# BEP33_6panel.net
KiCad netlist of a schematic drawn in EAGLE
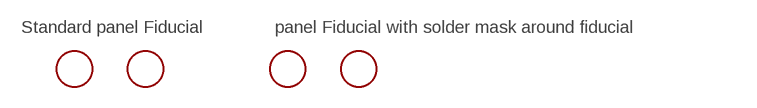
[diagram p0: schematic, sheet 1]
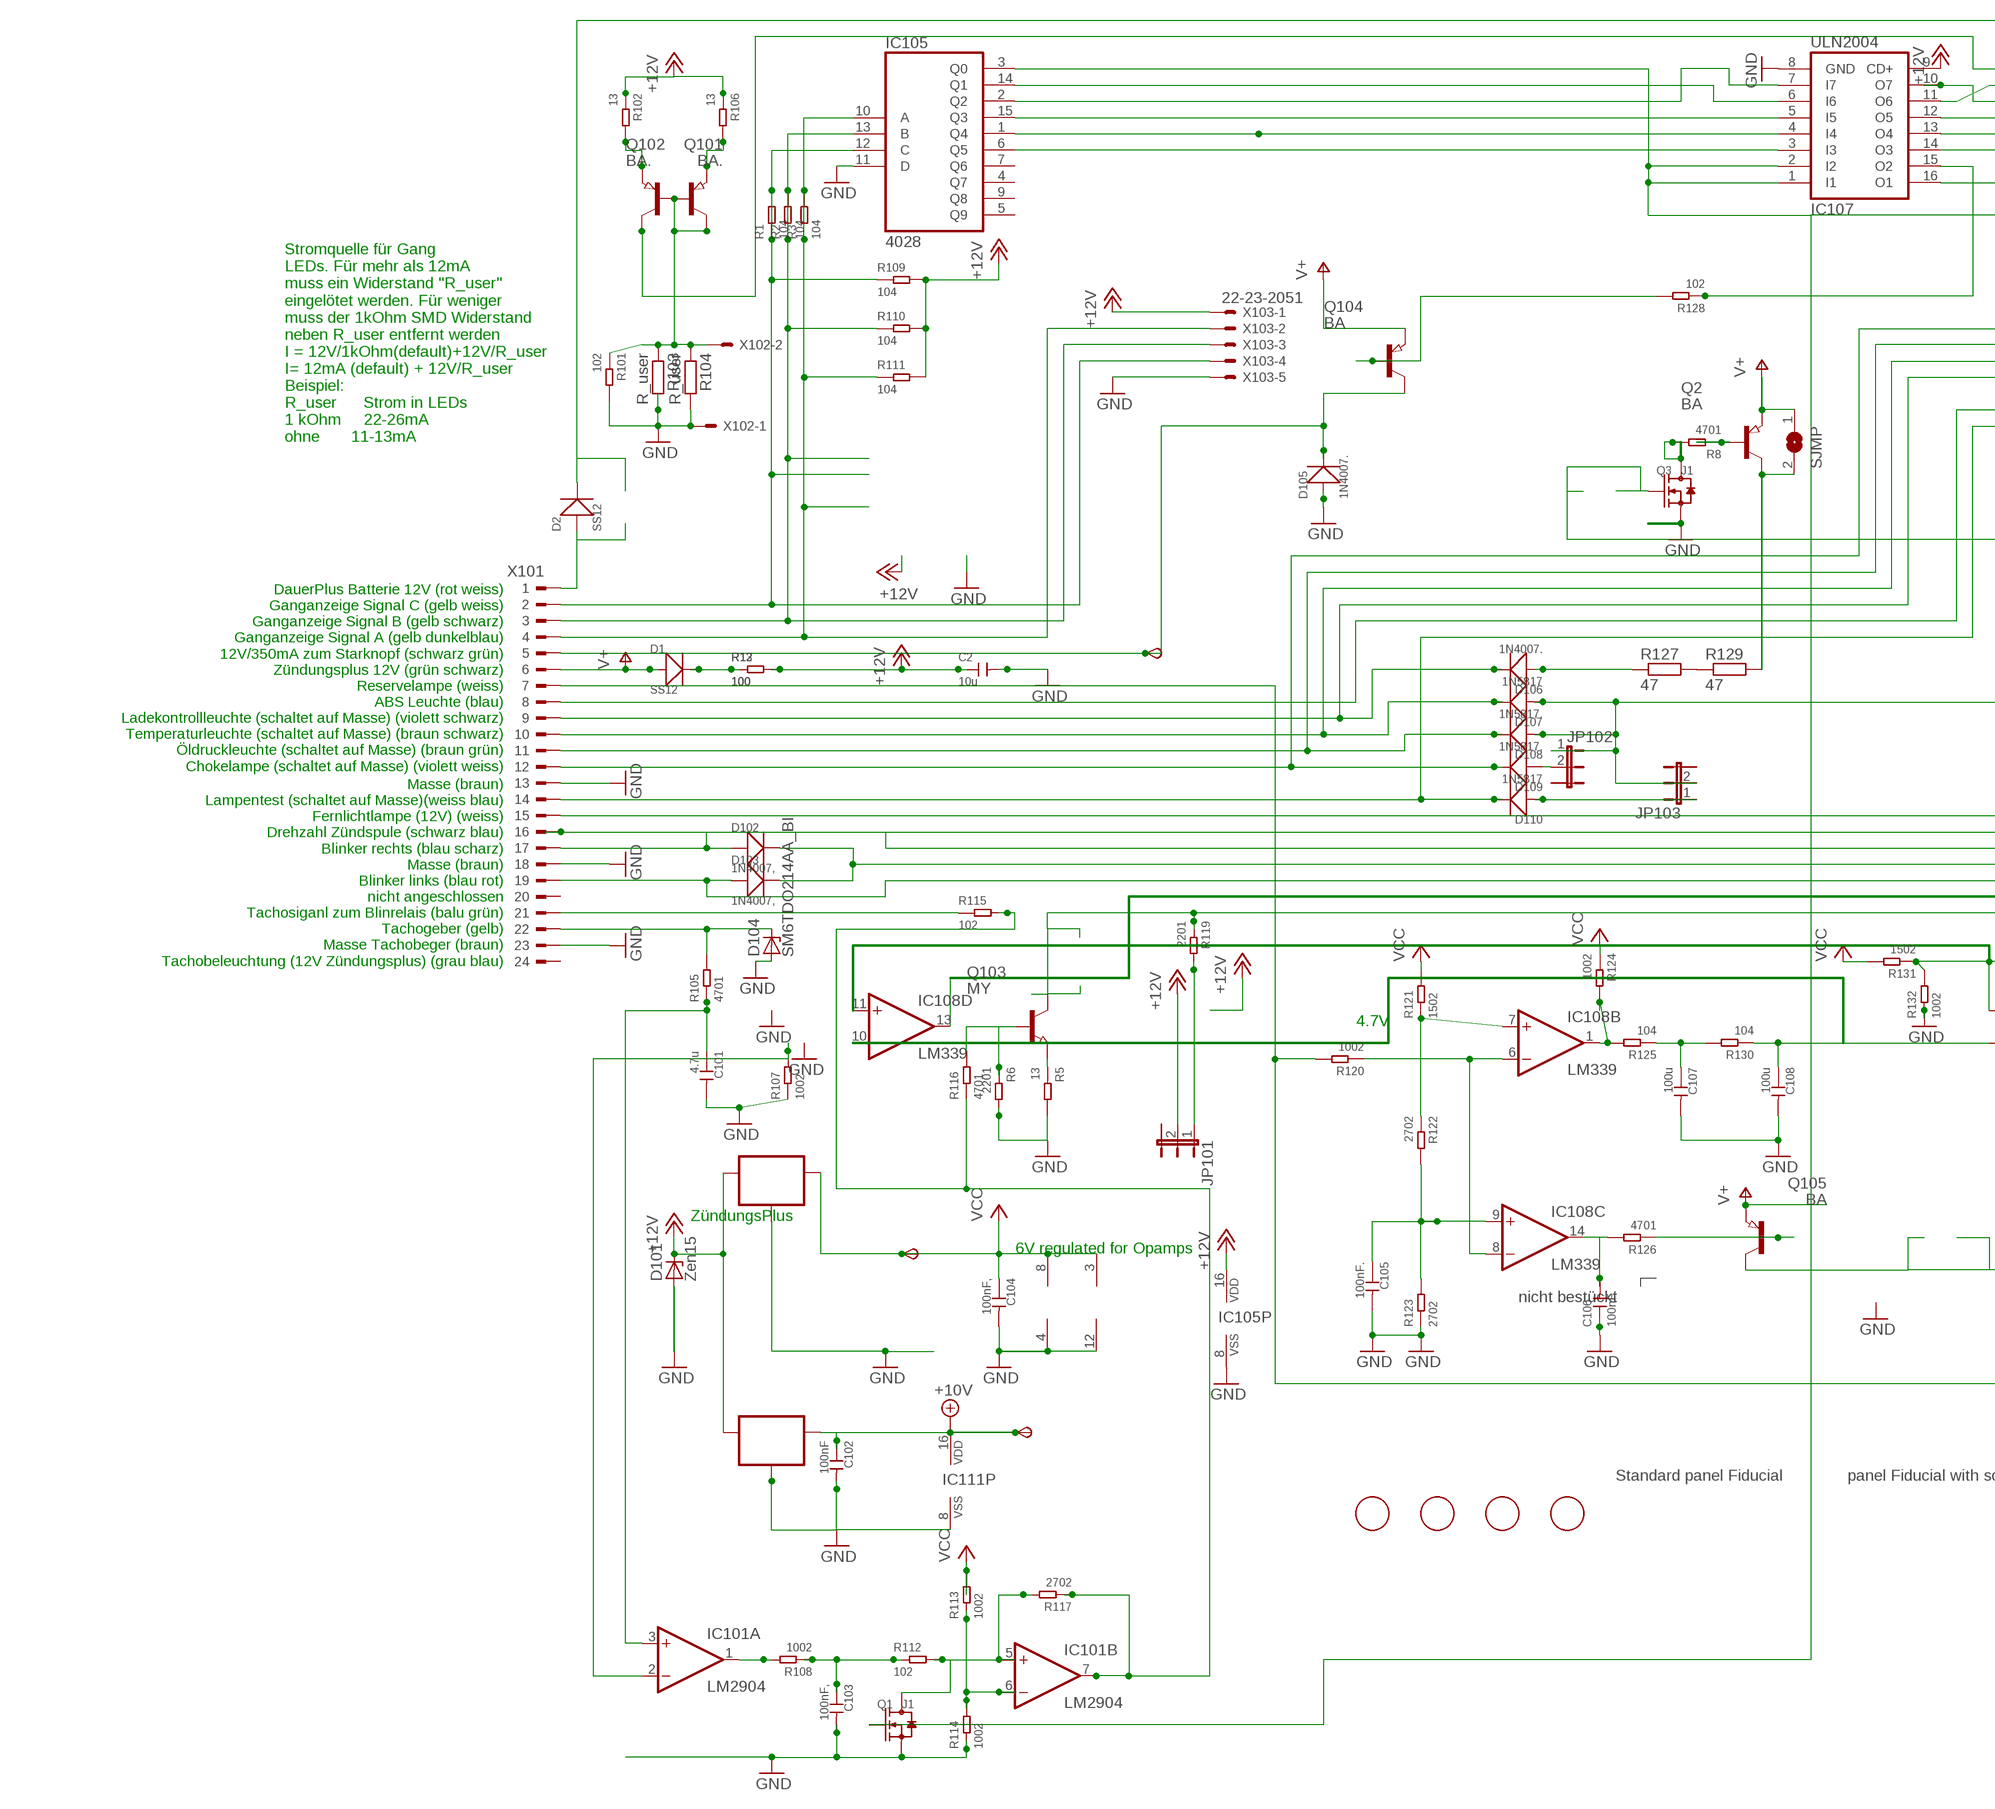
[diagram p1: schematic, sheet 2, part 1 of 2]
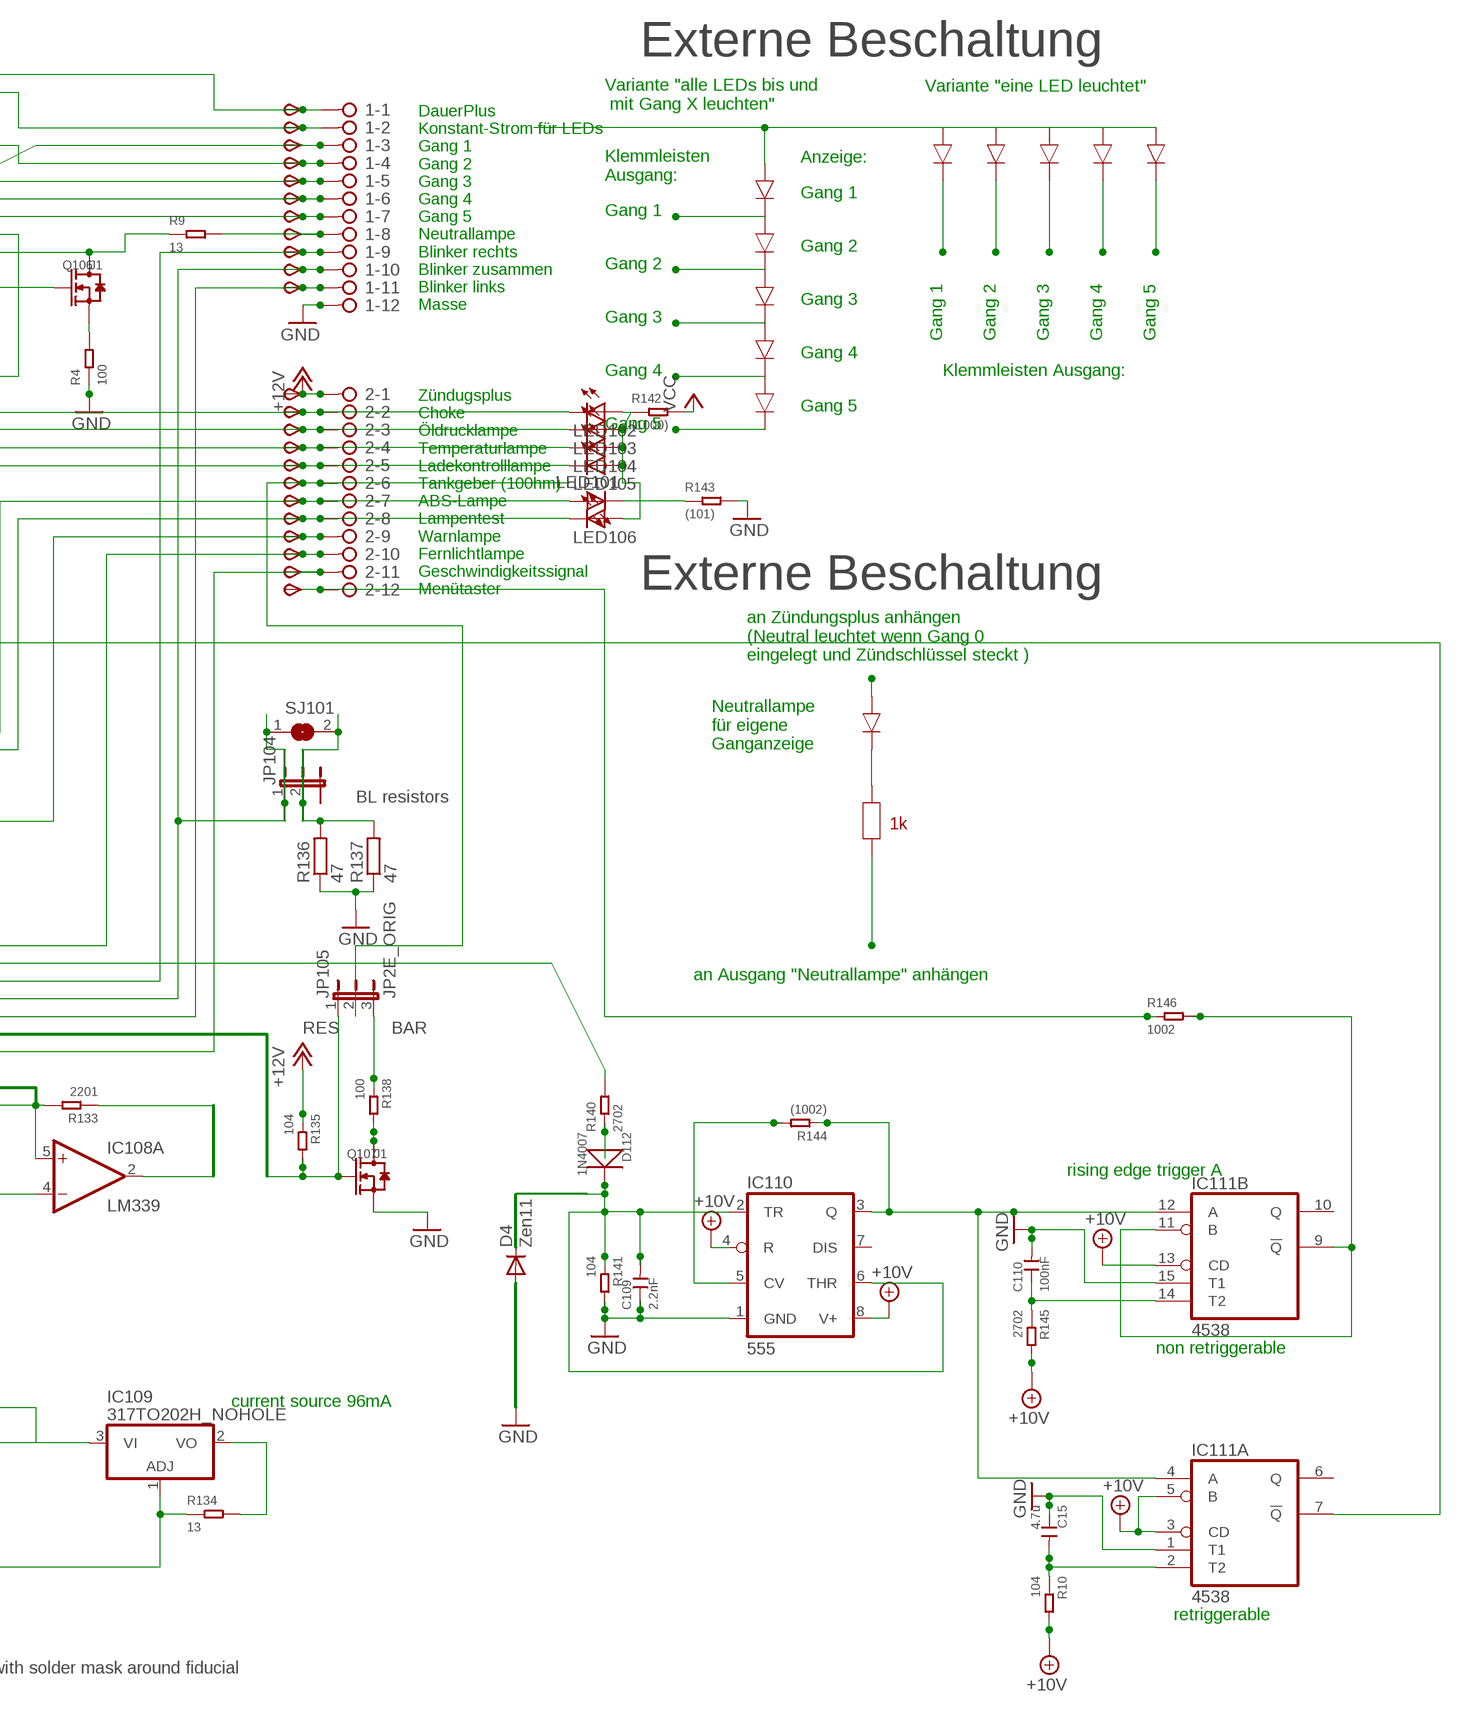
[diagram p2: schematic, sheet 2, part 2 of 2]
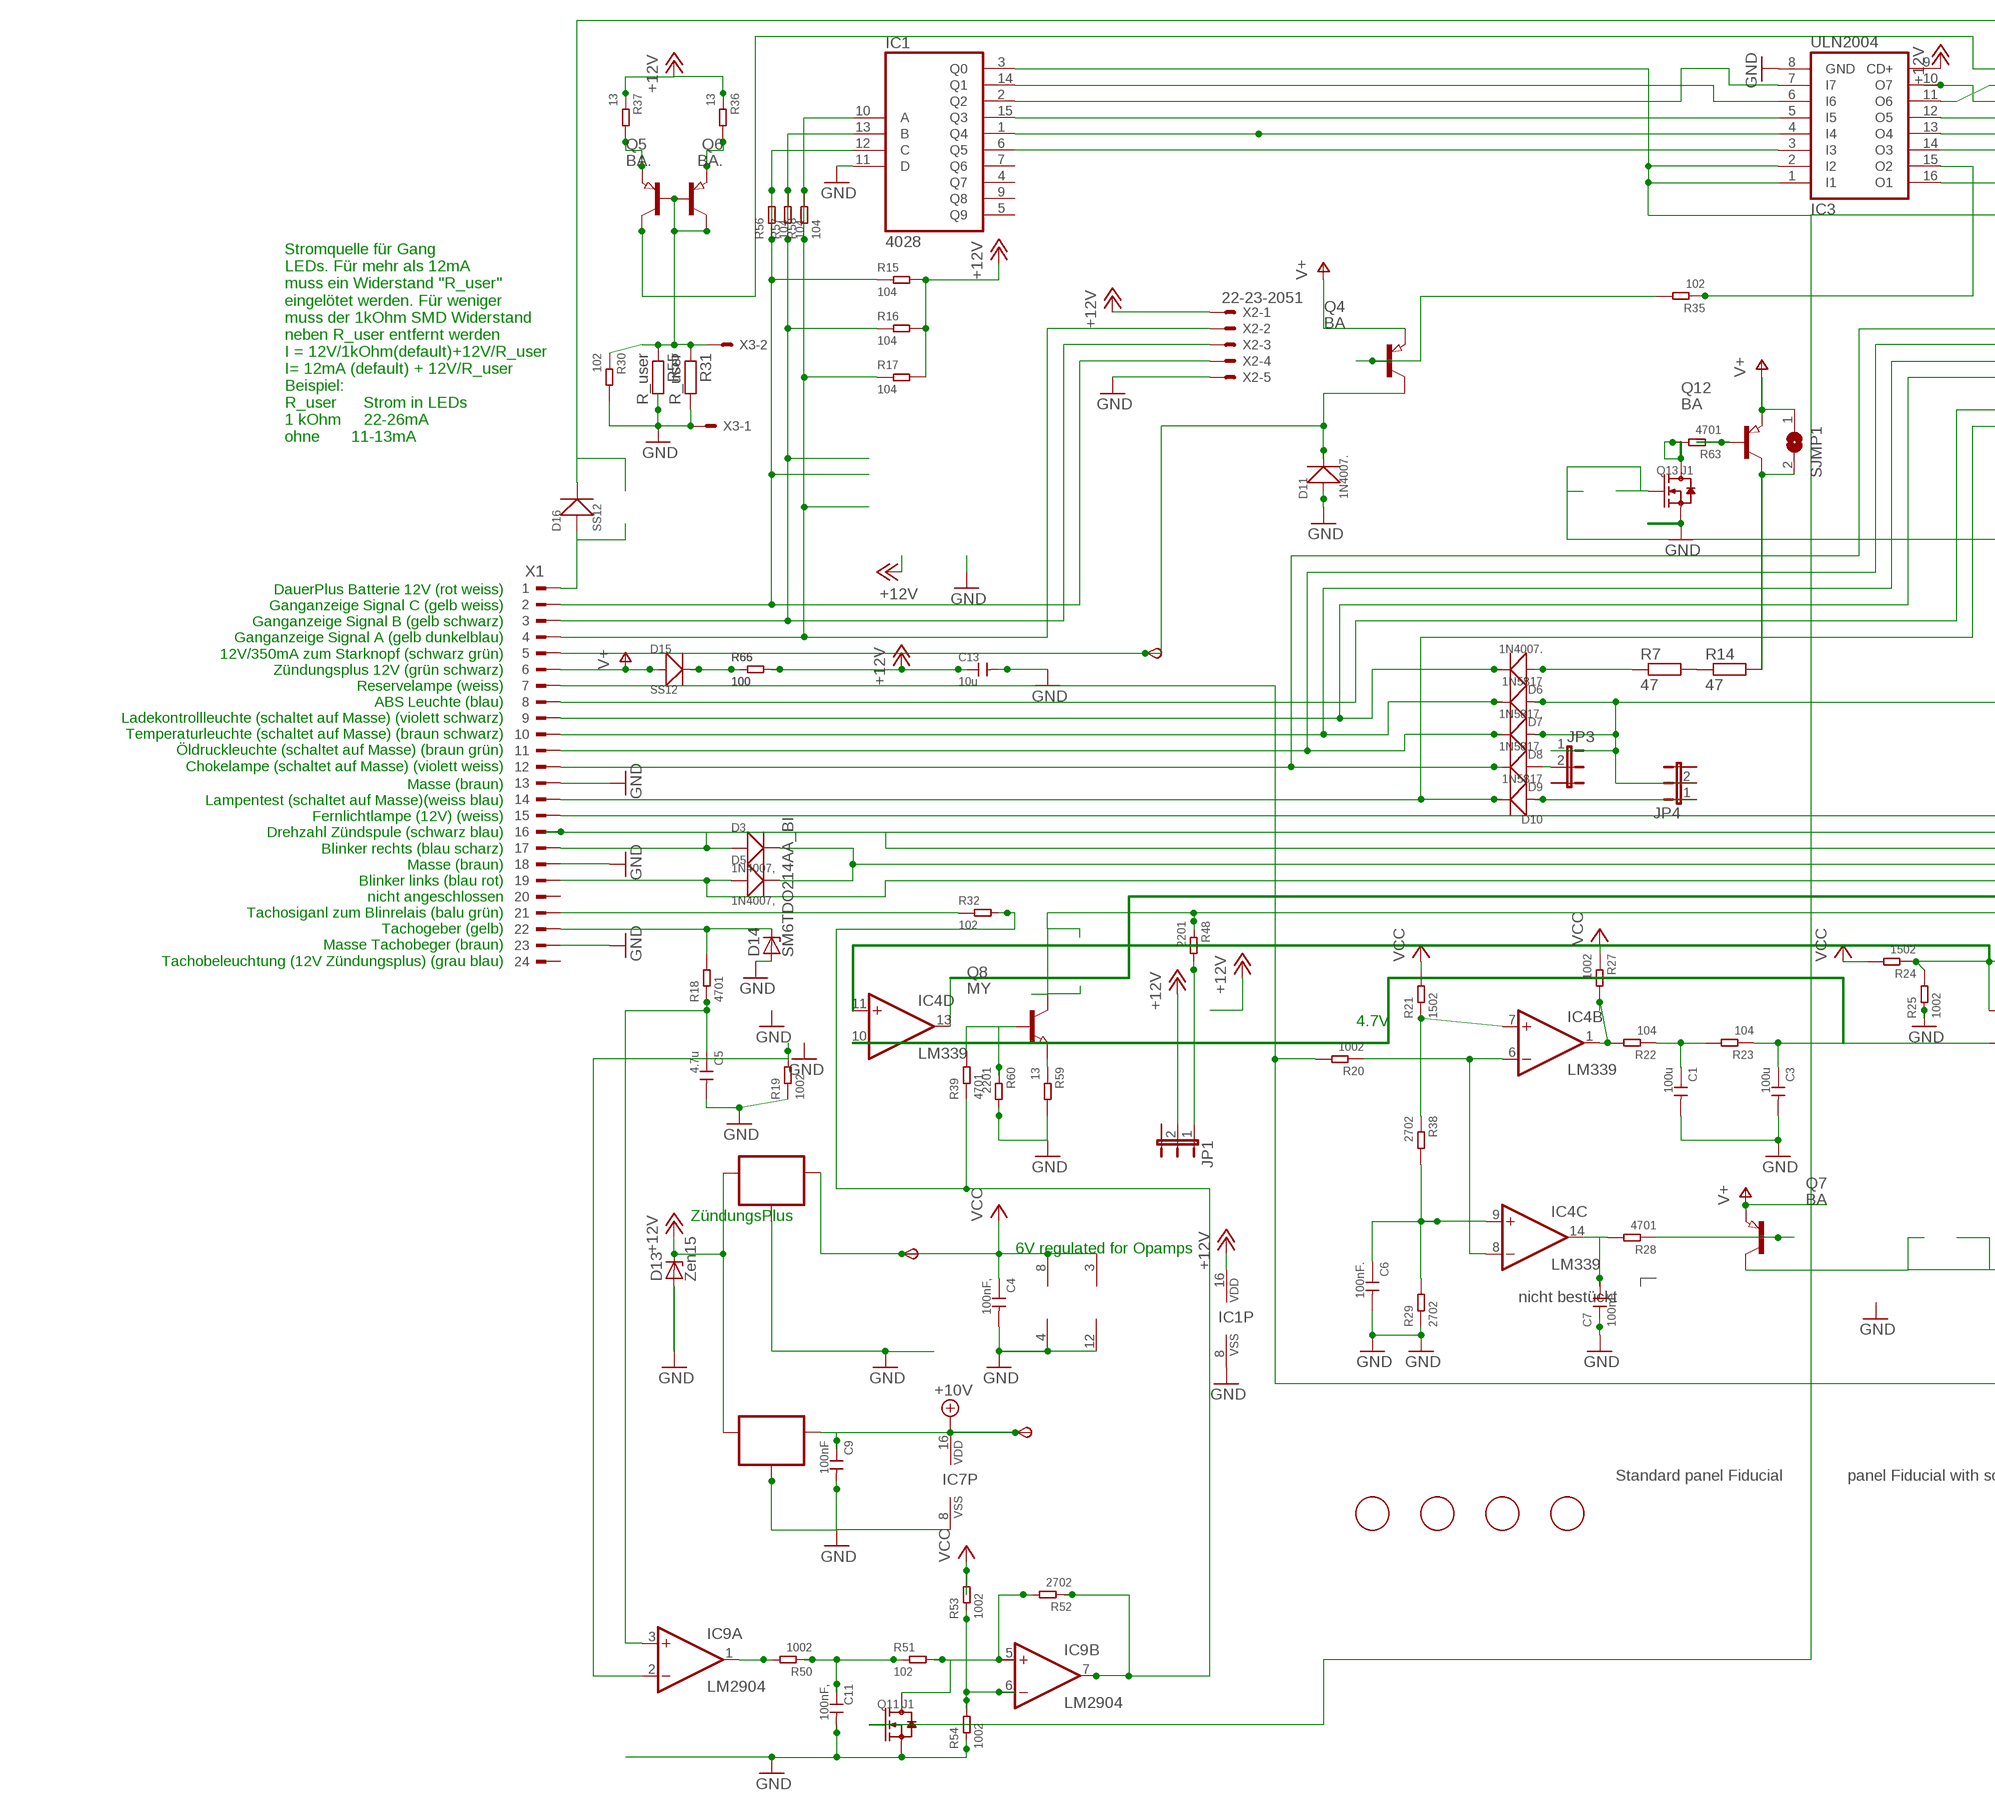
[diagram p3: schematic, sheet 3, part 1 of 2]
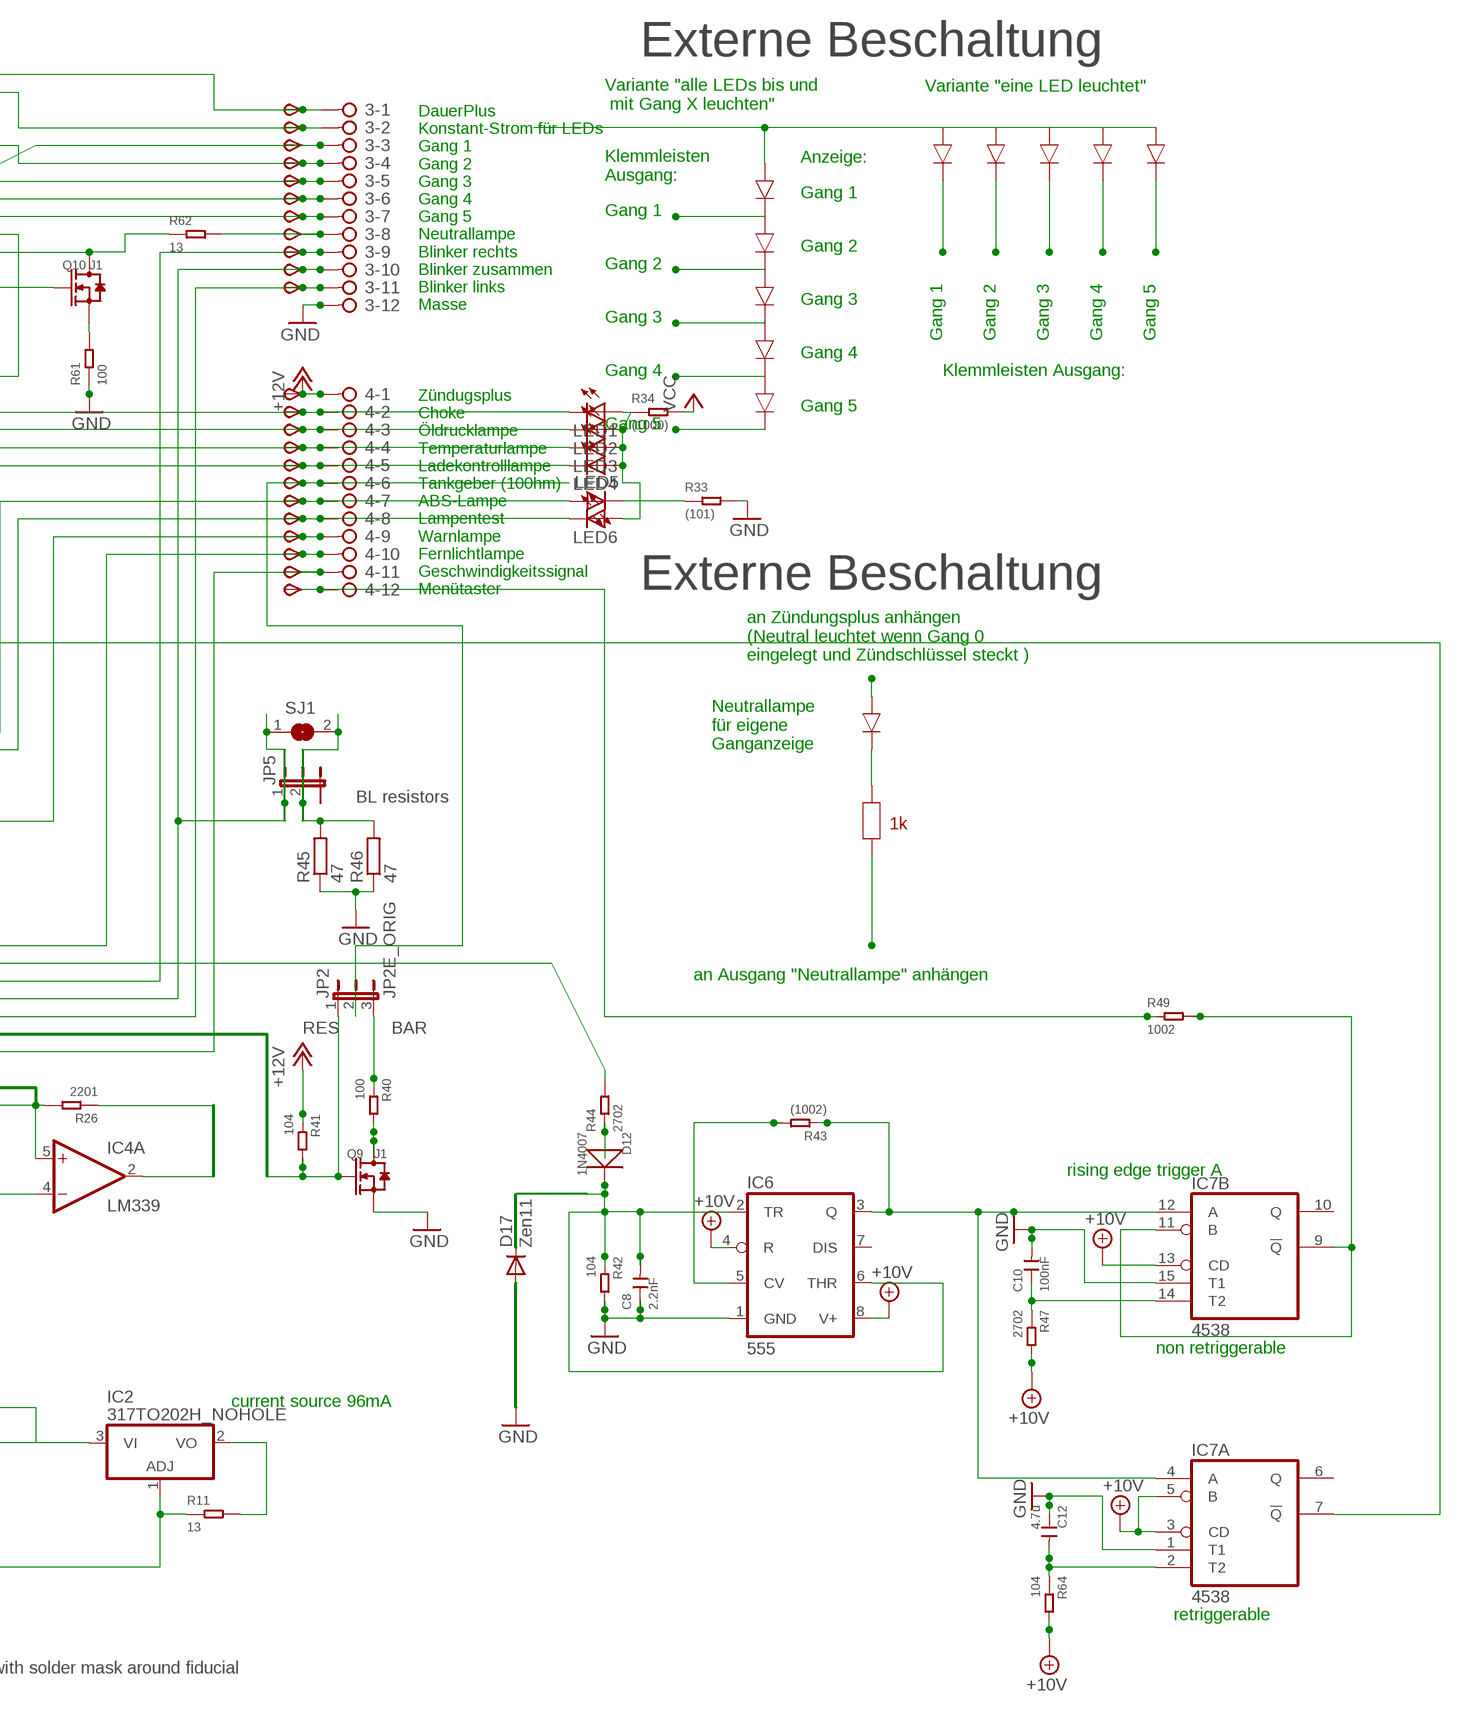
[diagram p4: schematic, sheet 3, part 2 of 2]
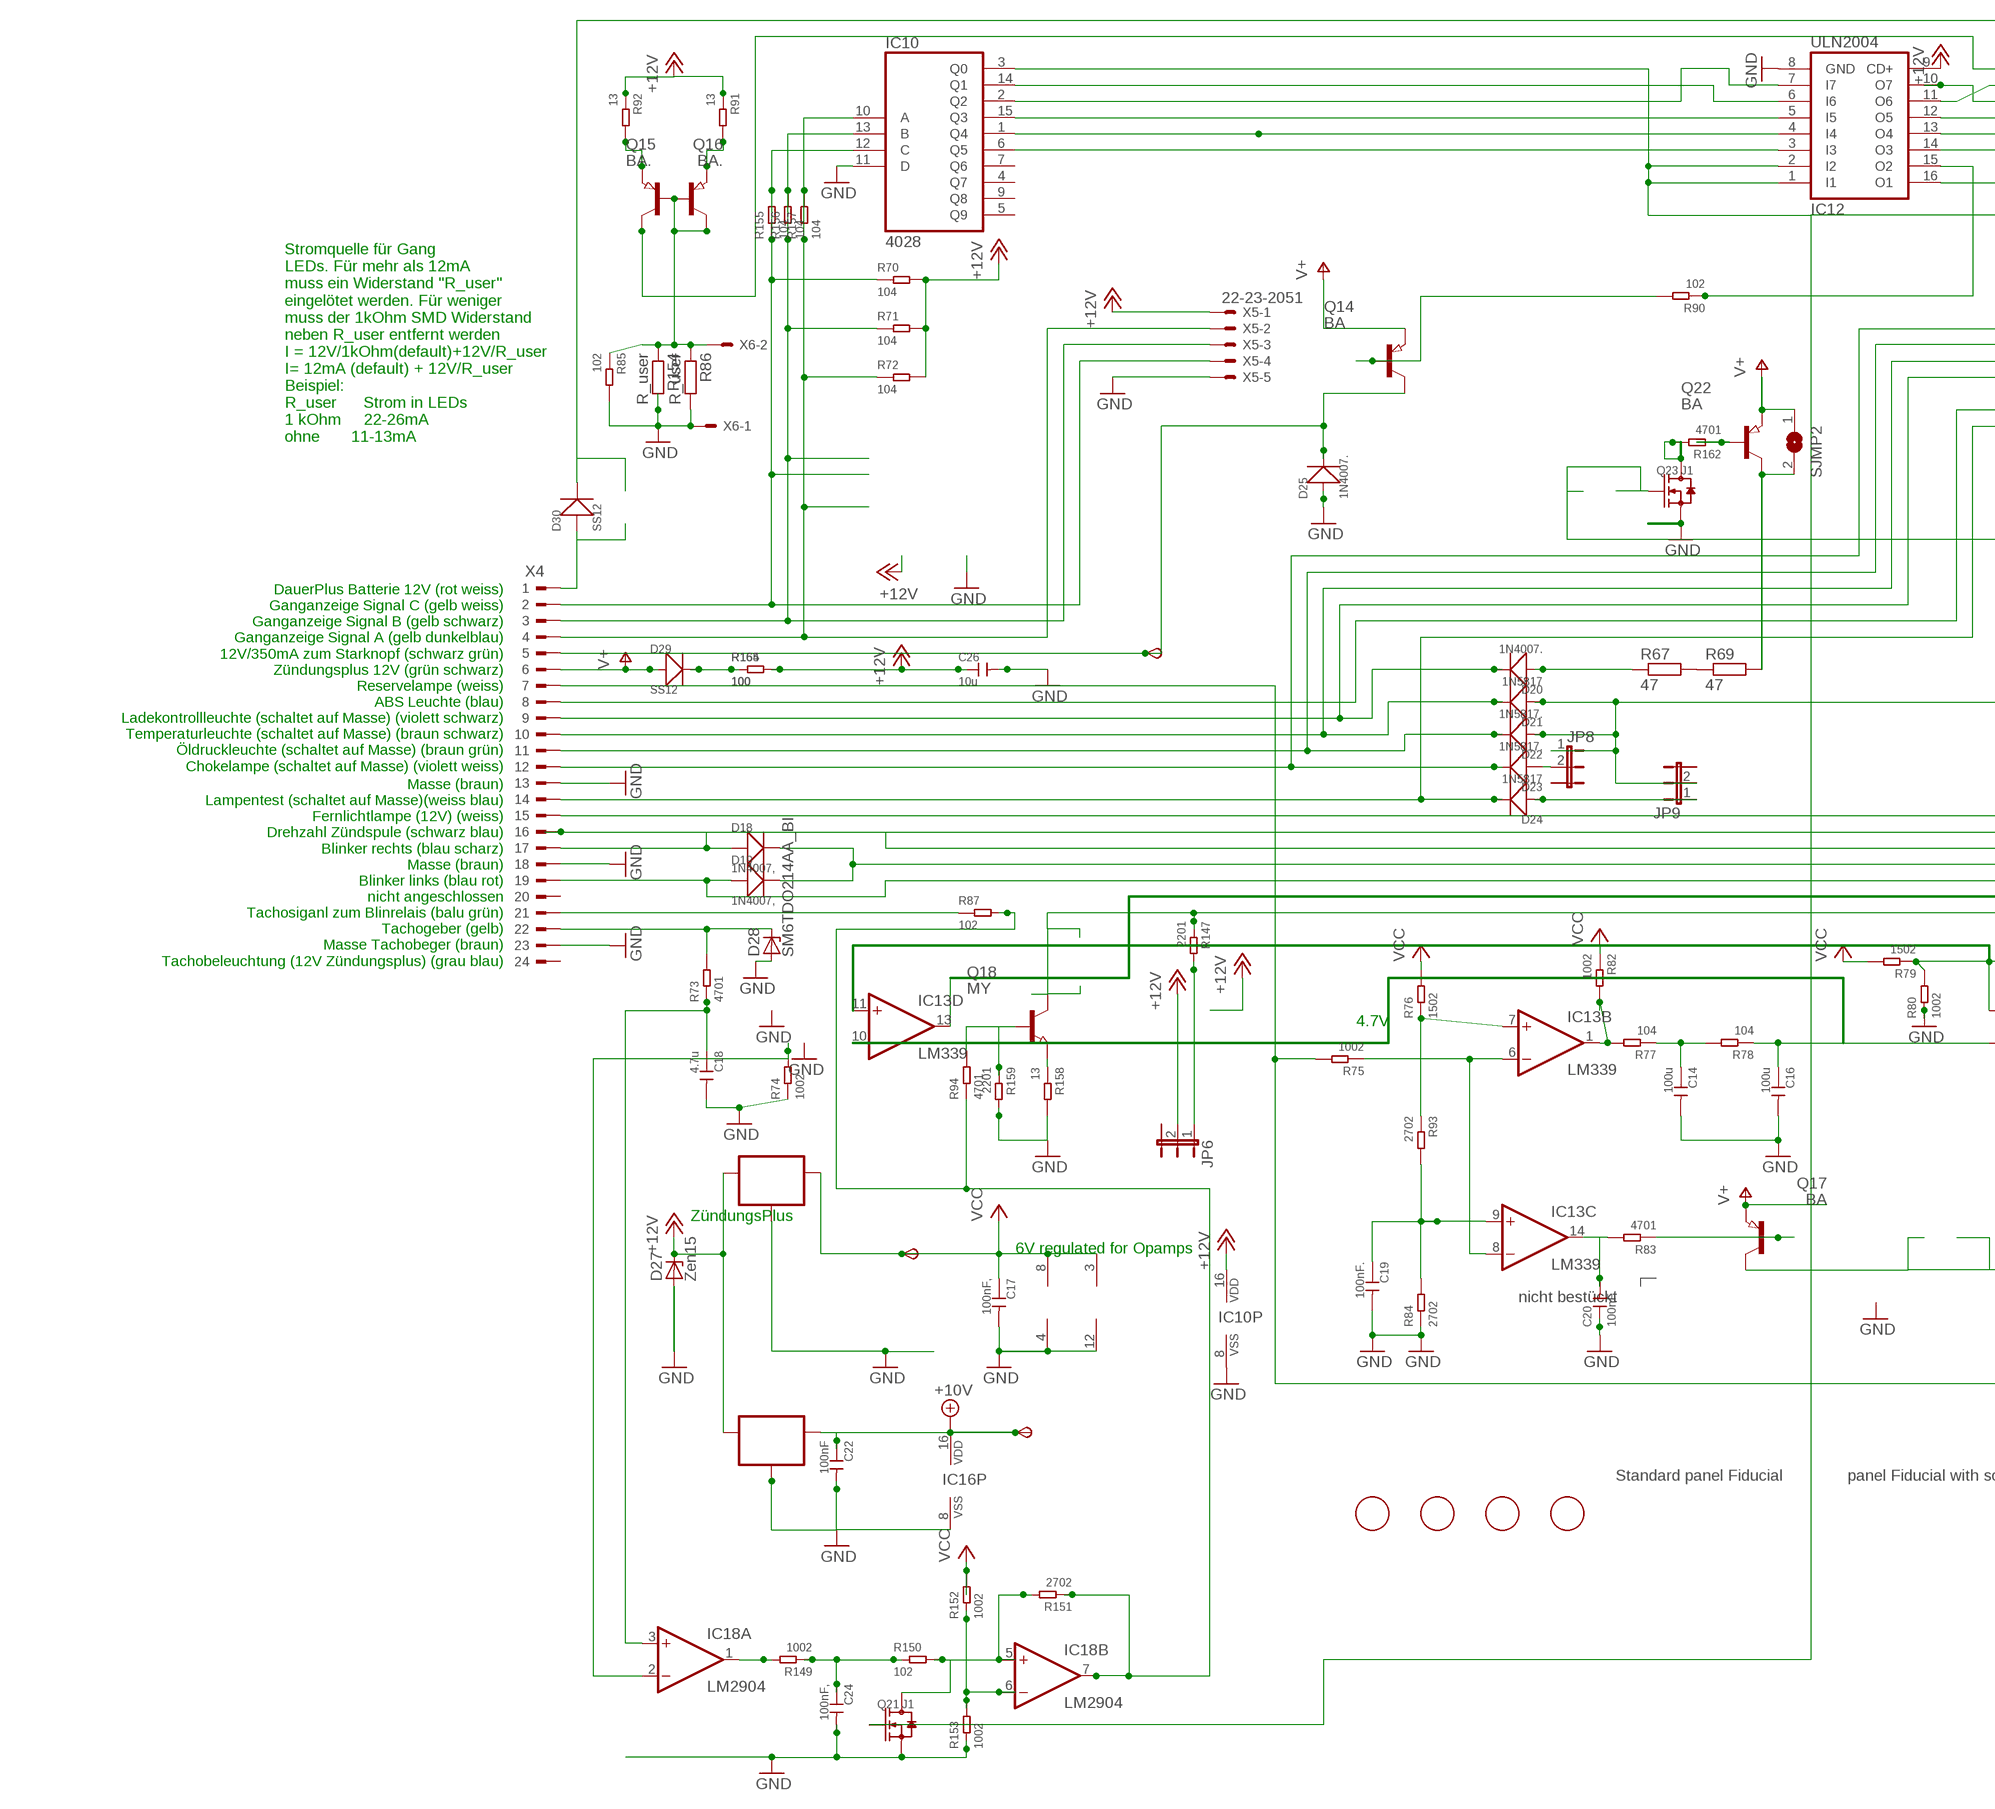
[diagram p5: schematic, sheet 4, part 1 of 2]
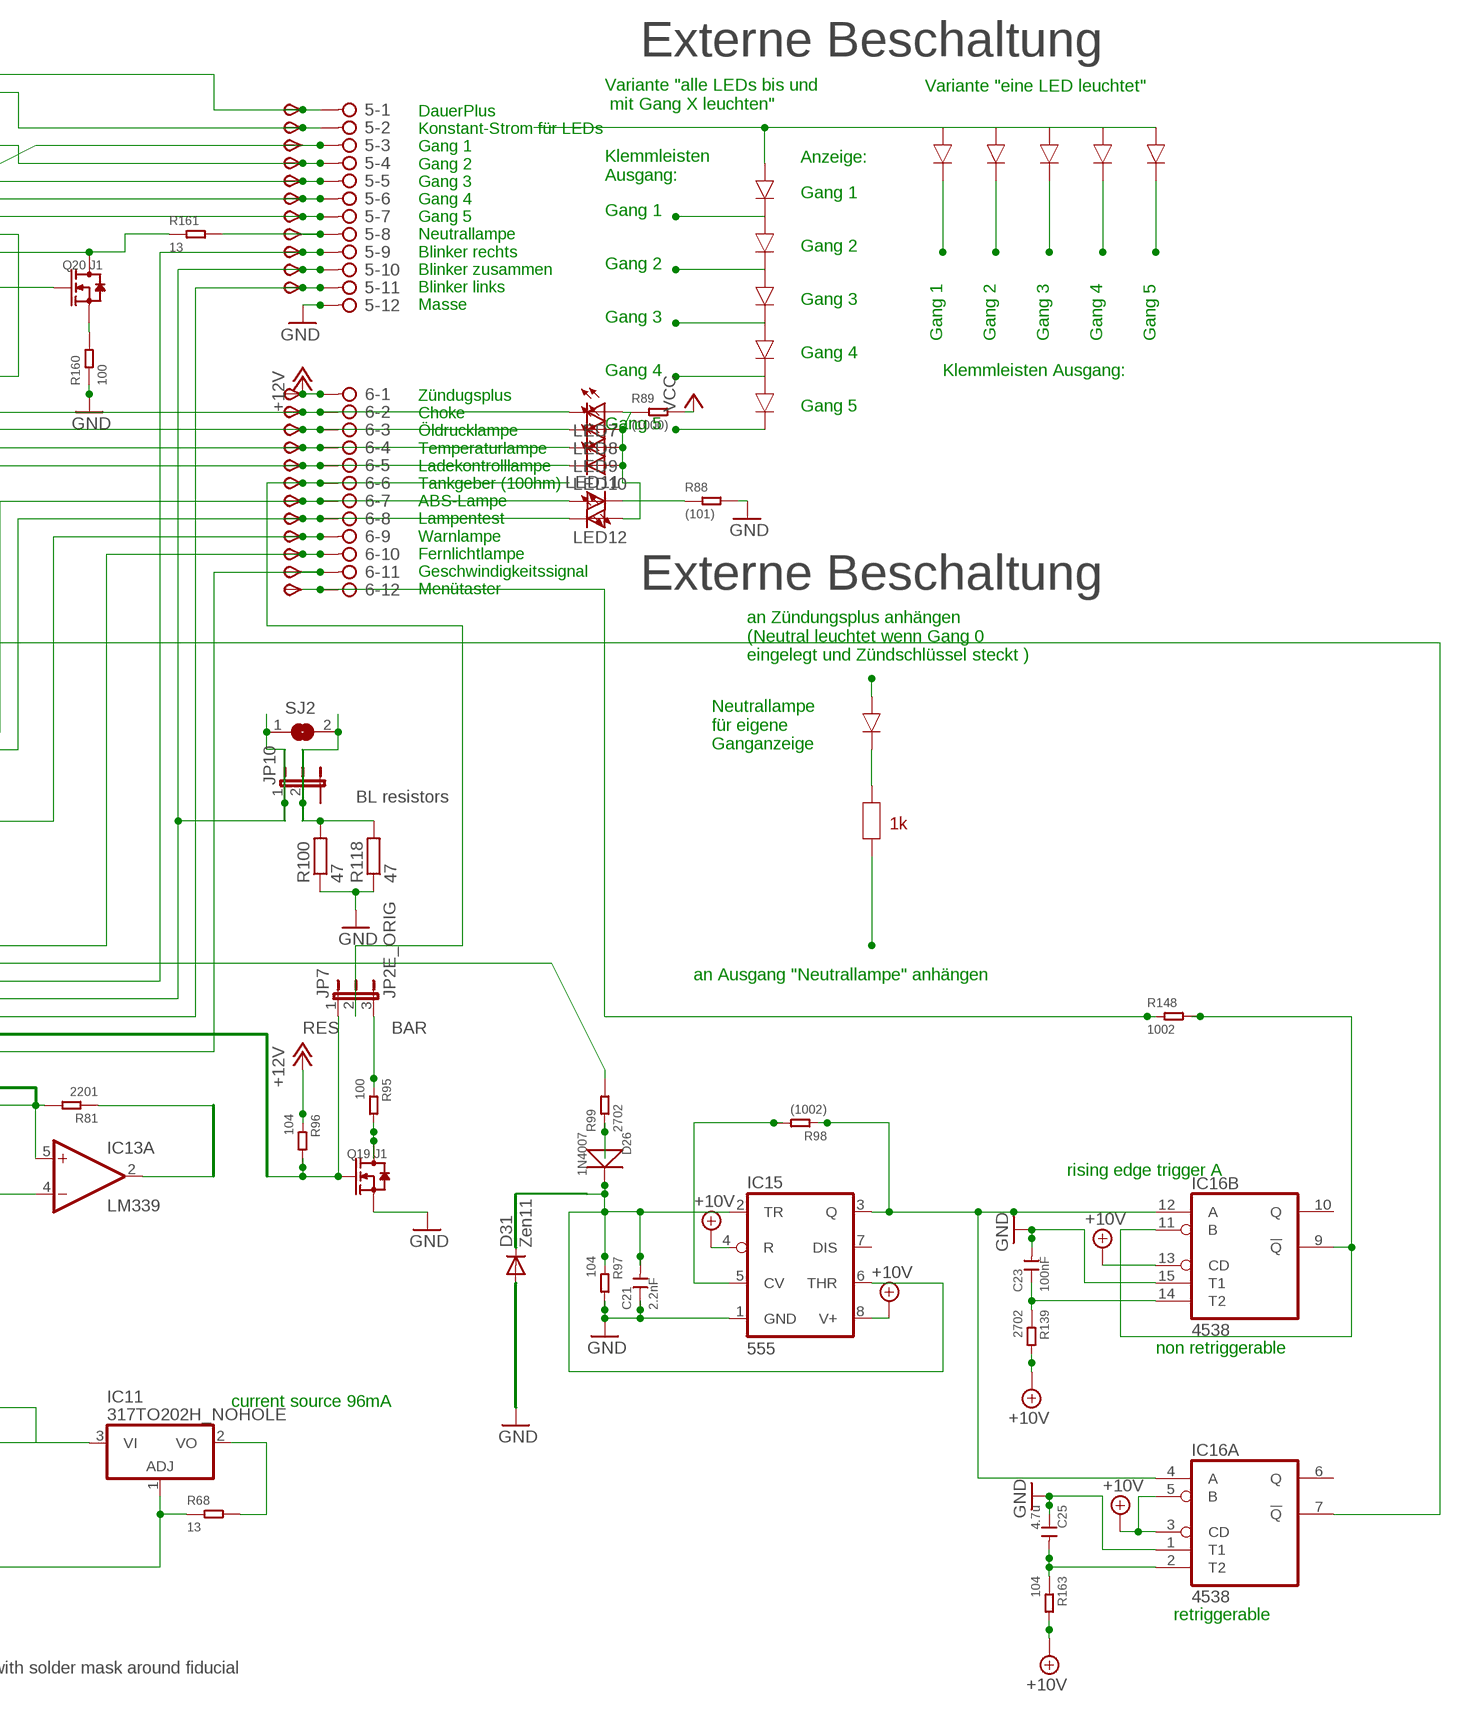
[diagram p6: schematic, sheet 4, part 2 of 2]
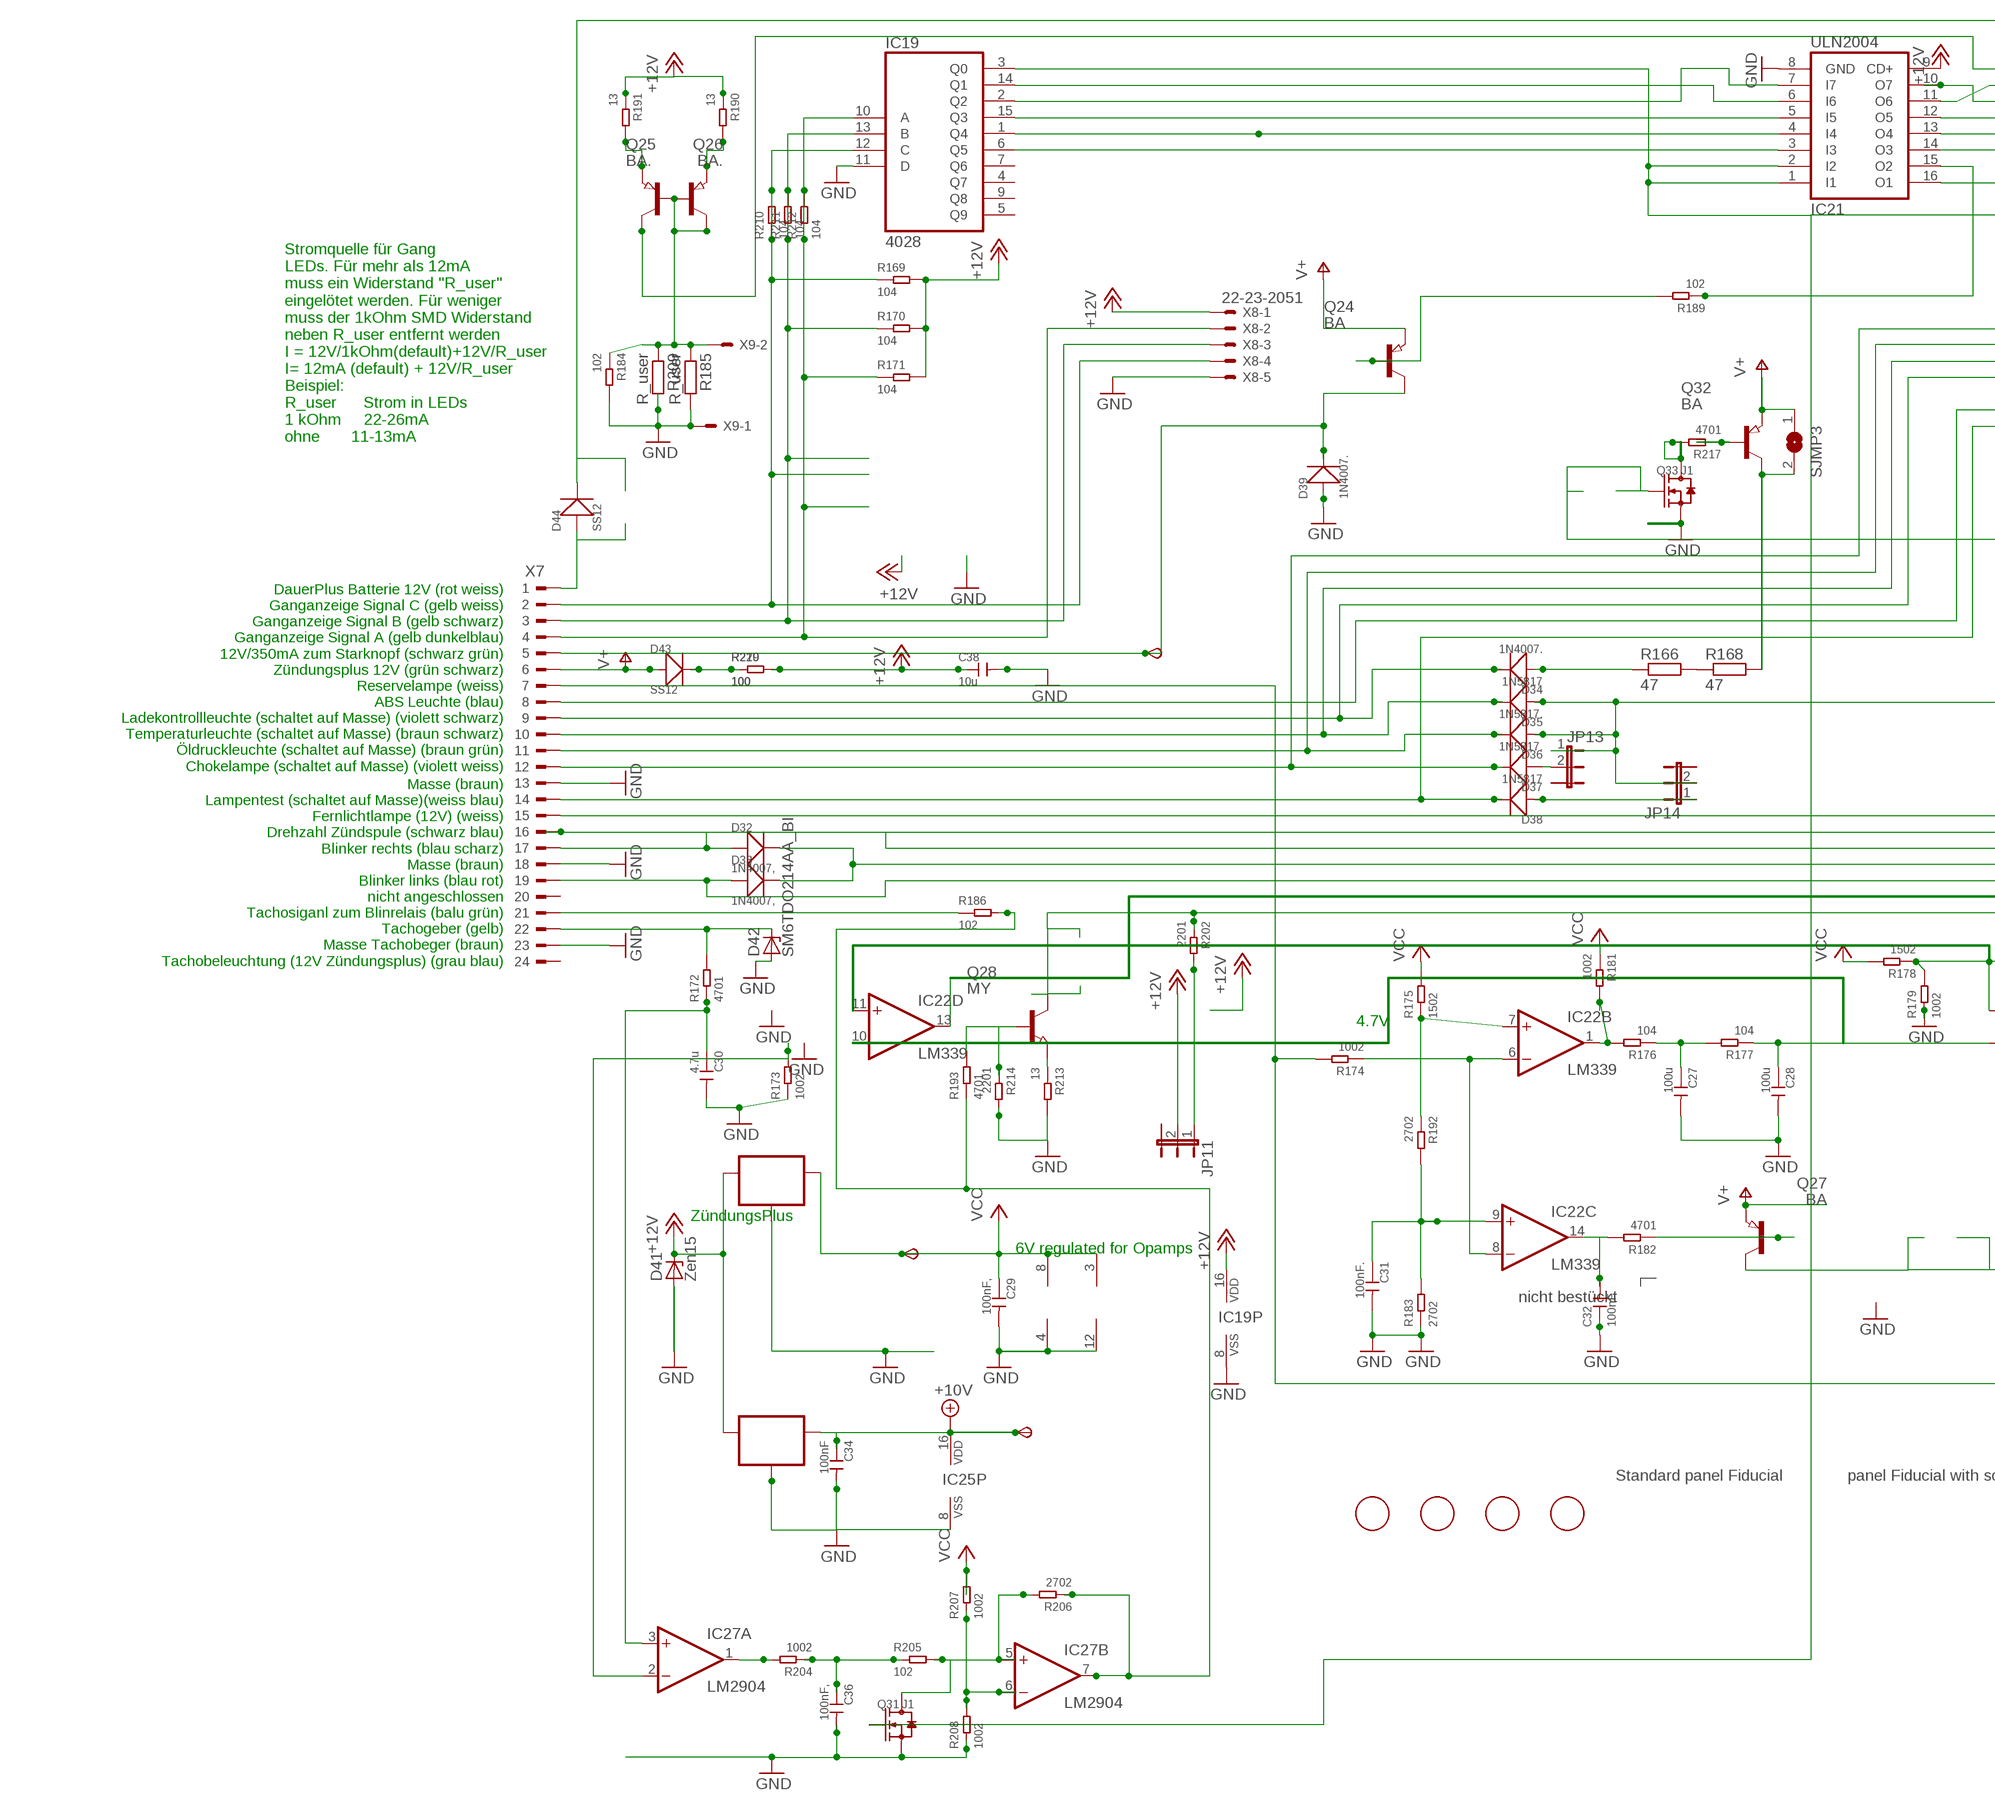
[diagram p7: schematic, sheet 5, part 1 of 2]
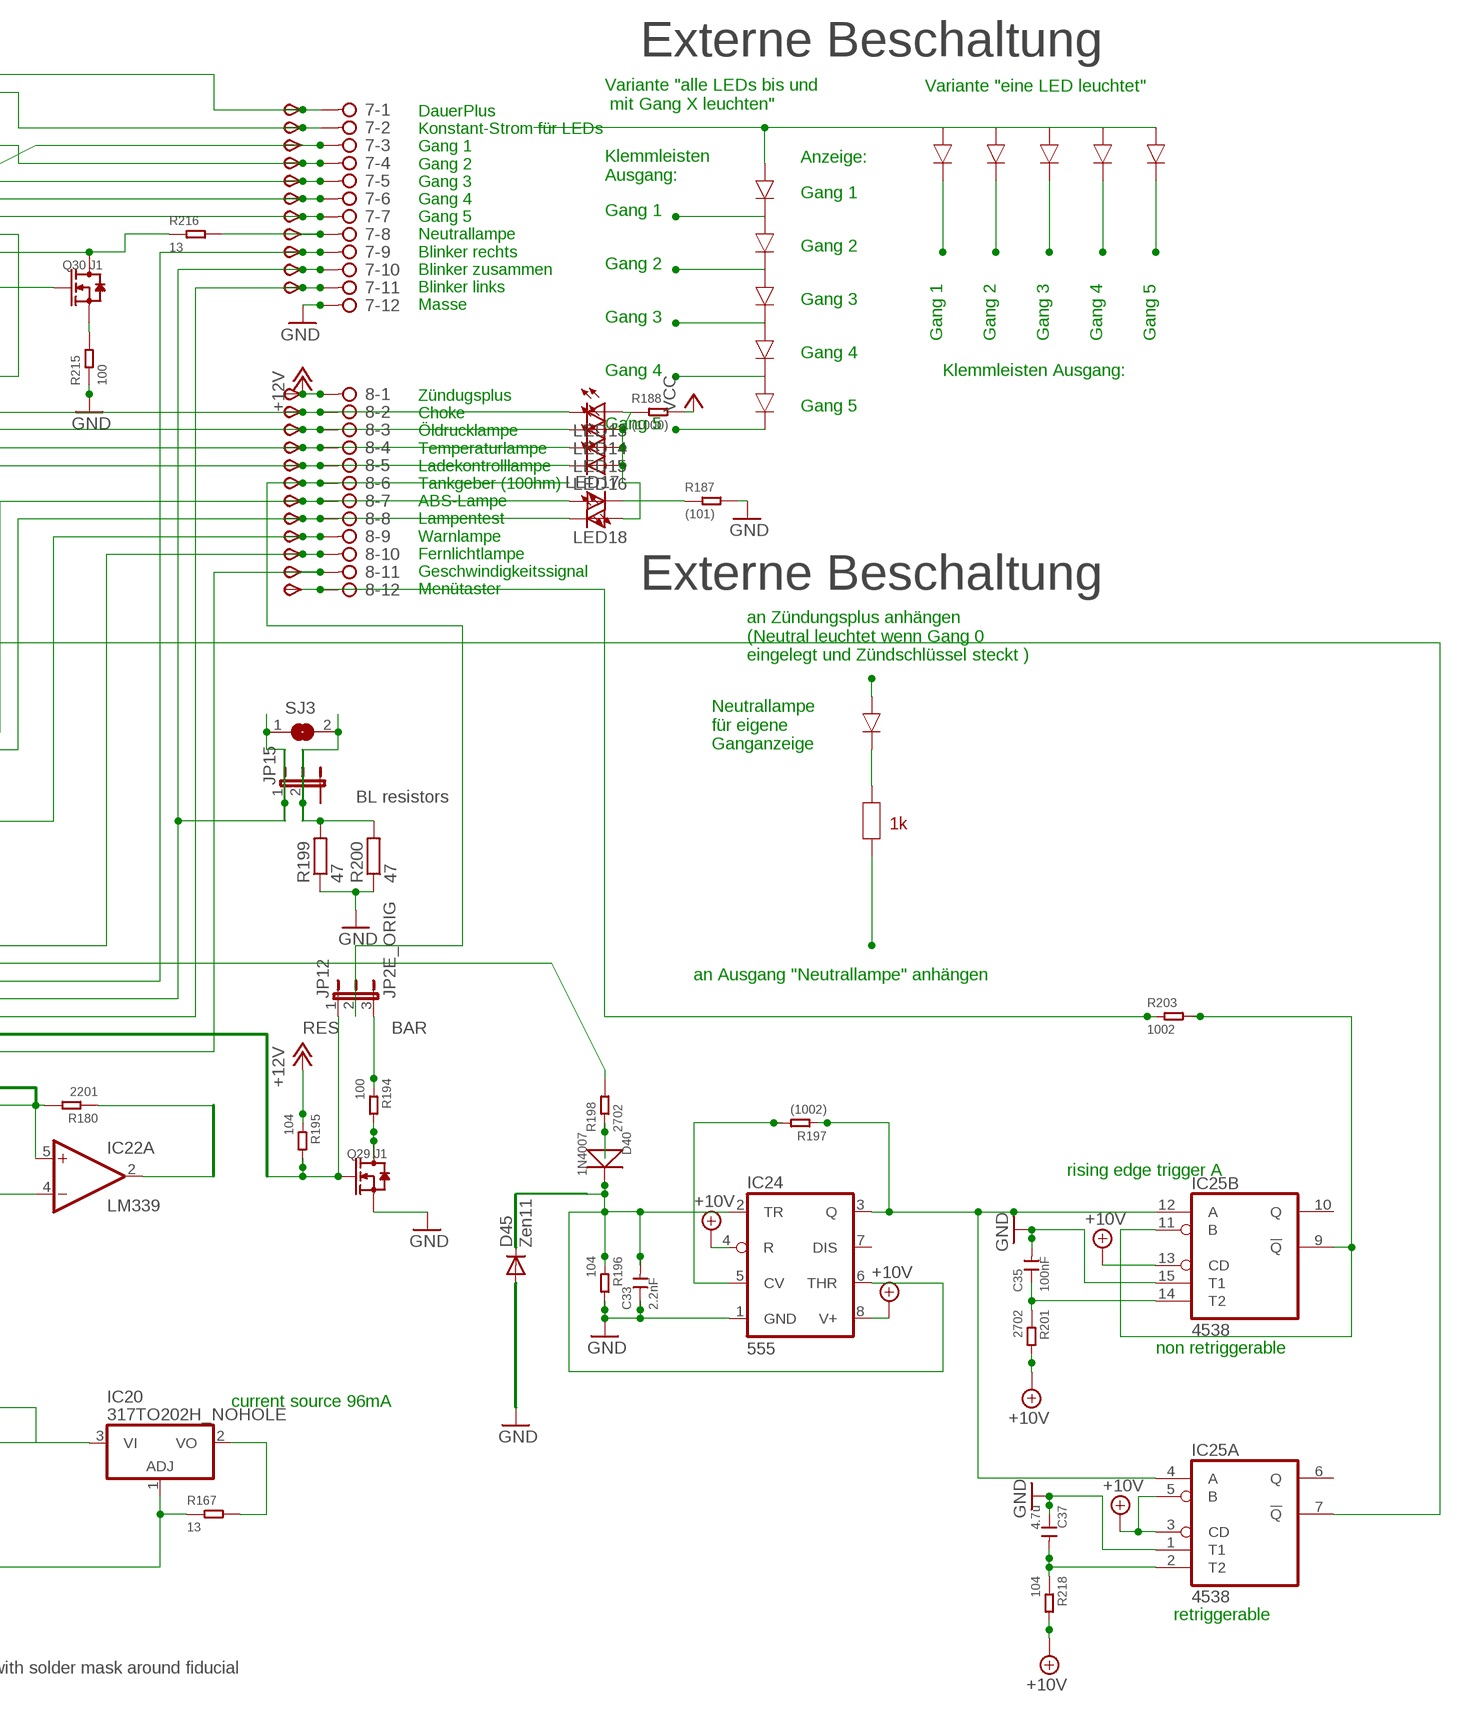
[diagram p8: schematic, sheet 5, part 2 of 2]
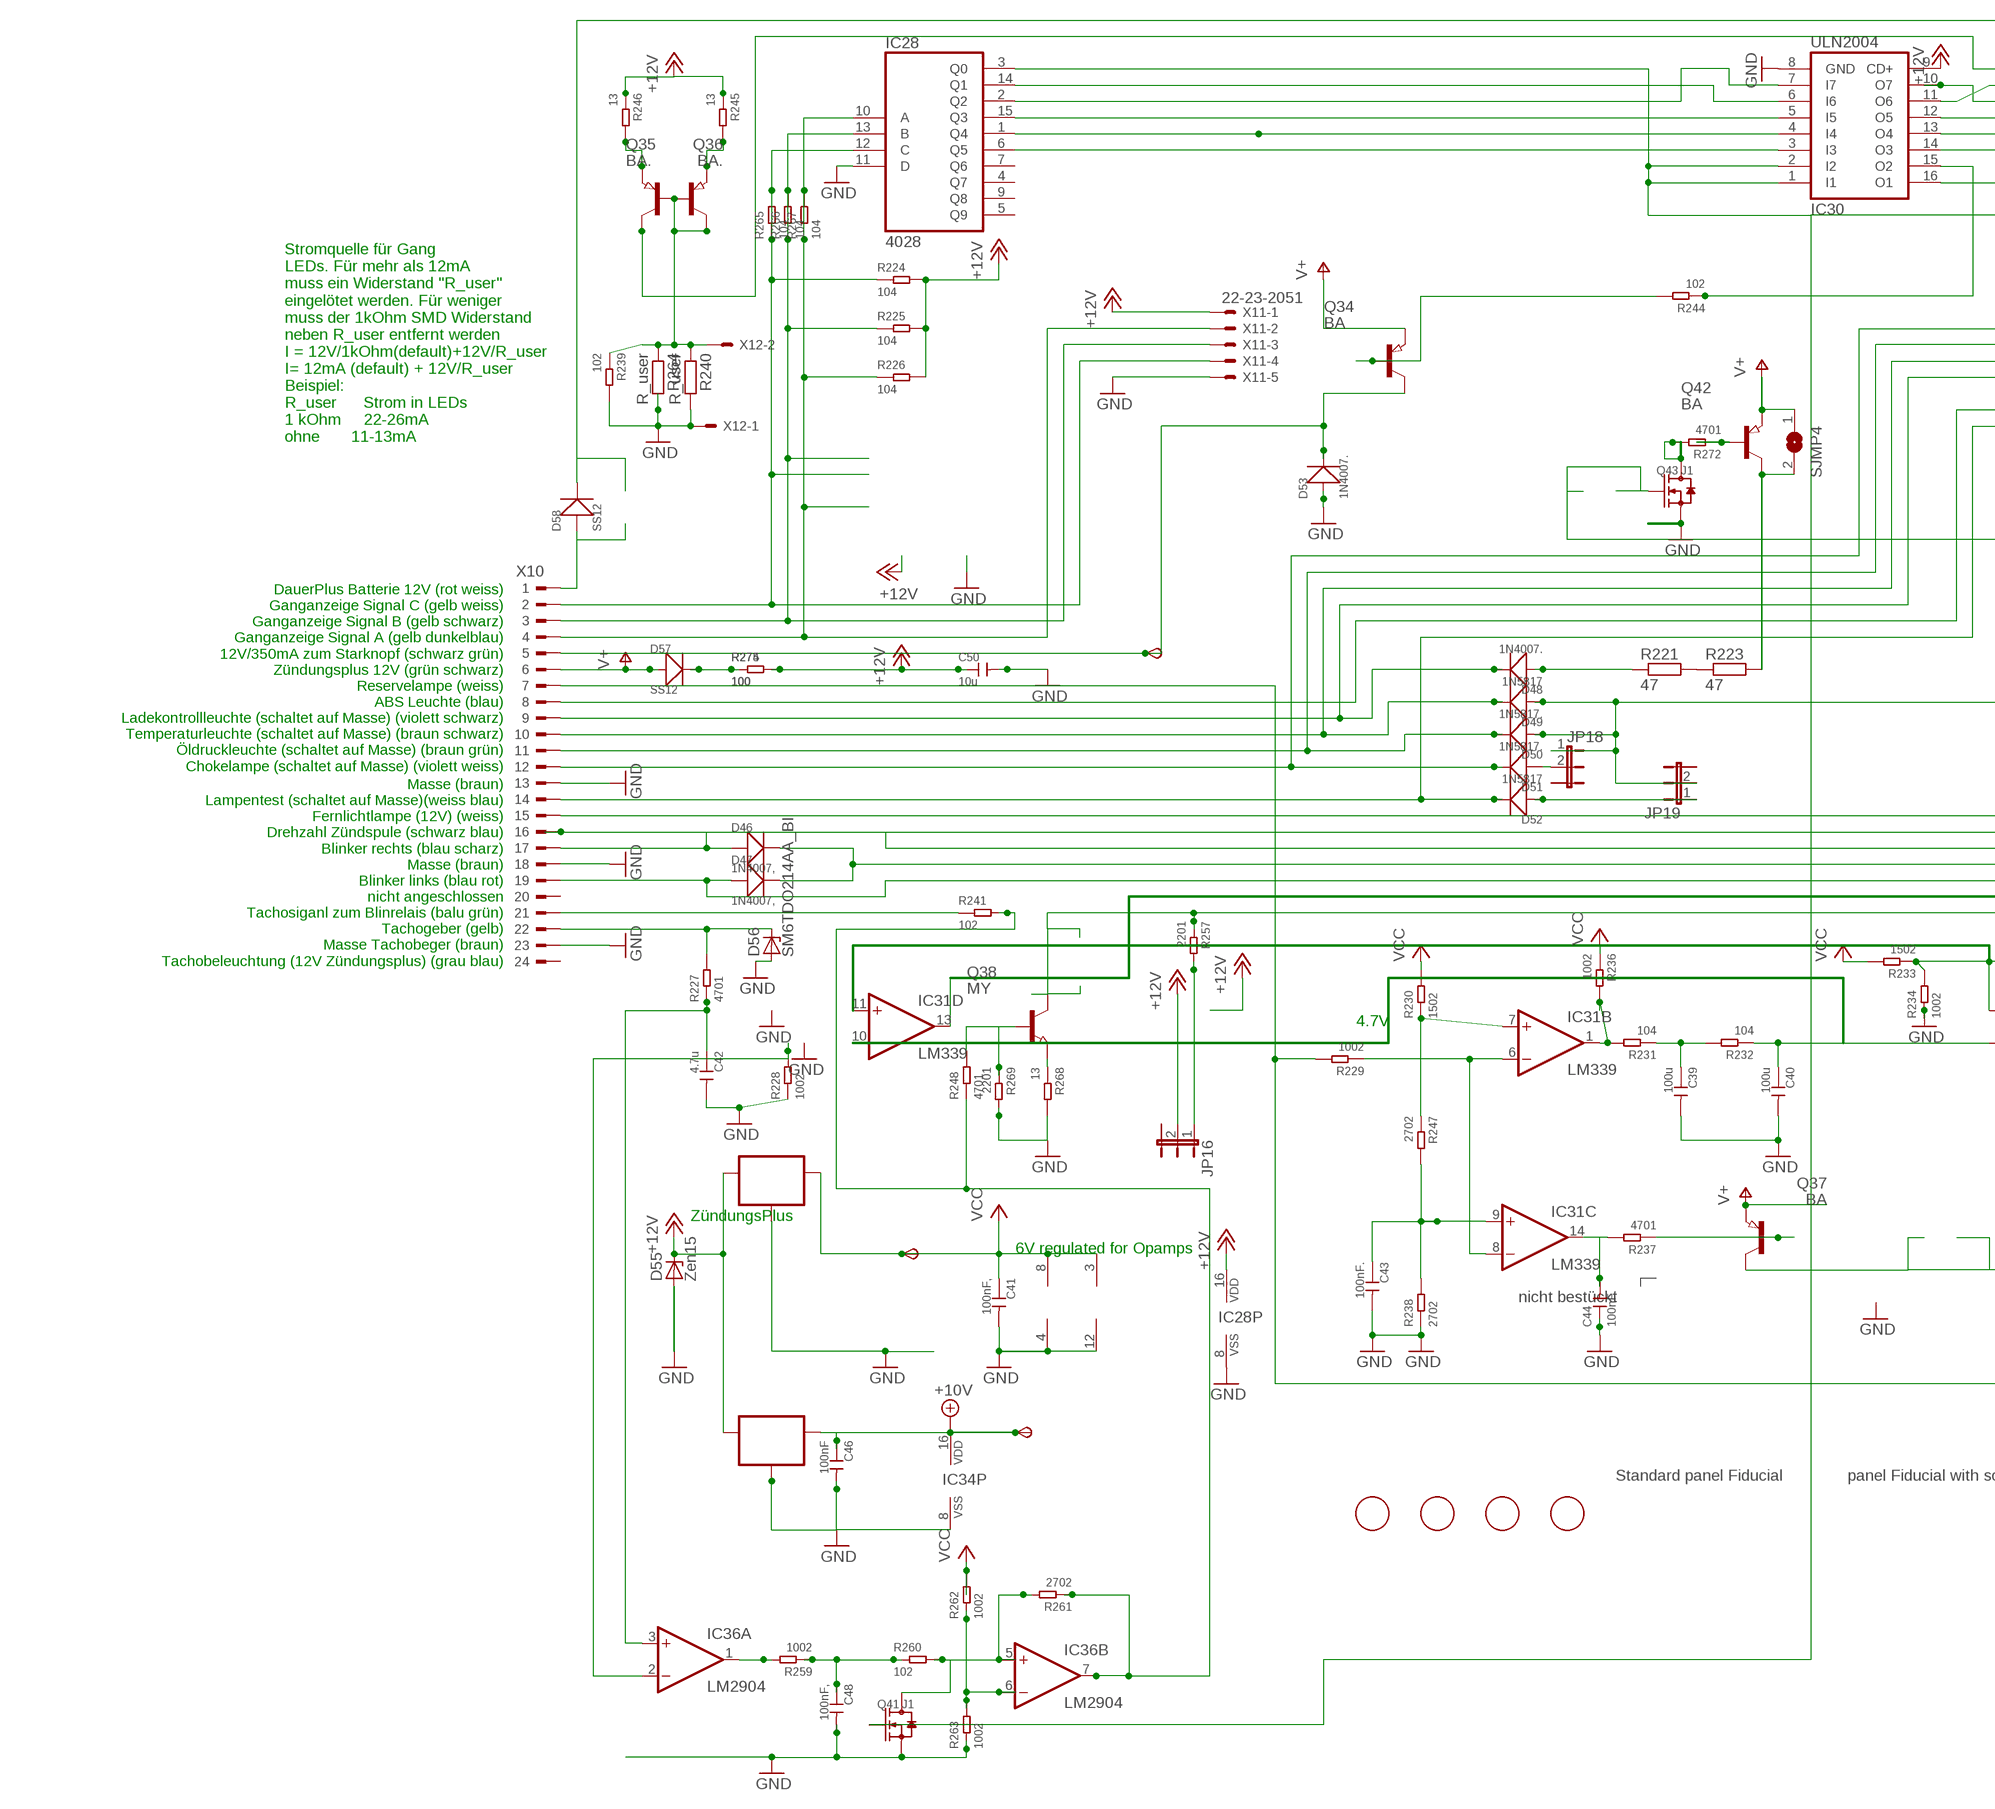
[diagram p9: schematic, sheet 6, part 1 of 2]
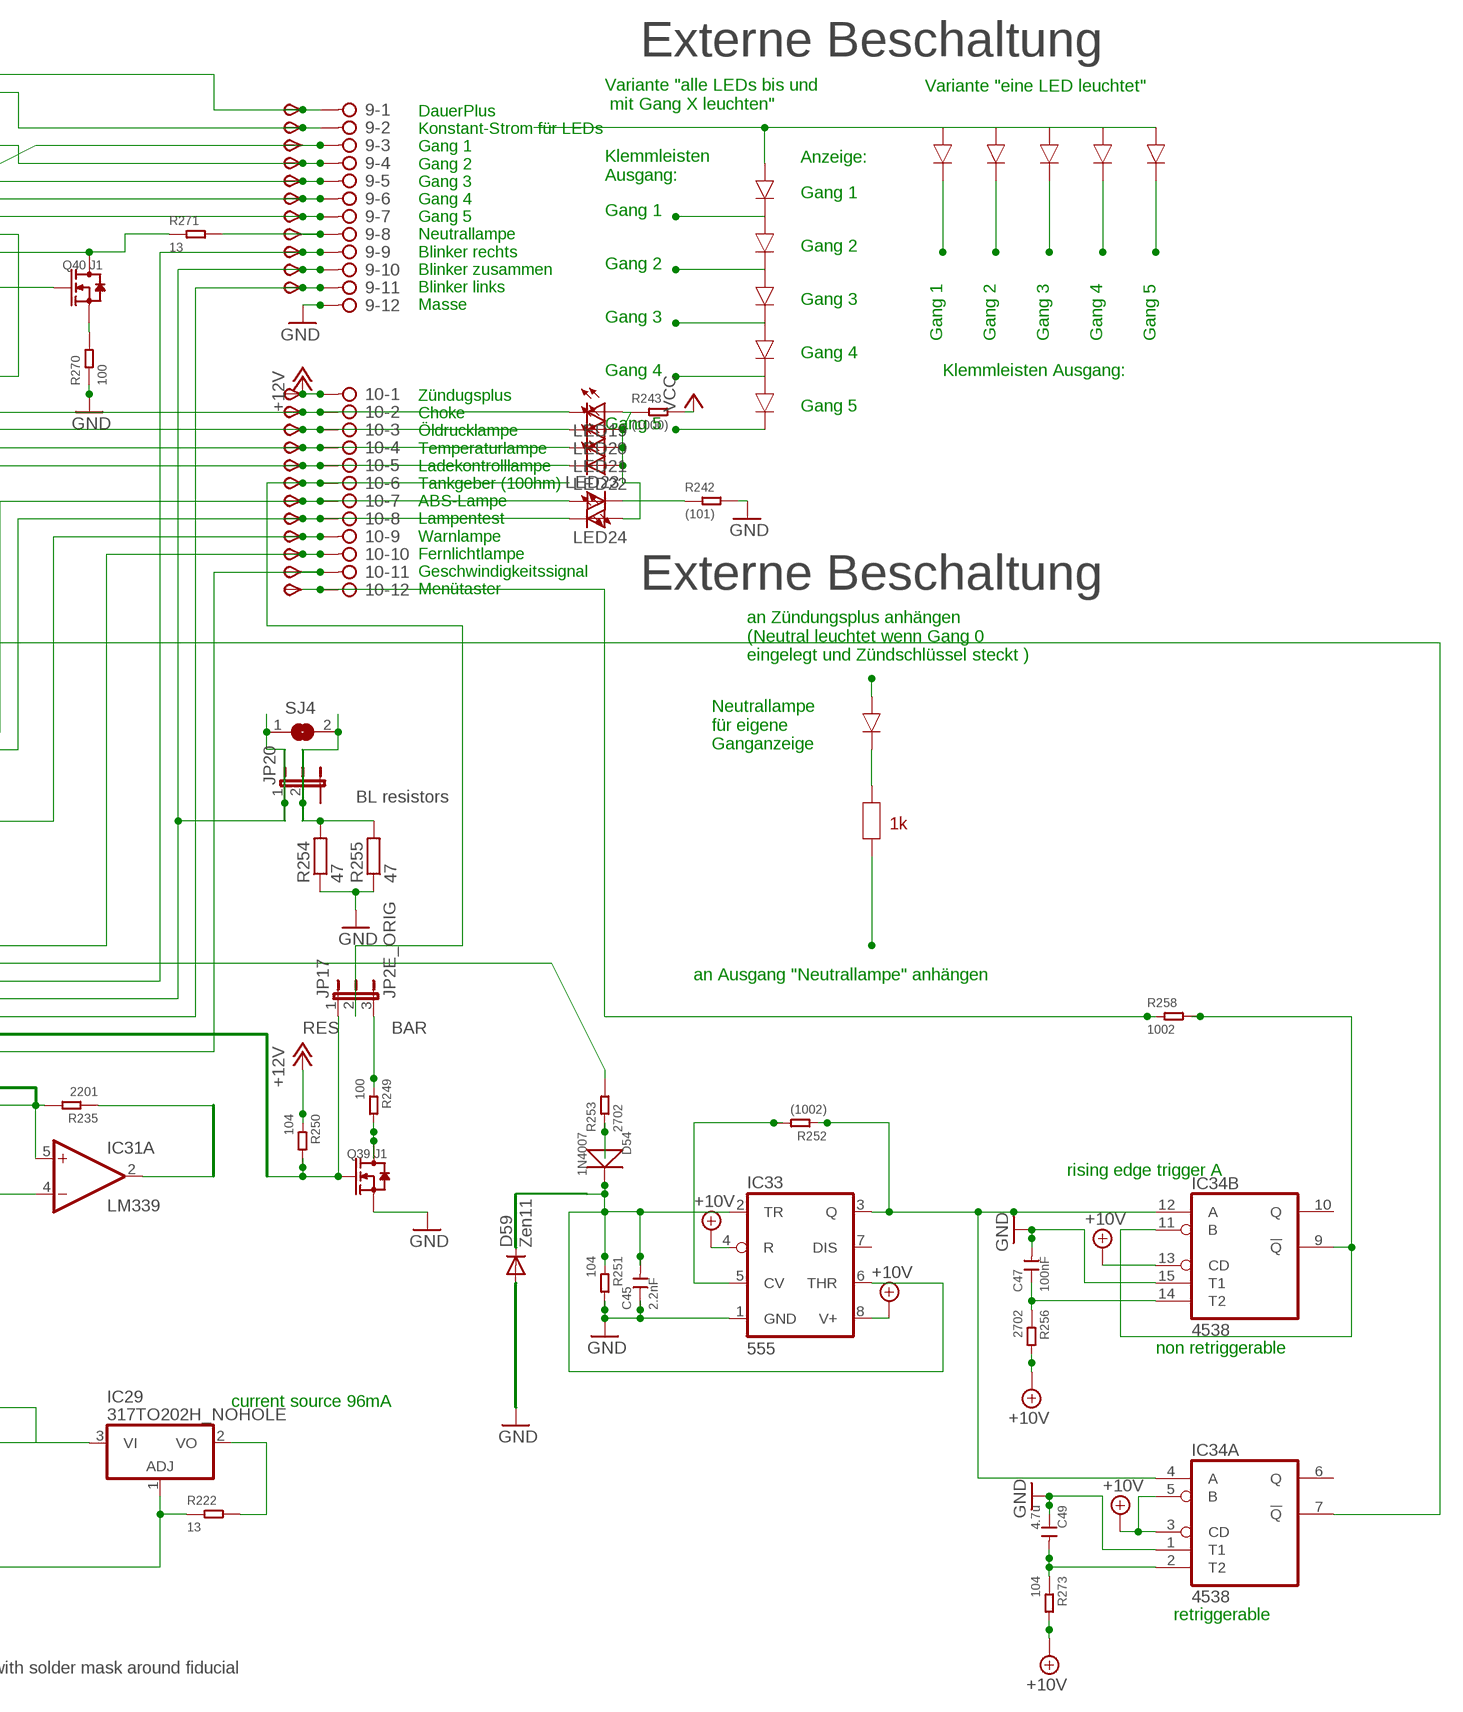
[diagram p10: schematic, sheet 6, part 2 of 2]
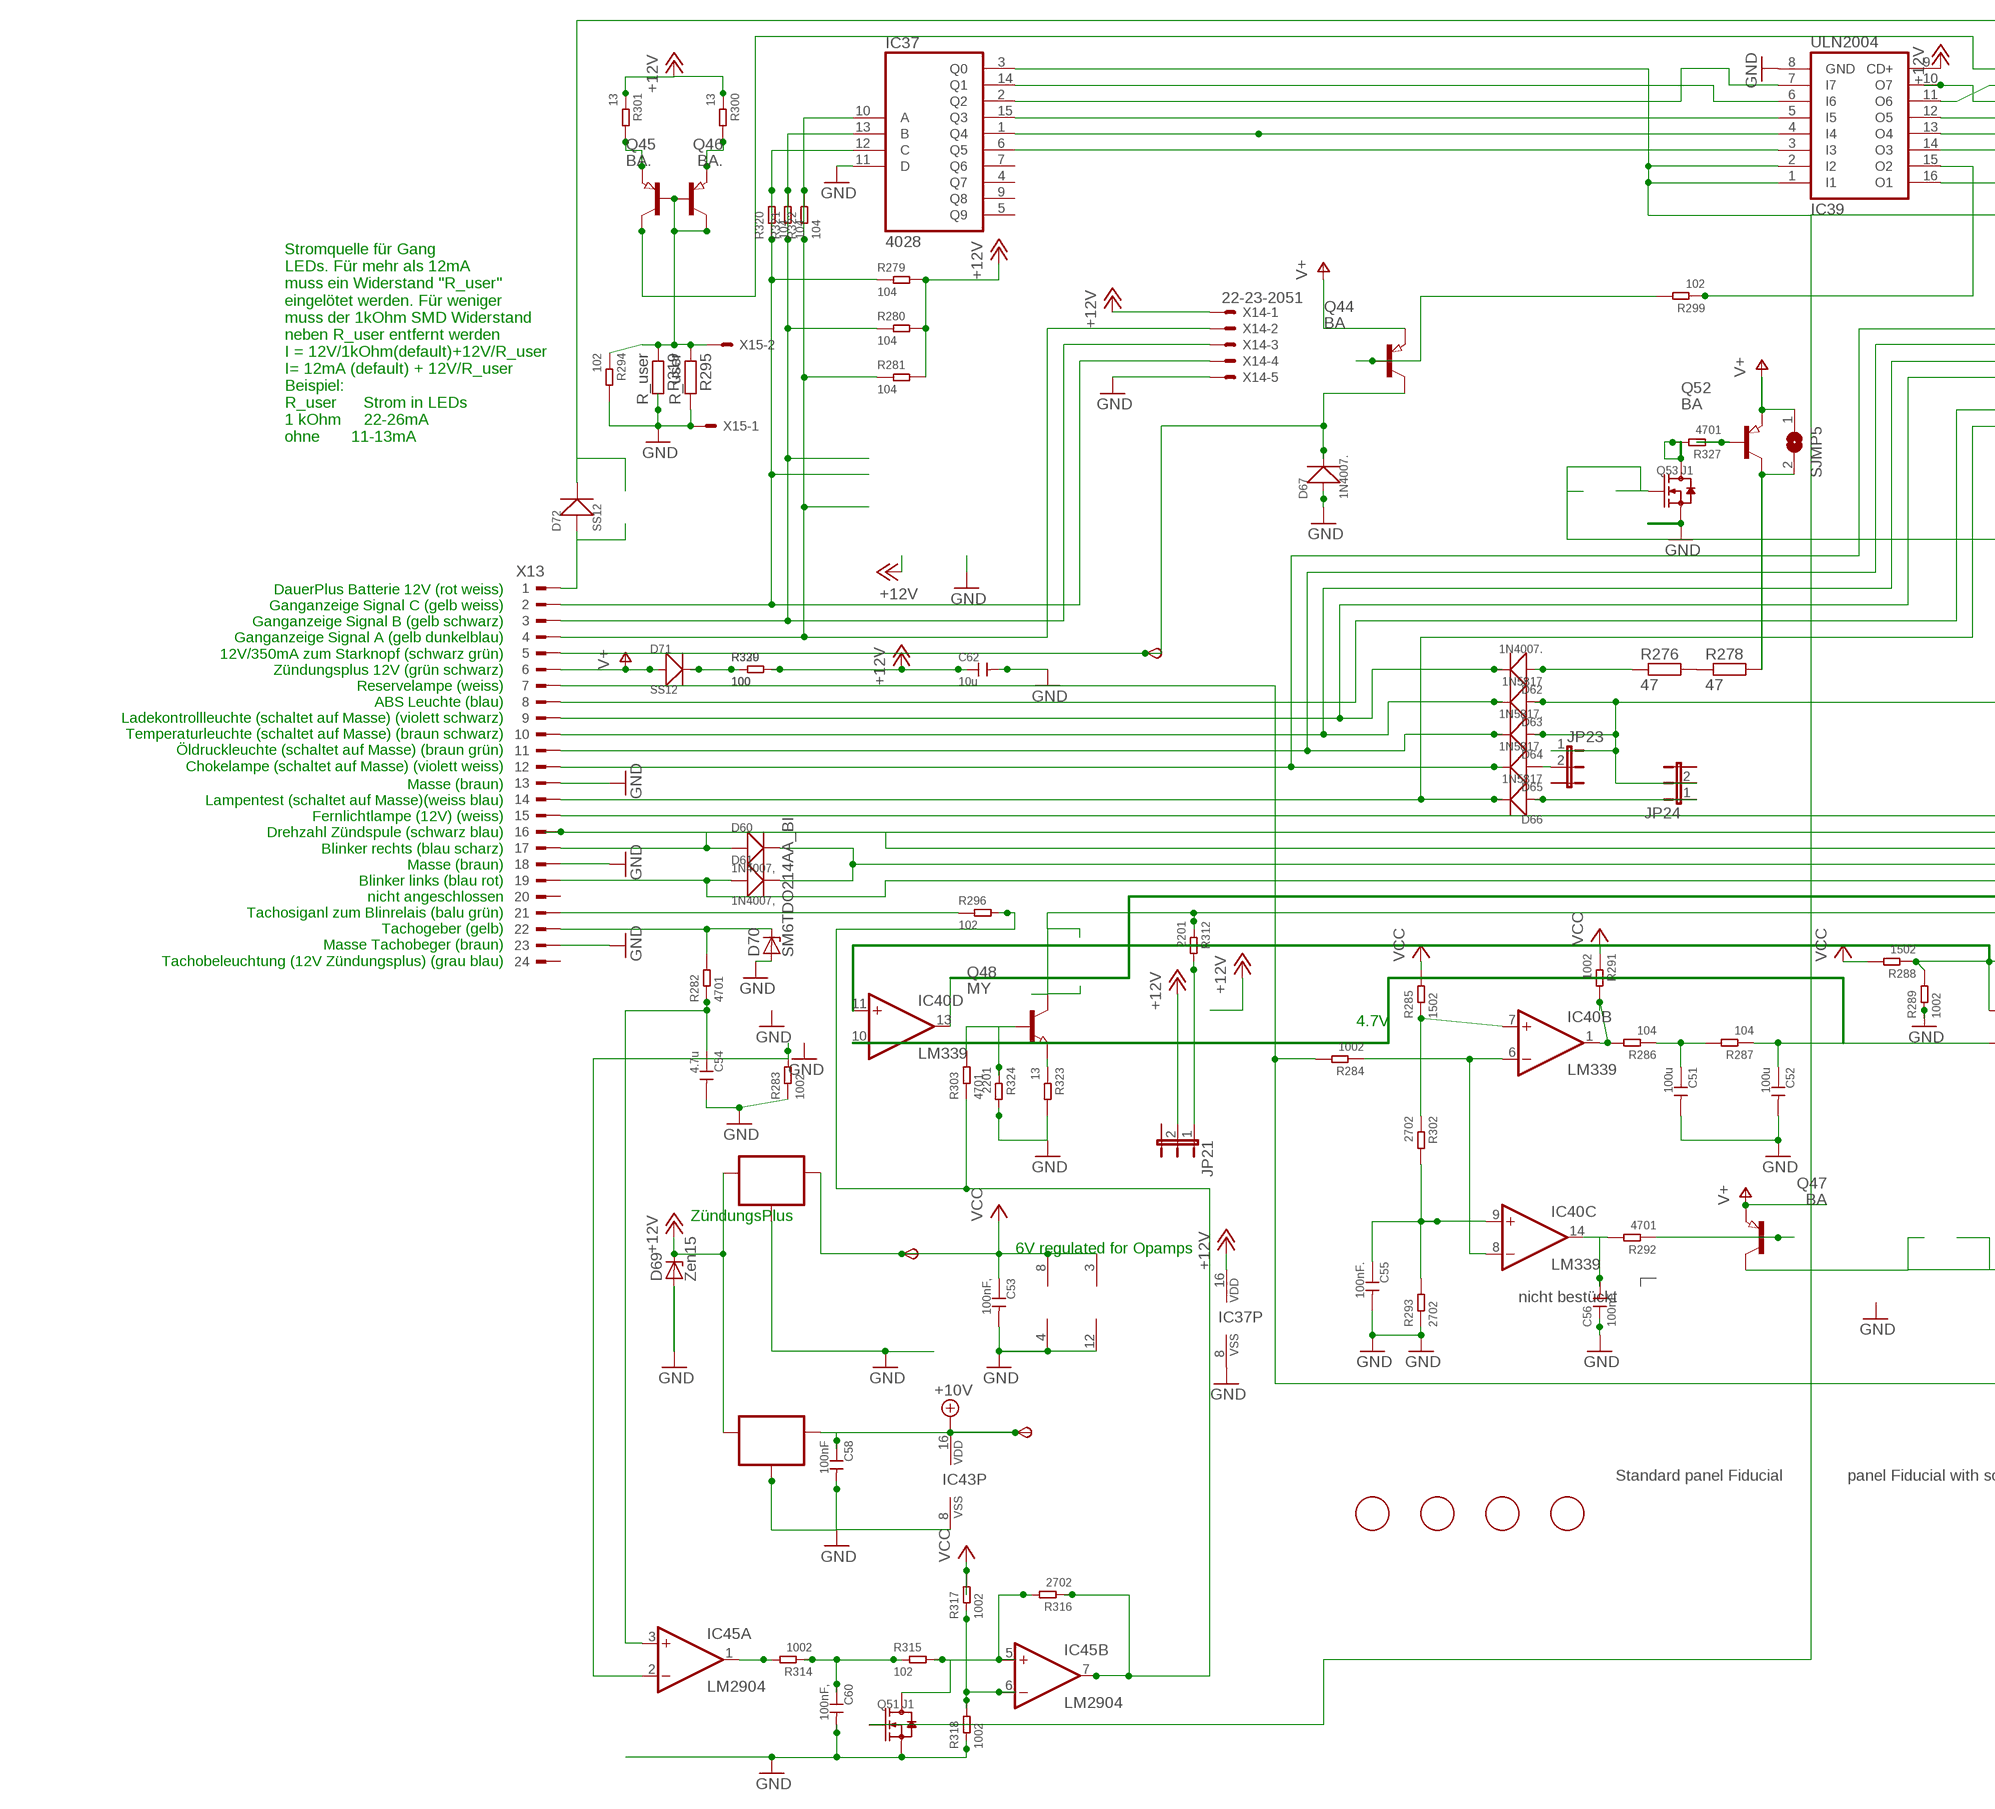
[diagram p11: schematic, sheet 7, part 1 of 2]
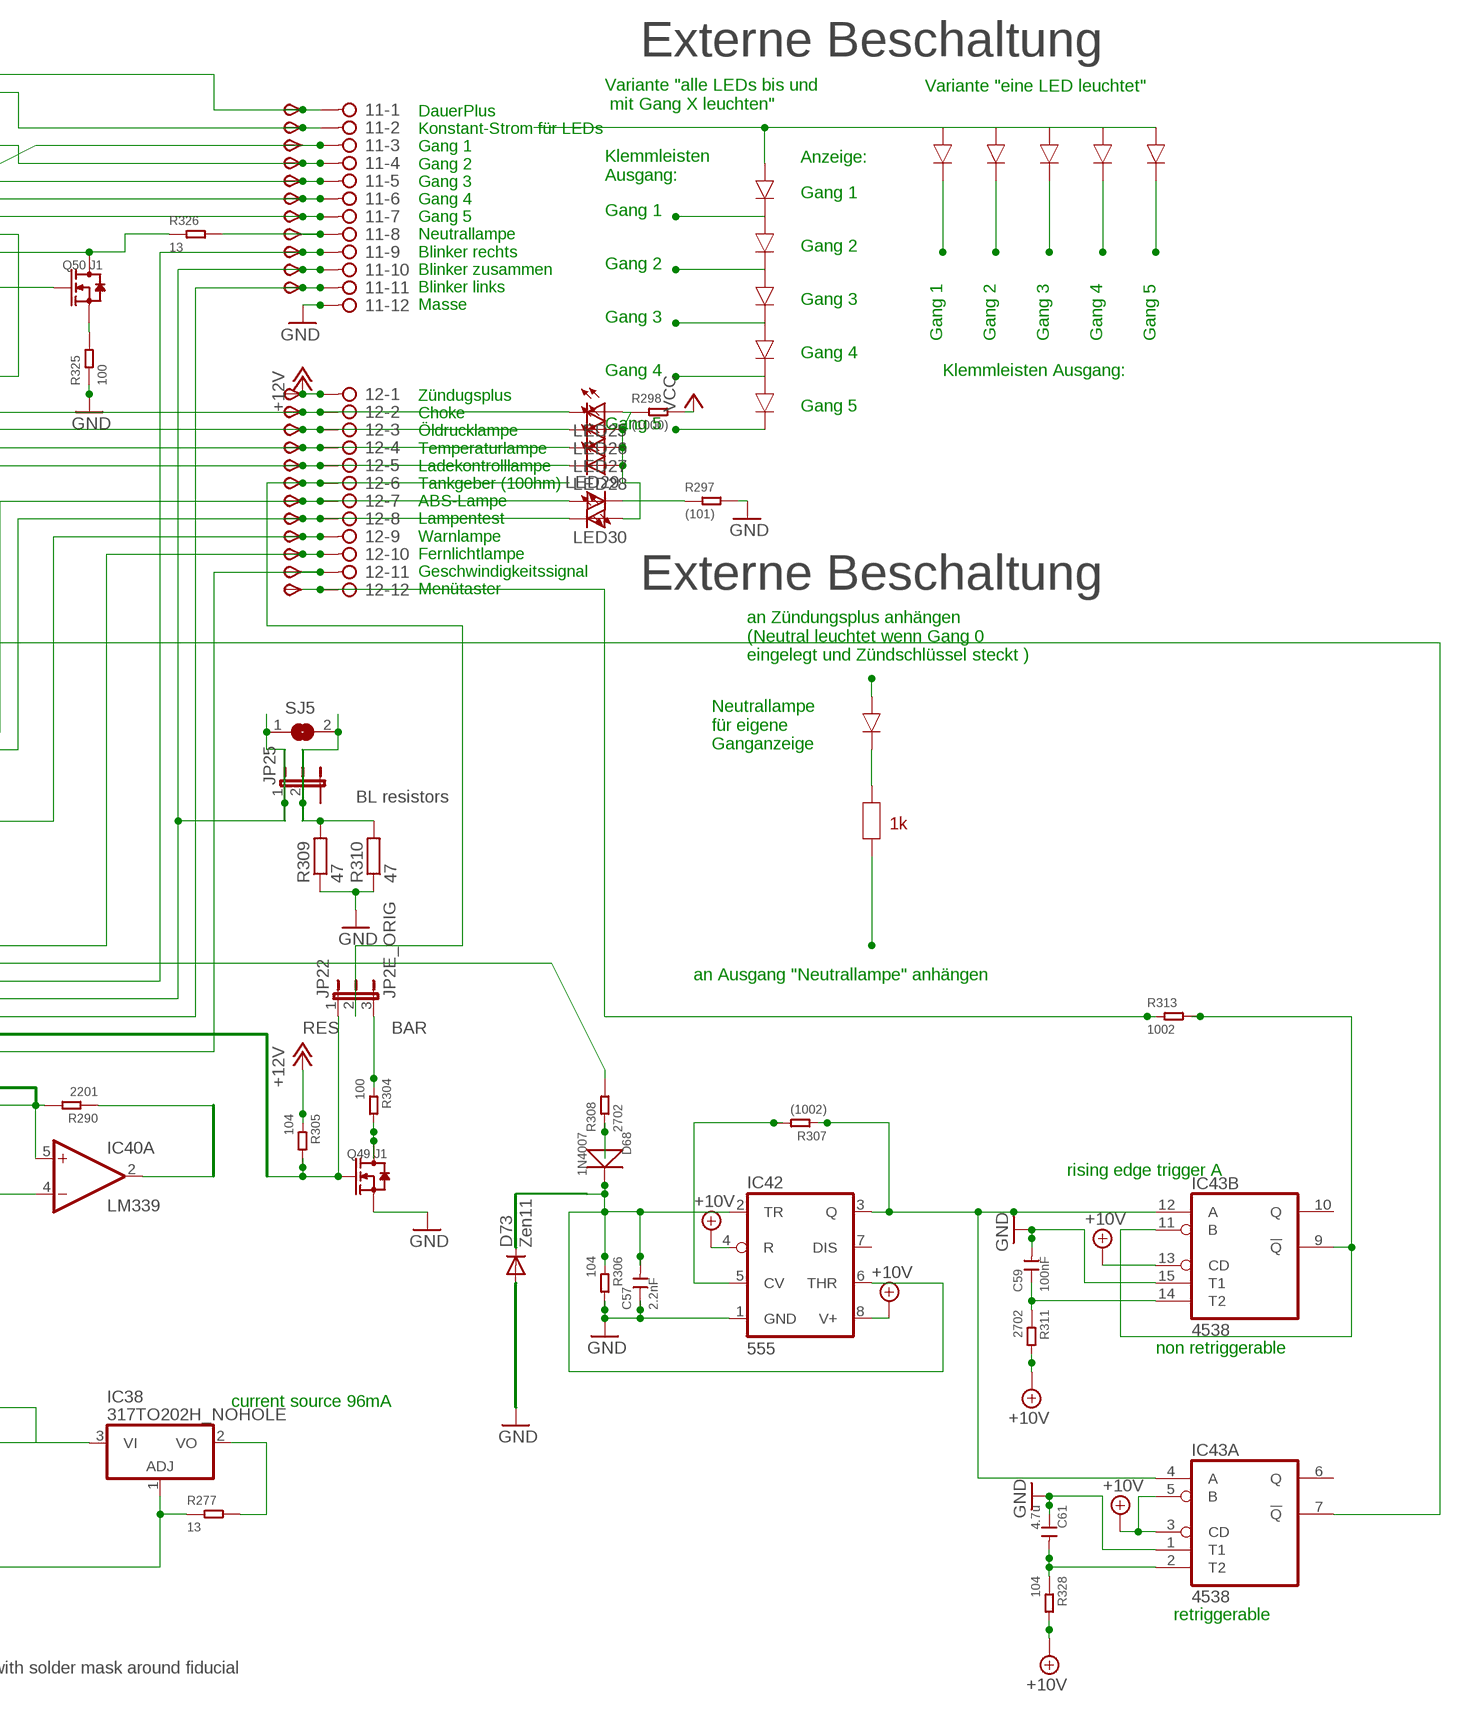
[diagram p12: schematic, sheet 7, part 2 of 2]

(export (version "E")
  (design (tool "Eeschema 10.0.6"))
  (components
    (comp (ref "6V4")
      (value "TPSB2.0")
      (footprint "eagle-import:B2.0")
      (libsource (lib "eagle-import") (part "TPSB2.0"))
    )
    (comp (ref "9")
      (value "2081-1132")
      (footprint "eagle-import:12-PIN")
      (libsource (lib "eagle-import") (part "2081-1132"))
    )
    (comp (ref "10")
      (value "2081-1132")
      (footprint "eagle-import:12-PIN")
      (libsource (lib "eagle-import") (part "2081-1132"))
    )
    (comp (ref "10V4")
      (value "TPSB2.0")
      (footprint "eagle-import:B2.0")
      (libsource (lib "eagle-import") (part "TPSB2.0"))
    )
    (comp (ref "C39")
      (value "100u")
      (footprint "eagle-import:C1206")
      (fields (field (name "MPN") "GRM31CR60J107ME39L"))
      (libsource (lib "eagle-import") (part "CERAMIC-100UF-6.3V-20%-X5R(1206)"))
    )
    (comp (ref "C40")
      (value "100u")
      (footprint "eagle-import:C1206")
      (fields (field (name "MPN") "GRM31CR60J107ME39L"))
      (libsource (lib "eagle-import") (part "CERAMIC-100UF-6.3V-20%-X5R(1206)"))
    )
    (comp (ref "C41")
      (value "100nF,")
      (footprint "eagle-import:C0805")
      (fields (field (name "MPN") "CC0805KRX7R9BB104"))
      (libsource (lib "eagle-import") (part "CERAMIC-100NF-50V-10%-X7R(0805)"))
    )
    (comp (ref "C42")
      (value "4.7u")
      (footprint "eagle-import:C0805")
      (fields (field (name "MPN") "CC0805KKX5R8BB475"))
      (libsource (lib "eagle-import") (part "CERAMIC-4.7UF-25V-10%-X5R(0805)"))
    )
    (comp (ref "C43")
      (value "100nF.")
      (footprint "eagle-import:C0805")
      (fields (field (name "MPN") "CC0805KRX7R9BB104"))
      (libsource (lib "eagle-import") (part "CERAMIC-100NF-50V-10%-X7R(0805)"))
    )
    (comp (ref "C44")
      (value "100nF.")
      (footprint "eagle-import:C0805")
      (fields (field (name "MPN") "CC0805KRX7R9BB104"))
      (libsource (lib "eagle-import") (part "CERAMIC-100NF-50V-10%-X7R(0805)"))
    )
    (comp (ref "C45")
      (value "2.2nF")
      (footprint "eagle-import:C0805")
      (fields (field (name "MPN") "CC0805KRX7R9BB104"))
      (libsource (lib "eagle-import") (part "CERAMIC-100NF-50V-10%-X7R(0805)"))
    )
    (comp (ref "C46")
      (value "100nF")
      (footprint "eagle-import:C0805")
      (fields (field (name "MPN") "CC0805KRX7R9BB104"))
      (libsource (lib "eagle-import") (part "CERAMIC-100NF-50V-10%-X7R(0805)"))
    )
    (comp (ref "C47")
      (value "100nF")
      (footprint "eagle-import:C0805")
      (fields (field (name "MPN") "CC0805KRX7R9BB104"))
      (libsource (lib "eagle-import") (part "CERAMIC-100NF-50V-10%-X7R(0805)"))
    )
    (comp (ref "C48")
      (value "100nF,")
      (footprint "eagle-import:C0805")
      (fields (field (name "MPN") "CC0805KRX7R9BB104"))
      (libsource (lib "eagle-import") (part "CERAMIC-100NF-50V-10%-X7R(0805)"))
    )
    (comp (ref "C49")
      (value "4.7u")
      (footprint "eagle-import:C0805")
      (fields (field (name "MPN") "CC0805KKX5R8BB475"))
      (libsource (lib "eagle-import") (part "CERAMIC-4.7UF-25V-10%-X5R(0805)"))
    )
    (comp (ref "C50")
      (value "10u")
      (footprint "eagle-import:C1206")
      (fields (field (name "MPN") "GRM31CR60J107ME39L"))
      (libsource (lib "eagle-import") (part "CERAMIC-100UF-6.3V-20%-X5R(1206)"))
    )
    (comp (ref "D46")
      (value "1N4007,")
      (footprint "eagle-import:DO-214AC")
      (fields (field (name "MPN") "1N4007"))
      (libsource (lib "eagle-import") (part "DIODE-GEN-PURPOSE-1KV-1A(DO-214AC)"))
    )
    (comp (ref "D47")
      (value "1N4007,")
      (footprint "eagle-import:DO-214AC")
      (fields (field (name "MPN") "1N4007"))
      (libsource (lib "eagle-import") (part "DIODE-GEN-PURPOSE-1KV-1A(DO-214AC)"))
    )
    (comp (ref "D48")
      (value "1N4007.")
      (footprint "eagle-import:DO-214AC")
      (fields (field (name "MPN") "1N4007"))
      (libsource (lib "eagle-import") (part "DIODE-GEN-PURPOSE-1KV-1A(DO-214AC)"))
    )
    (comp (ref "D49")
      (value "1N5817")
      (footprint "eagle-import:DO-214AC_SLIM")
      (libsource (lib "eagle-import") (part "DIODE-GEN-PURPOSE-1KV-1A(DO-214AC)DO-214AC/1206"))
    )
    (comp (ref "D50")
      (value "1N5817.")
      (footprint "eagle-import:DO-214AC_SLIM")
      (libsource (lib "eagle-import") (part "DIODE-GEN-PURPOSE-1KV-1A(DO-214AC)DO-214AC/1206"))
    )
    (comp (ref "D51")
      (value "1N5817.")
      (footprint "eagle-import:DO-214AC_SLIM")
      (libsource (lib "eagle-import") (part "DIODE-GEN-PURPOSE-1KV-1A(DO-214AC)DO-214AC/1206"))
    )
    (comp (ref "D52")
      (value "1N5817")
      (footprint "eagle-import:DO-214AC_SLIM")
      (libsource (lib "eagle-import") (part "DIODE-GEN-PURPOSE-1KV-1A(DO-214AC)DO-214AC/1206"))
    )
    (comp (ref "D53")
      (value "1N4007.")
      (footprint "eagle-import:DO-214AC")
      (fields (field (name "MPN") "1N4007"))
      (libsource (lib "eagle-import") (part "DIODE-GEN-PURPOSE-1KV-1A(DO-214AC)"))
    )
    (comp (ref "D54")
      (value "1N4007")
      (footprint "eagle-import:DO-214AC")
      (libsource (lib "eagle-import") (part "DIODE-GEN-PURPOSE-1KV-1A(DO-214AC)"))
    )
    (comp (ref "D55")
      (value "Zen15")
      (footprint "eagle-import:DO214AA")
      (libsource (lib "eagle-import") (part "SM6T"))
    )
    (comp (ref "D56")
      (value "SM6TDO214AA_BI")
      (footprint "eagle-import:DO214AA_BI")
      (libsource (lib "eagle-import") (part "SM6TDO214AA_BI"))
    )
    (comp (ref "D57")
      (value "SS12")
      (footprint "eagle-import:DO-214AC_SLIM")
      (libsource (lib "eagle-import") (part "DIODE-GEN-PURPOSE-1KV-1A(DO-214AC)DO-214AC/1206"))
    )
    (comp (ref "D58")
      (value "SS12")
      (footprint "eagle-import:DO-214AC_SLIM")
      (libsource (lib "eagle-import") (part "DIODE-GEN-PURPOSE-1KV-1A(DO-214AC)DO-214AC/1206"))
    )
    (comp (ref "D59")
      (value "Zen11")
      (footprint "eagle-import:SOD-123_MINI-SMA")
      (libsource (lib "eagle-import") (part "CGRM400-G1"))
    )
    (comp (ref "FID15")
      (value "FIDUCIAL")
      (footprint "eagle-import:FIDUCIAL_1MM")
      (libsource (lib "eagle-import") (part "FIDUCIAL"))
    )
    (comp (ref "FID16")
      (value "FIDUCIAL")
      (footprint "eagle-import:FIDUCIAL_1MM")
      (libsource (lib "eagle-import") (part "FIDUCIAL"))
    )
    (comp (ref "FID17")
      (value "FIDUCIAL")
      (footprint "eagle-import:FIDUCIAL_1MM")
      (libsource (lib "eagle-import") (part "FIDUCIAL"))
    )
    (comp (ref "FID18")
      (value "FIDUCIAL")
      (footprint "eagle-import:FIDUCIAL_1MM")
      (libsource (lib "eagle-import") (part "FIDUCIAL"))
    )
    (comp (ref "IC28")
      (value "4028")
      (footprint "eagle-import:SO16")
      (libsource (lib "eagle-import") (part "4028D"))
    )
    (comp (ref "IC29")
      (value "317TO202H_NOHOLE")
      (footprint "eagle-import:TO220H_NOHOLE")
      (libsource (lib "eagle-import") (part "317TO202H_NOHOLE"))
    )
    (comp (ref "IC30")
      (value "ULN2004")
      (footprint "eagle-import:SO16")
      (libsource (lib "eagle-import") (part "ULN2004AD"))
    )
    (comp (ref "IC31")
      (value "LM339")
      (footprint "eagle-import:SO14")
      (libsource (lib "eagle-import") (part "LM339D"))
    )
    (comp (ref "IC32")
      (value "78L06")
      (footprint "eagle-import:SOT89_ROUND")
      (libsource (lib "eagle-import") (part "78LXXSOT89_ROUND"))
    )
    (comp (ref "IC33")
      (value "555")
      (footprint "eagle-import:SO08")
      (libsource (lib "eagle-import") (part "555DNE"))
    )
    (comp (ref "IC34")
      (value "4538")
      (footprint "eagle-import:SO16")
      (libsource (lib "eagle-import") (part "4538D"))
    )
    (comp (ref "IC35")
      (value "78L10")
      (footprint "eagle-import:SOT89_ROUND")
      (libsource (lib "eagle-import") (part "78LXXSOT89_ROUND"))
    )
    (comp (ref "IC36")
      (value "LM2904")
      (footprint "eagle-import:SO08")
      (libsource (lib "eagle-import") (part "LM358D"))
    )
    (comp (ref "JP16")
      (value "JP2EJP2_SMALLPADS")
      (footprint "eagle-import:JP2_SMALLPADS")
      (libsource (lib "eagle-import") (part "JP2EJP2_SMALLPADS"))
    )
    (comp (ref "JP17")
      (value "JP2E_ORIG")
      (footprint "eagle-import:JP2_ORIG_SMALLPADS")
      (libsource (lib "eagle-import") (part "JP2E_ORIG"))
    )
    (comp (ref "JP18")
      (value "JP2EJP2_SMALLPADS")
      (footprint "eagle-import:JP2_SMALLPADS")
      (libsource (lib "eagle-import") (part "JP2EJP2_SMALLPADS"))
    )
    (comp (ref "JP19")
      (value "JP2EJP2_SMALLPADS")
      (footprint "eagle-import:JP2_SMALLPADS")
      (libsource (lib "eagle-import") (part "JP2EJP2_SMALLPADS"))
    )
    (comp (ref "JP20")
      (value "JP2EJP2_SMALLPADS")
      (footprint "eagle-import:JP2_SMALLPADS")
      (libsource (lib "eagle-import") (part "JP2EJP2_SMALLPADS"))
    )
    (comp (ref "LED19")
      (value "LEDLD260")
      (footprint "eagle-import:LD260")
      (libsource (lib "eagle-import") (part "LEDLD260"))
    )
    (comp (ref "LED20")
      (value "LEDLD260")
      (footprint "eagle-import:LD260")
      (libsource (lib "eagle-import") (part "LEDLD260"))
    )
    (comp (ref "LED21")
      (value "LEDLD260")
      (footprint "eagle-import:LD260")
      (libsource (lib "eagle-import") (part "LEDLD260"))
    )
    (comp (ref "LED22")
      (value "LEDLD260")
      (footprint "eagle-import:LD260")
      (libsource (lib "eagle-import") (part "LEDLD260"))
    )
    (comp (ref "LED23")
      (value "LEDLD260")
      (footprint "eagle-import:LD260")
      (libsource (lib "eagle-import") (part "LEDLD260"))
    )
    (comp (ref "LED24")
      (value "LEDLD260")
      (footprint "eagle-import:LD260")
      (libsource (lib "eagle-import") (part "LEDLD260"))
    )
    (comp (ref "Q34")
      (value "BA")
      (footprint "eagle-import:SOT89")
      (libsource (lib "eagle-import") (part "PNP-TRANSISTOR_SOT89"))
    )
    (comp (ref "Q35")
      (value "BA.")
      (footprint "eagle-import:SOT89")
      (libsource (lib "eagle-import") (part "PNP-TRANSISTOR_SOT89"))
    )
    (comp (ref "Q36")
      (value "BA.")
      (footprint "eagle-import:SOT89")
      (libsource (lib "eagle-import") (part "PNP-TRANSISTOR_SOT89"))
    )
    (comp (ref "Q37")
      (value "BA")
      (footprint "eagle-import:SOT89")
      (libsource (lib "eagle-import") (part "PNP-TRANSISTOR_SOT89"))
    )
    (comp (ref "Q38")
      (value "MY")
      (footprint "eagle-import:SOT89")
      (libsource (lib "eagle-import") (part "NPN-TRANSISTOR_SOT89"))
    )
    (comp (ref "Q39")
      (value "J1")
      (footprint "eagle-import:SOT-23")
      (fields (field (name "MPN") "BSS138W-7-F"))
      (libsource (lib "eagle-import") (part "SMD-MOSFET-N-CH-50V-200MA-BSS138W-7-F(SOT-23)"))
    )
    (comp (ref "Q40")
      (value "J1")
      (footprint "eagle-import:SOT-23")
      (fields (field (name "MPN") "BSS138W-7-F"))
      (libsource (lib "eagle-import") (part "SMD-MOSFET-N-CH-50V-200MA-BSS138W-7-F(SOT-23)"))
    )
    (comp (ref "Q41")
      (value "J1")
      (footprint "eagle-import:SOT-23")
      (fields (field (name "MPN") "BSS138W-7-F"))
      (libsource (lib "eagle-import") (part "SMD-MOSFET-N-CH-50V-200MA-BSS138W-7-F(SOT-23)"))
    )
    (comp (ref "Q42")
      (value "BA")
      (footprint "eagle-import:SOT89")
      (libsource (lib "eagle-import") (part "PNP-TRANSISTOR_SOT89"))
    )
    (comp (ref "Q43")
      (value "J1")
      (footprint "eagle-import:SOT-23")
      (fields (field (name "MPN") "BSS138W-7-F"))
      (libsource (lib "eagle-import") (part "SMD-MOSFET-N-CH-50V-200MA-BSS138W-7-F(SOT-23)"))
    )
    (comp (ref "R221")
      (value "47")
      (footprint "eagle-import:V235_17_1MM")
      (libsource (lib "eagle-import") (part "R-EU_V235/17_1MM"))
    )
    (comp (ref "R222")
      (value "13")
      (footprint "eagle-import:R1206")
      (fields (field (name "MPN") "RC1206JR-0713RL"))
      (libsource (lib "eagle-import") (part "SMD-RES-13R-5%-1/4W(1206)"))
    )
    (comp (ref "R223")
      (value "47")
      (footprint "eagle-import:V235_17_1MM")
      (libsource (lib "eagle-import") (part "R-EU_V235/17_1MM"))
    )
    (comp (ref "R224")
      (value "104")
      (footprint "eagle-import:R0805")
      (fields (field (name "MPN") "RC0805FR-0710KL"))
      (libsource (lib "eagle-import") (part "SMD-RES-10K-1%-1/8W(0805)"))
    )
    (comp (ref "R225")
      (value "104")
      (footprint "eagle-import:R0805")
      (fields (field (name "MPN") "RC0805FR-0710KL"))
      (libsource (lib "eagle-import") (part "SMD-RES-10K-1%-1/8W(0805)"))
    )
    (comp (ref "R226")
      (value "104")
      (footprint "eagle-import:R0805")
      (fields (field (name "MPN") "RC0805FR-0710KL"))
      (libsource (lib "eagle-import") (part "SMD-RES-10K-1%-1/8W(0805)"))
    )
    (comp (ref "R227")
      (value "4701")
      (footprint "eagle-import:R0805")
      (fields (field (name "MPN") "RC0805JR-074K7L"))
      (libsource (lib "eagle-import") (part "SMD-RES-4.7K-5%-1/8W(0805)"))
    )
    (comp (ref "R228")
      (value "1002")
      (footprint "eagle-import:R0805")
      (fields (field (name "MPN") "RC0805FR-0710KL"))
      (libsource (lib "eagle-import") (part "SMD-RES-10K-1%-1/8W(0805)"))
    )
    (comp (ref "R229")
      (value "1002")
      (footprint "eagle-import:R0805")
      (fields (field (name "MPN") "RC0805FR-0710KL"))
      (libsource (lib "eagle-import") (part "SMD-RES-10K-1%-1/8W(0805)"))
    )
    (comp (ref "R230")
      (value "1502")
      (footprint "eagle-import:R0805")
      (fields (field (name "MPN") "RC0805FR-0710KL"))
      (libsource (lib "eagle-import") (part "SMD-RES-10K-1%-1/8W(0805)"))
    )
    (comp (ref "R231")
      (value "104")
      (footprint "eagle-import:R0805")
      (fields (field (name "MPN") "RC0805FR-0710KL"))
      (libsource (lib "eagle-import") (part "SMD-RES-10K-1%-1/8W(0805)"))
    )
    (comp (ref "R232")
      (value "104")
      (footprint "eagle-import:R0805")
      (fields (field (name "MPN") "RC0805FR-0710KL"))
      (libsource (lib "eagle-import") (part "SMD-RES-10K-1%-1/8W(0805)"))
    )
    (comp (ref "R233")
      (value "1502")
      (footprint "eagle-import:R0805")
      (fields (field (name "MPN") "RC0805FR-0710KL"))
      (libsource (lib "eagle-import") (part "SMD-RES-10K-1%-1/8W(0805)"))
    )
    (comp (ref "R234")
      (value "1002")
      (footprint "eagle-import:R0805")
      (fields (field (name "MPN") "RC0805FR-0710KL"))
      (libsource (lib "eagle-import") (part "SMD-RES-10K-1%-1/8W(0805)"))
    )
    (comp (ref "R235")
      (value "2201")
      (footprint "eagle-import:R0805")
      (fields (field (name "MPN") "RC0805JR-072K2L"))
      (libsource (lib "eagle-import") (part "SMD-RES-2.2K-5%-1/8W(0805)"))
    )
    (comp (ref "R236")
      (value "1002")
      (footprint "eagle-import:R0805")
      (fields (field (name "MPN") "RC0805FR-0710KL"))
      (libsource (lib "eagle-import") (part "SMD-RES-10K-1%-1/8W(0805)"))
    )
    (comp (ref "R237")
      (value "4701")
      (footprint "eagle-import:R0805")
      (fields (field (name "MPN") "RC0805JR-074K7L"))
      (libsource (lib "eagle-import") (part "SMD-RES-4.7K-5%-1/8W(0805)"))
    )
    (comp (ref "R238")
      (value "2702")
      (footprint "eagle-import:R0805")
      (fields (field (name "MPN") "RC0805JR-074K7L"))
      (libsource (lib "eagle-import") (part "SMD-RES-4.7K-5%-1/8W(0805)"))
    )
    (comp (ref "R239")
      (value "102")
      (footprint "eagle-import:R0805")
      (fields (field (name "MPN") "RC0805JR-071KL"))
      (libsource (lib "eagle-import") (part "SMD-RES-1K-5%-1/8W(0805)"))
    )
    (comp (ref "R240")
      (value "R_user")
      (footprint "eagle-import:R0805")
      (libsource (lib "eagle-import") (part "R-EU_R0805"))
    )
    (comp (ref "R241")
      (value "102")
      (footprint "eagle-import:R0805")
      (fields (field (name "MPN") "RC0805JR-07220RL"))
      (libsource (lib "eagle-import") (part "SMD-RES-220R-5%-1/8W(0805)"))
    )
    (comp (ref "R242")
      (value "(101)")
      (footprint "eagle-import:R0805")
      (fields (field (name "MPN") "RC0805JR-07100RL"))
      (libsource (lib "eagle-import") (part "SMD-RES-100R-5%-1/8W(0805)"))
    )
    (comp (ref "R243")
      (value "(1000)")
      (footprint "eagle-import:R0805")
      (fields (field (name "MPN") "RC0805JR-07100RL"))
      (libsource (lib "eagle-import") (part "SMD-RES-100R-5%-1/8W(0805)"))
    )
    (comp (ref "R244")
      (value "102")
      (footprint "eagle-import:R0805")
      (fields (field (name "MPN") "RC0805JR-071KL"))
      (libsource (lib "eagle-import") (part "SMD-RES-1K-5%-1/8W(0805)"))
    )
    (comp (ref "R245")
      (value "13")
      (footprint "eagle-import:R1206")
      (fields (field (name "MPN") "RC1206JR-0713RL"))
      (libsource (lib "eagle-import") (part "SMD-RES-13R-5%-1/4W(1206)"))
    )
    (comp (ref "R246")
      (value "13")
      (footprint "eagle-import:R1206")
      (fields (field (name "MPN") "RC1206JR-0713RL"))
      (libsource (lib "eagle-import") (part "SMD-RES-13R-5%-1/4W(1206)"))
    )
    (comp (ref "R247")
      (value "2702")
      (footprint "eagle-import:R0805")
      (fields (field (name "MPN") "RC0805JR-074K7L"))
      (libsource (lib "eagle-import") (part "SMD-RES-4.7K-5%-1/8W(0805)"))
    )
    (comp (ref "R248")
      (value "4701")
      (footprint "eagle-import:R0805")
      (fields (field (name "MPN") "RC0805JR-074K7L"))
      (libsource (lib "eagle-import") (part "SMD-RES-4.7K-5%-1/8W(0805)"))
    )
    (comp (ref "R249")
      (value "100")
      (footprint "eagle-import:R0805")
      (fields (field (name "MPN") "RC0805JR-072K2L"))
      (libsource (lib "eagle-import") (part "SMD-RES-2.2K-5%-1/8W(0805)"))
    )
    (comp (ref "R250")
      (value "104")
      (footprint "eagle-import:R0805")
      (fields (field (name "MPN") "RC0805FR-0710KL"))
      (libsource (lib "eagle-import") (part "SMD-RES-10K-1%-1/8W(0805)"))
    )
    (comp (ref "R251")
      (value "104")
      (footprint "eagle-import:R0805")
      (fields (field (name "MPN") "RC0805FR-0710KL"))
      (libsource (lib "eagle-import") (part "SMD-RES-10K-1%-1/8W(0805)"))
    )
    (comp (ref "R252")
      (value "(1002)")
      (footprint "eagle-import:R0805")
      (fields (field (name "MPN") "RC0805FR-0710KL"))
      (libsource (lib "eagle-import") (part "SMD-RES-10K-1%-1/8W(0805)"))
    )
    (comp (ref "R253")
      (value "2702")
      (footprint "eagle-import:R0805")
      (fields (field (name "MPN") "RC0805FR-0710KL"))
      (libsource (lib "eagle-import") (part "SMD-RES-10K-1%-1/8W(0805)"))
    )
    (comp (ref "R254")
      (value "47")
      (footprint "eagle-import:V235_17_1MM")
      (libsource (lib "eagle-import") (part "R-EU_V235/17_1MM"))
    )
    (comp (ref "R255")
      (value "47")
      (footprint "eagle-import:V235_17_1MM")
      (libsource (lib "eagle-import") (part "R-EU_V235/17_1MM"))
    )
    (comp (ref "R256")
      (value "2702")
      (footprint "eagle-import:R0805")
      (fields (field (name "MPN") "RC0805JR-074K7L"))
      (libsource (lib "eagle-import") (part "SMD-RES-4.7K-5%-1/8W(0805)"))
    )
    (comp (ref "R257")
      (value "2201")
      (footprint "eagle-import:R0805")
      (fields (field (name "MPN") "RC0805JR-072K2L"))
      (libsource (lib "eagle-import") (part "SMD-RES-2.2K-5%-1/8W(0805)"))
    )
    (comp (ref "R258")
      (value "1002")
      (footprint "eagle-import:R0805")
      (fields (field (name "MPN") "RC0805JR-074K7L"))
      (libsource (lib "eagle-import") (part "SMD-RES-4.7K-5%-1/8W(0805)"))
    )
    (comp (ref "R259")
      (value "1002")
      (footprint "eagle-import:R0805")
      (fields (field (name "MPN") "RC0805FR-0710KL"))
      (libsource (lib "eagle-import") (part "SMD-RES-10K-1%-1/8W(0805)"))
    )
    (comp (ref "R260")
      (value "102")
      (footprint "eagle-import:R0805")
      (fields (field (name "MPN") "RC0805JR-071KL"))
      (libsource (lib "eagle-import") (part "SMD-RES-1K-5%-1/8W(0805)"))
    )
    (comp (ref "R261")
      (value "2702")
      (footprint "eagle-import:R0805")
      (fields (field (name "MPN") "RC0805JR-074K7L"))
      (libsource (lib "eagle-import") (part "SMD-RES-4.7K-5%-1/8W(0805)"))
    )
    (comp (ref "R262")
      (value "1002")
      (footprint "eagle-import:R0805")
      (fields (field (name "MPN") "RC0805JR-071KL"))
      (libsource (lib "eagle-import") (part "SMD-RES-1K-5%-1/8W(0805)"))
    )
    (comp (ref "R263")
      (value "1002")
      (footprint "eagle-import:R0805")
      (fields (field (name "MPN") "RC0805JR-071KL"))
      (libsource (lib "eagle-import") (part "SMD-RES-1K-5%-1/8W(0805)"))
    )
    (comp (ref "R264")
      (value "R_user")
      (footprint "eagle-import:R0805")
      (libsource (lib "eagle-import") (part "R-EU_R0805"))
    )
    (comp (ref "R265")
      (value "104")
      (footprint "eagle-import:R0805")
      (fields (field (name "MPN") "RC0805FR-0710KL"))
      (libsource (lib "eagle-import") (part "SMD-RES-10K-1%-1/8W(0805)"))
    )
    (comp (ref "R266")
      (value "104")
      (footprint "eagle-import:R0805")
      (fields (field (name "MPN") "RC0805FR-0710KL"))
      (libsource (lib "eagle-import") (part "SMD-RES-10K-1%-1/8W(0805)"))
    )
    (comp (ref "R267")
      (value "104")
      (footprint "eagle-import:R0805")
      (fields (field (name "MPN") "RC0805FR-0710KL"))
      (libsource (lib "eagle-import") (part "SMD-RES-10K-1%-1/8W(0805)"))
    )
    (comp (ref "R268")
      (value "13")
      (footprint "eagle-import:R1206")
      (fields (field (name "MPN") "RC1206JR-0713RL"))
      (libsource (lib "eagle-import") (part "SMD-RES-13R-5%-1/4W(1206)"))
    )
    (comp (ref "R269")
      (value "2201")
      (footprint "eagle-import:R0805")
      (fields (field (name "MPN") "RC0805JR-071KL"))
      (libsource (lib "eagle-import") (part "SMD-RES-1K-5%-1/8W(0805)"))
    )
    (comp (ref "R270")
      (value "100")
      (footprint "eagle-import:R0805")
      (fields (field (name "MPN") "RC0805JR-07220RL"))
      (libsource (lib "eagle-import") (part "SMD-RES-220R-5%-1/8W(0805)"))
    )
    (comp (ref "R271")
      (value "13")
      (footprint "eagle-import:R1206")
      (fields (field (name "MPN") "RC1206JR-0713RL"))
      (libsource (lib "eagle-import") (part "SMD-RES-13R-5%-1/4W(1206)"))
    )
    (comp (ref "R272")
      (value "4701")
      (footprint "eagle-import:R0805")
      (fields (field (name "MPN") "RC0805JR-074K7L"))
      (libsource (lib "eagle-import") (part "SMD-RES-4.7K-5%-1/8W(0805)"))
    )
    (comp (ref "R273")
      (value "104")
      (footprint "eagle-import:R0805")
      (fields (field (name "MPN") "RC0805JR-074K7L"))
      (libsource (lib "eagle-import") (part "SMD-RES-4.7K-5%-1/8W(0805)"))
    )
    (comp (ref "R274")
      (value "100")
      (footprint "eagle-import:R0805")
      (fields (field (name "MPN") "RC0805JR-072K2L"))
      (libsource (lib "eagle-import") (part "SMD-RES-2.2K-5%-1/8W(0805)"))
    )
    (comp (ref "R275")
      (value "100")
      (footprint "eagle-import:R0805")
      (fields (field (name "MPN") "RC0805JR-072K2L"))
      (libsource (lib "eagle-import") (part "SMD-RES-2.2K-5%-1/8W(0805)"))
    )
    (comp (ref "SJ4")
      (value "SJ")
      (footprint "eagle-import:SJ")
      (libsource (lib "eagle-import") (part "solder-jumper_SJ"))
    )
    (comp (ref "SJMP4")
      (value "SJ")
      (footprint "eagle-import:SJ")
      (libsource (lib "eagle-import") (part "SJ"))
    )
    (comp (ref "START4")
      (value "TPSB2.0")
      (footprint "eagle-import:B2.0")
      (libsource (lib "eagle-import") (part "TPSB2.0"))
    )
    (comp (ref "TP93")
      (value "TPSB2.0")
      (footprint "eagle-import:B2.0")
      (libsource (lib "eagle-import") (part "TPSB2.0"))
    )
    (comp (ref "TP94")
      (value "TPSB2.0")
      (footprint "eagle-import:B2.0")
      (libsource (lib "eagle-import") (part "TPSB2.0"))
    )
    (comp (ref "TP95")
      (value "TPSB2.0")
      (footprint "eagle-import:B2.0")
      (libsource (lib "eagle-import") (part "TPSB2.0"))
    )
    (comp (ref "TP96")
      (value "TPSB2.0")
      (footprint "eagle-import:B2.0")
      (libsource (lib "eagle-import") (part "TPSB2.0"))
    )
    (comp (ref "TP97")
      (value "TPSB2.0")
      (footprint "eagle-import:B2.0")
      (libsource (lib "eagle-import") (part "TPSB2.0"))
    )
    (comp (ref "TP98")
      (value "TPSB2.0")
      (footprint "eagle-import:B2.0")
      (libsource (lib "eagle-import") (part "TPSB2.0"))
    )
    (comp (ref "TP99")
      (value "TPSB2.0")
      (footprint "eagle-import:B2.0")
      (libsource (lib "eagle-import") (part "TPSB2.0"))
    )
    (comp (ref "TP100")
      (value "TPSB2.0")
      (footprint "eagle-import:B2.0")
      (libsource (lib "eagle-import") (part "TPSB2.0"))
    )
    (comp (ref "TP101")
      (value "TPSB2.0")
      (footprint "eagle-import:B2.0")
      (libsource (lib "eagle-import") (part "TPSB2.0"))
    )
    (comp (ref "TP102")
      (value "TPSB2.0")
      (footprint "eagle-import:B2.0")
      (libsource (lib "eagle-import") (part "TPSB2.0"))
    )
    (comp (ref "TP103")
      (value "TPSB2.0")
      (footprint "eagle-import:B2.0")
      (libsource (lib "eagle-import") (part "TPSB2.0"))
    )
    (comp (ref "TP104")
      (value "TPSB2.0")
      (footprint "eagle-import:B2.0")
      (libsource (lib "eagle-import") (part "TPSB2.0"))
    )
    (comp (ref "TP105")
      (value "TPSB2.0")
      (footprint "eagle-import:B2.0")
      (libsource (lib "eagle-import") (part "TPSB2.0"))
    )
    (comp (ref "TP106")
      (value "TPSB2.0")
      (footprint "eagle-import:B2.0")
      (libsource (lib "eagle-import") (part "TPSB2.0"))
    )
    (comp (ref "TP107")
      (value "TPSB2.0")
      (footprint "eagle-import:B2.0")
      (libsource (lib "eagle-import") (part "TPSB2.0"))
    )
    (comp (ref "TP108")
      (value "TPSB2.0")
      (footprint "eagle-import:B2.0")
      (libsource (lib "eagle-import") (part "TPSB2.0"))
    )
    (comp (ref "TP109")
      (value "TPSB2.0")
      (footprint "eagle-import:B2.0")
      (libsource (lib "eagle-import") (part "TPSB2.0"))
    )
    (comp (ref "TP110")
      (value "TPSB2.0")
      (footprint "eagle-import:B2.0")
      (libsource (lib "eagle-import") (part "TPSB2.0"))
    )
    (comp (ref "TP111")
      (value "TPSB1,27")
      (footprint "eagle-import:B1,27")
      (libsource (lib "eagle-import") (part "TPSB1,27"))
    )
    (comp (ref "TP112")
      (value "TPSB2.0")
      (footprint "eagle-import:B2.0")
      (libsource (lib "eagle-import") (part "TPSB2.0"))
    )
    (comp (ref "TP113")
      (value "TPSB2.0")
      (footprint "eagle-import:B2.0")
      (libsource (lib "eagle-import") (part "TPSB2.0"))
    )
    (comp (ref "TP114")
      (value "TPSB2.0")
      (footprint "eagle-import:B2.0")
      (libsource (lib "eagle-import") (part "TPSB2.0"))
    )
    (comp (ref "TP115")
      (value "TPSB2.0")
      (footprint "eagle-import:B2.0")
      (libsource (lib "eagle-import") (part "TPSB2.0"))
    )
    (comp (ref "X10")
      (value "CON_BMWV2")
      (footprint "eagle-import:24-PIN_V2")
      (libsource (lib "eagle-import") (part "CON_BMWV2"))
    )
    (comp (ref "X11")
      (value "22-23-2051")
      (footprint "eagle-import:22-23-2051")
      (fields (field (name "MF") "MOLEX"))
      (libsource (lib "eagle-import") (part "22-23-2051"))
    )
    (comp (ref "X12")
      (value "22-23-2021")
      (footprint "eagle-import:22-23-2021")
      (fields (field (name "MF") "MOLEX"))
      (libsource (lib "eagle-import") (part "22-23-2021"))
    )
    (comp (ref "6V5")
      (value "TPSB2.0")
      (footprint "eagle-import:B2.0")
      (libsource (lib "eagle-import") (part "TPSB2.0"))
    )
    (comp (ref "10V5")
      (value "TPSB2.0")
      (footprint "eagle-import:B2.0")
      (libsource (lib "eagle-import") (part "TPSB2.0"))
    )
    (comp (ref "11")
      (value "2081-1132")
      (footprint "eagle-import:12-PIN")
      (libsource (lib "eagle-import") (part "2081-1132"))
    )
    (comp (ref "12")
      (value "2081-1132")
      (footprint "eagle-import:12-PIN")
      (libsource (lib "eagle-import") (part "2081-1132"))
    )
    (comp (ref "C51")
      (value "100u")
      (footprint "eagle-import:C1206")
      (fields (field (name "MPN") "GRM31CR60J107ME39L"))
      (libsource (lib "eagle-import") (part "CERAMIC-100UF-6.3V-20%-X5R(1206)"))
    )
    (comp (ref "C52")
      (value "100u")
      (footprint "eagle-import:C1206")
      (fields (field (name "MPN") "GRM31CR60J107ME39L"))
      (libsource (lib "eagle-import") (part "CERAMIC-100UF-6.3V-20%-X5R(1206)"))
    )
    (comp (ref "C53")
      (value "100nF,")
      (footprint "eagle-import:C0805")
      (fields (field (name "MPN") "CC0805KRX7R9BB104"))
      (libsource (lib "eagle-import") (part "CERAMIC-100NF-50V-10%-X7R(0805)"))
    )
    (comp (ref "C54")
      (value "4.7u")
      (footprint "eagle-import:C0805")
      (fields (field (name "MPN") "CC0805KKX5R8BB475"))
      (libsource (lib "eagle-import") (part "CERAMIC-4.7UF-25V-10%-X5R(0805)"))
    )
    (comp (ref "C55")
      (value "100nF.")
      (footprint "eagle-import:C0805")
      (fields (field (name "MPN") "CC0805KRX7R9BB104"))
      (libsource (lib "eagle-import") (part "CERAMIC-100NF-50V-10%-X7R(0805)"))
    )
    (comp (ref "C56")
      (value "100nF.")
      (footprint "eagle-import:C0805")
      (fields (field (name "MPN") "CC0805KRX7R9BB104"))
      (libsource (lib "eagle-import") (part "CERAMIC-100NF-50V-10%-X7R(0805)"))
    )
    (comp (ref "C57")
      (value "2.2nF")
      (footprint "eagle-import:C0805")
      (fields (field (name "MPN") "CC0805KRX7R9BB104"))
      (libsource (lib "eagle-import") (part "CERAMIC-100NF-50V-10%-X7R(0805)"))
    )
    (comp (ref "C58")
      (value "100nF")
      (footprint "eagle-import:C0805")
      (fields (field (name "MPN") "CC0805KRX7R9BB104"))
      (libsource (lib "eagle-import") (part "CERAMIC-100NF-50V-10%-X7R(0805)"))
    )
    (comp (ref "C59")
      (value "100nF")
      (footprint "eagle-import:C0805")
      (fields (field (name "MPN") "CC0805KRX7R9BB104"))
      (libsource (lib "eagle-import") (part "CERAMIC-100NF-50V-10%-X7R(0805)"))
    )
    (comp (ref "C60")
      (value "100nF,")
      (footprint "eagle-import:C0805")
      (fields (field (name "MPN") "CC0805KRX7R9BB104"))
      (libsource (lib "eagle-import") (part "CERAMIC-100NF-50V-10%-X7R(0805)"))
    )
    (comp (ref "C61")
      (value "4.7u")
      (footprint "eagle-import:C0805")
      (fields (field (name "MPN") "CC0805KKX5R8BB475"))
      (libsource (lib "eagle-import") (part "CERAMIC-4.7UF-25V-10%-X5R(0805)"))
    )
    (comp (ref "C62")
      (value "10u")
      (footprint "eagle-import:C1206")
      (fields (field (name "MPN") "GRM31CR60J107ME39L"))
      (libsource (lib "eagle-import") (part "CERAMIC-100UF-6.3V-20%-X5R(1206)"))
    )
    (comp (ref "D60")
      (value "1N4007,")
      (footprint "eagle-import:DO-214AC")
      (fields (field (name "MPN") "1N4007"))
      (libsource (lib "eagle-import") (part "DIODE-GEN-PURPOSE-1KV-1A(DO-214AC)"))
    )
    (comp (ref "D61")
      (value "1N4007,")
      (footprint "eagle-import:DO-214AC")
      (fields (field (name "MPN") "1N4007"))
      (libsource (lib "eagle-import") (part "DIODE-GEN-PURPOSE-1KV-1A(DO-214AC)"))
    )
    (comp (ref "D62")
      (value "1N4007.")
      (footprint "eagle-import:DO-214AC")
      (fields (field (name "MPN") "1N4007"))
      (libsource (lib "eagle-import") (part "DIODE-GEN-PURPOSE-1KV-1A(DO-214AC)"))
    )
    (comp (ref "D63")
      (value "1N5817")
      (footprint "eagle-import:DO-214AC_SLIM")
      (libsource (lib "eagle-import") (part "DIODE-GEN-PURPOSE-1KV-1A(DO-214AC)DO-214AC/1206"))
    )
    (comp (ref "D64")
      (value "1N5817.")
      (footprint "eagle-import:DO-214AC_SLIM")
      (libsource (lib "eagle-import") (part "DIODE-GEN-PURPOSE-1KV-1A(DO-214AC)DO-214AC/1206"))
    )
    (comp (ref "D65")
      (value "1N5817.")
      (footprint "eagle-import:DO-214AC_SLIM")
      (libsource (lib "eagle-import") (part "DIODE-GEN-PURPOSE-1KV-1A(DO-214AC)DO-214AC/1206"))
    )
    (comp (ref "D66")
      (value "1N5817")
      (footprint "eagle-import:DO-214AC_SLIM")
      (libsource (lib "eagle-import") (part "DIODE-GEN-PURPOSE-1KV-1A(DO-214AC)DO-214AC/1206"))
    )
    (comp (ref "D67")
      (value "1N4007.")
      (footprint "eagle-import:DO-214AC")
      (fields (field (name "MPN") "1N4007"))
      (libsource (lib "eagle-import") (part "DIODE-GEN-PURPOSE-1KV-1A(DO-214AC)"))
    )
    (comp (ref "D68")
      (value "1N4007")
      (footprint "eagle-import:DO-214AC")
      (libsource (lib "eagle-import") (part "DIODE-GEN-PURPOSE-1KV-1A(DO-214AC)"))
    )
    (comp (ref "D69")
      (value "Zen15")
      (footprint "eagle-import:DO214AA")
      (libsource (lib "eagle-import") (part "SM6T"))
    )
    (comp (ref "D70")
      (value "SM6TDO214AA_BI")
      (footprint "eagle-import:DO214AA_BI")
      (libsource (lib "eagle-import") (part "SM6TDO214AA_BI"))
    )
    (comp (ref "D71")
      (value "SS12")
      (footprint "eagle-import:DO-214AC_SLIM")
      (libsource (lib "eagle-import") (part "DIODE-GEN-PURPOSE-1KV-1A(DO-214AC)DO-214AC/1206"))
    )
    (comp (ref "D72")
      (value "SS12")
      (footprint "eagle-import:DO-214AC_SLIM")
      (libsource (lib "eagle-import") (part "DIODE-GEN-PURPOSE-1KV-1A(DO-214AC)DO-214AC/1206"))
    )
    (comp (ref "D73")
      (value "Zen11")
      (footprint "eagle-import:SOD-123_MINI-SMA")
      (libsource (lib "eagle-import") (part "CGRM400-G1"))
    )
    (comp (ref "FID19")
      (value "FIDUCIAL")
      (footprint "eagle-import:FIDUCIAL_1MM")
      (libsource (lib "eagle-import") (part "FIDUCIAL"))
    )
    (comp (ref "FID20")
      (value "FIDUCIAL")
      (footprint "eagle-import:FIDUCIAL_1MM")
      (libsource (lib "eagle-import") (part "FIDUCIAL"))
    )
    (comp (ref "FID21")
      (value "FIDUCIAL")
      (footprint "eagle-import:FIDUCIAL_1MM")
      (libsource (lib "eagle-import") (part "FIDUCIAL"))
    )
    (comp (ref "FID22")
      (value "FIDUCIAL")
      (footprint "eagle-import:FIDUCIAL_1MM")
      (libsource (lib "eagle-import") (part "FIDUCIAL"))
    )
    (comp (ref "IC37")
      (value "4028")
      (footprint "eagle-import:SO16")
      (libsource (lib "eagle-import") (part "4028D"))
    )
    (comp (ref "IC38")
      (value "317TO202H_NOHOLE")
      (footprint "eagle-import:TO220H_NOHOLE")
      (libsource (lib "eagle-import") (part "317TO202H_NOHOLE"))
    )
    (comp (ref "IC39")
      (value "ULN2004")
      (footprint "eagle-import:SO16")
      (libsource (lib "eagle-import") (part "ULN2004AD"))
    )
    (comp (ref "IC40")
      (value "LM339")
      (footprint "eagle-import:SO14")
      (libsource (lib "eagle-import") (part "LM339D"))
    )
    (comp (ref "IC41")
      (value "78L06")
      (footprint "eagle-import:SOT89_ROUND")
      (libsource (lib "eagle-import") (part "78LXXSOT89_ROUND"))
    )
    (comp (ref "IC42")
      (value "555")
      (footprint "eagle-import:SO08")
      (libsource (lib "eagle-import") (part "555DNE"))
    )
    (comp (ref "IC43")
      (value "4538")
      (footprint "eagle-import:SO16")
      (libsource (lib "eagle-import") (part "4538D"))
    )
    (comp (ref "IC44")
      (value "78L10")
      (footprint "eagle-import:SOT89_ROUND")
      (libsource (lib "eagle-import") (part "78LXXSOT89_ROUND"))
    )
    (comp (ref "IC45")
      (value "LM2904")
      (footprint "eagle-import:SO08")
      (libsource (lib "eagle-import") (part "LM358D"))
    )
    (comp (ref "JP21")
      (value "JP2EJP2_SMALLPADS")
      (footprint "eagle-import:JP2_SMALLPADS")
      (libsource (lib "eagle-import") (part "JP2EJP2_SMALLPADS"))
    )
    (comp (ref "JP22")
      (value "JP2E_ORIG")
      (footprint "eagle-import:JP2_ORIG_SMALLPADS")
      (libsource (lib "eagle-import") (part "JP2E_ORIG"))
    )
    (comp (ref "JP23")
      (value "JP2EJP2_SMALLPADS")
      (footprint "eagle-import:JP2_SMALLPADS")
      (libsource (lib "eagle-import") (part "JP2EJP2_SMALLPADS"))
    )
    (comp (ref "JP24")
      (value "JP2EJP2_SMALLPADS")
      (footprint "eagle-import:JP2_SMALLPADS")
      (libsource (lib "eagle-import") (part "JP2EJP2_SMALLPADS"))
    )
    (comp (ref "JP25")
      (value "JP2EJP2_SMALLPADS")
      (footprint "eagle-import:JP2_SMALLPADS")
      (libsource (lib "eagle-import") (part "JP2EJP2_SMALLPADS"))
    )
    (comp (ref "LED25")
      (value "LEDLD260")
      (footprint "eagle-import:LD260")
      (libsource (lib "eagle-import") (part "LEDLD260"))
    )
    (comp (ref "LED26")
      (value "LEDLD260")
      (footprint "eagle-import:LD260")
      (libsource (lib "eagle-import") (part "LEDLD260"))
    )
    (comp (ref "LED27")
      (value "LEDLD260")
      (footprint "eagle-import:LD260")
      (libsource (lib "eagle-import") (part "LEDLD260"))
    )
    (comp (ref "LED28")
      (value "LEDLD260")
      (footprint "eagle-import:LD260")
      (libsource (lib "eagle-import") (part "LEDLD260"))
    )
    (comp (ref "LED29")
      (value "LEDLD260")
      (footprint "eagle-import:LD260")
      (libsource (lib "eagle-import") (part "LEDLD260"))
    )
    (comp (ref "LED30")
      (value "LEDLD260")
      (footprint "eagle-import:LD260")
      (libsource (lib "eagle-import") (part "LEDLD260"))
    )
    (comp (ref "Q44")
      (value "BA")
      (footprint "eagle-import:SOT89")
      (libsource (lib "eagle-import") (part "PNP-TRANSISTOR_SOT89"))
    )
    (comp (ref "Q45")
      (value "BA.")
      (footprint "eagle-import:SOT89")
      (libsource (lib "eagle-import") (part "PNP-TRANSISTOR_SOT89"))
    )
    (comp (ref "Q46")
      (value "BA.")
      (footprint "eagle-import:SOT89")
      (libsource (lib "eagle-import") (part "PNP-TRANSISTOR_SOT89"))
    )
    (comp (ref "Q47")
      (value "BA")
      (footprint "eagle-import:SOT89")
      (libsource (lib "eagle-import") (part "PNP-TRANSISTOR_SOT89"))
    )
    (comp (ref "Q48")
      (value "MY")
      (footprint "eagle-import:SOT89")
      (libsource (lib "eagle-import") (part "NPN-TRANSISTOR_SOT89"))
    )
    (comp (ref "Q49")
      (value "J1")
      (footprint "eagle-import:SOT-23")
      (fields (field (name "MPN") "BSS138W-7-F"))
      (libsource (lib "eagle-import") (part "SMD-MOSFET-N-CH-50V-200MA-BSS138W-7-F(SOT-23)"))
    )
    (comp (ref "Q50")
      (value "J1")
      (footprint "eagle-import:SOT-23")
      (fields (field (name "MPN") "BSS138W-7-F"))
      (libsource (lib "eagle-import") (part "SMD-MOSFET-N-CH-50V-200MA-BSS138W-7-F(SOT-23)"))
    )
    (comp (ref "Q51")
      (value "J1")
      (footprint "eagle-import:SOT-23")
      (fields (field (name "MPN") "BSS138W-7-F"))
      (libsource (lib "eagle-import") (part "SMD-MOSFET-N-CH-50V-200MA-BSS138W-7-F(SOT-23)"))
    )
    (comp (ref "Q52")
      (value "BA")
      (footprint "eagle-import:SOT89")
      (libsource (lib "eagle-import") (part "PNP-TRANSISTOR_SOT89"))
    )
    (comp (ref "Q53")
      (value "J1")
      (footprint "eagle-import:SOT-23")
      (fields (field (name "MPN") "BSS138W-7-F"))
      (libsource (lib "eagle-import") (part "SMD-MOSFET-N-CH-50V-200MA-BSS138W-7-F(SOT-23)"))
    )
    (comp (ref "R276")
      (value "47")
      (footprint "eagle-import:V235_17_1MM")
      (libsource (lib "eagle-import") (part "R-EU_V235/17_1MM"))
    )
    (comp (ref "R277")
      (value "13")
      (footprint "eagle-import:R1206")
      (fields (field (name "MPN") "RC1206JR-0713RL"))
      (libsource (lib "eagle-import") (part "SMD-RES-13R-5%-1/4W(1206)"))
    )
    (comp (ref "R278")
      (value "47")
      (footprint "eagle-import:V235_17_1MM")
      (libsource (lib "eagle-import") (part "R-EU_V235/17_1MM"))
    )
    (comp (ref "R279")
      (value "104")
      (footprint "eagle-import:R0805")
      (fields (field (name "MPN") "RC0805FR-0710KL"))
      (libsource (lib "eagle-import") (part "SMD-RES-10K-1%-1/8W(0805)"))
    )
    (comp (ref "R280")
      (value "104")
      (footprint "eagle-import:R0805")
      (fields (field (name "MPN") "RC0805FR-0710KL"))
      (libsource (lib "eagle-import") (part "SMD-RES-10K-1%-1/8W(0805)"))
    )
    (comp (ref "R281")
      (value "104")
      (footprint "eagle-import:R0805")
      (fields (field (name "MPN") "RC0805FR-0710KL"))
      (libsource (lib "eagle-import") (part "SMD-RES-10K-1%-1/8W(0805)"))
    )
    (comp (ref "R282")
      (value "4701")
      (footprint "eagle-import:R0805")
      (fields (field (name "MPN") "RC0805JR-074K7L"))
      (libsource (lib "eagle-import") (part "SMD-RES-4.7K-5%-1/8W(0805)"))
    )
    (comp (ref "R283")
      (value "1002")
      (footprint "eagle-import:R0805")
      (fields (field (name "MPN") "RC0805FR-0710KL"))
      (libsource (lib "eagle-import") (part "SMD-RES-10K-1%-1/8W(0805)"))
    )
    (comp (ref "R284")
      (value "1002")
      (footprint "eagle-import:R0805")
      (fields (field (name "MPN") "RC0805FR-0710KL"))
      (libsource (lib "eagle-import") (part "SMD-RES-10K-1%-1/8W(0805)"))
    )
    (comp (ref "R285")
      (value "1502")
      (footprint "eagle-import:R0805")
      (fields (field (name "MPN") "RC0805FR-0710KL"))
      (libsource (lib "eagle-import") (part "SMD-RES-10K-1%-1/8W(0805)"))
    )
    (comp (ref "R286")
      (value "104")
      (footprint "eagle-import:R0805")
      (fields (field (name "MPN") "RC0805FR-0710KL"))
      (libsource (lib "eagle-import") (part "SMD-RES-10K-1%-1/8W(0805)"))
    )
    (comp (ref "R287")
      (value "104")
      (footprint "eagle-import:R0805")
      (fields (field (name "MPN") "RC0805FR-0710KL"))
      (libsource (lib "eagle-import") (part "SMD-RES-10K-1%-1/8W(0805)"))
    )
    (comp (ref "R288")
      (value "1502")
      (footprint "eagle-import:R0805")
      (fields (field (name "MPN") "RC0805FR-0710KL"))
      (libsource (lib "eagle-import") (part "SMD-RES-10K-1%-1/8W(0805)"))
    )
    (comp (ref "R289")
      (value "1002")
      (footprint "eagle-import:R0805")
      (fields (field (name "MPN") "RC0805FR-0710KL"))
      (libsource (lib "eagle-import") (part "SMD-RES-10K-1%-1/8W(0805)"))
    )
    (comp (ref "R290")
      (value "2201")
      (footprint "eagle-import:R0805")
      (fields (field (name "MPN") "RC0805JR-072K2L"))
      (libsource (lib "eagle-import") (part "SMD-RES-2.2K-5%-1/8W(0805)"))
    )
    (comp (ref "R291")
      (value "1002")
      (footprint "eagle-import:R0805")
      (fields (field (name "MPN") "RC0805FR-0710KL"))
      (libsource (lib "eagle-import") (part "SMD-RES-10K-1%-1/8W(0805)"))
    )
    (comp (ref "R292")
      (value "4701")
      (footprint "eagle-import:R0805")
      (fields (field (name "MPN") "RC0805JR-074K7L"))
      (libsource (lib "eagle-import") (part "SMD-RES-4.7K-5%-1/8W(0805)"))
    )
    (comp (ref "R293")
      (value "2702")
      (footprint "eagle-import:R0805")
      (fields (field (name "MPN") "RC0805JR-074K7L"))
      (libsource (lib "eagle-import") (part "SMD-RES-4.7K-5%-1/8W(0805)"))
    )
    (comp (ref "R294")
      (value "102")
      (footprint "eagle-import:R0805")
      (fields (field (name "MPN") "RC0805JR-071KL"))
      (libsource (lib "eagle-import") (part "SMD-RES-1K-5%-1/8W(0805)"))
    )
    (comp (ref "R295")
      (value "R_user")
      (footprint "eagle-import:R0805")
      (libsource (lib "eagle-import") (part "R-EU_R0805"))
    )
    (comp (ref "R296")
      (value "102")
      (footprint "eagle-import:R0805")
      (fields (field (name "MPN") "RC0805JR-07220RL"))
      (libsource (lib "eagle-import") (part "SMD-RES-220R-5%-1/8W(0805)"))
    )
    (comp (ref "R297")
      (value "(101)")
      (footprint "eagle-import:R0805")
      (fields (field (name "MPN") "RC0805JR-07100RL"))
      (libsource (lib "eagle-import") (part "SMD-RES-100R-5%-1/8W(0805)"))
    )
    (comp (ref "R298")
      (value "(1000)")
      (footprint "eagle-import:R0805")
      (fields (field (name "MPN") "RC0805JR-07100RL"))
      (libsource (lib "eagle-import") (part "SMD-RES-100R-5%-1/8W(0805)"))
    )
    (comp (ref "R299")
      (value "102")
      (footprint "eagle-import:R0805")
      (fields (field (name "MPN") "RC0805JR-071KL"))
      (libsource (lib "eagle-import") (part "SMD-RES-1K-5%-1/8W(0805)"))
    )
    (comp (ref "R300")
      (value "13")
      (footprint "eagle-import:R1206")
      (fields (field (name "MPN") "RC1206JR-0713RL"))
      (libsource (lib "eagle-import") (part "SMD-RES-13R-5%-1/4W(1206)"))
    )
    (comp (ref "R301")
      (value "13")
      (footprint "eagle-import:R1206")
      (fields (field (name "MPN") "RC1206JR-0713RL"))
      (libsource (lib "eagle-import") (part "SMD-RES-13R-5%-1/4W(1206)"))
    )
    (comp (ref "R302")
      (value "2702")
      (footprint "eagle-import:R0805")
      (fields (field (name "MPN") "RC0805JR-074K7L"))
      (libsource (lib "eagle-import") (part "SMD-RES-4.7K-5%-1/8W(0805)"))
    )
    (comp (ref "R303")
      (value "4701")
      (footprint "eagle-import:R0805")
      (fields (field (name "MPN") "RC0805JR-074K7L"))
      (libsource (lib "eagle-import") (part "SMD-RES-4.7K-5%-1/8W(0805)"))
    )
    (comp (ref "R304")
      (value "100")
      (footprint "eagle-import:R0805")
      (fields (field (name "MPN") "RC0805JR-072K2L"))
      (libsource (lib "eagle-import") (part "SMD-RES-2.2K-5%-1/8W(0805)"))
    )
    (comp (ref "R305")
      (value "104")
      (footprint "eagle-import:R0805")
      (fields (field (name "MPN") "RC0805FR-0710KL"))
      (libsource (lib "eagle-import") (part "SMD-RES-10K-1%-1/8W(0805)"))
    )
    (comp (ref "R306")
      (value "104")
      (footprint "eagle-import:R0805")
      (fields (field (name "MPN") "RC0805FR-0710KL"))
      (libsource (lib "eagle-import") (part "SMD-RES-10K-1%-1/8W(0805)"))
    )
    (comp (ref "R307")
      (value "(1002)")
      (footprint "eagle-import:R0805")
      (fields (field (name "MPN") "RC0805FR-0710KL"))
      (libsource (lib "eagle-import") (part "SMD-RES-10K-1%-1/8W(0805)"))
    )
    (comp (ref "R308")
      (value "2702")
      (footprint "eagle-import:R0805")
      (fields (field (name "MPN") "RC0805FR-0710KL"))
      (libsource (lib "eagle-import") (part "SMD-RES-10K-1%-1/8W(0805)"))
    )
    (comp (ref "R309")
      (value "47")
      (footprint "eagle-import:V235_17_1MM")
      (libsource (lib "eagle-import") (part "R-EU_V235/17_1MM"))
    )
    (comp (ref "R310")
      (value "47")
      (footprint "eagle-import:V235_17_1MM")
      (libsource (lib "eagle-import") (part "R-EU_V235/17_1MM"))
    )
    (comp (ref "R311")
      (value "2702")
      (footprint "eagle-import:R0805")
      (fields (field (name "MPN") "RC0805JR-074K7L"))
      (libsource (lib "eagle-import") (part "SMD-RES-4.7K-5%-1/8W(0805)"))
    )
    (comp (ref "R312")
      (value "2201")
      (footprint "eagle-import:R0805")
      (fields (field (name "MPN") "RC0805JR-072K2L"))
      (libsource (lib "eagle-import") (part "SMD-RES-2.2K-5%-1/8W(0805)"))
    )
    (comp (ref "R313")
      (value "1002")
      (footprint "eagle-import:R0805")
      (fields (field (name "MPN") "RC0805JR-074K7L"))
      (libsource (lib "eagle-import") (part "SMD-RES-4.7K-5%-1/8W(0805)"))
    )
    (comp (ref "R314")
      (value "1002")
      (footprint "eagle-import:R0805")
      (fields (field (name "MPN") "RC0805FR-0710KL"))
      (libsource (lib "eagle-import") (part "SMD-RES-10K-1%-1/8W(0805)"))
    )
    (comp (ref "R315")
      (value "102")
      (footprint "eagle-import:R0805")
      (fields (field (name "MPN") "RC0805JR-071KL"))
      (libsource (lib "eagle-import") (part "SMD-RES-1K-5%-1/8W(0805)"))
    )
    (comp (ref "R316")
      (value "2702")
      (footprint "eagle-import:R0805")
      (fields (field (name "MPN") "RC0805JR-074K7L"))
      (libsource (lib "eagle-import") (part "SMD-RES-4.7K-5%-1/8W(0805)"))
    )
    (comp (ref "R317")
      (value "1002")
      (footprint "eagle-import:R0805")
      (fields (field (name "MPN") "RC0805JR-071KL"))
      (libsource (lib "eagle-import") (part "SMD-RES-1K-5%-1/8W(0805)"))
    )
    (comp (ref "R318")
      (value "1002")
      (footprint "eagle-import:R0805")
      (fields (field (name "MPN") "RC0805JR-071KL"))
      (libsource (lib "eagle-import") (part "SMD-RES-1K-5%-1/8W(0805)"))
    )
    (comp (ref "R319")
      (value "R_user")
      (footprint "eagle-import:R0805")
      (libsource (lib "eagle-import") (part "R-EU_R0805"))
    )
    (comp (ref "R320")
      (value "104")
      (footprint "eagle-import:R0805")
      (fields (field (name "MPN") "RC0805FR-0710KL"))
      (libsource (lib "eagle-import") (part "SMD-RES-10K-1%-1/8W(0805)"))
    )
    (comp (ref "R321")
      (value "104")
      (footprint "eagle-import:R0805")
      (fields (field (name "MPN") "RC0805FR-0710KL"))
      (libsource (lib "eagle-import") (part "SMD-RES-10K-1%-1/8W(0805)"))
    )
    (comp (ref "R322")
      (value "104")
      (footprint "eagle-import:R0805")
      (fields (field (name "MPN") "RC0805FR-0710KL"))
      (libsource (lib "eagle-import") (part "SMD-RES-10K-1%-1/8W(0805)"))
    )
    (comp (ref "R323")
      (value "13")
      (footprint "eagle-import:R1206")
      (fields (field (name "MPN") "RC1206JR-0713RL"))
      (libsource (lib "eagle-import") (part "SMD-RES-13R-5%-1/4W(1206)"))
    )
    (comp (ref "R324")
      (value "2201")
      (footprint "eagle-import:R0805")
      (fields (field (name "MPN") "RC0805JR-071KL"))
      (libsource (lib "eagle-import") (part "SMD-RES-1K-5%-1/8W(0805)"))
    )
    (comp (ref "R325")
      (value "100")
      (footprint "eagle-import:R0805")
      (fields (field (name "MPN") "RC0805JR-07220RL"))
      (libsource (lib "eagle-import") (part "SMD-RES-220R-5%-1/8W(0805)"))
    )
    (comp (ref "R326")
      (value "13")
      (footprint "eagle-import:R1206")
      (fields (field (name "MPN") "RC1206JR-0713RL"))
      (libsource (lib "eagle-import") (part "SMD-RES-13R-5%-1/4W(1206)"))
    )
    (comp (ref "R327")
      (value "4701")
      (footprint "eagle-import:R0805")
      (fields (field (name "MPN") "RC0805JR-074K7L"))
      (libsource (lib "eagle-import") (part "SMD-RES-4.7K-5%-1/8W(0805)"))
    )
    (comp (ref "R328")
      (value "104")
      (footprint "eagle-import:R0805")
      (fields (field (name "MPN") "RC0805JR-074K7L"))
      (libsource (lib "eagle-import") (part "SMD-RES-4.7K-5%-1/8W(0805)"))
    )
    (comp (ref "R329")
      (value "100")
      (footprint "eagle-import:R0805")
      (fields (field (name "MPN") "RC0805JR-072K2L"))
      (libsource (lib "eagle-import") (part "SMD-RES-2.2K-5%-1/8W(0805)"))
    )
    (comp (ref "R330")
      (value "100")
      (footprint "eagle-import:R0805")
      (fields (field (name "MPN") "RC0805JR-072K2L"))
      (libsource (lib "eagle-import") (part "SMD-RES-2.2K-5%-1/8W(0805)"))
    )
    (comp (ref "SJ5")
      (value "SJ")
      (footprint "eagle-import:SJ")
      (libsource (lib "eagle-import") (part "solder-jumper_SJ"))
    )
    (comp (ref "SJMP5")
      (value "SJ")
      (footprint "eagle-import:SJ")
      (libsource (lib "eagle-import") (part "SJ"))
    )
    (comp (ref "START5")
      (value "TPSB2.0")
      (footprint "eagle-import:B2.0")
      (libsource (lib "eagle-import") (part "TPSB2.0"))
    )
    (comp (ref "TP116")
      (value "TPSB2.0")
      (footprint "eagle-import:B2.0")
      (libsource (lib "eagle-import") (part "TPSB2.0"))
    )
    (comp (ref "TP117")
      (value "TPSB2.0")
      (footprint "eagle-import:B2.0")
      (libsource (lib "eagle-import") (part "TPSB2.0"))
    )
    (comp (ref "TP118")
      (value "TPSB2.0")
      (footprint "eagle-import:B2.0")
      (libsource (lib "eagle-import") (part "TPSB2.0"))
    )
    (comp (ref "TP119")
      (value "TPSB2.0")
      (footprint "eagle-import:B2.0")
      (libsource (lib "eagle-import") (part "TPSB2.0"))
    )
    (comp (ref "TP120")
      (value "TPSB2.0")
      (footprint "eagle-import:B2.0")
      (libsource (lib "eagle-import") (part "TPSB2.0"))
    )
    (comp (ref "TP121")
      (value "TPSB2.0")
      (footprint "eagle-import:B2.0")
      (libsource (lib "eagle-import") (part "TPSB2.0"))
    )
    (comp (ref "TP122")
      (value "TPSB2.0")
      (footprint "eagle-import:B2.0")
      (libsource (lib "eagle-import") (part "TPSB2.0"))
    )
    (comp (ref "TP123")
      (value "TPSB2.0")
      (footprint "eagle-import:B2.0")
      (libsource (lib "eagle-import") (part "TPSB2.0"))
    )
    (comp (ref "TP124")
      (value "TPSB2.0")
      (footprint "eagle-import:B2.0")
      (libsource (lib "eagle-import") (part "TPSB2.0"))
    )
    (comp (ref "TP125")
      (value "TPSB2.0")
      (footprint "eagle-import:B2.0")
      (libsource (lib "eagle-import") (part "TPSB2.0"))
    )
    (comp (ref "TP126")
      (value "TPSB2.0")
      (footprint "eagle-import:B2.0")
      (libsource (lib "eagle-import") (part "TPSB2.0"))
    )
    (comp (ref "TP127")
      (value "TPSB2.0")
      (footprint "eagle-import:B2.0")
      (libsource (lib "eagle-import") (part "TPSB2.0"))
    )
    (comp (ref "TP128")
      (value "TPSB2.0")
      (footprint "eagle-import:B2.0")
      (libsource (lib "eagle-import") (part "TPSB2.0"))
    )
    (comp (ref "TP129")
      (value "TPSB2.0")
      (footprint "eagle-import:B2.0")
      (libsource (lib "eagle-import") (part "TPSB2.0"))
    )
    (comp (ref "TP130")
      (value "TPSB2.0")
      (footprint "eagle-import:B2.0")
      (libsource (lib "eagle-import") (part "TPSB2.0"))
    )
    (comp (ref "TP131")
      (value "TPSB2.0")
      (footprint "eagle-import:B2.0")
      (libsource (lib "eagle-import") (part "TPSB2.0"))
    )
    (comp (ref "TP132")
      (value "TPSB2.0")
      (footprint "eagle-import:B2.0")
      (libsource (lib "eagle-import") (part "TPSB2.0"))
    )
    (comp (ref "TP133")
      (value "TPSB2.0")
      (footprint "eagle-import:B2.0")
      (libsource (lib "eagle-import") (part "TPSB2.0"))
    )
    (comp (ref "TP134")
      (value "TPSB1,27")
      (footprint "eagle-import:B1,27")
      (libsource (lib "eagle-import") (part "TPSB1,27"))
    )
    (comp (ref "TP135")
      (value "TPSB2.0")
      (footprint "eagle-import:B2.0")
      (libsource (lib "eagle-import") (part "TPSB2.0"))
    )
    (comp (ref "TP136")
      (value "TPSB2.0")
      (footprint "eagle-import:B2.0")
      (libsource (lib "eagle-import") (part "TPSB2.0"))
    )
    (comp (ref "TP137")
      (value "TPSB2.0")
      (footprint "eagle-import:B2.0")
      (libsource (lib "eagle-import") (part "TPSB2.0"))
    )
    (comp (ref "TP138")
      (value "TPSB2.0")
      (footprint "eagle-import:B2.0")
      (libsource (lib "eagle-import") (part "TPSB2.0"))
    )
    (comp (ref "X13")
      (value "CON_BMWV2")
      (footprint "eagle-import:24-PIN_V2")
      (libsource (lib "eagle-import") (part "CON_BMWV2"))
    )
    (comp (ref "X14")
      (value "22-23-2051")
      (footprint "eagle-import:22-23-2051")
      (fields (field (name "MF") "MOLEX"))
      (libsource (lib "eagle-import") (part "22-23-2051"))
    )
    (comp (ref "X15")
      (value "22-23-2021")
      (footprint "eagle-import:22-23-2021")
      (fields (field (name "MF") "MOLEX"))
      (libsource (lib "eagle-import") (part "22-23-2021"))
    )
    (comp (ref "6V3")
      (value "TPSB2.0")
      (footprint "eagle-import:B2.0")
      (libsource (lib "eagle-import") (part "TPSB2.0"))
    )
    (comp (ref "7")
      (value "2081-1132")
      (footprint "eagle-import:12-PIN")
      (libsource (lib "eagle-import") (part "2081-1132"))
    )
    (comp (ref "8")
      (value "2081-1132")
      (footprint "eagle-import:12-PIN")
      (libsource (lib "eagle-import") (part "2081-1132"))
    )
    (comp (ref "10V3")
      (value "TPSB2.0")
      (footprint "eagle-import:B2.0")
      (libsource (lib "eagle-import") (part "TPSB2.0"))
    )
    (comp (ref "C27")
      (value "100u")
      (footprint "eagle-import:C1206")
      (fields (field (name "MPN") "GRM31CR60J107ME39L"))
      (libsource (lib "eagle-import") (part "CERAMIC-100UF-6.3V-20%-X5R(1206)"))
    )
    (comp (ref "C28")
      (value "100u")
      (footprint "eagle-import:C1206")
      (fields (field (name "MPN") "GRM31CR60J107ME39L"))
      (libsource (lib "eagle-import") (part "CERAMIC-100UF-6.3V-20%-X5R(1206)"))
    )
    (comp (ref "C29")
      (value "100nF,")
      (footprint "eagle-import:C0805")
      (fields (field (name "MPN") "CC0805KRX7R9BB104"))
      (libsource (lib "eagle-import") (part "CERAMIC-100NF-50V-10%-X7R(0805)"))
    )
    (comp (ref "C30")
      (value "4.7u")
      (footprint "eagle-import:C0805")
      (fields (field (name "MPN") "CC0805KKX5R8BB475"))
      (libsource (lib "eagle-import") (part "CERAMIC-4.7UF-25V-10%-X5R(0805)"))
    )
    (comp (ref "C31")
      (value "100nF.")
      (footprint "eagle-import:C0805")
      (fields (field (name "MPN") "CC0805KRX7R9BB104"))
      (libsource (lib "eagle-import") (part "CERAMIC-100NF-50V-10%-X7R(0805)"))
    )
    (comp (ref "C32")
      (value "100nF.")
      (footprint "eagle-import:C0805")
      (fields (field (name "MPN") "CC0805KRX7R9BB104"))
      (libsource (lib "eagle-import") (part "CERAMIC-100NF-50V-10%-X7R(0805)"))
    )
    (comp (ref "C33")
      (value "2.2nF")
      (footprint "eagle-import:C0805")
      (fields (field (name "MPN") "CC0805KRX7R9BB104"))
      (libsource (lib "eagle-import") (part "CERAMIC-100NF-50V-10%-X7R(0805)"))
    )
    (comp (ref "C34")
      (value "100nF")
      (footprint "eagle-import:C0805")
      (fields (field (name "MPN") "CC0805KRX7R9BB104"))
      (libsource (lib "eagle-import") (part "CERAMIC-100NF-50V-10%-X7R(0805)"))
    )
    (comp (ref "C35")
      (value "100nF")
      (footprint "eagle-import:C0805")
      (fields (field (name "MPN") "CC0805KRX7R9BB104"))
      (libsource (lib "eagle-import") (part "CERAMIC-100NF-50V-10%-X7R(0805)"))
    )
    (comp (ref "C36")
      (value "100nF,")
      (footprint "eagle-import:C0805")
      (fields (field (name "MPN") "CC0805KRX7R9BB104"))
      (libsource (lib "eagle-import") (part "CERAMIC-100NF-50V-10%-X7R(0805)"))
    )
    (comp (ref "C37")
      (value "4.7u")
      (footprint "eagle-import:C0805")
      (fields (field (name "MPN") "CC0805KKX5R8BB475"))
      (libsource (lib "eagle-import") (part "CERAMIC-4.7UF-25V-10%-X5R(0805)"))
    )
    (comp (ref "C38")
      (value "10u")
      (footprint "eagle-import:C1206")
      (fields (field (name "MPN") "GRM31CR60J107ME39L"))
      (libsource (lib "eagle-import") (part "CERAMIC-100UF-6.3V-20%-X5R(1206)"))
    )
    (comp (ref "D32")
      (value "1N4007,")
      (footprint "eagle-import:DO-214AC")
      (fields (field (name "MPN") "1N4007"))
      (libsource (lib "eagle-import") (part "DIODE-GEN-PURPOSE-1KV-1A(DO-214AC)"))
    )
    (comp (ref "D33")
      (value "1N4007,")
      (footprint "eagle-import:DO-214AC")
      (fields (field (name "MPN") "1N4007"))
      (libsource (lib "eagle-import") (part "DIODE-GEN-PURPOSE-1KV-1A(DO-214AC)"))
    )
    (comp (ref "D34")
      (value "1N4007.")
      (footprint "eagle-import:DO-214AC")
      (fields (field (name "MPN") "1N4007"))
      (libsource (lib "eagle-import") (part "DIODE-GEN-PURPOSE-1KV-1A(DO-214AC)"))
    )
    (comp (ref "D35")
      (value "1N5817")
      (footprint "eagle-import:DO-214AC_SLIM")
      (libsource (lib "eagle-import") (part "DIODE-GEN-PURPOSE-1KV-1A(DO-214AC)DO-214AC/1206"))
    )
    (comp (ref "D36")
      (value "1N5817.")
      (footprint "eagle-import:DO-214AC_SLIM")
      (libsource (lib "eagle-import") (part "DIODE-GEN-PURPOSE-1KV-1A(DO-214AC)DO-214AC/1206"))
    )
    (comp (ref "D37")
      (value "1N5817.")
      (footprint "eagle-import:DO-214AC_SLIM")
      (libsource (lib "eagle-import") (part "DIODE-GEN-PURPOSE-1KV-1A(DO-214AC)DO-214AC/1206"))
    )
    (comp (ref "D38")
      (value "1N5817")
      (footprint "eagle-import:DO-214AC_SLIM")
      (libsource (lib "eagle-import") (part "DIODE-GEN-PURPOSE-1KV-1A(DO-214AC)DO-214AC/1206"))
    )
    (comp (ref "D39")
      (value "1N4007.")
      (footprint "eagle-import:DO-214AC")
      (fields (field (name "MPN") "1N4007"))
      (libsource (lib "eagle-import") (part "DIODE-GEN-PURPOSE-1KV-1A(DO-214AC)"))
    )
    (comp (ref "D40")
      (value "1N4007")
      (footprint "eagle-import:DO-214AC")
      (libsource (lib "eagle-import") (part "DIODE-GEN-PURPOSE-1KV-1A(DO-214AC)"))
    )
    (comp (ref "D41")
      (value "Zen15")
      (footprint "eagle-import:DO214AA")
      (libsource (lib "eagle-import") (part "SM6T"))
    )
    (comp (ref "D42")
      (value "SM6TDO214AA_BI")
      (footprint "eagle-import:DO214AA_BI")
      (libsource (lib "eagle-import") (part "SM6TDO214AA_BI"))
    )
    (comp (ref "D43")
      (value "SS12")
      (footprint "eagle-import:DO-214AC_SLIM")
      (libsource (lib "eagle-import") (part "DIODE-GEN-PURPOSE-1KV-1A(DO-214AC)DO-214AC/1206"))
    )
    (comp (ref "D44")
      (value "SS12")
      (footprint "eagle-import:DO-214AC_SLIM")
      (libsource (lib "eagle-import") (part "DIODE-GEN-PURPOSE-1KV-1A(DO-214AC)DO-214AC/1206"))
    )
    (comp (ref "D45")
      (value "Zen11")
      (footprint "eagle-import:SOD-123_MINI-SMA")
      (libsource (lib "eagle-import") (part "CGRM400-G1"))
    )
    (comp (ref "FID11")
      (value "FIDUCIAL")
      (footprint "eagle-import:FIDUCIAL_1MM")
      (libsource (lib "eagle-import") (part "FIDUCIAL"))
    )
    (comp (ref "FID12")
      (value "FIDUCIAL")
      (footprint "eagle-import:FIDUCIAL_1MM")
      (libsource (lib "eagle-import") (part "FIDUCIAL"))
    )
    (comp (ref "FID13")
      (value "FIDUCIAL")
      (footprint "eagle-import:FIDUCIAL_1MM")
      (libsource (lib "eagle-import") (part "FIDUCIAL"))
    )
    (comp (ref "FID14")
      (value "FIDUCIAL")
      (footprint "eagle-import:FIDUCIAL_1MM")
      (libsource (lib "eagle-import") (part "FIDUCIAL"))
    )
    (comp (ref "IC19")
      (value "4028")
      (footprint "eagle-import:SO16")
      (libsource (lib "eagle-import") (part "4028D"))
    )
    (comp (ref "IC20")
      (value "317TO202H_NOHOLE")
      (footprint "eagle-import:TO220H_NOHOLE")
      (libsource (lib "eagle-import") (part "317TO202H_NOHOLE"))
    )
    (comp (ref "IC21")
      (value "ULN2004")
      (footprint "eagle-import:SO16")
      (libsource (lib "eagle-import") (part "ULN2004AD"))
    )
    (comp (ref "IC22")
      (value "LM339")
      (footprint "eagle-import:SO14")
      (libsource (lib "eagle-import") (part "LM339D"))
    )
    (comp (ref "IC23")
      (value "78L06")
      (footprint "eagle-import:SOT89_ROUND")
      (libsource (lib "eagle-import") (part "78LXXSOT89_ROUND"))
    )
    (comp (ref "IC24")
      (value "555")
      (footprint "eagle-import:SO08")
      (libsource (lib "eagle-import") (part "555DNE"))
    )
    (comp (ref "IC25")
      (value "4538")
      (footprint "eagle-import:SO16")
      (libsource (lib "eagle-import") (part "4538D"))
    )
    (comp (ref "IC26")
      (value "78L10")
      (footprint "eagle-import:SOT89_ROUND")
      (libsource (lib "eagle-import") (part "78LXXSOT89_ROUND"))
    )
    (comp (ref "IC27")
      (value "LM2904")
      (footprint "eagle-import:SO08")
      (libsource (lib "eagle-import") (part "LM358D"))
    )
    (comp (ref "JP11")
      (value "JP2EJP2_SMALLPADS")
      (footprint "eagle-import:JP2_SMALLPADS")
      (libsource (lib "eagle-import") (part "JP2EJP2_SMALLPADS"))
    )
    (comp (ref "JP12")
      (value "JP2E_ORIG")
      (footprint "eagle-import:JP2_ORIG_SMALLPADS")
      (libsource (lib "eagle-import") (part "JP2E_ORIG"))
    )
    (comp (ref "JP13")
      (value "JP2EJP2_SMALLPADS")
      (footprint "eagle-import:JP2_SMALLPADS")
      (libsource (lib "eagle-import") (part "JP2EJP2_SMALLPADS"))
    )
    (comp (ref "JP14")
      (value "JP2EJP2_SMALLPADS")
      (footprint "eagle-import:JP2_SMALLPADS")
      (libsource (lib "eagle-import") (part "JP2EJP2_SMALLPADS"))
    )
    (comp (ref "JP15")
      (value "JP2EJP2_SMALLPADS")
      (footprint "eagle-import:JP2_SMALLPADS")
      (libsource (lib "eagle-import") (part "JP2EJP2_SMALLPADS"))
    )
    (comp (ref "LED13")
      (value "LEDLD260")
      (footprint "eagle-import:LD260")
      (libsource (lib "eagle-import") (part "LEDLD260"))
    )
    (comp (ref "LED14")
      (value "LEDLD260")
      (footprint "eagle-import:LD260")
      (libsource (lib "eagle-import") (part "LEDLD260"))
    )
    (comp (ref "LED15")
      (value "LEDLD260")
      (footprint "eagle-import:LD260")
      (libsource (lib "eagle-import") (part "LEDLD260"))
    )
    (comp (ref "LED16")
      (value "LEDLD260")
      (footprint "eagle-import:LD260")
      (libsource (lib "eagle-import") (part "LEDLD260"))
    )
    (comp (ref "LED17")
      (value "LEDLD260")
      (footprint "eagle-import:LD260")
      (libsource (lib "eagle-import") (part "LEDLD260"))
    )
    (comp (ref "LED18")
      (value "LEDLD260")
      (footprint "eagle-import:LD260")
      (libsource (lib "eagle-import") (part "LEDLD260"))
    )
    (comp (ref "Q24")
      (value "BA")
      (footprint "eagle-import:SOT89")
      (libsource (lib "eagle-import") (part "PNP-TRANSISTOR_SOT89"))
    )
    (comp (ref "Q25")
      (value "BA.")
      (footprint "eagle-import:SOT89")
      (libsource (lib "eagle-import") (part "PNP-TRANSISTOR_SOT89"))
    )
    (comp (ref "Q26")
      (value "BA.")
      (footprint "eagle-import:SOT89")
      (libsource (lib "eagle-import") (part "PNP-TRANSISTOR_SOT89"))
    )
    (comp (ref "Q27")
      (value "BA")
      (footprint "eagle-import:SOT89")
      (libsource (lib "eagle-import") (part "PNP-TRANSISTOR_SOT89"))
    )
    (comp (ref "Q28")
      (value "MY")
      (footprint "eagle-import:SOT89")
      (libsource (lib "eagle-import") (part "NPN-TRANSISTOR_SOT89"))
    )
    (comp (ref "Q29")
      (value "J1")
      (footprint "eagle-import:SOT-23")
      (fields (field (name "MPN") "BSS138W-7-F"))
      (libsource (lib "eagle-import") (part "SMD-MOSFET-N-CH-50V-200MA-BSS138W-7-F(SOT-23)"))
    )
    (comp (ref "Q30")
      (value "J1")
      (footprint "eagle-import:SOT-23")
      (fields (field (name "MPN") "BSS138W-7-F"))
      (libsource (lib "eagle-import") (part "SMD-MOSFET-N-CH-50V-200MA-BSS138W-7-F(SOT-23)"))
    )
    (comp (ref "Q31")
      (value "J1")
      (footprint "eagle-import:SOT-23")
      (fields (field (name "MPN") "BSS138W-7-F"))
      (libsource (lib "eagle-import") (part "SMD-MOSFET-N-CH-50V-200MA-BSS138W-7-F(SOT-23)"))
    )
    (comp (ref "Q32")
      (value "BA")
      (footprint "eagle-import:SOT89")
      (libsource (lib "eagle-import") (part "PNP-TRANSISTOR_SOT89"))
    )
    (comp (ref "Q33")
      (value "J1")
      (footprint "eagle-import:SOT-23")
      (fields (field (name "MPN") "BSS138W-7-F"))
      (libsource (lib "eagle-import") (part "SMD-MOSFET-N-CH-50V-200MA-BSS138W-7-F(SOT-23)"))
    )
    (comp (ref "R166")
      (value "47")
      (footprint "eagle-import:V235_17_1MM")
      (libsource (lib "eagle-import") (part "R-EU_V235/17_1MM"))
    )
    (comp (ref "R167")
      (value "13")
      (footprint "eagle-import:R1206")
      (fields (field (name "MPN") "RC1206JR-0713RL"))
      (libsource (lib "eagle-import") (part "SMD-RES-13R-5%-1/4W(1206)"))
    )
    (comp (ref "R168")
      (value "47")
      (footprint "eagle-import:V235_17_1MM")
      (libsource (lib "eagle-import") (part "R-EU_V235/17_1MM"))
    )
    (comp (ref "R169")
      (value "104")
      (footprint "eagle-import:R0805")
      (fields (field (name "MPN") "RC0805FR-0710KL"))
      (libsource (lib "eagle-import") (part "SMD-RES-10K-1%-1/8W(0805)"))
    )
    (comp (ref "R170")
      (value "104")
      (footprint "eagle-import:R0805")
      (fields (field (name "MPN") "RC0805FR-0710KL"))
      (libsource (lib "eagle-import") (part "SMD-RES-10K-1%-1/8W(0805)"))
    )
    (comp (ref "R171")
      (value "104")
      (footprint "eagle-import:R0805")
      (fields (field (name "MPN") "RC0805FR-0710KL"))
      (libsource (lib "eagle-import") (part "SMD-RES-10K-1%-1/8W(0805)"))
    )
    (comp (ref "R172")
      (value "4701")
      (footprint "eagle-import:R0805")
      (fields (field (name "MPN") "RC0805JR-074K7L"))
      (libsource (lib "eagle-import") (part "SMD-RES-4.7K-5%-1/8W(0805)"))
    )
    (comp (ref "R173")
      (value "1002")
      (footprint "eagle-import:R0805")
      (fields (field (name "MPN") "RC0805FR-0710KL"))
      (libsource (lib "eagle-import") (part "SMD-RES-10K-1%-1/8W(0805)"))
    )
    (comp (ref "R174")
      (value "1002")
      (footprint "eagle-import:R0805")
      (fields (field (name "MPN") "RC0805FR-0710KL"))
      (libsource (lib "eagle-import") (part "SMD-RES-10K-1%-1/8W(0805)"))
    )
    (comp (ref "R175")
      (value "1502")
      (footprint "eagle-import:R0805")
      (fields (field (name "MPN") "RC0805FR-0710KL"))
      (libsource (lib "eagle-import") (part "SMD-RES-10K-1%-1/8W(0805)"))
    )
    (comp (ref "R176")
      (value "104")
      (footprint "eagle-import:R0805")
      (fields (field (name "MPN") "RC0805FR-0710KL"))
      (libsource (lib "eagle-import") (part "SMD-RES-10K-1%-1/8W(0805)"))
    )
    (comp (ref "R177")
      (value "104")
      (footprint "eagle-import:R0805")
      (fields (field (name "MPN") "RC0805FR-0710KL"))
      (libsource (lib "eagle-import") (part "SMD-RES-10K-1%-1/8W(0805)"))
    )
    (comp (ref "R178")
      (value "1502")
      (footprint "eagle-import:R0805")
      (fields (field (name "MPN") "RC0805FR-0710KL"))
      (libsource (lib "eagle-import") (part "SMD-RES-10K-1%-1/8W(0805)"))
    )
    (comp (ref "R179")
      (value "1002")
      (footprint "eagle-import:R0805")
      (fields (field (name "MPN") "RC0805FR-0710KL"))
      (libsource (lib "eagle-import") (part "SMD-RES-10K-1%-1/8W(0805)"))
    )
    (comp (ref "R180")
      (value "2201")
      (footprint "eagle-import:R0805")
      (fields (field (name "MPN") "RC0805JR-072K2L"))
      (libsource (lib "eagle-import") (part "SMD-RES-2.2K-5%-1/8W(0805)"))
    )
    (comp (ref "R181")
      (value "1002")
      (footprint "eagle-import:R0805")
      (fields (field (name "MPN") "RC0805FR-0710KL"))
      (libsource (lib "eagle-import") (part "SMD-RES-10K-1%-1/8W(0805)"))
    )
    (comp (ref "R182")
      (value "4701")
      (footprint "eagle-import:R0805")
      (fields (field (name "MPN") "RC0805JR-074K7L"))
      (libsource (lib "eagle-import") (part "SMD-RES-4.7K-5%-1/8W(0805)"))
    )
    (comp (ref "R183")
      (value "2702")
      (footprint "eagle-import:R0805")
      (fields (field (name "MPN") "RC0805JR-074K7L"))
      (libsource (lib "eagle-import") (part "SMD-RES-4.7K-5%-1/8W(0805)"))
    )
    (comp (ref "R184")
      (value "102")
      (footprint "eagle-import:R0805")
      (fields (field (name "MPN") "RC0805JR-071KL"))
      (libsource (lib "eagle-import") (part "SMD-RES-1K-5%-1/8W(0805)"))
    )
    (comp (ref "R185")
      (value "R_user")
      (footprint "eagle-import:R0805")
      (libsource (lib "eagle-import") (part "R-EU_R0805"))
    )
    (comp (ref "R186")
      (value "102")
      (footprint "eagle-import:R0805")
      (fields (field (name "MPN") "RC0805JR-07220RL"))
      (libsource (lib "eagle-import") (part "SMD-RES-220R-5%-1/8W(0805)"))
    )
    (comp (ref "R187")
      (value "(101)")
      (footprint "eagle-import:R0805")
      (fields (field (name "MPN") "RC0805JR-07100RL"))
      (libsource (lib "eagle-import") (part "SMD-RES-100R-5%-1/8W(0805)"))
    )
    (comp (ref "R188")
      (value "(1000)")
      (footprint "eagle-import:R0805")
      (fields (field (name "MPN") "RC0805JR-07100RL"))
      (libsource (lib "eagle-import") (part "SMD-RES-100R-5%-1/8W(0805)"))
    )
    (comp (ref "R189")
      (value "102")
      (footprint "eagle-import:R0805")
      (fields (field (name "MPN") "RC0805JR-071KL"))
      (libsource (lib "eagle-import") (part "SMD-RES-1K-5%-1/8W(0805)"))
    )
    (comp (ref "R190")
      (value "13")
      (footprint "eagle-import:R1206")
      (fields (field (name "MPN") "RC1206JR-0713RL"))
      (libsource (lib "eagle-import") (part "SMD-RES-13R-5%-1/4W(1206)"))
    )
    (comp (ref "R191")
      (value "13")
      (footprint "eagle-import:R1206")
      (fields (field (name "MPN") "RC1206JR-0713RL"))
      (libsource (lib "eagle-import") (part "SMD-RES-13R-5%-1/4W(1206)"))
    )
    (comp (ref "R192")
      (value "2702")
      (footprint "eagle-import:R0805")
      (fields (field (name "MPN") "RC0805JR-074K7L"))
      (libsource (lib "eagle-import") (part "SMD-RES-4.7K-5%-1/8W(0805)"))
    )
    (comp (ref "R193")
      (value "4701")
      (footprint "eagle-import:R0805")
      (fields (field (name "MPN") "RC0805JR-074K7L"))
      (libsource (lib "eagle-import") (part "SMD-RES-4.7K-5%-1/8W(0805)"))
    )
    (comp (ref "R194")
      (value "100")
      (footprint "eagle-import:R0805")
      (fields (field (name "MPN") "RC0805JR-072K2L"))
      (libsource (lib "eagle-import") (part "SMD-RES-2.2K-5%-1/8W(0805)"))
    )
    (comp (ref "R195")
      (value "104")
      (footprint "eagle-import:R0805")
      (fields (field (name "MPN") "RC0805FR-0710KL"))
      (libsource (lib "eagle-import") (part "SMD-RES-10K-1%-1/8W(0805)"))
    )
    (comp (ref "R196")
      (value "104")
      (footprint "eagle-import:R0805")
      (fields (field (name "MPN") "RC0805FR-0710KL"))
      (libsource (lib "eagle-import") (part "SMD-RES-10K-1%-1/8W(0805)"))
    )
    (comp (ref "R197")
      (value "(1002)")
      (footprint "eagle-import:R0805")
      (fields (field (name "MPN") "RC0805FR-0710KL"))
      (libsource (lib "eagle-import") (part "SMD-RES-10K-1%-1/8W(0805)"))
    )
    (comp (ref "R198")
      (value "2702")
      (footprint "eagle-import:R0805")
      (fields (field (name "MPN") "RC0805FR-0710KL"))
      (libsource (lib "eagle-import") (part "SMD-RES-10K-1%-1/8W(0805)"))
    )
    (comp (ref "R199")
      (value "47")
      (footprint "eagle-import:V235_17_1MM")
      (libsource (lib "eagle-import") (part "R-EU_V235/17_1MM"))
    )
    (comp (ref "R200")
      (value "47")
      (footprint "eagle-import:V235_17_1MM")
      (libsource (lib "eagle-import") (part "R-EU_V235/17_1MM"))
    )
    (comp (ref "R201")
      (value "2702")
      (footprint "eagle-import:R0805")
      (fields (field (name "MPN") "RC0805JR-074K7L"))
      (libsource (lib "eagle-import") (part "SMD-RES-4.7K-5%-1/8W(0805)"))
    )
    (comp (ref "R202")
      (value "2201")
      (footprint "eagle-import:R0805")
      (fields (field (name "MPN") "RC0805JR-072K2L"))
      (libsource (lib "eagle-import") (part "SMD-RES-2.2K-5%-1/8W(0805)"))
    )
    (comp (ref "R203")
      (value "1002")
      (footprint "eagle-import:R0805")
      (fields (field (name "MPN") "RC0805JR-074K7L"))
      (libsource (lib "eagle-import") (part "SMD-RES-4.7K-5%-1/8W(0805)"))
    )
    (comp (ref "R204")
      (value "1002")
      (footprint "eagle-import:R0805")
      (fields (field (name "MPN") "RC0805FR-0710KL"))
      (libsource (lib "eagle-import") (part "SMD-RES-10K-1%-1/8W(0805)"))
    )
    (comp (ref "R205")
      (value "102")
      (footprint "eagle-import:R0805")
      (fields (field (name "MPN") "RC0805JR-071KL"))
      (libsource (lib "eagle-import") (part "SMD-RES-1K-5%-1/8W(0805)"))
    )
    (comp (ref "R206")
      (value "2702")
      (footprint "eagle-import:R0805")
      (fields (field (name "MPN") "RC0805JR-074K7L"))
      (libsource (lib "eagle-import") (part "SMD-RES-4.7K-5%-1/8W(0805)"))
    )
    (comp (ref "R207")
      (value "1002")
      (footprint "eagle-import:R0805")
      (fields (field (name "MPN") "RC0805JR-071KL"))
      (libsource (lib "eagle-import") (part "SMD-RES-1K-5%-1/8W(0805)"))
    )
    (comp (ref "R208")
      (value "1002")
      (footprint "eagle-import:R0805")
      (fields (field (name "MPN") "RC0805JR-071KL"))
      (libsource (lib "eagle-import") (part "SMD-RES-1K-5%-1/8W(0805)"))
    )
    (comp (ref "R209")
      (value "R_user")
      (footprint "eagle-import:R0805")
      (libsource (lib "eagle-import") (part "R-EU_R0805"))
    )
    (comp (ref "R210")
      (value "104")
      (footprint "eagle-import:R0805")
      (fields (field (name "MPN") "RC0805FR-0710KL"))
      (libsource (lib "eagle-import") (part "SMD-RES-10K-1%-1/8W(0805)"))
    )
    (comp (ref "R211")
      (value "104")
      (footprint "eagle-import:R0805")
      (fields (field (name "MPN") "RC0805FR-0710KL"))
      (libsource (lib "eagle-import") (part "SMD-RES-10K-1%-1/8W(0805)"))
    )
    (comp (ref "R212")
      (value "104")
      (footprint "eagle-import:R0805")
      (fields (field (name "MPN") "RC0805FR-0710KL"))
      (libsource (lib "eagle-import") (part "SMD-RES-10K-1%-1/8W(0805)"))
    )
    (comp (ref "R213")
      (value "13")
      (footprint "eagle-import:R1206")
      (fields (field (name "MPN") "RC1206JR-0713RL"))
      (libsource (lib "eagle-import") (part "SMD-RES-13R-5%-1/4W(1206)"))
    )
    (comp (ref "R214")
      (value "2201")
      (footprint "eagle-import:R0805")
      (fields (field (name "MPN") "RC0805JR-071KL"))
      (libsource (lib "eagle-import") (part "SMD-RES-1K-5%-1/8W(0805)"))
    )
    (comp (ref "R215")
      (value "100")
      (footprint "eagle-import:R0805")
      (fields (field (name "MPN") "RC0805JR-07220RL"))
      (libsource (lib "eagle-import") (part "SMD-RES-220R-5%-1/8W(0805)"))
    )
    (comp (ref "R216")
      (value "13")
      (footprint "eagle-import:R1206")
      (fields (field (name "MPN") "RC1206JR-0713RL"))
      (libsource (lib "eagle-import") (part "SMD-RES-13R-5%-1/4W(1206)"))
    )
    (comp (ref "R217")
      (value "4701")
      (footprint "eagle-import:R0805")
      (fields (field (name "MPN") "RC0805JR-074K7L"))
      (libsource (lib "eagle-import") (part "SMD-RES-4.7K-5%-1/8W(0805)"))
    )
    (comp (ref "R218")
      (value "104")
      (footprint "eagle-import:R0805")
      (fields (field (name "MPN") "RC0805JR-074K7L"))
      (libsource (lib "eagle-import") (part "SMD-RES-4.7K-5%-1/8W(0805)"))
    )
    (comp (ref "R219")
      (value "100")
      (footprint "eagle-import:R0805")
      (fields (field (name "MPN") "RC0805JR-072K2L"))
      (libsource (lib "eagle-import") (part "SMD-RES-2.2K-5%-1/8W(0805)"))
    )
    (comp (ref "R220")
      (value "100")
      (footprint "eagle-import:R0805")
      (fields (field (name "MPN") "RC0805JR-072K2L"))
      (libsource (lib "eagle-import") (part "SMD-RES-2.2K-5%-1/8W(0805)"))
    )
    (comp (ref "SJ3")
      (value "SJ")
      (footprint "eagle-import:SJ")
      (libsource (lib "eagle-import") (part "solder-jumper_SJ"))
    )
    (comp (ref "SJMP3")
      (value "SJ")
      (footprint "eagle-import:SJ")
      (libsource (lib "eagle-import") (part "SJ"))
    )
    (comp (ref "START3")
      (value "TPSB2.0")
      (footprint "eagle-import:B2.0")
      (libsource (lib "eagle-import") (part "TPSB2.0"))
    )
    (comp (ref "TP70")
      (value "TPSB2.0")
      (footprint "eagle-import:B2.0")
      (libsource (lib "eagle-import") (part "TPSB2.0"))
    )
    (comp (ref "TP71")
      (value "TPSB2.0")
      (footprint "eagle-import:B2.0")
      (libsource (lib "eagle-import") (part "TPSB2.0"))
    )
    (comp (ref "TP72")
      (value "TPSB2.0")
      (footprint "eagle-import:B2.0")
      (libsource (lib "eagle-import") (part "TPSB2.0"))
    )
    (comp (ref "TP73")
      (value "TPSB2.0")
      (footprint "eagle-import:B2.0")
      (libsource (lib "eagle-import") (part "TPSB2.0"))
    )
    (comp (ref "TP74")
      (value "TPSB2.0")
      (footprint "eagle-import:B2.0")
      (libsource (lib "eagle-import") (part "TPSB2.0"))
    )
    (comp (ref "TP75")
      (value "TPSB2.0")
      (footprint "eagle-import:B2.0")
      (libsource (lib "eagle-import") (part "TPSB2.0"))
    )
    (comp (ref "TP76")
      (value "TPSB2.0")
      (footprint "eagle-import:B2.0")
      (libsource (lib "eagle-import") (part "TPSB2.0"))
    )
    (comp (ref "TP77")
      (value "TPSB2.0")
      (footprint "eagle-import:B2.0")
      (libsource (lib "eagle-import") (part "TPSB2.0"))
    )
    (comp (ref "TP78")
      (value "TPSB2.0")
      (footprint "eagle-import:B2.0")
      (libsource (lib "eagle-import") (part "TPSB2.0"))
    )
    (comp (ref "TP79")
      (value "TPSB2.0")
      (footprint "eagle-import:B2.0")
      (libsource (lib "eagle-import") (part "TPSB2.0"))
    )
    (comp (ref "TP80")
      (value "TPSB2.0")
      (footprint "eagle-import:B2.0")
      (libsource (lib "eagle-import") (part "TPSB2.0"))
    )
    (comp (ref "TP81")
      (value "TPSB2.0")
      (footprint "eagle-import:B2.0")
      (libsource (lib "eagle-import") (part "TPSB2.0"))
    )
    (comp (ref "TP82")
      (value "TPSB2.0")
      (footprint "eagle-import:B2.0")
      (libsource (lib "eagle-import") (part "TPSB2.0"))
    )
    (comp (ref "TP83")
      (value "TPSB2.0")
      (footprint "eagle-import:B2.0")
      (libsource (lib "eagle-import") (part "TPSB2.0"))
    )
    (comp (ref "TP84")
      (value "TPSB2.0")
      (footprint "eagle-import:B2.0")
      (libsource (lib "eagle-import") (part "TPSB2.0"))
    )
    (comp (ref "TP85")
      (value "TPSB2.0")
      (footprint "eagle-import:B2.0")
      (libsource (lib "eagle-import") (part "TPSB2.0"))
    )
    (comp (ref "TP86")
      (value "TPSB2.0")
      (footprint "eagle-import:B2.0")
      (libsource (lib "eagle-import") (part "TPSB2.0"))
    )
    (comp (ref "TP87")
      (value "TPSB2.0")
      (footprint "eagle-import:B2.0")
      (libsource (lib "eagle-import") (part "TPSB2.0"))
    )
    (comp (ref "TP88")
      (value "TPSB1,27")
      (footprint "eagle-import:B1,27")
      (libsource (lib "eagle-import") (part "TPSB1,27"))
    )
    (comp (ref "TP89")
      (value "TPSB2.0")
      (footprint "eagle-import:B2.0")
      (libsource (lib "eagle-import") (part "TPSB2.0"))
    )
    (comp (ref "TP90")
      (value "TPSB2.0")
      (footprint "eagle-import:B2.0")
      (libsource (lib "eagle-import") (part "TPSB2.0"))
    )
    (comp (ref "TP91")
      (value "TPSB2.0")
      (footprint "eagle-import:B2.0")
      (libsource (lib "eagle-import") (part "TPSB2.0"))
    )
    (comp (ref "TP92")
      (value "TPSB2.0")
      (footprint "eagle-import:B2.0")
      (libsource (lib "eagle-import") (part "TPSB2.0"))
    )
    (comp (ref "X7")
      (value "CON_BMWV2")
      (footprint "eagle-import:24-PIN_V2")
      (libsource (lib "eagle-import") (part "CON_BMWV2"))
    )
    (comp (ref "X8")
      (value "22-23-2051")
      (footprint "eagle-import:22-23-2051")
      (fields (field (name "MF") "MOLEX"))
      (libsource (lib "eagle-import") (part "22-23-2051"))
    )
    (comp (ref "X9")
      (value "22-23-2021")
      (footprint "eagle-import:22-23-2021")
      (fields (field (name "MF") "MOLEX"))
      (libsource (lib "eagle-import") (part "22-23-2021"))
    )
    (comp (ref "3")
      (value "2081-1132")
      (footprint "eagle-import:12-PIN")
      (libsource (lib "eagle-import") (part "2081-1132"))
    )
    (comp (ref "4")
      (value "2081-1132")
      (footprint "eagle-import:12-PIN")
      (libsource (lib "eagle-import") (part "2081-1132"))
    )
    (comp (ref "6V1")
      (value "TPSB2.0")
      (footprint "eagle-import:B2.0")
      (libsource (lib "eagle-import") (part "TPSB2.0"))
    )
    (comp (ref "10V1")
      (value "TPSB2.0")
      (footprint "eagle-import:B2.0")
      (libsource (lib "eagle-import") (part "TPSB2.0"))
    )
    (comp (ref "C1")
      (value "100u")
      (footprint "eagle-import:C1206")
      (fields (field (name "MPN") "GRM31CR60J107ME39L"))
      (libsource (lib "eagle-import") (part "CERAMIC-100UF-6.3V-20%-X5R(1206)"))
    )
    (comp (ref "C3")
      (value "100u")
      (footprint "eagle-import:C1206")
      (fields (field (name "MPN") "GRM31CR60J107ME39L"))
      (libsource (lib "eagle-import") (part "CERAMIC-100UF-6.3V-20%-X5R(1206)"))
    )
    (comp (ref "C4")
      (value "100nF,")
      (footprint "eagle-import:C0805")
      (fields (field (name "MPN") "CC0805KRX7R9BB104"))
      (libsource (lib "eagle-import") (part "CERAMIC-100NF-50V-10%-X7R(0805)"))
    )
    (comp (ref "C5")
      (value "4.7u")
      (footprint "eagle-import:C0805")
      (fields (field (name "MPN") "CC0805KKX5R8BB475"))
      (libsource (lib "eagle-import") (part "CERAMIC-4.7UF-25V-10%-X5R(0805)"))
    )
    (comp (ref "C6")
      (value "100nF.")
      (footprint "eagle-import:C0805")
      (fields (field (name "MPN") "CC0805KRX7R9BB104"))
      (libsource (lib "eagle-import") (part "CERAMIC-100NF-50V-10%-X7R(0805)"))
    )
    (comp (ref "C7")
      (value "100nF.")
      (footprint "eagle-import:C0805")
      (fields (field (name "MPN") "CC0805KRX7R9BB104"))
      (libsource (lib "eagle-import") (part "CERAMIC-100NF-50V-10%-X7R(0805)"))
    )
    (comp (ref "C8")
      (value "2.2nF")
      (footprint "eagle-import:C0805")
      (fields (field (name "MPN") "CC0805KRX7R9BB104"))
      (libsource (lib "eagle-import") (part "CERAMIC-100NF-50V-10%-X7R(0805)"))
    )
    (comp (ref "C9")
      (value "100nF")
      (footprint "eagle-import:C0805")
      (fields (field (name "MPN") "CC0805KRX7R9BB104"))
      (libsource (lib "eagle-import") (part "CERAMIC-100NF-50V-10%-X7R(0805)"))
    )
    (comp (ref "C10")
      (value "100nF")
      (footprint "eagle-import:C0805")
      (fields (field (name "MPN") "CC0805KRX7R9BB104"))
      (libsource (lib "eagle-import") (part "CERAMIC-100NF-50V-10%-X7R(0805)"))
    )
    (comp (ref "C11")
      (value "100nF,")
      (footprint "eagle-import:C0805")
      (fields (field (name "MPN") "CC0805KRX7R9BB104"))
      (libsource (lib "eagle-import") (part "CERAMIC-100NF-50V-10%-X7R(0805)"))
    )
    (comp (ref "C12")
      (value "4.7u")
      (footprint "eagle-import:C0805")
      (fields (field (name "MPN") "CC0805KKX5R8BB475"))
      (libsource (lib "eagle-import") (part "CERAMIC-4.7UF-25V-10%-X5R(0805)"))
    )
    (comp (ref "C13")
      (value "10u")
      (footprint "eagle-import:C1206")
      (fields (field (name "MPN") "GRM31CR60J107ME39L"))
      (libsource (lib "eagle-import") (part "CERAMIC-100UF-6.3V-20%-X5R(1206)"))
    )
    (comp (ref "D3")
      (value "1N4007,")
      (footprint "eagle-import:DO-214AC")
      (fields (field (name "MPN") "1N4007"))
      (libsource (lib "eagle-import") (part "DIODE-GEN-PURPOSE-1KV-1A(DO-214AC)"))
    )
    (comp (ref "D5")
      (value "1N4007,")
      (footprint "eagle-import:DO-214AC")
      (fields (field (name "MPN") "1N4007"))
      (libsource (lib "eagle-import") (part "DIODE-GEN-PURPOSE-1KV-1A(DO-214AC)"))
    )
    (comp (ref "D6")
      (value "1N4007.")
      (footprint "eagle-import:DO-214AC")
      (fields (field (name "MPN") "1N4007"))
      (libsource (lib "eagle-import") (part "DIODE-GEN-PURPOSE-1KV-1A(DO-214AC)"))
    )
    (comp (ref "D7")
      (value "1N5817")
      (footprint "eagle-import:DO-214AC_SLIM")
      (libsource (lib "eagle-import") (part "DIODE-GEN-PURPOSE-1KV-1A(DO-214AC)DO-214AC/1206"))
    )
    (comp (ref "D8")
      (value "1N5817.")
      (footprint "eagle-import:DO-214AC_SLIM")
      (libsource (lib "eagle-import") (part "DIODE-GEN-PURPOSE-1KV-1A(DO-214AC)DO-214AC/1206"))
    )
    (comp (ref "D9")
      (value "1N5817.")
      (footprint "eagle-import:DO-214AC_SLIM")
      (libsource (lib "eagle-import") (part "DIODE-GEN-PURPOSE-1KV-1A(DO-214AC)DO-214AC/1206"))
    )
    (comp (ref "D10")
      (value "1N5817")
      (footprint "eagle-import:DO-214AC_SLIM")
      (libsource (lib "eagle-import") (part "DIODE-GEN-PURPOSE-1KV-1A(DO-214AC)DO-214AC/1206"))
    )
    (comp (ref "D11")
      (value "1N4007.")
      (footprint "eagle-import:DO-214AC")
      (fields (field (name "MPN") "1N4007"))
      (libsource (lib "eagle-import") (part "DIODE-GEN-PURPOSE-1KV-1A(DO-214AC)"))
    )
    (comp (ref "D12")
      (value "1N4007")
      (footprint "eagle-import:DO-214AC")
      (libsource (lib "eagle-import") (part "DIODE-GEN-PURPOSE-1KV-1A(DO-214AC)"))
    )
    (comp (ref "D13")
      (value "Zen15")
      (footprint "eagle-import:DO214AA")
      (libsource (lib "eagle-import") (part "SM6T"))
    )
    (comp (ref "D14")
      (value "SM6TDO214AA_BI")
      (footprint "eagle-import:DO214AA_BI")
      (libsource (lib "eagle-import") (part "SM6TDO214AA_BI"))
    )
    (comp (ref "D15")
      (value "SS12")
      (footprint "eagle-import:DO-214AC_SLIM")
      (libsource (lib "eagle-import") (part "DIODE-GEN-PURPOSE-1KV-1A(DO-214AC)DO-214AC/1206"))
    )
    (comp (ref "D16")
      (value "SS12")
      (footprint "eagle-import:DO-214AC_SLIM")
      (libsource (lib "eagle-import") (part "DIODE-GEN-PURPOSE-1KV-1A(DO-214AC)DO-214AC/1206"))
    )
    (comp (ref "D17")
      (value "Zen11")
      (footprint "eagle-import:SOD-123_MINI-SMA")
      (libsource (lib "eagle-import") (part "CGRM400-G1"))
    )
    (comp (ref "FID3")
      (value "FIDUCIAL")
      (footprint "eagle-import:FIDUCIAL_1MM")
      (libsource (lib "eagle-import") (part "FIDUCIAL"))
    )
    (comp (ref "FID4")
      (value "FIDUCIAL")
      (footprint "eagle-import:FIDUCIAL_1MM")
      (libsource (lib "eagle-import") (part "FIDUCIAL"))
    )
    (comp (ref "FID5")
      (value "FIDUCIAL")
      (footprint "eagle-import:FIDUCIAL_1MM")
      (libsource (lib "eagle-import") (part "FIDUCIAL"))
    )
    (comp (ref "FID6")
      (value "FIDUCIAL")
      (footprint "eagle-import:FIDUCIAL_1MM")
      (libsource (lib "eagle-import") (part "FIDUCIAL"))
    )
    (comp (ref "IC1")
      (value "4028")
      (footprint "eagle-import:SO16")
      (libsource (lib "eagle-import") (part "4028D"))
    )
    (comp (ref "IC2")
      (value "317TO202H_NOHOLE")
      (footprint "eagle-import:TO220H_NOHOLE")
      (libsource (lib "eagle-import") (part "317TO202H_NOHOLE"))
    )
    (comp (ref "IC3")
      (value "ULN2004")
      (footprint "eagle-import:SO16")
      (libsource (lib "eagle-import") (part "ULN2004AD"))
    )
    (comp (ref "IC4")
      (value "LM339")
      (footprint "eagle-import:SO14")
      (libsource (lib "eagle-import") (part "LM339D"))
    )
    (comp (ref "IC5")
      (value "78L06")
      (footprint "eagle-import:SOT89_ROUND")
      (libsource (lib "eagle-import") (part "78LXXSOT89_ROUND"))
    )
    (comp (ref "IC6")
      (value "555")
      (footprint "eagle-import:SO08")
      (libsource (lib "eagle-import") (part "555DNE"))
    )
    (comp (ref "IC7")
      (value "4538")
      (footprint "eagle-import:SO16")
      (libsource (lib "eagle-import") (part "4538D"))
    )
    (comp (ref "IC8")
      (value "78L10")
      (footprint "eagle-import:SOT89_ROUND")
      (libsource (lib "eagle-import") (part "78LXXSOT89_ROUND"))
    )
    (comp (ref "IC9")
      (value "LM2904")
      (footprint "eagle-import:SO08")
      (libsource (lib "eagle-import") (part "LM358D"))
    )
    (comp (ref "JP1")
      (value "JP2EJP2_SMALLPADS")
      (footprint "eagle-import:JP2_SMALLPADS")
      (libsource (lib "eagle-import") (part "JP2EJP2_SMALLPADS"))
    )
    (comp (ref "JP2")
      (value "JP2E_ORIG")
      (footprint "eagle-import:JP2_ORIG_SMALLPADS")
      (libsource (lib "eagle-import") (part "JP2E_ORIG"))
    )
    (comp (ref "JP3")
      (value "JP2EJP2_SMALLPADS")
      (footprint "eagle-import:JP2_SMALLPADS")
      (libsource (lib "eagle-import") (part "JP2EJP2_SMALLPADS"))
    )
    (comp (ref "JP4")
      (value "JP2EJP2_SMALLPADS")
      (footprint "eagle-import:JP2_SMALLPADS")
      (libsource (lib "eagle-import") (part "JP2EJP2_SMALLPADS"))
    )
    (comp (ref "JP5")
      (value "JP2EJP2_SMALLPADS")
      (footprint "eagle-import:JP2_SMALLPADS")
      (libsource (lib "eagle-import") (part "JP2EJP2_SMALLPADS"))
    )
    (comp (ref "LED1")
      (value "LEDLD260")
      (footprint "eagle-import:LD260")
      (libsource (lib "eagle-import") (part "LEDLD260"))
    )
    (comp (ref "LED2")
      (value "LEDLD260")
      (footprint "eagle-import:LD260")
      (libsource (lib "eagle-import") (part "LEDLD260"))
    )
    (comp (ref "LED3")
      (value "LEDLD260")
      (footprint "eagle-import:LD260")
      (libsource (lib "eagle-import") (part "LEDLD260"))
    )
    (comp (ref "LED4")
      (value "LEDLD260")
      (footprint "eagle-import:LD260")
      (libsource (lib "eagle-import") (part "LEDLD260"))
    )
    (comp (ref "LED5")
      (value "LEDLD260")
      (footprint "eagle-import:LD260")
      (libsource (lib "eagle-import") (part "LEDLD260"))
    )
    (comp (ref "LED6")
      (value "LEDLD260")
      (footprint "eagle-import:LD260")
      (libsource (lib "eagle-import") (part "LEDLD260"))
    )
    (comp (ref "Q4")
      (value "BA")
      (footprint "eagle-import:SOT89")
      (libsource (lib "eagle-import") (part "PNP-TRANSISTOR_SOT89"))
    )
    (comp (ref "Q5")
      (value "BA.")
      (footprint "eagle-import:SOT89")
      (libsource (lib "eagle-import") (part "PNP-TRANSISTOR_SOT89"))
    )
    (comp (ref "Q6")
      (value "BA.")
      (footprint "eagle-import:SOT89")
      (libsource (lib "eagle-import") (part "PNP-TRANSISTOR_SOT89"))
    )
    (comp (ref "Q7")
      (value "BA")
      (footprint "eagle-import:SOT89")
      (libsource (lib "eagle-import") (part "PNP-TRANSISTOR_SOT89"))
    )
    (comp (ref "Q8")
      (value "MY")
      (footprint "eagle-import:SOT89")
      (libsource (lib "eagle-import") (part "NPN-TRANSISTOR_SOT89"))
    )
    (comp (ref "Q9")
      (value "J1")
      (footprint "eagle-import:SOT-23")
      (fields (field (name "MPN") "BSS138W-7-F"))
      (libsource (lib "eagle-import") (part "SMD-MOSFET-N-CH-50V-200MA-BSS138W-7-F(SOT-23)"))
    )
    (comp (ref "Q10")
      (value "J1")
      (footprint "eagle-import:SOT-23")
      (fields (field (name "MPN") "BSS138W-7-F"))
      (libsource (lib "eagle-import") (part "SMD-MOSFET-N-CH-50V-200MA-BSS138W-7-F(SOT-23)"))
    )
    (comp (ref "Q11")
      (value "J1")
      (footprint "eagle-import:SOT-23")
      (fields (field (name "MPN") "BSS138W-7-F"))
      (libsource (lib "eagle-import") (part "SMD-MOSFET-N-CH-50V-200MA-BSS138W-7-F(SOT-23)"))
    )
    (comp (ref "Q12")
      (value "BA")
      (footprint "eagle-import:SOT89")
      (libsource (lib "eagle-import") (part "PNP-TRANSISTOR_SOT89"))
    )
    (comp (ref "Q13")
      (value "J1")
      (footprint "eagle-import:SOT-23")
      (fields (field (name "MPN") "BSS138W-7-F"))
      (libsource (lib "eagle-import") (part "SMD-MOSFET-N-CH-50V-200MA-BSS138W-7-F(SOT-23)"))
    )
    (comp (ref "R7")
      (value "47")
      (footprint "eagle-import:V235_17_1MM")
      (libsource (lib "eagle-import") (part "R-EU_V235/17_1MM"))
    )
    (comp (ref "R11")
      (value "13")
      (footprint "eagle-import:R1206")
      (fields (field (name "MPN") "RC1206JR-0713RL"))
      (libsource (lib "eagle-import") (part "SMD-RES-13R-5%-1/4W(1206)"))
    )
    (comp (ref "R14")
      (value "47")
      (footprint "eagle-import:V235_17_1MM")
      (libsource (lib "eagle-import") (part "R-EU_V235/17_1MM"))
    )
    (comp (ref "R15")
      (value "104")
      (footprint "eagle-import:R0805")
      (fields (field (name "MPN") "RC0805FR-0710KL"))
      (libsource (lib "eagle-import") (part "SMD-RES-10K-1%-1/8W(0805)"))
    )
    (comp (ref "R16")
      (value "104")
      (footprint "eagle-import:R0805")
      (fields (field (name "MPN") "RC0805FR-0710KL"))
      (libsource (lib "eagle-import") (part "SMD-RES-10K-1%-1/8W(0805)"))
    )
    (comp (ref "R17")
      (value "104")
      (footprint "eagle-import:R0805")
      (fields (field (name "MPN") "RC0805FR-0710KL"))
      (libsource (lib "eagle-import") (part "SMD-RES-10K-1%-1/8W(0805)"))
    )
    (comp (ref "R18")
      (value "4701")
      (footprint "eagle-import:R0805")
      (fields (field (name "MPN") "RC0805JR-074K7L"))
      (libsource (lib "eagle-import") (part "SMD-RES-4.7K-5%-1/8W(0805)"))
    )
    (comp (ref "R19")
      (value "1002")
      (footprint "eagle-import:R0805")
      (fields (field (name "MPN") "RC0805FR-0710KL"))
      (libsource (lib "eagle-import") (part "SMD-RES-10K-1%-1/8W(0805)"))
    )
    (comp (ref "R20")
      (value "1002")
      (footprint "eagle-import:R0805")
      (fields (field (name "MPN") "RC0805FR-0710KL"))
      (libsource (lib "eagle-import") (part "SMD-RES-10K-1%-1/8W(0805)"))
    )
    (comp (ref "R21")
      (value "1502")
      (footprint "eagle-import:R0805")
      (fields (field (name "MPN") "RC0805FR-0710KL"))
      (libsource (lib "eagle-import") (part "SMD-RES-10K-1%-1/8W(0805)"))
    )
    (comp (ref "R22")
      (value "104")
      (footprint "eagle-import:R0805")
      (fields (field (name "MPN") "RC0805FR-0710KL"))
      (libsource (lib "eagle-import") (part "SMD-RES-10K-1%-1/8W(0805)"))
    )
    (comp (ref "R23")
      (value "104")
      (footprint "eagle-import:R0805")
      (fields (field (name "MPN") "RC0805FR-0710KL"))
      (libsource (lib "eagle-import") (part "SMD-RES-10K-1%-1/8W(0805)"))
    )
    (comp (ref "R24")
      (value "1502")
      (footprint "eagle-import:R0805")
      (fields (field (name "MPN") "RC0805FR-0710KL"))
      (libsource (lib "eagle-import") (part "SMD-RES-10K-1%-1/8W(0805)"))
    )
    (comp (ref "R25")
      (value "1002")
      (footprint "eagle-import:R0805")
      (fields (field (name "MPN") "RC0805FR-0710KL"))
      (libsource (lib "eagle-import") (part "SMD-RES-10K-1%-1/8W(0805)"))
    )
    (comp (ref "R26")
      (value "2201")
      (footprint "eagle-import:R0805")
      (fields (field (name "MPN") "RC0805JR-072K2L"))
      (libsource (lib "eagle-import") (part "SMD-RES-2.2K-5%-1/8W(0805)"))
    )
    (comp (ref "R27")
      (value "1002")
      (footprint "eagle-import:R0805")
      (fields (field (name "MPN") "RC0805FR-0710KL"))
      (libsource (lib "eagle-import") (part "SMD-RES-10K-1%-1/8W(0805)"))
    )
    (comp (ref "R28")
      (value "4701")
      (footprint "eagle-import:R0805")
      (fields (field (name "MPN") "RC0805JR-074K7L"))
      (libsource (lib "eagle-import") (part "SMD-RES-4.7K-5%-1/8W(0805)"))
    )
    (comp (ref "R29")
      (value "2702")
      (footprint "eagle-import:R0805")
      (fields (field (name "MPN") "RC0805JR-074K7L"))
      (libsource (lib "eagle-import") (part "SMD-RES-4.7K-5%-1/8W(0805)"))
    )
    (comp (ref "R30")
      (value "102")
      (footprint "eagle-import:R0805")
      (fields (field (name "MPN") "RC0805JR-071KL"))
      (libsource (lib "eagle-import") (part "SMD-RES-1K-5%-1/8W(0805)"))
    )
    (comp (ref "R31")
      (value "R_user")
      (footprint "eagle-import:R0805")
      (libsource (lib "eagle-import") (part "R-EU_R0805"))
    )
    (comp (ref "R32")
      (value "102")
      (footprint "eagle-import:R0805")
      (fields (field (name "MPN") "RC0805JR-07220RL"))
      (libsource (lib "eagle-import") (part "SMD-RES-220R-5%-1/8W(0805)"))
    )
    (comp (ref "R33")
      (value "(101)")
      (footprint "eagle-import:R0805")
      (fields (field (name "MPN") "RC0805JR-07100RL"))
      (libsource (lib "eagle-import") (part "SMD-RES-100R-5%-1/8W(0805)"))
    )
    (comp (ref "R34")
      (value "(1000)")
      (footprint "eagle-import:R0805")
      (fields (field (name "MPN") "RC0805JR-07100RL"))
      (libsource (lib "eagle-import") (part "SMD-RES-100R-5%-1/8W(0805)"))
    )
    (comp (ref "R35")
      (value "102")
      (footprint "eagle-import:R0805")
      (fields (field (name "MPN") "RC0805JR-071KL"))
      (libsource (lib "eagle-import") (part "SMD-RES-1K-5%-1/8W(0805)"))
    )
    (comp (ref "R36")
      (value "13")
      (footprint "eagle-import:R1206")
      (fields (field (name "MPN") "RC1206JR-0713RL"))
      (libsource (lib "eagle-import") (part "SMD-RES-13R-5%-1/4W(1206)"))
    )
    (comp (ref "R37")
      (value "13")
      (footprint "eagle-import:R1206")
      (fields (field (name "MPN") "RC1206JR-0713RL"))
      (libsource (lib "eagle-import") (part "SMD-RES-13R-5%-1/4W(1206)"))
    )
    (comp (ref "R38")
      (value "2702")
      (footprint "eagle-import:R0805")
      (fields (field (name "MPN") "RC0805JR-074K7L"))
      (libsource (lib "eagle-import") (part "SMD-RES-4.7K-5%-1/8W(0805)"))
    )
    (comp (ref "R39")
      (value "4701")
      (footprint "eagle-import:R0805")
      (fields (field (name "MPN") "RC0805JR-074K7L"))
      (libsource (lib "eagle-import") (part "SMD-RES-4.7K-5%-1/8W(0805)"))
    )
    (comp (ref "R40")
      (value "100")
      (footprint "eagle-import:R0805")
      (fields (field (name "MPN") "RC0805JR-072K2L"))
      (libsource (lib "eagle-import") (part "SMD-RES-2.2K-5%-1/8W(0805)"))
    )
    (comp (ref "R41")
      (value "104")
      (footprint "eagle-import:R0805")
      (fields (field (name "MPN") "RC0805FR-0710KL"))
      (libsource (lib "eagle-import") (part "SMD-RES-10K-1%-1/8W(0805)"))
    )
    (comp (ref "R42")
      (value "104")
      (footprint "eagle-import:R0805")
      (fields (field (name "MPN") "RC0805FR-0710KL"))
      (libsource (lib "eagle-import") (part "SMD-RES-10K-1%-1/8W(0805)"))
    )
    (comp (ref "R43")
      (value "(1002)")
      (footprint "eagle-import:R0805")
      (fields (field (name "MPN") "RC0805FR-0710KL"))
      (libsource (lib "eagle-import") (part "SMD-RES-10K-1%-1/8W(0805)"))
    )
    (comp (ref "R44")
      (value "2702")
      (footprint "eagle-import:R0805")
      (fields (field (name "MPN") "RC0805FR-0710KL"))
      (libsource (lib "eagle-import") (part "SMD-RES-10K-1%-1/8W(0805)"))
    )
    (comp (ref "R45")
      (value "47")
      (footprint "eagle-import:V235_17_1MM")
      (libsource (lib "eagle-import") (part "R-EU_V235/17_1MM"))
    )
    (comp (ref "R46")
      (value "47")
      (footprint "eagle-import:V235_17_1MM")
      (libsource (lib "eagle-import") (part "R-EU_V235/17_1MM"))
    )
    (comp (ref "R47")
      (value "2702")
      (footprint "eagle-import:R0805")
      (fields (field (name "MPN") "RC0805JR-074K7L"))
      (libsource (lib "eagle-import") (part "SMD-RES-4.7K-5%-1/8W(0805)"))
    )
    (comp (ref "R48")
      (value "2201")
      (footprint "eagle-import:R0805")
      (fields (field (name "MPN") "RC0805JR-072K2L"))
      (libsource (lib "eagle-import") (part "SMD-RES-2.2K-5%-1/8W(0805)"))
    )
    (comp (ref "R49")
      (value "1002")
      (footprint "eagle-import:R0805")
      (fields (field (name "MPN") "RC0805JR-074K7L"))
      (libsource (lib "eagle-import") (part "SMD-RES-4.7K-5%-1/8W(0805)"))
    )
    (comp (ref "R50")
      (value "1002")
      (footprint "eagle-import:R0805")
      (fields (field (name "MPN") "RC0805FR-0710KL"))
      (libsource (lib "eagle-import") (part "SMD-RES-10K-1%-1/8W(0805)"))
    )
    (comp (ref "R51")
      (value "102")
      (footprint "eagle-import:R0805")
      (fields (field (name "MPN") "RC0805JR-071KL"))
      (libsource (lib "eagle-import") (part "SMD-RES-1K-5%-1/8W(0805)"))
    )
    (comp (ref "R52")
      (value "2702")
      (footprint "eagle-import:R0805")
      (fields (field (name "MPN") "RC0805JR-074K7L"))
      (libsource (lib "eagle-import") (part "SMD-RES-4.7K-5%-1/8W(0805)"))
    )
    (comp (ref "R53")
      (value "1002")
      (footprint "eagle-import:R0805")
      (fields (field (name "MPN") "RC0805JR-071KL"))
      (libsource (lib "eagle-import") (part "SMD-RES-1K-5%-1/8W(0805)"))
    )
    (comp (ref "R54")
      (value "1002")
      (footprint "eagle-import:R0805")
      (fields (field (name "MPN") "RC0805JR-071KL"))
      (libsource (lib "eagle-import") (part "SMD-RES-1K-5%-1/8W(0805)"))
    )
    (comp (ref "R55")
      (value "R_user")
      (footprint "eagle-import:R0805")
      (libsource (lib "eagle-import") (part "R-EU_R0805"))
    )
    (comp (ref "R56")
      (value "104")
      (footprint "eagle-import:R0805")
      (fields (field (name "MPN") "RC0805FR-0710KL"))
      (libsource (lib "eagle-import") (part "SMD-RES-10K-1%-1/8W(0805)"))
    )
    (comp (ref "R57")
      (value "104")
      (footprint "eagle-import:R0805")
      (fields (field (name "MPN") "RC0805FR-0710KL"))
      (libsource (lib "eagle-import") (part "SMD-RES-10K-1%-1/8W(0805)"))
    )
    (comp (ref "R58")
      (value "104")
      (footprint "eagle-import:R0805")
      (fields (field (name "MPN") "RC0805FR-0710KL"))
      (libsource (lib "eagle-import") (part "SMD-RES-10K-1%-1/8W(0805)"))
    )
    (comp (ref "R59")
      (value "13")
      (footprint "eagle-import:R1206")
      (fields (field (name "MPN") "RC1206JR-0713RL"))
      (libsource (lib "eagle-import") (part "SMD-RES-13R-5%-1/4W(1206)"))
    )
    (comp (ref "R60")
      (value "2201")
      (footprint "eagle-import:R0805")
      (fields (field (name "MPN") "RC0805JR-071KL"))
      (libsource (lib "eagle-import") (part "SMD-RES-1K-5%-1/8W(0805)"))
    )
    (comp (ref "R61")
      (value "100")
      (footprint "eagle-import:R0805")
      (fields (field (name "MPN") "RC0805JR-07220RL"))
      (libsource (lib "eagle-import") (part "SMD-RES-220R-5%-1/8W(0805)"))
    )
    (comp (ref "R62")
      (value "13")
      (footprint "eagle-import:R1206")
      (fields (field (name "MPN") "RC1206JR-0713RL"))
      (libsource (lib "eagle-import") (part "SMD-RES-13R-5%-1/4W(1206)"))
    )
    (comp (ref "R63")
      (value "4701")
      (footprint "eagle-import:R0805")
      (fields (field (name "MPN") "RC0805JR-074K7L"))
      (libsource (lib "eagle-import") (part "SMD-RES-4.7K-5%-1/8W(0805)"))
    )
    (comp (ref "R64")
      (value "104")
      (footprint "eagle-import:R0805")
      (fields (field (name "MPN") "RC0805JR-074K7L"))
      (libsource (lib "eagle-import") (part "SMD-RES-4.7K-5%-1/8W(0805)"))
    )
    (comp (ref "R65")
      (value "100")
      (footprint "eagle-import:R0805")
      (fields (field (name "MPN") "RC0805JR-072K2L"))
      (libsource (lib "eagle-import") (part "SMD-RES-2.2K-5%-1/8W(0805)"))
    )
    (comp (ref "R66")
      (value "100")
      (footprint "eagle-import:R0805")
      (fields (field (name "MPN") "RC0805JR-072K2L"))
      (libsource (lib "eagle-import") (part "SMD-RES-2.2K-5%-1/8W(0805)"))
    )
    (comp (ref "SJ1")
      (value "SJ")
      (footprint "eagle-import:SJ")
      (libsource (lib "eagle-import") (part "solder-jumper_SJ"))
    )
    (comp (ref "SJMP1")
      (value "SJ")
      (footprint "eagle-import:SJ")
      (libsource (lib "eagle-import") (part "SJ"))
    )
    (comp (ref "START1")
      (value "TPSB2.0")
      (footprint "eagle-import:B2.0")
      (libsource (lib "eagle-import") (part "TPSB2.0"))
    )
    (comp (ref "TP14")
      (value "TPSB2.0")
      (footprint "eagle-import:B2.0")
      (libsource (lib "eagle-import") (part "TPSB2.0"))
    )
    (comp (ref "TP15")
      (value "TPSB2.0")
      (footprint "eagle-import:B2.0")
      (libsource (lib "eagle-import") (part "TPSB2.0"))
    )
    (comp (ref "TP20")
      (value "TPSB2.0")
      (footprint "eagle-import:B2.0")
      (libsource (lib "eagle-import") (part "TPSB2.0"))
    )
    (comp (ref "TP27")
      (value "TPSB2.0")
      (footprint "eagle-import:B2.0")
      (libsource (lib "eagle-import") (part "TPSB2.0"))
    )
    (comp (ref "TP28")
      (value "TPSB2.0")
      (footprint "eagle-import:B2.0")
      (libsource (lib "eagle-import") (part "TPSB2.0"))
    )
    (comp (ref "TP29")
      (value "TPSB2.0")
      (footprint "eagle-import:B2.0")
      (libsource (lib "eagle-import") (part "TPSB2.0"))
    )
    (comp (ref "TP30")
      (value "TPSB2.0")
      (footprint "eagle-import:B2.0")
      (libsource (lib "eagle-import") (part "TPSB2.0"))
    )
    (comp (ref "TP31")
      (value "TPSB2.0")
      (footprint "eagle-import:B2.0")
      (libsource (lib "eagle-import") (part "TPSB2.0"))
    )
    (comp (ref "TP32")
      (value "TPSB2.0")
      (footprint "eagle-import:B2.0")
      (libsource (lib "eagle-import") (part "TPSB2.0"))
    )
    (comp (ref "TP33")
      (value "TPSB2.0")
      (footprint "eagle-import:B2.0")
      (libsource (lib "eagle-import") (part "TPSB2.0"))
    )
    (comp (ref "TP34")
      (value "TPSB2.0")
      (footprint "eagle-import:B2.0")
      (libsource (lib "eagle-import") (part "TPSB2.0"))
    )
    (comp (ref "TP35")
      (value "TPSB2.0")
      (footprint "eagle-import:B2.0")
      (libsource (lib "eagle-import") (part "TPSB2.0"))
    )
    (comp (ref "TP36")
      (value "TPSB2.0")
      (footprint "eagle-import:B2.0")
      (libsource (lib "eagle-import") (part "TPSB2.0"))
    )
    (comp (ref "TP37")
      (value "TPSB2.0")
      (footprint "eagle-import:B2.0")
      (libsource (lib "eagle-import") (part "TPSB2.0"))
    )
    (comp (ref "TP38")
      (value "TPSB2.0")
      (footprint "eagle-import:B2.0")
      (libsource (lib "eagle-import") (part "TPSB2.0"))
    )
    (comp (ref "TP39")
      (value "TPSB2.0")
      (footprint "eagle-import:B2.0")
      (libsource (lib "eagle-import") (part "TPSB2.0"))
    )
    (comp (ref "TP40")
      (value "TPSB2.0")
      (footprint "eagle-import:B2.0")
      (libsource (lib "eagle-import") (part "TPSB2.0"))
    )
    (comp (ref "TP41")
      (value "TPSB2.0")
      (footprint "eagle-import:B2.0")
      (libsource (lib "eagle-import") (part "TPSB2.0"))
    )
    (comp (ref "TP42")
      (value "TPSB1,27")
      (footprint "eagle-import:B1,27")
      (libsource (lib "eagle-import") (part "TPSB1,27"))
    )
    (comp (ref "TP43")
      (value "TPSB2.0")
      (footprint "eagle-import:B2.0")
      (libsource (lib "eagle-import") (part "TPSB2.0"))
    )
    (comp (ref "TP44")
      (value "TPSB2.0")
      (footprint "eagle-import:B2.0")
      (libsource (lib "eagle-import") (part "TPSB2.0"))
    )
    (comp (ref "TP45")
      (value "TPSB2.0")
      (footprint "eagle-import:B2.0")
      (libsource (lib "eagle-import") (part "TPSB2.0"))
    )
    (comp (ref "TP46")
      (value "TPSB2.0")
      (footprint "eagle-import:B2.0")
      (libsource (lib "eagle-import") (part "TPSB2.0"))
    )
    (comp (ref "X1")
      (value "CON_BMWV2")
      (footprint "eagle-import:24-PIN_V2")
      (libsource (lib "eagle-import") (part "CON_BMWV2"))
    )
    (comp (ref "X2")
      (value "22-23-2051")
      (footprint "eagle-import:22-23-2051")
      (fields (field (name "MF") "MOLEX"))
      (libsource (lib "eagle-import") (part "22-23-2051"))
    )
    (comp (ref "X3")
      (value "22-23-2021")
      (footprint "eagle-import:22-23-2021")
      (fields (field (name "MF") "MOLEX"))
      (libsource (lib "eagle-import") (part "22-23-2021"))
    )
    (comp (ref "5")
      (value "2081-1132")
      (footprint "eagle-import:12-PIN")
      (libsource (lib "eagle-import") (part "2081-1132"))
    )
    (comp (ref "6")
      (value "2081-1132")
      (footprint "eagle-import:12-PIN")
      (libsource (lib "eagle-import") (part "2081-1132"))
    )
    (comp (ref "6V2")
      (value "TPSB2.0")
      (footprint "eagle-import:B2.0")
      (libsource (lib "eagle-import") (part "TPSB2.0"))
    )
    (comp (ref "10V2")
      (value "TPSB2.0")
      (footprint "eagle-import:B2.0")
      (libsource (lib "eagle-import") (part "TPSB2.0"))
    )
    (comp (ref "C14")
      (value "100u")
      (footprint "eagle-import:C1206")
      (fields (field (name "MPN") "GRM31CR60J107ME39L"))
      (libsource (lib "eagle-import") (part "CERAMIC-100UF-6.3V-20%-X5R(1206)"))
    )
    (comp (ref "C16")
      (value "100u")
      (footprint "eagle-import:C1206")
      (fields (field (name "MPN") "GRM31CR60J107ME39L"))
      (libsource (lib "eagle-import") (part "CERAMIC-100UF-6.3V-20%-X5R(1206)"))
    )
    (comp (ref "C17")
      (value "100nF,")
      (footprint "eagle-import:C0805")
      (fields (field (name "MPN") "CC0805KRX7R9BB104"))
      (libsource (lib "eagle-import") (part "CERAMIC-100NF-50V-10%-X7R(0805)"))
    )
    (comp (ref "C18")
      (value "4.7u")
      (footprint "eagle-import:C0805")
      (fields (field (name "MPN") "CC0805KKX5R8BB475"))
      (libsource (lib "eagle-import") (part "CERAMIC-4.7UF-25V-10%-X5R(0805)"))
    )
    (comp (ref "C19")
      (value "100nF.")
      (footprint "eagle-import:C0805")
      (fields (field (name "MPN") "CC0805KRX7R9BB104"))
      (libsource (lib "eagle-import") (part "CERAMIC-100NF-50V-10%-X7R(0805)"))
    )
    (comp (ref "C20")
      (value "100nF.")
      (footprint "eagle-import:C0805")
      (fields (field (name "MPN") "CC0805KRX7R9BB104"))
      (libsource (lib "eagle-import") (part "CERAMIC-100NF-50V-10%-X7R(0805)"))
    )
    (comp (ref "C21")
      (value "2.2nF")
      (footprint "eagle-import:C0805")
      (fields (field (name "MPN") "CC0805KRX7R9BB104"))
      (libsource (lib "eagle-import") (part "CERAMIC-100NF-50V-10%-X7R(0805)"))
    )
    (comp (ref "C22")
      (value "100nF")
      (footprint "eagle-import:C0805")
      (fields (field (name "MPN") "CC0805KRX7R9BB104"))
      (libsource (lib "eagle-import") (part "CERAMIC-100NF-50V-10%-X7R(0805)"))
    )
    (comp (ref "C23")
      (value "100nF")
      (footprint "eagle-import:C0805")
      (fields (field (name "MPN") "CC0805KRX7R9BB104"))
      (libsource (lib "eagle-import") (part "CERAMIC-100NF-50V-10%-X7R(0805)"))
    )
    (comp (ref "C24")
      (value "100nF,")
      (footprint "eagle-import:C0805")
      (fields (field (name "MPN") "CC0805KRX7R9BB104"))
      (libsource (lib "eagle-import") (part "CERAMIC-100NF-50V-10%-X7R(0805)"))
    )
    (comp (ref "C25")
      (value "4.7u")
      (footprint "eagle-import:C0805")
      (fields (field (name "MPN") "CC0805KKX5R8BB475"))
      (libsource (lib "eagle-import") (part "CERAMIC-4.7UF-25V-10%-X5R(0805)"))
    )
    (comp (ref "C26")
      (value "10u")
      (footprint "eagle-import:C1206")
      (fields (field (name "MPN") "GRM31CR60J107ME39L"))
      (libsource (lib "eagle-import") (part "CERAMIC-100UF-6.3V-20%-X5R(1206)"))
    )
    (comp (ref "D18")
      (value "1N4007,")
      (footprint "eagle-import:DO-214AC")
      (fields (field (name "MPN") "1N4007"))
      (libsource (lib "eagle-import") (part "DIODE-GEN-PURPOSE-1KV-1A(DO-214AC)"))
    )
    (comp (ref "D19")
      (value "1N4007,")
      (footprint "eagle-import:DO-214AC")
      (fields (field (name "MPN") "1N4007"))
      (libsource (lib "eagle-import") (part "DIODE-GEN-PURPOSE-1KV-1A(DO-214AC)"))
    )
    (comp (ref "D20")
      (value "1N4007.")
      (footprint "eagle-import:DO-214AC")
      (fields (field (name "MPN") "1N4007"))
      (libsource (lib "eagle-import") (part "DIODE-GEN-PURPOSE-1KV-1A(DO-214AC)"))
    )
    (comp (ref "D21")
      (value "1N5817")
      (footprint "eagle-import:DO-214AC_SLIM")
      (libsource (lib "eagle-import") (part "DIODE-GEN-PURPOSE-1KV-1A(DO-214AC)DO-214AC/1206"))
    )
    (comp (ref "D22")
      (value "1N5817.")
      (footprint "eagle-import:DO-214AC_SLIM")
      (libsource (lib "eagle-import") (part "DIODE-GEN-PURPOSE-1KV-1A(DO-214AC)DO-214AC/1206"))
    )
    (comp (ref "D23")
      (value "1N5817.")
      (footprint "eagle-import:DO-214AC_SLIM")
      (libsource (lib "eagle-import") (part "DIODE-GEN-PURPOSE-1KV-1A(DO-214AC)DO-214AC/1206"))
    )
    (comp (ref "D24")
      (value "1N5817")
      (footprint "eagle-import:DO-214AC_SLIM")
      (libsource (lib "eagle-import") (part "DIODE-GEN-PURPOSE-1KV-1A(DO-214AC)DO-214AC/1206"))
    )
    (comp (ref "D25")
      (value "1N4007.")
      (footprint "eagle-import:DO-214AC")
      (fields (field (name "MPN") "1N4007"))
      (libsource (lib "eagle-import") (part "DIODE-GEN-PURPOSE-1KV-1A(DO-214AC)"))
    )
    (comp (ref "D26")
      (value "1N4007")
      (footprint "eagle-import:DO-214AC")
      (libsource (lib "eagle-import") (part "DIODE-GEN-PURPOSE-1KV-1A(DO-214AC)"))
    )
    (comp (ref "D27")
      (value "Zen15")
      (footprint "eagle-import:DO214AA")
      (libsource (lib "eagle-import") (part "SM6T"))
    )
    (comp (ref "D28")
      (value "SM6TDO214AA_BI")
      (footprint "eagle-import:DO214AA_BI")
      (libsource (lib "eagle-import") (part "SM6TDO214AA_BI"))
    )
    (comp (ref "D29")
      (value "SS12")
      (footprint "eagle-import:DO-214AC_SLIM")
      (libsource (lib "eagle-import") (part "DIODE-GEN-PURPOSE-1KV-1A(DO-214AC)DO-214AC/1206"))
    )
    (comp (ref "D30")
      (value "SS12")
      (footprint "eagle-import:DO-214AC_SLIM")
      (libsource (lib "eagle-import") (part "DIODE-GEN-PURPOSE-1KV-1A(DO-214AC)DO-214AC/1206"))
    )
    (comp (ref "D31")
      (value "Zen11")
      (footprint "eagle-import:SOD-123_MINI-SMA")
      (libsource (lib "eagle-import") (part "CGRM400-G1"))
    )
    (comp (ref "FID7")
      (value "FIDUCIAL")
      (footprint "eagle-import:FIDUCIAL_1MM")
      (libsource (lib "eagle-import") (part "FIDUCIAL"))
    )
    (comp (ref "FID8")
      (value "FIDUCIAL")
      (footprint "eagle-import:FIDUCIAL_1MM")
      (libsource (lib "eagle-import") (part "FIDUCIAL"))
    )
    (comp (ref "FID9")
      (value "FIDUCIAL")
      (footprint "eagle-import:FIDUCIAL_1MM")
      (libsource (lib "eagle-import") (part "FIDUCIAL"))
    )
    (comp (ref "FID10")
      (value "FIDUCIAL")
      (footprint "eagle-import:FIDUCIAL_1MM")
      (libsource (lib "eagle-import") (part "FIDUCIAL"))
    )
    (comp (ref "IC10")
      (value "4028")
      (footprint "eagle-import:SO16")
      (libsource (lib "eagle-import") (part "4028D"))
    )
    (comp (ref "IC11")
      (value "317TO202H_NOHOLE")
      (footprint "eagle-import:TO220H_NOHOLE")
      (libsource (lib "eagle-import") (part "317TO202H_NOHOLE"))
    )
    (comp (ref "IC12")
      (value "ULN2004")
      (footprint "eagle-import:SO16")
      (libsource (lib "eagle-import") (part "ULN2004AD"))
    )
    (comp (ref "IC13")
      (value "LM339")
      (footprint "eagle-import:SO14")
      (libsource (lib "eagle-import") (part "LM339D"))
    )
    (comp (ref "IC14")
      (value "78L06")
      (footprint "eagle-import:SOT89_ROUND")
      (libsource (lib "eagle-import") (part "78LXXSOT89_ROUND"))
    )
    (comp (ref "IC15")
      (value "555")
      (footprint "eagle-import:SO08")
      (libsource (lib "eagle-import") (part "555DNE"))
    )
    (comp (ref "IC16")
      (value "4538")
      (footprint "eagle-import:SO16")
      (libsource (lib "eagle-import") (part "4538D"))
    )
    (comp (ref "IC17")
      (value "78L10")
      (footprint "eagle-import:SOT89_ROUND")
      (libsource (lib "eagle-import") (part "78LXXSOT89_ROUND"))
    )
    (comp (ref "IC18")
      (value "LM2904")
      (footprint "eagle-import:SO08")
      (libsource (lib "eagle-import") (part "LM358D"))
    )
    (comp (ref "JP6")
      (value "JP2EJP2_SMALLPADS")
      (footprint "eagle-import:JP2_SMALLPADS")
      (libsource (lib "eagle-import") (part "JP2EJP2_SMALLPADS"))
    )
    (comp (ref "JP7")
      (value "JP2E_ORIG")
      (footprint "eagle-import:JP2_ORIG_SMALLPADS")
      (libsource (lib "eagle-import") (part "JP2E_ORIG"))
    )
    (comp (ref "JP8")
      (value "JP2EJP2_SMALLPADS")
      (footprint "eagle-import:JP2_SMALLPADS")
      (libsource (lib "eagle-import") (part "JP2EJP2_SMALLPADS"))
    )
    (comp (ref "JP9")
      (value "JP2EJP2_SMALLPADS")
      (footprint "eagle-import:JP2_SMALLPADS")
      (libsource (lib "eagle-import") (part "JP2EJP2_SMALLPADS"))
    )
    (comp (ref "JP10")
      (value "JP2EJP2_SMALLPADS")
      (footprint "eagle-import:JP2_SMALLPADS")
      (libsource (lib "eagle-import") (part "JP2EJP2_SMALLPADS"))
    )
    (comp (ref "LED7")
      (value "LEDLD260")
      (footprint "eagle-import:LD260")
      (libsource (lib "eagle-import") (part "LEDLD260"))
    )
    (comp (ref "LED8")
      (value "LEDLD260")
      (footprint "eagle-import:LD260")
      (libsource (lib "eagle-import") (part "LEDLD260"))
    )
    (comp (ref "LED9")
      (value "LEDLD260")
      (footprint "eagle-import:LD260")
      (libsource (lib "eagle-import") (part "LEDLD260"))
    )
    (comp (ref "LED10")
      (value "LEDLD260")
      (footprint "eagle-import:LD260")
      (libsource (lib "eagle-import") (part "LEDLD260"))
    )
    (comp (ref "LED11")
      (value "LEDLD260")
      (footprint "eagle-import:LD260")
      (libsource (lib "eagle-import") (part "LEDLD260"))
    )
    (comp (ref "LED12")
      (value "LEDLD260")
      (footprint "eagle-import:LD260")
      (libsource (lib "eagle-import") (part "LEDLD260"))
    )
    (comp (ref "Q14")
      (value "BA")
      (footprint "eagle-import:SOT89")
      (libsource (lib "eagle-import") (part "PNP-TRANSISTOR_SOT89"))
    )
    (comp (ref "Q15")
      (value "BA.")
      (footprint "eagle-import:SOT89")
      (libsource (lib "eagle-import") (part "PNP-TRANSISTOR_SOT89"))
    )
    (comp (ref "Q16")
      (value "BA.")
      (footprint "eagle-import:SOT89")
      (libsource (lib "eagle-import") (part "PNP-TRANSISTOR_SOT89"))
    )
    (comp (ref "Q17")
      (value "BA")
      (footprint "eagle-import:SOT89")
      (libsource (lib "eagle-import") (part "PNP-TRANSISTOR_SOT89"))
    )
    (comp (ref "Q18")
      (value "MY")
      (footprint "eagle-import:SOT89")
      (libsource (lib "eagle-import") (part "NPN-TRANSISTOR_SOT89"))
    )
    (comp (ref "Q19")
      (value "J1")
      (footprint "eagle-import:SOT-23")
      (fields (field (name "MPN") "BSS138W-7-F"))
      (libsource (lib "eagle-import") (part "SMD-MOSFET-N-CH-50V-200MA-BSS138W-7-F(SOT-23)"))
    )
    (comp (ref "Q20")
      (value "J1")
      (footprint "eagle-import:SOT-23")
      (fields (field (name "MPN") "BSS138W-7-F"))
      (libsource (lib "eagle-import") (part "SMD-MOSFET-N-CH-50V-200MA-BSS138W-7-F(SOT-23)"))
    )
    (comp (ref "Q21")
      (value "J1")
      (footprint "eagle-import:SOT-23")
      (fields (field (name "MPN") "BSS138W-7-F"))
      (libsource (lib "eagle-import") (part "SMD-MOSFET-N-CH-50V-200MA-BSS138W-7-F(SOT-23)"))
    )
    (comp (ref "Q22")
      (value "BA")
      (footprint "eagle-import:SOT89")
      (libsource (lib "eagle-import") (part "PNP-TRANSISTOR_SOT89"))
    )
    (comp (ref "Q23")
      (value "J1")
      (footprint "eagle-import:SOT-23")
      (fields (field (name "MPN") "BSS138W-7-F"))
      (libsource (lib "eagle-import") (part "SMD-MOSFET-N-CH-50V-200MA-BSS138W-7-F(SOT-23)"))
    )
    (comp (ref "R67")
      (value "47")
      (footprint "eagle-import:V235_17_1MM")
      (libsource (lib "eagle-import") (part "R-EU_V235/17_1MM"))
    )
    (comp (ref "R68")
      (value "13")
      (footprint "eagle-import:R1206")
      (fields (field (name "MPN") "RC1206JR-0713RL"))
      (libsource (lib "eagle-import") (part "SMD-RES-13R-5%-1/4W(1206)"))
    )
    (comp (ref "R69")
      (value "47")
      (footprint "eagle-import:V235_17_1MM")
      (libsource (lib "eagle-import") (part "R-EU_V235/17_1MM"))
    )
    (comp (ref "R70")
      (value "104")
      (footprint "eagle-import:R0805")
      (fields (field (name "MPN") "RC0805FR-0710KL"))
      (libsource (lib "eagle-import") (part "SMD-RES-10K-1%-1/8W(0805)"))
    )
    (comp (ref "R71")
      (value "104")
      (footprint "eagle-import:R0805")
      (fields (field (name "MPN") "RC0805FR-0710KL"))
      (libsource (lib "eagle-import") (part "SMD-RES-10K-1%-1/8W(0805)"))
    )
    (comp (ref "R72")
      (value "104")
      (footprint "eagle-import:R0805")
      (fields (field (name "MPN") "RC0805FR-0710KL"))
      (libsource (lib "eagle-import") (part "SMD-RES-10K-1%-1/8W(0805)"))
    )
    (comp (ref "R73")
      (value "4701")
      (footprint "eagle-import:R0805")
      (fields (field (name "MPN") "RC0805JR-074K7L"))
      (libsource (lib "eagle-import") (part "SMD-RES-4.7K-5%-1/8W(0805)"))
    )
    (comp (ref "R74")
      (value "1002")
      (footprint "eagle-import:R0805")
      (fields (field (name "MPN") "RC0805FR-0710KL"))
      (libsource (lib "eagle-import") (part "SMD-RES-10K-1%-1/8W(0805)"))
    )
    (comp (ref "R75")
      (value "1002")
      (footprint "eagle-import:R0805")
      (fields (field (name "MPN") "RC0805FR-0710KL"))
      (libsource (lib "eagle-import") (part "SMD-RES-10K-1%-1/8W(0805)"))
    )
    (comp (ref "R76")
      (value "1502")
      (footprint "eagle-import:R0805")
      (fields (field (name "MPN") "RC0805FR-0710KL"))
      (libsource (lib "eagle-import") (part "SMD-RES-10K-1%-1/8W(0805)"))
    )
    (comp (ref "R77")
      (value "104")
      (footprint "eagle-import:R0805")
      (fields (field (name "MPN") "RC0805FR-0710KL"))
      (libsource (lib "eagle-import") (part "SMD-RES-10K-1%-1/8W(0805)"))
    )
    (comp (ref "R78")
      (value "104")
      (footprint "eagle-import:R0805")
      (fields (field (name "MPN") "RC0805FR-0710KL"))
      (libsource (lib "eagle-import") (part "SMD-RES-10K-1%-1/8W(0805)"))
    )
    (comp (ref "R79")
      (value "1502")
      (footprint "eagle-import:R0805")
      (fields (field (name "MPN") "RC0805FR-0710KL"))
      (libsource (lib "eagle-import") (part "SMD-RES-10K-1%-1/8W(0805)"))
    )
    (comp (ref "R80")
      (value "1002")
      (footprint "eagle-import:R0805")
      (fields (field (name "MPN") "RC0805FR-0710KL"))
      (libsource (lib "eagle-import") (part "SMD-RES-10K-1%-1/8W(0805)"))
    )
    (comp (ref "R81")
      (value "2201")
      (footprint "eagle-import:R0805")
      (fields (field (name "MPN") "RC0805JR-072K2L"))
      (libsource (lib "eagle-import") (part "SMD-RES-2.2K-5%-1/8W(0805)"))
    )
    (comp (ref "R82")
      (value "1002")
      (footprint "eagle-import:R0805")
      (fields (field (name "MPN") "RC0805FR-0710KL"))
      (libsource (lib "eagle-import") (part "SMD-RES-10K-1%-1/8W(0805)"))
    )
    (comp (ref "R83")
      (value "4701")
      (footprint "eagle-import:R0805")
      (fields (field (name "MPN") "RC0805JR-074K7L"))
      (libsource (lib "eagle-import") (part "SMD-RES-4.7K-5%-1/8W(0805)"))
    )
    (comp (ref "R84")
      (value "2702")
      (footprint "eagle-import:R0805")
      (fields (field (name "MPN") "RC0805JR-074K7L"))
      (libsource (lib "eagle-import") (part "SMD-RES-4.7K-5%-1/8W(0805)"))
    )
    (comp (ref "R85")
      (value "102")
      (footprint "eagle-import:R0805")
      (fields (field (name "MPN") "RC0805JR-071KL"))
      (libsource (lib "eagle-import") (part "SMD-RES-1K-5%-1/8W(0805)"))
    )
    (comp (ref "R86")
      (value "R_user")
      (footprint "eagle-import:R0805")
      (libsource (lib "eagle-import") (part "R-EU_R0805"))
    )
    (comp (ref "R87")
      (value "102")
      (footprint "eagle-import:R0805")
      (fields (field (name "MPN") "RC0805JR-07220RL"))
      (libsource (lib "eagle-import") (part "SMD-RES-220R-5%-1/8W(0805)"))
    )
    (comp (ref "R88")
      (value "(101)")
      (footprint "eagle-import:R0805")
      (fields (field (name "MPN") "RC0805JR-07100RL"))
      (libsource (lib "eagle-import") (part "SMD-RES-100R-5%-1/8W(0805)"))
    )
    (comp (ref "R89")
      (value "(1000)")
      (footprint "eagle-import:R0805")
      (fields (field (name "MPN") "RC0805JR-07100RL"))
      (libsource (lib "eagle-import") (part "SMD-RES-100R-5%-1/8W(0805)"))
    )
    (comp (ref "R90")
      (value "102")
      (footprint "eagle-import:R0805")
      (fields (field (name "MPN") "RC0805JR-071KL"))
      (libsource (lib "eagle-import") (part "SMD-RES-1K-5%-1/8W(0805)"))
    )
    (comp (ref "R91")
      (value "13")
      (footprint "eagle-import:R1206")
      (fields (field (name "MPN") "RC1206JR-0713RL"))
      (libsource (lib "eagle-import") (part "SMD-RES-13R-5%-1/4W(1206)"))
    )
    (comp (ref "R92")
      (value "13")
      (footprint "eagle-import:R1206")
      (fields (field (name "MPN") "RC1206JR-0713RL"))
      (libsource (lib "eagle-import") (part "SMD-RES-13R-5%-1/4W(1206)"))
    )
    (comp (ref "R93")
      (value "2702")
      (footprint "eagle-import:R0805")
      (fields (field (name "MPN") "RC0805JR-074K7L"))
      (libsource (lib "eagle-import") (part "SMD-RES-4.7K-5%-1/8W(0805)"))
    )
    (comp (ref "R94")
      (value "4701")
      (footprint "eagle-import:R0805")
      (fields (field (name "MPN") "RC0805JR-074K7L"))
      (libsource (lib "eagle-import") (part "SMD-RES-4.7K-5%-1/8W(0805)"))
    )
    (comp (ref "R95")
      (value "100")
      (footprint "eagle-import:R0805")
      (fields (field (name "MPN") "RC0805JR-072K2L"))
      (libsource (lib "eagle-import") (part "SMD-RES-2.2K-5%-1/8W(0805)"))
    )
    (comp (ref "R96")
      (value "104")
      (footprint "eagle-import:R0805")
      (fields (field (name "MPN") "RC0805FR-0710KL"))
      (libsource (lib "eagle-import") (part "SMD-RES-10K-1%-1/8W(0805)"))
    )
    (comp (ref "R97")
      (value "104")
      (footprint "eagle-import:R0805")
      (fields (field (name "MPN") "RC0805FR-0710KL"))
      (libsource (lib "eagle-import") (part "SMD-RES-10K-1%-1/8W(0805)"))
    )
    (comp (ref "R98")
      (value "(1002)")
      (footprint "eagle-import:R0805")
      (fields (field (name "MPN") "RC0805FR-0710KL"))
      (libsource (lib "eagle-import") (part "SMD-RES-10K-1%-1/8W(0805)"))
    )
    (comp (ref "R99")
      (value "2702")
      (footprint "eagle-import:R0805")
      (fields (field (name "MPN") "RC0805FR-0710KL"))
      (libsource (lib "eagle-import") (part "SMD-RES-10K-1%-1/8W(0805)"))
    )
    (comp (ref "R100")
      (value "47")
      (footprint "eagle-import:V235_17_1MM")
      (libsource (lib "eagle-import") (part "R-EU_V235/17_1MM"))
    )
    (comp (ref "R118")
      (value "47")
      (footprint "eagle-import:V235_17_1MM")
      (libsource (lib "eagle-import") (part "R-EU_V235/17_1MM"))
    )
    (comp (ref "R139")
      (value "2702")
      (footprint "eagle-import:R0805")
      (fields (field (name "MPN") "RC0805JR-074K7L"))
      (libsource (lib "eagle-import") (part "SMD-RES-4.7K-5%-1/8W(0805)"))
    )
    (comp (ref "R147")
      (value "2201")
      (footprint "eagle-import:R0805")
      (fields (field (name "MPN") "RC0805JR-072K2L"))
      (libsource (lib "eagle-import") (part "SMD-RES-2.2K-5%-1/8W(0805)"))
    )
    (comp (ref "R148")
      (value "1002")
      (footprint "eagle-import:R0805")
      (fields (field (name "MPN") "RC0805JR-074K7L"))
      (libsource (lib "eagle-import") (part "SMD-RES-4.7K-5%-1/8W(0805)"))
    )
    (comp (ref "R149")
      (value "1002")
      (footprint "eagle-import:R0805")
      (fields (field (name "MPN") "RC0805FR-0710KL"))
      (libsource (lib "eagle-import") (part "SMD-RES-10K-1%-1/8W(0805)"))
    )
    (comp (ref "R150")
      (value "102")
      (footprint "eagle-import:R0805")
      (fields (field (name "MPN") "RC0805JR-071KL"))
      (libsource (lib "eagle-import") (part "SMD-RES-1K-5%-1/8W(0805)"))
    )
    (comp (ref "R151")
      (value "2702")
      (footprint "eagle-import:R0805")
      (fields (field (name "MPN") "RC0805JR-074K7L"))
      (libsource (lib "eagle-import") (part "SMD-RES-4.7K-5%-1/8W(0805)"))
    )
    (comp (ref "R152")
      (value "1002")
      (footprint "eagle-import:R0805")
      (fields (field (name "MPN") "RC0805JR-071KL"))
      (libsource (lib "eagle-import") (part "SMD-RES-1K-5%-1/8W(0805)"))
    )
    (comp (ref "R153")
      (value "1002")
      (footprint "eagle-import:R0805")
      (fields (field (name "MPN") "RC0805JR-071KL"))
      (libsource (lib "eagle-import") (part "SMD-RES-1K-5%-1/8W(0805)"))
    )
    (comp (ref "R154")
      (value "R_user")
      (footprint "eagle-import:R0805")
      (libsource (lib "eagle-import") (part "R-EU_R0805"))
    )
    (comp (ref "R155")
      (value "104")
      (footprint "eagle-import:R0805")
      (fields (field (name "MPN") "RC0805FR-0710KL"))
      (libsource (lib "eagle-import") (part "SMD-RES-10K-1%-1/8W(0805)"))
    )
    (comp (ref "R156")
      (value "104")
      (footprint "eagle-import:R0805")
      (fields (field (name "MPN") "RC0805FR-0710KL"))
      (libsource (lib "eagle-import") (part "SMD-RES-10K-1%-1/8W(0805)"))
    )
    (comp (ref "R157")
      (value "104")
      (footprint "eagle-import:R0805")
      (fields (field (name "MPN") "RC0805FR-0710KL"))
      (libsource (lib "eagle-import") (part "SMD-RES-10K-1%-1/8W(0805)"))
    )
    (comp (ref "R158")
      (value "13")
      (footprint "eagle-import:R1206")
      (fields (field (name "MPN") "RC1206JR-0713RL"))
      (libsource (lib "eagle-import") (part "SMD-RES-13R-5%-1/4W(1206)"))
    )
    (comp (ref "R159")
      (value "2201")
      (footprint "eagle-import:R0805")
      (fields (field (name "MPN") "RC0805JR-071KL"))
      (libsource (lib "eagle-import") (part "SMD-RES-1K-5%-1/8W(0805)"))
    )
    (comp (ref "R160")
      (value "100")
      (footprint "eagle-import:R0805")
      (fields (field (name "MPN") "RC0805JR-07220RL"))
      (libsource (lib "eagle-import") (part "SMD-RES-220R-5%-1/8W(0805)"))
    )
    (comp (ref "R161")
      (value "13")
      (footprint "eagle-import:R1206")
      (fields (field (name "MPN") "RC1206JR-0713RL"))
      (libsource (lib "eagle-import") (part "SMD-RES-13R-5%-1/4W(1206)"))
    )
    (comp (ref "R162")
      (value "4701")
      (footprint "eagle-import:R0805")
      (fields (field (name "MPN") "RC0805JR-074K7L"))
      (libsource (lib "eagle-import") (part "SMD-RES-4.7K-5%-1/8W(0805)"))
    )
    (comp (ref "R163")
      (value "104")
      (footprint "eagle-import:R0805")
      (fields (field (name "MPN") "RC0805JR-074K7L"))
      (libsource (lib "eagle-import") (part "SMD-RES-4.7K-5%-1/8W(0805)"))
    )
    (comp (ref "R164")
      (value "100")
      (footprint "eagle-import:R0805")
      (fields (field (name "MPN") "RC0805JR-072K2L"))
      (libsource (lib "eagle-import") (part "SMD-RES-2.2K-5%-1/8W(0805)"))
    )
    (comp (ref "R165")
      (value "100")
      (footprint "eagle-import:R0805")
      (fields (field (name "MPN") "RC0805JR-072K2L"))
      (libsource (lib "eagle-import") (part "SMD-RES-2.2K-5%-1/8W(0805)"))
    )
    (comp (ref "SJ2")
      (value "SJ")
      (footprint "eagle-import:SJ")
      (libsource (lib "eagle-import") (part "solder-jumper_SJ"))
    )
    (comp (ref "SJMP2")
      (value "SJ")
      (footprint "eagle-import:SJ")
      (libsource (lib "eagle-import") (part "SJ"))
    )
    (comp (ref "START2")
      (value "TPSB2.0")
      (footprint "eagle-import:B2.0")
      (libsource (lib "eagle-import") (part "TPSB2.0"))
    )
    (comp (ref "TP47")
      (value "TPSB2.0")
      (footprint "eagle-import:B2.0")
      (libsource (lib "eagle-import") (part "TPSB2.0"))
    )
    (comp (ref "TP48")
      (value "TPSB2.0")
      (footprint "eagle-import:B2.0")
      (libsource (lib "eagle-import") (part "TPSB2.0"))
    )
    (comp (ref "TP49")
      (value "TPSB2.0")
      (footprint "eagle-import:B2.0")
      (libsource (lib "eagle-import") (part "TPSB2.0"))
    )
    (comp (ref "TP50")
      (value "TPSB2.0")
      (footprint "eagle-import:B2.0")
      (libsource (lib "eagle-import") (part "TPSB2.0"))
    )
    (comp (ref "TP51")
      (value "TPSB2.0")
      (footprint "eagle-import:B2.0")
      (libsource (lib "eagle-import") (part "TPSB2.0"))
    )
    (comp (ref "TP52")
      (value "TPSB2.0")
      (footprint "eagle-import:B2.0")
      (libsource (lib "eagle-import") (part "TPSB2.0"))
    )
    (comp (ref "TP53")
      (value "TPSB2.0")
      (footprint "eagle-import:B2.0")
      (libsource (lib "eagle-import") (part "TPSB2.0"))
    )
    (comp (ref "TP54")
      (value "TPSB2.0")
      (footprint "eagle-import:B2.0")
      (libsource (lib "eagle-import") (part "TPSB2.0"))
    )
    (comp (ref "TP55")
      (value "TPSB2.0")
      (footprint "eagle-import:B2.0")
      (libsource (lib "eagle-import") (part "TPSB2.0"))
    )
    (comp (ref "TP56")
      (value "TPSB2.0")
      (footprint "eagle-import:B2.0")
      (libsource (lib "eagle-import") (part "TPSB2.0"))
    )
    (comp (ref "TP57")
      (value "TPSB2.0")
      (footprint "eagle-import:B2.0")
      (libsource (lib "eagle-import") (part "TPSB2.0"))
    )
    (comp (ref "TP58")
      (value "TPSB2.0")
      (footprint "eagle-import:B2.0")
      (libsource (lib "eagle-import") (part "TPSB2.0"))
    )
    (comp (ref "TP59")
      (value "TPSB2.0")
      (footprint "eagle-import:B2.0")
      (libsource (lib "eagle-import") (part "TPSB2.0"))
    )
    (comp (ref "TP60")
      (value "TPSB2.0")
      (footprint "eagle-import:B2.0")
      (libsource (lib "eagle-import") (part "TPSB2.0"))
    )
    (comp (ref "TP61")
      (value "TPSB2.0")
      (footprint "eagle-import:B2.0")
      (libsource (lib "eagle-import") (part "TPSB2.0"))
    )
    (comp (ref "TP62")
      (value "TPSB2.0")
      (footprint "eagle-import:B2.0")
      (libsource (lib "eagle-import") (part "TPSB2.0"))
    )
    (comp (ref "TP63")
      (value "TPSB2.0")
      (footprint "eagle-import:B2.0")
      (libsource (lib "eagle-import") (part "TPSB2.0"))
    )
    (comp (ref "TP64")
      (value "TPSB2.0")
      (footprint "eagle-import:B2.0")
      (libsource (lib "eagle-import") (part "TPSB2.0"))
    )
    (comp (ref "TP65")
      (value "TPSB1,27")
      (footprint "eagle-import:B1,27")
      (libsource (lib "eagle-import") (part "TPSB1,27"))
    )
    (comp (ref "TP66")
      (value "TPSB2.0")
      (footprint "eagle-import:B2.0")
      (libsource (lib "eagle-import") (part "TPSB2.0"))
    )
    (comp (ref "TP67")
      (value "TPSB2.0")
      (footprint "eagle-import:B2.0")
      (libsource (lib "eagle-import") (part "TPSB2.0"))
    )
    (comp (ref "TP68")
      (value "TPSB2.0")
      (footprint "eagle-import:B2.0")
      (libsource (lib "eagle-import") (part "TPSB2.0"))
    )
    (comp (ref "TP69")
      (value "TPSB2.0")
      (footprint "eagle-import:B2.0")
      (libsource (lib "eagle-import") (part "TPSB2.0"))
    )
    (comp (ref "X4")
      (value "CON_BMWV2")
      (footprint "eagle-import:24-PIN_V2")
      (libsource (lib "eagle-import") (part "CON_BMWV2"))
    )
    (comp (ref "X5")
      (value "22-23-2051")
      (footprint "eagle-import:22-23-2051")
      (fields (field (name "MF") "MOLEX"))
      (libsource (lib "eagle-import") (part "22-23-2051"))
    )
    (comp (ref "X6")
      (value "22-23-2021")
      (footprint "eagle-import:22-23-2021")
      (fields (field (name "MF") "MOLEX"))
      (libsource (lib "eagle-import") (part "22-23-2021"))
    )
    (comp (ref "FID1")
      (value "FIDUCIAL")
      (footprint "eagle-import:FIDUCIAL_1MM")
      (libsource (lib "eagle-import") (part "FIDUCIAL"))
    )
    (comp (ref "FID1B")
      (value "FIDUCIALFIDUCIAL_1MM_WITH_SOLDERMASK")
      (footprint "eagle-import:FIDUCIAL_1MM_WITH_SOLDERMASK")
      (libsource (lib "eagle-import") (part "FIDUCIALFIDUCIAL_1MM_WITH_SOLDERMASK"))
    )
    (comp (ref "FID2")
      (value "FIDUCIAL")
      (footprint "eagle-import:FIDUCIAL_1MM")
      (libsource (lib "eagle-import") (part "FIDUCIAL"))
    )
    (comp (ref "FID2B")
      (value "FIDUCIALFIDUCIAL_1MM_WITH_SOLDERMASK")
      (footprint "eagle-import:FIDUCIAL_1MM_WITH_SOLDERMASK")
      (libsource (lib "eagle-import") (part "FIDUCIALFIDUCIAL_1MM_WITH_SOLDERMASK"))
    )
    (comp (ref "1")
      (value "2081-1132")
      (footprint "eagle-import:12-PIN")
      (libsource (lib "eagle-import") (part "2081-1132"))
    )
    (comp (ref "2")
      (value "2081-1132")
      (footprint "eagle-import:12-PIN")
      (libsource (lib "eagle-import") (part "2081-1132"))
    )
    (comp (ref "6V")
      (value "TPSB2.0")
      (footprint "eagle-import:B2.0")
      (libsource (lib "eagle-import") (part "TPSB2.0"))
    )
    (comp (ref "10V")
      (value "TPSB2.0")
      (footprint "eagle-import:B2.0")
      (libsource (lib "eagle-import") (part "TPSB2.0"))
    )
    (comp (ref "C2")
      (value "10u")
      (footprint "eagle-import:C1206")
      (fields (field (name "MPN") "GRM31CR60J107ME39L"))
      (libsource (lib "eagle-import") (part "CERAMIC-100UF-6.3V-20%-X5R(1206)"))
    )
    (comp (ref "C15")
      (value "4.7u")
      (footprint "eagle-import:C0805")
      (fields (field (name "MPN") "CC0805KKX5R8BB475"))
      (libsource (lib "eagle-import") (part "CERAMIC-4.7UF-25V-10%-X5R(0805)"))
    )
    (comp (ref "C101")
      (value "4.7u")
      (footprint "eagle-import:C0805")
      (fields (field (name "MPN") "CC0805KKX5R8BB475"))
      (libsource (lib "eagle-import") (part "CERAMIC-4.7UF-25V-10%-X5R(0805)"))
    )
    (comp (ref "C102")
      (value "100nF")
      (footprint "eagle-import:C0805")
      (fields (field (name "MPN") "CC0805KRX7R9BB104"))
      (libsource (lib "eagle-import") (part "CERAMIC-100NF-50V-10%-X7R(0805)"))
    )
    (comp (ref "C103")
      (value "100nF,")
      (footprint "eagle-import:C0805")
      (fields (field (name "MPN") "CC0805KRX7R9BB104"))
      (libsource (lib "eagle-import") (part "CERAMIC-100NF-50V-10%-X7R(0805)"))
    )
    (comp (ref "C104")
      (value "100nF,")
      (footprint "eagle-import:C0805")
      (fields (field (name "MPN") "CC0805KRX7R9BB104"))
      (libsource (lib "eagle-import") (part "CERAMIC-100NF-50V-10%-X7R(0805)"))
    )
    (comp (ref "C105")
      (value "100nF.")
      (footprint "eagle-import:C0805")
      (fields (field (name "MPN") "CC0805KRX7R9BB104"))
      (libsource (lib "eagle-import") (part "CERAMIC-100NF-50V-10%-X7R(0805)"))
    )
    (comp (ref "C106")
      (value "100nF.")
      (footprint "eagle-import:C0805")
      (fields (field (name "MPN") "CC0805KRX7R9BB104"))
      (libsource (lib "eagle-import") (part "CERAMIC-100NF-50V-10%-X7R(0805)"))
    )
    (comp (ref "C107")
      (value "100u")
      (footprint "eagle-import:C1206")
      (fields (field (name "MPN") "GRM31CR60J107ME39L"))
      (libsource (lib "eagle-import") (part "CERAMIC-100UF-6.3V-20%-X5R(1206)"))
    )
    (comp (ref "C108")
      (value "100u")
      (footprint "eagle-import:C1206")
      (fields (field (name "MPN") "GRM31CR60J107ME39L"))
      (libsource (lib "eagle-import") (part "CERAMIC-100UF-6.3V-20%-X5R(1206)"))
    )
    (comp (ref "C109")
      (value "2.2nF")
      (footprint "eagle-import:C0805")
      (fields (field (name "MPN") "CC0805KRX7R9BB104"))
      (libsource (lib "eagle-import") (part "CERAMIC-100NF-50V-10%-X7R(0805)"))
    )
    (comp (ref "C110")
      (value "100nF")
      (footprint "eagle-import:C0805")
      (fields (field (name "MPN") "CC0805KRX7R9BB104"))
      (libsource (lib "eagle-import") (part "CERAMIC-100NF-50V-10%-X7R(0805)"))
    )
    (comp (ref "D1")
      (value "SS12")
      (footprint "eagle-import:DO-214AC_SLIM")
      (libsource (lib "eagle-import") (part "DIODE-GEN-PURPOSE-1KV-1A(DO-214AC)DO-214AC/1206"))
    )
    (comp (ref "D2")
      (value "SS12")
      (footprint "eagle-import:DO-214AC_SLIM")
      (libsource (lib "eagle-import") (part "DIODE-GEN-PURPOSE-1KV-1A(DO-214AC)DO-214AC/1206"))
    )
    (comp (ref "D4")
      (value "Zen11")
      (footprint "eagle-import:SOD-123_MINI-SMA")
      (libsource (lib "eagle-import") (part "CGRM400-G1"))
    )
    (comp (ref "D101")
      (value "Zen15")
      (footprint "eagle-import:DO214AA")
      (libsource (lib "eagle-import") (part "SM6T"))
    )
    (comp (ref "D102")
      (value "1N4007,")
      (footprint "eagle-import:DO-214AC")
      (fields (field (name "MPN") "1N4007"))
      (libsource (lib "eagle-import") (part "DIODE-GEN-PURPOSE-1KV-1A(DO-214AC)"))
    )
    (comp (ref "D103")
      (value "1N4007,")
      (footprint "eagle-import:DO-214AC")
      (fields (field (name "MPN") "1N4007"))
      (libsource (lib "eagle-import") (part "DIODE-GEN-PURPOSE-1KV-1A(DO-214AC)"))
    )
    (comp (ref "D104")
      (value "SM6TDO214AA_BI")
      (footprint "eagle-import:DO214AA_BI")
      (libsource (lib "eagle-import") (part "SM6TDO214AA_BI"))
    )
    (comp (ref "D105")
      (value "1N4007.")
      (footprint "eagle-import:DO-214AC")
      (fields (field (name "MPN") "1N4007"))
      (libsource (lib "eagle-import") (part "DIODE-GEN-PURPOSE-1KV-1A(DO-214AC)"))
    )
    (comp (ref "D106")
      (value "1N4007.")
      (footprint "eagle-import:DO-214AC")
      (fields (field (name "MPN") "1N4007"))
      (libsource (lib "eagle-import") (part "DIODE-GEN-PURPOSE-1KV-1A(DO-214AC)"))
    )
    (comp (ref "D107")
      (value "1N5817")
      (footprint "eagle-import:DO-214AC_SLIM")
      (libsource (lib "eagle-import") (part "DIODE-GEN-PURPOSE-1KV-1A(DO-214AC)DO-214AC/1206"))
    )
    (comp (ref "D108")
      (value "1N5817.")
      (footprint "eagle-import:DO-214AC_SLIM")
      (libsource (lib "eagle-import") (part "DIODE-GEN-PURPOSE-1KV-1A(DO-214AC)DO-214AC/1206"))
    )
    (comp (ref "D109")
      (value "1N5817.")
      (footprint "eagle-import:DO-214AC_SLIM")
      (libsource (lib "eagle-import") (part "DIODE-GEN-PURPOSE-1KV-1A(DO-214AC)DO-214AC/1206"))
    )
    (comp (ref "D110")
      (value "1N5817")
      (footprint "eagle-import:DO-214AC_SLIM")
      (libsource (lib "eagle-import") (part "DIODE-GEN-PURPOSE-1KV-1A(DO-214AC)DO-214AC/1206"))
    )
    (comp (ref "D112")
      (value "1N4007")
      (footprint "eagle-import:DO-214AC")
      (libsource (lib "eagle-import") (part "DIODE-GEN-PURPOSE-1KV-1A(DO-214AC)"))
    )
    (comp (ref "FID101")
      (value "FIDUCIAL")
      (footprint "eagle-import:FIDUCIAL_1MM")
      (libsource (lib "eagle-import") (part "FIDUCIAL"))
    )
    (comp (ref "FID102")
      (value "FIDUCIAL")
      (footprint "eagle-import:FIDUCIAL_1MM")
      (libsource (lib "eagle-import") (part "FIDUCIAL"))
    )
    (comp (ref "FID103")
      (value "FIDUCIAL")
      (footprint "eagle-import:FIDUCIAL_1MM")
      (libsource (lib "eagle-import") (part "FIDUCIAL"))
    )
    (comp (ref "FID104")
      (value "FIDUCIAL")
      (footprint "eagle-import:FIDUCIAL_1MM")
      (libsource (lib "eagle-import") (part "FIDUCIAL"))
    )
    (comp (ref "IC101")
      (value "LM2904")
      (footprint "eagle-import:SO08")
      (libsource (lib "eagle-import") (part "LM358D"))
    )
    (comp (ref "IC102")
      (value "78L06")
      (footprint "eagle-import:SOT89_ROUND")
      (libsource (lib "eagle-import") (part "78LXXSOT89_ROUND"))
    )
    (comp (ref "IC104")
      (value "78L10")
      (footprint "eagle-import:SOT89_ROUND")
      (libsource (lib "eagle-import") (part "78LXXSOT89_ROUND"))
    )
    (comp (ref "IC105")
      (value "4028")
      (footprint "eagle-import:SO16")
      (libsource (lib "eagle-import") (part "4028D"))
    )
    (comp (ref "IC107")
      (value "ULN2004")
      (footprint "eagle-import:SO16")
      (libsource (lib "eagle-import") (part "ULN2004AD"))
    )
    (comp (ref "IC108")
      (value "LM339")
      (footprint "eagle-import:SO14")
      (libsource (lib "eagle-import") (part "LM339D"))
    )
    (comp (ref "IC109")
      (value "317TO202H_NOHOLE")
      (footprint "eagle-import:TO220H_NOHOLE")
      (libsource (lib "eagle-import") (part "317TO202H_NOHOLE"))
    )
    (comp (ref "IC110")
      (value "555")
      (footprint "eagle-import:SO08")
      (libsource (lib "eagle-import") (part "555DNE"))
    )
    (comp (ref "IC111")
      (value "4538")
      (footprint "eagle-import:SO16")
      (libsource (lib "eagle-import") (part "4538D"))
    )
    (comp (ref "JP101")
      (value "JP2EJP2_SMALLPADS")
      (footprint "eagle-import:JP2_SMALLPADS")
      (libsource (lib "eagle-import") (part "JP2EJP2_SMALLPADS"))
    )
    (comp (ref "JP102")
      (value "JP2EJP2_SMALLPADS")
      (footprint "eagle-import:JP2_SMALLPADS")
      (libsource (lib "eagle-import") (part "JP2EJP2_SMALLPADS"))
    )
    (comp (ref "JP103")
      (value "JP2EJP2_SMALLPADS")
      (footprint "eagle-import:JP2_SMALLPADS")
      (libsource (lib "eagle-import") (part "JP2EJP2_SMALLPADS"))
    )
    (comp (ref "JP104")
      (value "JP2EJP2_SMALLPADS")
      (footprint "eagle-import:JP2_SMALLPADS")
      (libsource (lib "eagle-import") (part "JP2EJP2_SMALLPADS"))
    )
    (comp (ref "JP105")
      (value "JP2E_ORIG")
      (footprint "eagle-import:JP2_ORIG_SMALLPADS")
      (libsource (lib "eagle-import") (part "JP2E_ORIG"))
    )
    (comp (ref "LED101")
      (value "LEDLD260")
      (footprint "eagle-import:LD260")
      (libsource (lib "eagle-import") (part "LEDLD260"))
    )
    (comp (ref "LED102")
      (value "LEDLD260")
      (footprint "eagle-import:LD260")
      (libsource (lib "eagle-import") (part "LEDLD260"))
    )
    (comp (ref "LED103")
      (value "LEDLD260")
      (footprint "eagle-import:LD260")
      (libsource (lib "eagle-import") (part "LEDLD260"))
    )
    (comp (ref "LED104")
      (value "LEDLD260")
      (footprint "eagle-import:LD260")
      (libsource (lib "eagle-import") (part "LEDLD260"))
    )
    (comp (ref "LED105")
      (value "LEDLD260")
      (footprint "eagle-import:LD260")
      (libsource (lib "eagle-import") (part "LEDLD260"))
    )
    (comp (ref "LED106")
      (value "LEDLD260")
      (footprint "eagle-import:LD260")
      (libsource (lib "eagle-import") (part "LEDLD260"))
    )
    (comp (ref "Q1")
      (value "J1")
      (footprint "eagle-import:SOT-23")
      (fields (field (name "MPN") "BSS138W-7-F"))
      (libsource (lib "eagle-import") (part "SMD-MOSFET-N-CH-50V-200MA-BSS138W-7-F(SOT-23)"))
    )
    (comp (ref "Q2")
      (value "BA")
      (footprint "eagle-import:SOT89")
      (libsource (lib "eagle-import") (part "PNP-TRANSISTOR_SOT89"))
    )
    (comp (ref "Q3")
      (value "J1")
      (footprint "eagle-import:SOT-23")
      (fields (field (name "MPN") "BSS138W-7-F"))
      (libsource (lib "eagle-import") (part "SMD-MOSFET-N-CH-50V-200MA-BSS138W-7-F(SOT-23)"))
    )
    (comp (ref "Q101")
      (value "BA.")
      (footprint "eagle-import:SOT89")
      (libsource (lib "eagle-import") (part "PNP-TRANSISTOR_SOT89"))
    )
    (comp (ref "Q102")
      (value "BA.")
      (footprint "eagle-import:SOT89")
      (libsource (lib "eagle-import") (part "PNP-TRANSISTOR_SOT89"))
    )
    (comp (ref "Q103")
      (value "MY")
      (footprint "eagle-import:SOT89")
      (libsource (lib "eagle-import") (part "NPN-TRANSISTOR_SOT89"))
    )
    (comp (ref "Q104")
      (value "BA")
      (footprint "eagle-import:SOT89")
      (libsource (lib "eagle-import") (part "PNP-TRANSISTOR_SOT89"))
    )
    (comp (ref "Q105")
      (value "BA")
      (footprint "eagle-import:SOT89")
      (libsource (lib "eagle-import") (part "PNP-TRANSISTOR_SOT89"))
    )
    (comp (ref "Q106")
      (value "J1")
      (footprint "eagle-import:SOT-23")
      (fields (field (name "MPN") "BSS138W-7-F"))
      (libsource (lib "eagle-import") (part "SMD-MOSFET-N-CH-50V-200MA-BSS138W-7-F(SOT-23)"))
    )
    (comp (ref "Q107")
      (value "J1")
      (footprint "eagle-import:SOT-23")
      (fields (field (name "MPN") "BSS138W-7-F"))
      (libsource (lib "eagle-import") (part "SMD-MOSFET-N-CH-50V-200MA-BSS138W-7-F(SOT-23)"))
    )
    (comp (ref "R1")
      (value "104")
      (footprint "eagle-import:R0805")
      (fields (field (name "MPN") "RC0805FR-0710KL"))
      (libsource (lib "eagle-import") (part "SMD-RES-10K-1%-1/8W(0805)"))
    )
    (comp (ref "R2")
      (value "104")
      (footprint "eagle-import:R0805")
      (fields (field (name "MPN") "RC0805FR-0710KL"))
      (libsource (lib "eagle-import") (part "SMD-RES-10K-1%-1/8W(0805)"))
    )
    (comp (ref "R3")
      (value "104")
      (footprint "eagle-import:R0805")
      (fields (field (name "MPN") "RC0805FR-0710KL"))
      (libsource (lib "eagle-import") (part "SMD-RES-10K-1%-1/8W(0805)"))
    )
    (comp (ref "R4")
      (value "100")
      (footprint "eagle-import:R0805")
      (fields (field (name "MPN") "RC0805JR-07220RL"))
      (libsource (lib "eagle-import") (part "SMD-RES-220R-5%-1/8W(0805)"))
    )
    (comp (ref "R5")
      (value "13")
      (footprint "eagle-import:R1206")
      (fields (field (name "MPN") "RC1206JR-0713RL"))
      (libsource (lib "eagle-import") (part "SMD-RES-13R-5%-1/4W(1206)"))
    )
    (comp (ref "R6")
      (value "2201")
      (footprint "eagle-import:R0805")
      (fields (field (name "MPN") "RC0805JR-071KL"))
      (libsource (lib "eagle-import") (part "SMD-RES-1K-5%-1/8W(0805)"))
    )
    (comp (ref "R8")
      (value "4701")
      (footprint "eagle-import:R0805")
      (fields (field (name "MPN") "RC0805JR-074K7L"))
      (libsource (lib "eagle-import") (part "SMD-RES-4.7K-5%-1/8W(0805)"))
    )
    (comp (ref "R9")
      (value "13")
      (footprint "eagle-import:R1206")
      (fields (field (name "MPN") "RC1206JR-0713RL"))
      (libsource (lib "eagle-import") (part "SMD-RES-13R-5%-1/4W(1206)"))
    )
    (comp (ref "R10")
      (value "104")
      (footprint "eagle-import:R0805")
      (fields (field (name "MPN") "RC0805JR-074K7L"))
      (libsource (lib "eagle-import") (part "SMD-RES-4.7K-5%-1/8W(0805)"))
    )
    (comp (ref "R12")
      (value "100")
      (footprint "eagle-import:R0805")
      (fields (field (name "MPN") "RC0805JR-072K2L"))
      (libsource (lib "eagle-import") (part "SMD-RES-2.2K-5%-1/8W(0805)"))
    )
    (comp (ref "R13")
      (value "100")
      (footprint "eagle-import:R0805")
      (fields (field (name "MPN") "RC0805JR-072K2L"))
      (libsource (lib "eagle-import") (part "SMD-RES-2.2K-5%-1/8W(0805)"))
    )
    (comp (ref "R101")
      (value "102")
      (footprint "eagle-import:R0805")
      (fields (field (name "MPN") "RC0805JR-071KL"))
      (libsource (lib "eagle-import") (part "SMD-RES-1K-5%-1/8W(0805)"))
    )
    (comp (ref "R102")
      (value "13")
      (footprint "eagle-import:R1206")
      (fields (field (name "MPN") "RC1206JR-0713RL"))
      (libsource (lib "eagle-import") (part "SMD-RES-13R-5%-1/4W(1206)"))
    )
    (comp (ref "R103")
      (value "R_user")
      (footprint "eagle-import:R0805")
      (libsource (lib "eagle-import") (part "R-EU_R0805"))
    )
    (comp (ref "R104")
      (value "R_user")
      (footprint "eagle-import:R0805")
      (libsource (lib "eagle-import") (part "R-EU_R0805"))
    )
    (comp (ref "R105")
      (value "4701")
      (footprint "eagle-import:R0805")
      (fields (field (name "MPN") "RC0805JR-074K7L"))
      (libsource (lib "eagle-import") (part "SMD-RES-4.7K-5%-1/8W(0805)"))
    )
    (comp (ref "R106")
      (value "13")
      (footprint "eagle-import:R1206")
      (fields (field (name "MPN") "RC1206JR-0713RL"))
      (libsource (lib "eagle-import") (part "SMD-RES-13R-5%-1/4W(1206)"))
    )
    (comp (ref "R107")
      (value "1002")
      (footprint "eagle-import:R0805")
      (fields (field (name "MPN") "RC0805FR-0710KL"))
      (libsource (lib "eagle-import") (part "SMD-RES-10K-1%-1/8W(0805)"))
    )
    (comp (ref "R108")
      (value "1002")
      (footprint "eagle-import:R0805")
      (fields (field (name "MPN") "RC0805FR-0710KL"))
      (libsource (lib "eagle-import") (part "SMD-RES-10K-1%-1/8W(0805)"))
    )
    (comp (ref "R109")
      (value "104")
      (footprint "eagle-import:R0805")
      (fields (field (name "MPN") "RC0805FR-0710KL"))
      (libsource (lib "eagle-import") (part "SMD-RES-10K-1%-1/8W(0805)"))
    )
    (comp (ref "R110")
      (value "104")
      (footprint "eagle-import:R0805")
      (fields (field (name "MPN") "RC0805FR-0710KL"))
      (libsource (lib "eagle-import") (part "SMD-RES-10K-1%-1/8W(0805)"))
    )
    (comp (ref "R111")
      (value "104")
      (footprint "eagle-import:R0805")
      (fields (field (name "MPN") "RC0805FR-0710KL"))
      (libsource (lib "eagle-import") (part "SMD-RES-10K-1%-1/8W(0805)"))
    )
    (comp (ref "R112")
      (value "102")
      (footprint "eagle-import:R0805")
      (fields (field (name "MPN") "RC0805JR-071KL"))
      (libsource (lib "eagle-import") (part "SMD-RES-1K-5%-1/8W(0805)"))
    )
    (comp (ref "R113")
      (value "1002")
      (footprint "eagle-import:R0805")
      (fields (field (name "MPN") "RC0805JR-071KL"))
      (libsource (lib "eagle-import") (part "SMD-RES-1K-5%-1/8W(0805)"))
    )
    (comp (ref "R114")
      (value "1002")
      (footprint "eagle-import:R0805")
      (fields (field (name "MPN") "RC0805JR-071KL"))
      (libsource (lib "eagle-import") (part "SMD-RES-1K-5%-1/8W(0805)"))
    )
    (comp (ref "R115")
      (value "102")
      (footprint "eagle-import:R0805")
      (fields (field (name "MPN") "RC0805JR-07220RL"))
      (libsource (lib "eagle-import") (part "SMD-RES-220R-5%-1/8W(0805)"))
    )
    (comp (ref "R116")
      (value "4701")
      (footprint "eagle-import:R0805")
      (fields (field (name "MPN") "RC0805JR-074K7L"))
      (libsource (lib "eagle-import") (part "SMD-RES-4.7K-5%-1/8W(0805)"))
    )
    (comp (ref "R117")
      (value "2702")
      (footprint "eagle-import:R0805")
      (fields (field (name "MPN") "RC0805JR-074K7L"))
      (libsource (lib "eagle-import") (part "SMD-RES-4.7K-5%-1/8W(0805)"))
    )
    (comp (ref "R119")
      (value "2201")
      (footprint "eagle-import:R0805")
      (fields (field (name "MPN") "RC0805JR-072K2L"))
      (libsource (lib "eagle-import") (part "SMD-RES-2.2K-5%-1/8W(0805)"))
    )
    (comp (ref "R120")
      (value "1002")
      (footprint "eagle-import:R0805")
      (fields (field (name "MPN") "RC0805FR-0710KL"))
      (libsource (lib "eagle-import") (part "SMD-RES-10K-1%-1/8W(0805)"))
    )
    (comp (ref "R121")
      (value "1502")
      (footprint "eagle-import:R0805")
      (fields (field (name "MPN") "RC0805FR-0710KL"))
      (libsource (lib "eagle-import") (part "SMD-RES-10K-1%-1/8W(0805)"))
    )
    (comp (ref "R122")
      (value "2702")
      (footprint "eagle-import:R0805")
      (fields (field (name "MPN") "RC0805JR-074K7L"))
      (libsource (lib "eagle-import") (part "SMD-RES-4.7K-5%-1/8W(0805)"))
    )
    (comp (ref "R123")
      (value "2702")
      (footprint "eagle-import:R0805")
      (fields (field (name "MPN") "RC0805JR-074K7L"))
      (libsource (lib "eagle-import") (part "SMD-RES-4.7K-5%-1/8W(0805)"))
    )
    (comp (ref "R124")
      (value "1002")
      (footprint "eagle-import:R0805")
      (fields (field (name "MPN") "RC0805FR-0710KL"))
      (libsource (lib "eagle-import") (part "SMD-RES-10K-1%-1/8W(0805)"))
    )
    (comp (ref "R125")
      (value "104")
      (footprint "eagle-import:R0805")
      (fields (field (name "MPN") "RC0805FR-0710KL"))
      (libsource (lib "eagle-import") (part "SMD-RES-10K-1%-1/8W(0805)"))
    )
    (comp (ref "R126")
      (value "4701")
      (footprint "eagle-import:R0805")
      (fields (field (name "MPN") "RC0805JR-074K7L"))
      (libsource (lib "eagle-import") (part "SMD-RES-4.7K-5%-1/8W(0805)"))
    )
    (comp (ref "R127")
      (value "47")
      (footprint "eagle-import:V235_17_1MM")
      (libsource (lib "eagle-import") (part "R-EU_V235/17_1MM"))
    )
    (comp (ref "R128")
      (value "102")
      (footprint "eagle-import:R0805")
      (fields (field (name "MPN") "RC0805JR-071KL"))
      (libsource (lib "eagle-import") (part "SMD-RES-1K-5%-1/8W(0805)"))
    )
    (comp (ref "R129")
      (value "47")
      (footprint "eagle-import:V235_17_1MM")
      (libsource (lib "eagle-import") (part "R-EU_V235/17_1MM"))
    )
    (comp (ref "R130")
      (value "104")
      (footprint "eagle-import:R0805")
      (fields (field (name "MPN") "RC0805FR-0710KL"))
      (libsource (lib "eagle-import") (part "SMD-RES-10K-1%-1/8W(0805)"))
    )
    (comp (ref "R131")
      (value "1502")
      (footprint "eagle-import:R0805")
      (fields (field (name "MPN") "RC0805FR-0710KL"))
      (libsource (lib "eagle-import") (part "SMD-RES-10K-1%-1/8W(0805)"))
    )
    (comp (ref "R132")
      (value "1002")
      (footprint "eagle-import:R0805")
      (fields (field (name "MPN") "RC0805FR-0710KL"))
      (libsource (lib "eagle-import") (part "SMD-RES-10K-1%-1/8W(0805)"))
    )
    (comp (ref "R133")
      (value "2201")
      (footprint "eagle-import:R0805")
      (fields (field (name "MPN") "RC0805JR-072K2L"))
      (libsource (lib "eagle-import") (part "SMD-RES-2.2K-5%-1/8W(0805)"))
    )
    (comp (ref "R134")
      (value "13")
      (footprint "eagle-import:R1206")
      (fields (field (name "MPN") "RC1206JR-0713RL"))
      (libsource (lib "eagle-import") (part "SMD-RES-13R-5%-1/4W(1206)"))
    )
    (comp (ref "R135")
      (value "104")
      (footprint "eagle-import:R0805")
      (fields (field (name "MPN") "RC0805FR-0710KL"))
      (libsource (lib "eagle-import") (part "SMD-RES-10K-1%-1/8W(0805)"))
    )
    (comp (ref "R136")
      (value "47")
      (footprint "eagle-import:V235_17_1MM")
      (libsource (lib "eagle-import") (part "R-EU_V235/17_1MM"))
    )
    (comp (ref "R137")
      (value "47")
      (footprint "eagle-import:V235_17_1MM")
      (libsource (lib "eagle-import") (part "R-EU_V235/17_1MM"))
    )
    (comp (ref "R138")
      (value "100")
      (footprint "eagle-import:R0805")
      (fields (field (name "MPN") "RC0805JR-072K2L"))
      (libsource (lib "eagle-import") (part "SMD-RES-2.2K-5%-1/8W(0805)"))
    )
    (comp (ref "R140")
      (value "2702")
      (footprint "eagle-import:R0805")
      (fields (field (name "MPN") "RC0805FR-0710KL"))
      (libsource (lib "eagle-import") (part "SMD-RES-10K-1%-1/8W(0805)"))
    )
    (comp (ref "R141")
      (value "104")
      (footprint "eagle-import:R0805")
      (fields (field (name "MPN") "RC0805FR-0710KL"))
      (libsource (lib "eagle-import") (part "SMD-RES-10K-1%-1/8W(0805)"))
    )
    (comp (ref "R142")
      (value "(1000)")
      (footprint "eagle-import:R0805")
      (fields (field (name "MPN") "RC0805JR-07100RL"))
      (libsource (lib "eagle-import") (part "SMD-RES-100R-5%-1/8W(0805)"))
    )
    (comp (ref "R143")
      (value "(101)")
      (footprint "eagle-import:R0805")
      (fields (field (name "MPN") "RC0805JR-07100RL"))
      (libsource (lib "eagle-import") (part "SMD-RES-100R-5%-1/8W(0805)"))
    )
    (comp (ref "R144")
      (value "(1002)")
      (footprint "eagle-import:R0805")
      (fields (field (name "MPN") "RC0805FR-0710KL"))
      (libsource (lib "eagle-import") (part "SMD-RES-10K-1%-1/8W(0805)"))
    )
    (comp (ref "R145")
      (value "2702")
      (footprint "eagle-import:R0805")
      (fields (field (name "MPN") "RC0805JR-074K7L"))
      (libsource (lib "eagle-import") (part "SMD-RES-4.7K-5%-1/8W(0805)"))
    )
    (comp (ref "R146")
      (value "1002")
      (footprint "eagle-import:R0805")
      (fields (field (name "MPN") "RC0805JR-074K7L"))
      (libsource (lib "eagle-import") (part "SMD-RES-4.7K-5%-1/8W(0805)"))
    )
    (comp (ref "SJ101")
      (value "SJ")
      (footprint "eagle-import:SJ")
      (libsource (lib "eagle-import") (part "solder-jumper_SJ"))
    )
    (comp (ref "SJMP")
      (value "SJ")
      (footprint "eagle-import:SJ")
      (libsource (lib "eagle-import") (part "SJ"))
    )
    (comp (ref "START")
      (value "TPSB2.0")
      (footprint "eagle-import:B2.0")
      (libsource (lib "eagle-import") (part "TPSB2.0"))
    )
    (comp (ref "TP1")
      (value "TPSB2.0")
      (footprint "eagle-import:B2.0")
      (libsource (lib "eagle-import") (part "TPSB2.0"))
    )
    (comp (ref "TP2")
      (value "TPSB2.0")
      (footprint "eagle-import:B2.0")
      (libsource (lib "eagle-import") (part "TPSB2.0"))
    )
    (comp (ref "TP3")
      (value "TPSB2.0")
      (footprint "eagle-import:B2.0")
      (libsource (lib "eagle-import") (part "TPSB2.0"))
    )
    (comp (ref "TP4")
      (value "TPSB2.0")
      (footprint "eagle-import:B2.0")
      (libsource (lib "eagle-import") (part "TPSB2.0"))
    )
    (comp (ref "TP5")
      (value "TPSB2.0")
      (footprint "eagle-import:B2.0")
      (libsource (lib "eagle-import") (part "TPSB2.0"))
    )
    (comp (ref "TP6")
      (value "TPSB2.0")
      (footprint "eagle-import:B2.0")
      (libsource (lib "eagle-import") (part "TPSB2.0"))
    )
    (comp (ref "TP7")
      (value "TPSB2.0")
      (footprint "eagle-import:B2.0")
      (libsource (lib "eagle-import") (part "TPSB2.0"))
    )
    (comp (ref "TP8")
      (value "TPSB2.0")
      (footprint "eagle-import:B2.0")
      (libsource (lib "eagle-import") (part "TPSB2.0"))
    )
    (comp (ref "TP9")
      (value "TPSB2.0")
      (footprint "eagle-import:B2.0")
      (libsource (lib "eagle-import") (part "TPSB2.0"))
    )
    (comp (ref "TP10")
      (value "TPSB2.0")
      (footprint "eagle-import:B2.0")
      (libsource (lib "eagle-import") (part "TPSB2.0"))
    )
    (comp (ref "TP11")
      (value "TPSB2.0")
      (footprint "eagle-import:B2.0")
      (libsource (lib "eagle-import") (part "TPSB2.0"))
    )
    (comp (ref "TP12")
      (value "TPSB2.0")
      (footprint "eagle-import:B2.0")
      (libsource (lib "eagle-import") (part "TPSB2.0"))
    )
    (comp (ref "TP13")
      (value "TPSB2.0")
      (footprint "eagle-import:B2.0")
      (libsource (lib "eagle-import") (part "TPSB2.0"))
    )
    (comp (ref "TP16")
      (value "TPSB2.0")
      (footprint "eagle-import:B2.0")
      (libsource (lib "eagle-import") (part "TPSB2.0"))
    )
    (comp (ref "TP17")
      (value "TPSB2.0")
      (footprint "eagle-import:B2.0")
      (libsource (lib "eagle-import") (part "TPSB2.0"))
    )
    (comp (ref "TP18")
      (value "TPSB2.0")
      (footprint "eagle-import:B2.0")
      (libsource (lib "eagle-import") (part "TPSB2.0"))
    )
    (comp (ref "TP19")
      (value "TPSB2.0")
      (footprint "eagle-import:B2.0")
      (libsource (lib "eagle-import") (part "TPSB2.0"))
    )
    (comp (ref "TP21")
      (value "TPSB2.0")
      (footprint "eagle-import:B2.0")
      (libsource (lib "eagle-import") (part "TPSB2.0"))
    )
    (comp (ref "TP22")
      (value "TPSB2.0")
      (footprint "eagle-import:B2.0")
      (libsource (lib "eagle-import") (part "TPSB2.0"))
    )
    (comp (ref "TP23")
      (value "TPSB2.0")
      (footprint "eagle-import:B2.0")
      (libsource (lib "eagle-import") (part "TPSB2.0"))
    )
    (comp (ref "TP24")
      (value "TPSB1,27")
      (footprint "eagle-import:B1,27")
      (libsource (lib "eagle-import") (part "TPSB1,27"))
    )
    (comp (ref "TP25")
      (value "TPSB2.0")
      (footprint "eagle-import:B2.0")
      (libsource (lib "eagle-import") (part "TPSB2.0"))
    )
    (comp (ref "TP26")
      (value "TPSB2.0")
      (footprint "eagle-import:B2.0")
      (libsource (lib "eagle-import") (part "TPSB2.0"))
    )
    (comp (ref "X101")
      (value "CON_BMWV2")
      (footprint "eagle-import:24-PIN_V2")
      (libsource (lib "eagle-import") (part "CON_BMWV2"))
    )
    (comp (ref "X102")
      (value "22-23-2021")
      (footprint "eagle-import:22-23-2021")
      (fields (field (name "MF") "MOLEX"))
      (libsource (lib "eagle-import") (part "22-23-2021"))
    )
    (comp (ref "X103")
      (value "22-23-2051")
      (footprint "eagle-import:22-23-2051")
      (fields (field (name "MF") "MOLEX"))
      (libsource (lib "eagle-import") (part "22-23-2051"))
    )
  )
  (nets
    (net (code "1") (name "+10V") (class "Default")
      (node (ref "10V") (pin "TP") (pinfunction "PP_TP") (pintype "input"))
      (node (ref "10V1") (pin "TP") (pinfunction "PP_TP") (pintype "input"))
      (node (ref "10V2") (pin "TP") (pinfunction "PP_TP") (pintype "input"))
      (node (ref "10V3") (pin "TP") (pinfunction "PP_TP") (pintype "input"))
      (node (ref "10V4") (pin "TP") (pinfunction "PP_TP") (pintype "input"))
      (node (ref "10V5") (pin "TP") (pinfunction "PP_TP") (pintype "input"))
      (node (ref "C102") (pin "1") (pinfunction "1_1") (pintype "passive"))
      (node (ref "C22") (pin "1") (pinfunction "1_1") (pintype "passive"))
      (node (ref "C34") (pin "1") (pinfunction "1_1") (pintype "passive"))
      (node (ref "C46") (pin "1") (pinfunction "1_1") (pintype "passive"))
      (node (ref "C58") (pin "1") (pinfunction "1_1") (pintype "passive"))
      (node (ref "C9") (pin "1") (pinfunction "1_1") (pintype "passive"))
      (node (ref "IC104") (pin "1") (pinfunction "OUT_1") (pintype "passive"))
      (node (ref "IC110") (pin "4") (pinfunction "R_4") (pintype "input"))
      (node (ref "IC110") (pin "8") (pinfunction "V+_8") (pintype "power_in"))
      (node (ref "IC111") (pin "13") (pinfunction "CD_13") (pintype "input"))
      (node (ref "IC111") (pin "16") (pinfunction "VDD_16") (pintype "power_in"))
      (node (ref "IC111") (pin "3") (pinfunction "CD_3") (pintype "input"))
      (node (ref "IC111") (pin "5") (pinfunction "B_5") (pintype "input"))
      (node (ref "IC15") (pin "4") (pinfunction "R_4") (pintype "input"))
      (node (ref "IC15") (pin "8") (pinfunction "V+_8") (pintype "power_in"))
      (node (ref "IC16") (pin "13") (pinfunction "CD_13") (pintype "input"))
      (node (ref "IC16") (pin "16") (pinfunction "VDD_16") (pintype "power_in"))
      (node (ref "IC16") (pin "3") (pinfunction "CD_3") (pintype "input"))
      (node (ref "IC16") (pin "5") (pinfunction "B_5") (pintype "input"))
      (node (ref "IC17") (pin "1") (pinfunction "OUT_1") (pintype "passive"))
      (node (ref "IC24") (pin "4") (pinfunction "R_4") (pintype "input"))
      (node (ref "IC24") (pin "8") (pinfunction "V+_8") (pintype "power_in"))
      (node (ref "IC25") (pin "13") (pinfunction "CD_13") (pintype "input"))
      (node (ref "IC25") (pin "16") (pinfunction "VDD_16") (pintype "power_in"))
      (node (ref "IC25") (pin "3") (pinfunction "CD_3") (pintype "input"))
      (node (ref "IC25") (pin "5") (pinfunction "B_5") (pintype "input"))
      (node (ref "IC26") (pin "1") (pinfunction "OUT_1") (pintype "passive"))
      (node (ref "IC33") (pin "4") (pinfunction "R_4") (pintype "input"))
      (node (ref "IC33") (pin "8") (pinfunction "V+_8") (pintype "power_in"))
      (node (ref "IC34") (pin "13") (pinfunction "CD_13") (pintype "input"))
      (node (ref "IC34") (pin "16") (pinfunction "VDD_16") (pintype "power_in"))
      (node (ref "IC34") (pin "3") (pinfunction "CD_3") (pintype "input"))
      (node (ref "IC34") (pin "5") (pinfunction "B_5") (pintype "input"))
      (node (ref "IC35") (pin "1") (pinfunction "OUT_1") (pintype "passive"))
      (node (ref "IC42") (pin "4") (pinfunction "R_4") (pintype "input"))
      (node (ref "IC42") (pin "8") (pinfunction "V+_8") (pintype "power_in"))
      (node (ref "IC43") (pin "13") (pinfunction "CD_13") (pintype "input"))
      (node (ref "IC43") (pin "16") (pinfunction "VDD_16") (pintype "power_in"))
      (node (ref "IC43") (pin "3") (pinfunction "CD_3") (pintype "input"))
      (node (ref "IC43") (pin "5") (pinfunction "B_5") (pintype "input"))
      (node (ref "IC44") (pin "1") (pinfunction "OUT_1") (pintype "passive"))
      (node (ref "IC6") (pin "4") (pinfunction "R_4") (pintype "input"))
      (node (ref "IC6") (pin "8") (pinfunction "V+_8") (pintype "power_in"))
      (node (ref "IC7") (pin "13") (pinfunction "CD_13") (pintype "input"))
      (node (ref "IC7") (pin "16") (pinfunction "VDD_16") (pintype "power_in"))
      (node (ref "IC7") (pin "3") (pinfunction "CD_3") (pintype "input"))
      (node (ref "IC7") (pin "5") (pinfunction "B_5") (pintype "input"))
      (node (ref "IC8") (pin "1") (pinfunction "OUT_1") (pintype "passive"))
      (node (ref "R10") (pin "2") (pinfunction "2_2") (pintype "passive"))
      (node (ref "R139") (pin "2") (pinfunction "2_2") (pintype "passive"))
      (node (ref "R145") (pin "2") (pinfunction "2_2") (pintype "passive"))
      (node (ref "R163") (pin "2") (pinfunction "2_2") (pintype "passive"))
      (node (ref "R201") (pin "2") (pinfunction "2_2") (pintype "passive"))
      (node (ref "R218") (pin "2") (pinfunction "2_2") (pintype "passive"))
      (node (ref "R256") (pin "2") (pinfunction "2_2") (pintype "passive"))
      (node (ref "R273") (pin "2") (pinfunction "2_2") (pintype "passive"))
      (node (ref "R311") (pin "2") (pinfunction "2_2") (pintype "passive"))
      (node (ref "R328") (pin "2") (pinfunction "2_2") (pintype "passive"))
      (node (ref "R47") (pin "2") (pinfunction "2_2") (pintype "passive"))
      (node (ref "R64") (pin "2") (pinfunction "2_2") (pintype "passive"))
    )
    (net (code "2") (name "+12V") (class "Default")
      (node (ref "10") (pin "1") (pinfunction "KL_1") (pintype "passive"))
      (node (ref "12") (pin "1") (pinfunction "KL_1") (pintype "passive"))
      (node (ref "2") (pin "1") (pinfunction "KL_1") (pintype "passive"))
      (node (ref "4") (pin "1") (pinfunction "KL_1") (pintype "passive"))
      (node (ref "6") (pin "1") (pinfunction "KL_1") (pintype "passive"))
      (node (ref "8") (pin "1") (pinfunction "KL_1") (pintype "passive"))
      (node (ref "C13") (pin "1") (pinfunction "1_1") (pintype "passive"))
      (node (ref "C2") (pin "1") (pinfunction "1_1") (pintype "passive"))
      (node (ref "C26") (pin "1") (pinfunction "1_1") (pintype "passive"))
      (node (ref "C38") (pin "1") (pinfunction "1_1") (pintype "passive"))
      (node (ref "C50") (pin "1") (pinfunction "1_1") (pintype "passive"))
      (node (ref "C62") (pin "1") (pinfunction "1_1") (pintype "passive"))
      (node (ref "D101") (pin "C") (pinfunction "C_C") (pintype "passive"))
      (node (ref "D13") (pin "C") (pinfunction "C_C") (pintype "passive"))
      (node (ref "D27") (pin "C") (pinfunction "C_C") (pintype "passive"))
      (node (ref "D41") (pin "C") (pinfunction "C_C") (pintype "passive"))
      (node (ref "D55") (pin "C") (pinfunction "C_C") (pintype "passive"))
      (node (ref "D69") (pin "C") (pinfunction "C_C") (pintype "passive"))
      (node (ref "IC1") (pin "16") (pinfunction "VDD_16") (pintype "power_in"))
      (node (ref "IC10") (pin "16") (pinfunction "VDD_16") (pintype "power_in"))
      (node (ref "IC102") (pin "3") (pinfunction "IN_3") (pintype "input"))
      (node (ref "IC104") (pin "3") (pinfunction "IN_3") (pintype "input"))
      (node (ref "IC105") (pin "16") (pinfunction "VDD_16") (pintype "power_in"))
      (node (ref "IC107") (pin "9") (pinfunction "CD+_9") (pintype "passive"))
      (node (ref "IC12") (pin "9") (pinfunction "CD+_9") (pintype "passive"))
      (node (ref "IC14") (pin "3") (pinfunction "IN_3") (pintype "input"))
      (node (ref "IC17") (pin "3") (pinfunction "IN_3") (pintype "input"))
      (node (ref "IC19") (pin "16") (pinfunction "VDD_16") (pintype "power_in"))
      (node (ref "IC21") (pin "9") (pinfunction "CD+_9") (pintype "passive"))
      (node (ref "IC23") (pin "3") (pinfunction "IN_3") (pintype "input"))
      (node (ref "IC26") (pin "3") (pinfunction "IN_3") (pintype "input"))
      (node (ref "IC28") (pin "16") (pinfunction "VDD_16") (pintype "power_in"))
      (node (ref "IC3") (pin "9") (pinfunction "CD+_9") (pintype "passive"))
      (node (ref "IC30") (pin "9") (pinfunction "CD+_9") (pintype "passive"))
      (node (ref "IC32") (pin "3") (pinfunction "IN_3") (pintype "input"))
      (node (ref "IC35") (pin "3") (pinfunction "IN_3") (pintype "input"))
      (node (ref "IC37") (pin "16") (pinfunction "VDD_16") (pintype "power_in"))
      (node (ref "IC39") (pin "9") (pinfunction "CD+_9") (pintype "passive"))
      (node (ref "IC41") (pin "3") (pinfunction "IN_3") (pintype "input"))
      (node (ref "IC44") (pin "3") (pinfunction "IN_3") (pintype "input"))
      (node (ref "IC5") (pin "3") (pinfunction "IN_3") (pintype "input"))
      (node (ref "IC8") (pin "3") (pinfunction "IN_3") (pintype "input"))
      (node (ref "JP1") (pin "2") (pinfunction "2_2") (pintype "passive"))
      (node (ref "JP101") (pin "2") (pinfunction "2_2") (pintype "passive"))
      (node (ref "JP11") (pin "2") (pinfunction "2_2") (pintype "passive"))
      (node (ref "JP16") (pin "2") (pinfunction "2_2") (pintype "passive"))
      (node (ref "JP21") (pin "2") (pinfunction "2_2") (pintype "passive"))
      (node (ref "JP6") (pin "2") (pinfunction "2_2") (pintype "passive"))
      (node (ref "R102") (pin "1") (pinfunction "1_1") (pintype "passive"))
      (node (ref "R106") (pin "1") (pinfunction "1_1") (pintype "passive"))
      (node (ref "R109") (pin "2") (pinfunction "2_2") (pintype "passive"))
      (node (ref "R110") (pin "2") (pinfunction "2_2") (pintype "passive"))
      (node (ref "R111") (pin "2") (pinfunction "2_2") (pintype "passive"))
      (node (ref "R12") (pin "2") (pinfunction "2_2") (pintype "passive"))
      (node (ref "R13") (pin "2") (pinfunction "2_2") (pintype "passive"))
      (node (ref "R135") (pin "1") (pinfunction "1_1") (pintype "passive"))
      (node (ref "R15") (pin "2") (pinfunction "2_2") (pintype "passive"))
      (node (ref "R16") (pin "2") (pinfunction "2_2") (pintype "passive"))
      (node (ref "R164") (pin "2") (pinfunction "2_2") (pintype "passive"))
      (node (ref "R165") (pin "2") (pinfunction "2_2") (pintype "passive"))
      (node (ref "R169") (pin "2") (pinfunction "2_2") (pintype "passive"))
      (node (ref "R17") (pin "2") (pinfunction "2_2") (pintype "passive"))
      (node (ref "R170") (pin "2") (pinfunction "2_2") (pintype "passive"))
      (node (ref "R171") (pin "2") (pinfunction "2_2") (pintype "passive"))
      (node (ref "R190") (pin "1") (pinfunction "1_1") (pintype "passive"))
      (node (ref "R191") (pin "1") (pinfunction "1_1") (pintype "passive"))
      (node (ref "R195") (pin "1") (pinfunction "1_1") (pintype "passive"))
      (node (ref "R219") (pin "2") (pinfunction "2_2") (pintype "passive"))
      (node (ref "R220") (pin "2") (pinfunction "2_2") (pintype "passive"))
      (node (ref "R224") (pin "2") (pinfunction "2_2") (pintype "passive"))
      (node (ref "R225") (pin "2") (pinfunction "2_2") (pintype "passive"))
      (node (ref "R226") (pin "2") (pinfunction "2_2") (pintype "passive"))
      (node (ref "R245") (pin "1") (pinfunction "1_1") (pintype "passive"))
      (node (ref "R246") (pin "1") (pinfunction "1_1") (pintype "passive"))
      (node (ref "R250") (pin "1") (pinfunction "1_1") (pintype "passive"))
      (node (ref "R274") (pin "2") (pinfunction "2_2") (pintype "passive"))
      (node (ref "R275") (pin "2") (pinfunction "2_2") (pintype "passive"))
      (node (ref "R279") (pin "2") (pinfunction "2_2") (pintype "passive"))
      (node (ref "R280") (pin "2") (pinfunction "2_2") (pintype "passive"))
      (node (ref "R281") (pin "2") (pinfunction "2_2") (pintype "passive"))
      (node (ref "R300") (pin "1") (pinfunction "1_1") (pintype "passive"))
      (node (ref "R301") (pin "1") (pinfunction "1_1") (pintype "passive"))
      (node (ref "R305") (pin "1") (pinfunction "1_1") (pintype "passive"))
      (node (ref "R329") (pin "2") (pinfunction "2_2") (pintype "passive"))
      (node (ref "R330") (pin "2") (pinfunction "2_2") (pintype "passive"))
      (node (ref "R36") (pin "1") (pinfunction "1_1") (pintype "passive"))
      (node (ref "R37") (pin "1") (pinfunction "1_1") (pintype "passive"))
      (node (ref "R41") (pin "1") (pinfunction "1_1") (pintype "passive"))
      (node (ref "R65") (pin "2") (pinfunction "2_2") (pintype "passive"))
      (node (ref "R66") (pin "2") (pinfunction "2_2") (pintype "passive"))
      (node (ref "R70") (pin "2") (pinfunction "2_2") (pintype "passive"))
      (node (ref "R71") (pin "2") (pinfunction "2_2") (pintype "passive"))
      (node (ref "R72") (pin "2") (pinfunction "2_2") (pintype "passive"))
      (node (ref "R91") (pin "1") (pinfunction "1_1") (pintype "passive"))
      (node (ref "R92") (pin "1") (pinfunction "1_1") (pintype "passive"))
      (node (ref "R96") (pin "1") (pinfunction "1_1") (pintype "passive"))
      (node (ref "TP114") (pin "TP") (pinfunction "PP_TP") (pintype "input"))
      (node (ref "TP12") (pin "TP") (pinfunction "PP_TP") (pintype "input"))
      (node (ref "TP137") (pin "TP") (pinfunction "PP_TP") (pintype "input"))
      (node (ref "TP45") (pin "TP") (pinfunction "PP_TP") (pintype "input"))
      (node (ref "TP68") (pin "TP") (pinfunction "PP_TP") (pintype "input"))
      (node (ref "TP91") (pin "TP") (pinfunction "PP_TP") (pintype "input"))
      (node (ref "X103") (pin "1") (pinfunction "S_1") (pintype "passive"))
      (node (ref "X11") (pin "1") (pinfunction "S_1") (pintype "passive"))
      (node (ref "X14") (pin "1") (pinfunction "S_1") (pintype "passive"))
      (node (ref "X2") (pin "1") (pinfunction "S_1") (pintype "passive"))
      (node (ref "X5") (pin "1") (pinfunction "S_1") (pintype "passive"))
      (node (ref "X8") (pin "1") (pinfunction "S_1") (pintype "passive"))
    )
    (net (code "3") (name "GND") (class "Default")
      (node (ref "1") (pin "12") (pinfunction "KL_12") (pintype "passive"))
      (node (ref "11") (pin "12") (pinfunction "KL_12") (pintype "passive"))
      (node (ref "3") (pin "12") (pinfunction "KL_12") (pintype "passive"))
      (node (ref "5") (pin "12") (pinfunction "KL_12") (pintype "passive"))
      (node (ref "7") (pin "12") (pinfunction "KL_12") (pintype "passive"))
      (node (ref "9") (pin "12") (pinfunction "KL_12") (pintype "passive"))
      (node (ref "C1") (pin "2") (pinfunction "2_2") (pintype "passive"))
      (node (ref "C10") (pin "2") (pinfunction "2_2") (pintype "passive"))
      (node (ref "C101") (pin "2") (pinfunction "2_2") (pintype "passive"))
      (node (ref "C102") (pin "2") (pinfunction "2_2") (pintype "passive"))
      (node (ref "C103") (pin "2") (pinfunction "2_2") (pintype "passive"))
      (node (ref "C104") (pin "2") (pinfunction "2_2") (pintype "passive"))
      (node (ref "C105") (pin "2") (pinfunction "2_2") (pintype "passive"))
      (node (ref "C106") (pin "1") (pinfunction "1_1") (pintype "passive"))
      (node (ref "C107") (pin "2") (pinfunction "2_2") (pintype "passive"))
      (node (ref "C108") (pin "2") (pinfunction "2_2") (pintype "passive"))
      (node (ref "C109") (pin "1") (pinfunction "1_1") (pintype "passive"))
      (node (ref "C11") (pin "2") (pinfunction "2_2") (pintype "passive"))
      (node (ref "C110") (pin "2") (pinfunction "2_2") (pintype "passive"))
      (node (ref "C12") (pin "1") (pinfunction "1_1") (pintype "passive"))
      (node (ref "C13") (pin "2") (pinfunction "2_2") (pintype "passive"))
      (node (ref "C14") (pin "2") (pinfunction "2_2") (pintype "passive"))
      (node (ref "C15") (pin "1") (pinfunction "1_1") (pintype "passive"))
      (node (ref "C16") (pin "2") (pinfunction "2_2") (pintype "passive"))
      (node (ref "C17") (pin "2") (pinfunction "2_2") (pintype "passive"))
      (node (ref "C18") (pin "2") (pinfunction "2_2") (pintype "passive"))
      (node (ref "C19") (pin "2") (pinfunction "2_2") (pintype "passive"))
      (node (ref "C2") (pin "2") (pinfunction "2_2") (pintype "passive"))
      (node (ref "C20") (pin "1") (pinfunction "1_1") (pintype "passive"))
      (node (ref "C21") (pin "1") (pinfunction "1_1") (pintype "passive"))
      (node (ref "C22") (pin "2") (pinfunction "2_2") (pintype "passive"))
      (node (ref "C23") (pin "2") (pinfunction "2_2") (pintype "passive"))
      (node (ref "C24") (pin "2") (pinfunction "2_2") (pintype "passive"))
      (node (ref "C25") (pin "1") (pinfunction "1_1") (pintype "passive"))
      (node (ref "C26") (pin "2") (pinfunction "2_2") (pintype "passive"))
      (node (ref "C27") (pin "2") (pinfunction "2_2") (pintype "passive"))
      (node (ref "C28") (pin "2") (pinfunction "2_2") (pintype "passive"))
      (node (ref "C29") (pin "2") (pinfunction "2_2") (pintype "passive"))
      (node (ref "C3") (pin "2") (pinfunction "2_2") (pintype "passive"))
      (node (ref "C30") (pin "2") (pinfunction "2_2") (pintype "passive"))
      (node (ref "C31") (pin "2") (pinfunction "2_2") (pintype "passive"))
      (node (ref "C32") (pin "1") (pinfunction "1_1") (pintype "passive"))
      (node (ref "C33") (pin "1") (pinfunction "1_1") (pintype "passive"))
      (node (ref "C34") (pin "2") (pinfunction "2_2") (pintype "passive"))
      (node (ref "C35") (pin "2") (pinfunction "2_2") (pintype "passive"))
      (node (ref "C36") (pin "2") (pinfunction "2_2") (pintype "passive"))
      (node (ref "C37") (pin "1") (pinfunction "1_1") (pintype "passive"))
      (node (ref "C38") (pin "2") (pinfunction "2_2") (pintype "passive"))
      (node (ref "C39") (pin "2") (pinfunction "2_2") (pintype "passive"))
      (node (ref "C4") (pin "2") (pinfunction "2_2") (pintype "passive"))
      (node (ref "C40") (pin "2") (pinfunction "2_2") (pintype "passive"))
      (node (ref "C41") (pin "2") (pinfunction "2_2") (pintype "passive"))
      (node (ref "C42") (pin "2") (pinfunction "2_2") (pintype "passive"))
      (node (ref "C43") (pin "2") (pinfunction "2_2") (pintype "passive"))
      (node (ref "C44") (pin "1") (pinfunction "1_1") (pintype "passive"))
      (node (ref "C45") (pin "1") (pinfunction "1_1") (pintype "passive"))
      (node (ref "C46") (pin "2") (pinfunction "2_2") (pintype "passive"))
      (node (ref "C47") (pin "2") (pinfunction "2_2") (pintype "passive"))
      (node (ref "C48") (pin "2") (pinfunction "2_2") (pintype "passive"))
      (node (ref "C49") (pin "1") (pinfunction "1_1") (pintype "passive"))
      (node (ref "C5") (pin "2") (pinfunction "2_2") (pintype "passive"))
      (node (ref "C50") (pin "2") (pinfunction "2_2") (pintype "passive"))
      (node (ref "C51") (pin "2") (pinfunction "2_2") (pintype "passive"))
      (node (ref "C52") (pin "2") (pinfunction "2_2") (pintype "passive"))
      (node (ref "C53") (pin "2") (pinfunction "2_2") (pintype "passive"))
      (node (ref "C54") (pin "2") (pinfunction "2_2") (pintype "passive"))
      (node (ref "C55") (pin "2") (pinfunction "2_2") (pintype "passive"))
      (node (ref "C56") (pin "1") (pinfunction "1_1") (pintype "passive"))
      (node (ref "C57") (pin "1") (pinfunction "1_1") (pintype "passive"))
      (node (ref "C58") (pin "2") (pinfunction "2_2") (pintype "passive"))
      (node (ref "C59") (pin "2") (pinfunction "2_2") (pintype "passive"))
      (node (ref "C6") (pin "2") (pinfunction "2_2") (pintype "passive"))
      (node (ref "C60") (pin "2") (pinfunction "2_2") (pintype "passive"))
      (node (ref "C61") (pin "1") (pinfunction "1_1") (pintype "passive"))
      (node (ref "C62") (pin "2") (pinfunction "2_2") (pintype "passive"))
      (node (ref "C7") (pin "1") (pinfunction "1_1") (pintype "passive"))
      (node (ref "C8") (pin "1") (pinfunction "1_1") (pintype "passive"))
      (node (ref "C9") (pin "2") (pinfunction "2_2") (pintype "passive"))
      (node (ref "D101") (pin "A") (pinfunction "A_A") (pintype "passive"))
      (node (ref "D104") (pin "A") (pinfunction "A_A") (pintype "passive"))
      (node (ref "D105") (pin "1") (pinfunction "+_1") (pintype "passive"))
      (node (ref "D11") (pin "1") (pinfunction "+_1") (pintype "passive"))
      (node (ref "D13") (pin "A") (pinfunction "A_A") (pintype "passive"))
      (node (ref "D14") (pin "A") (pinfunction "A_A") (pintype "passive"))
      (node (ref "D17") (pin "A") (pinfunction "A_A") (pintype "passive"))
      (node (ref "D25") (pin "1") (pinfunction "+_1") (pintype "passive"))
      (node (ref "D27") (pin "A") (pinfunction "A_A") (pintype "passive"))
      (node (ref "D28") (pin "A") (pinfunction "A_A") (pintype "passive"))
      (node (ref "D31") (pin "A") (pinfunction "A_A") (pintype "passive"))
      (node (ref "D39") (pin "1") (pinfunction "+_1") (pintype "passive"))
      (node (ref "D4") (pin "A") (pinfunction "A_A") (pintype "passive"))
      (node (ref "D41") (pin "A") (pinfunction "A_A") (pintype "passive"))
      (node (ref "D42") (pin "A") (pinfunction "A_A") (pintype "passive"))
      (node (ref "D45") (pin "A") (pinfunction "A_A") (pintype "passive"))
      (node (ref "D53") (pin "1") (pinfunction "+_1") (pintype "passive"))
      (node (ref "D55") (pin "A") (pinfunction "A_A") (pintype "passive"))
      (node (ref "D56") (pin "A") (pinfunction "A_A") (pintype "passive"))
      (node (ref "D59") (pin "A") (pinfunction "A_A") (pintype "passive"))
      (node (ref "D67") (pin "1") (pinfunction "+_1") (pintype "passive"))
      (node (ref "D69") (pin "A") (pinfunction "A_A") (pintype "passive"))
      (node (ref "D70") (pin "A") (pinfunction "A_A") (pintype "passive"))
      (node (ref "D73") (pin "A") (pinfunction "A_A") (pintype "passive"))
      (node (ref "IC1") (pin "11") (pinfunction "D_11") (pintype "input"))
      (node (ref "IC1") (pin "8") (pinfunction "VSS_8") (pintype "power_in"))
      (node (ref "IC10") (pin "11") (pinfunction "D_11") (pintype "input"))
      (node (ref "IC10") (pin "8") (pinfunction "VSS_8") (pintype "power_in"))
      (node (ref "IC101") (pin "4") (pinfunction "V-_4") (pintype "power_in"))
      (node (ref "IC102") (pin "2") (pinfunction "GND_2") (pintype "input"))
      (node (ref "IC102") (pin "2@1") (pinfunction "GND_2@1") (pintype "input"))
      (node (ref "IC104") (pin "2") (pinfunction "GND_2") (pintype "input"))
      (node (ref "IC104") (pin "2@1") (pinfunction "GND_2@1") (pintype "input"))
      (node (ref "IC105") (pin "11") (pinfunction "D_11") (pintype "input"))
      (node (ref "IC105") (pin "8") (pinfunction "VSS_8") (pintype "power_in"))
      (node (ref "IC107") (pin "8") (pinfunction "GND_8") (pintype "power_in"))
      (node (ref "IC108") (pin "12") (pinfunction "GND_12") (pintype "power_in"))
      (node (ref "IC110") (pin "1") (pinfunction "GND_1") (pintype "power_in"))
      (node (ref "IC111") (pin "1") (pinfunction "T1_1") (pintype "input"))
      (node (ref "IC111") (pin "15") (pinfunction "T1_15") (pintype "input"))
      (node (ref "IC111") (pin "8") (pinfunction "VSS_8") (pintype "power_in"))
      (node (ref "IC12") (pin "8") (pinfunction "GND_8") (pintype "power_in"))
      (node (ref "IC13") (pin "12") (pinfunction "GND_12") (pintype "power_in"))
      (node (ref "IC14") (pin "2") (pinfunction "GND_2") (pintype "input"))
      (node (ref "IC14") (pin "2@1") (pinfunction "GND_2@1") (pintype "input"))
      (node (ref "IC15") (pin "1") (pinfunction "GND_1") (pintype "power_in"))
      (node (ref "IC16") (pin "1") (pinfunction "T1_1") (pintype "input"))
      (node (ref "IC16") (pin "15") (pinfunction "T1_15") (pintype "input"))
      (node (ref "IC16") (pin "8") (pinfunction "VSS_8") (pintype "power_in"))
      (node (ref "IC17") (pin "2") (pinfunction "GND_2") (pintype "input"))
      (node (ref "IC17") (pin "2@1") (pinfunction "GND_2@1") (pintype "input"))
      (node (ref "IC18") (pin "4") (pinfunction "V-_4") (pintype "power_in"))
      (node (ref "IC19") (pin "11") (pinfunction "D_11") (pintype "input"))
      (node (ref "IC19") (pin "8") (pinfunction "VSS_8") (pintype "power_in"))
      (node (ref "IC21") (pin "8") (pinfunction "GND_8") (pintype "power_in"))
      (node (ref "IC22") (pin "12") (pinfunction "GND_12") (pintype "power_in"))
      (node (ref "IC23") (pin "2") (pinfunction "GND_2") (pintype "input"))
      (node (ref "IC23") (pin "2@1") (pinfunction "GND_2@1") (pintype "input"))
      (node (ref "IC24") (pin "1") (pinfunction "GND_1") (pintype "power_in"))
      (node (ref "IC25") (pin "1") (pinfunction "T1_1") (pintype "input"))
      (node (ref "IC25") (pin "15") (pinfunction "T1_15") (pintype "input"))
      (node (ref "IC25") (pin "8") (pinfunction "VSS_8") (pintype "power_in"))
      (node (ref "IC26") (pin "2") (pinfunction "GND_2") (pintype "input"))
      (node (ref "IC26") (pin "2@1") (pinfunction "GND_2@1") (pintype "input"))
      (node (ref "IC27") (pin "4") (pinfunction "V-_4") (pintype "power_in"))
      (node (ref "IC28") (pin "11") (pinfunction "D_11") (pintype "input"))
      (node (ref "IC28") (pin "8") (pinfunction "VSS_8") (pintype "power_in"))
      (node (ref "IC3") (pin "8") (pinfunction "GND_8") (pintype "power_in"))
      (node (ref "IC30") (pin "8") (pinfunction "GND_8") (pintype "power_in"))
      (node (ref "IC31") (pin "12") (pinfunction "GND_12") (pintype "power_in"))
      (node (ref "IC32") (pin "2") (pinfunction "GND_2") (pintype "input"))
      (node (ref "IC32") (pin "2@1") (pinfunction "GND_2@1") (pintype "input"))
      (node (ref "IC33") (pin "1") (pinfunction "GND_1") (pintype "power_in"))
      (node (ref "IC34") (pin "1") (pinfunction "T1_1") (pintype "input"))
      (node (ref "IC34") (pin "15") (pinfunction "T1_15") (pintype "input"))
      (node (ref "IC34") (pin "8") (pinfunction "VSS_8") (pintype "power_in"))
      (node (ref "IC35") (pin "2") (pinfunction "GND_2") (pintype "input"))
      (node (ref "IC35") (pin "2@1") (pinfunction "GND_2@1") (pintype "input"))
      (node (ref "IC36") (pin "4") (pinfunction "V-_4") (pintype "power_in"))
      (node (ref "IC37") (pin "11") (pinfunction "D_11") (pintype "input"))
      (node (ref "IC37") (pin "8") (pinfunction "VSS_8") (pintype "power_in"))
      (node (ref "IC39") (pin "8") (pinfunction "GND_8") (pintype "power_in"))
      (node (ref "IC4") (pin "12") (pinfunction "GND_12") (pintype "power_in"))
      (node (ref "IC40") (pin "12") (pinfunction "GND_12") (pintype "power_in"))
      (node (ref "IC41") (pin "2") (pinfunction "GND_2") (pintype "input"))
      (node (ref "IC41") (pin "2@1") (pinfunction "GND_2@1") (pintype "input"))
      (node (ref "IC42") (pin "1") (pinfunction "GND_1") (pintype "power_in"))
      (node (ref "IC43") (pin "1") (pinfunction "T1_1") (pintype "input"))
      (node (ref "IC43") (pin "15") (pinfunction "T1_15") (pintype "input"))
      (node (ref "IC43") (pin "8") (pinfunction "VSS_8") (pintype "power_in"))
      (node (ref "IC44") (pin "2") (pinfunction "GND_2") (pintype "input"))
      (node (ref "IC44") (pin "2@1") (pinfunction "GND_2@1") (pintype "input"))
      (node (ref "IC45") (pin "4") (pinfunction "V-_4") (pintype "power_in"))
      (node (ref "IC5") (pin "2") (pinfunction "GND_2") (pintype "input"))
      (node (ref "IC5") (pin "2@1") (pinfunction "GND_2@1") (pintype "input"))
      (node (ref "IC6") (pin "1") (pinfunction "GND_1") (pintype "power_in"))
      (node (ref "IC7") (pin "1") (pinfunction "T1_1") (pintype "input"))
      (node (ref "IC7") (pin "15") (pinfunction "T1_15") (pintype "input"))
      (node (ref "IC7") (pin "8") (pinfunction "VSS_8") (pintype "power_in"))
      (node (ref "IC8") (pin "2") (pinfunction "GND_2") (pintype "input"))
      (node (ref "IC8") (pin "2@1") (pinfunction "GND_2@1") (pintype "input"))
      (node (ref "IC9") (pin "4") (pinfunction "V-_4") (pintype "power_in"))
      (node (ref "Q1") (pin "2") (pinfunction "S_2") (pintype "passive"))
      (node (ref "Q107") (pin "2") (pinfunction "S_2") (pintype "passive"))
      (node (ref "Q11") (pin "2") (pinfunction "S_2") (pintype "passive"))
      (node (ref "Q13") (pin "2") (pinfunction "S_2") (pintype "passive"))
      (node (ref "Q19") (pin "2") (pinfunction "S_2") (pintype "passive"))
      (node (ref "Q21") (pin "2") (pinfunction "S_2") (pintype "passive"))
      (node (ref "Q23") (pin "2") (pinfunction "S_2") (pintype "passive"))
      (node (ref "Q29") (pin "2") (pinfunction "S_2") (pintype "passive"))
      (node (ref "Q3") (pin "2") (pinfunction "S_2") (pintype "passive"))
      (node (ref "Q31") (pin "2") (pinfunction "S_2") (pintype "passive"))
      (node (ref "Q33") (pin "2") (pinfunction "S_2") (pintype "passive"))
      (node (ref "Q39") (pin "2") (pinfunction "S_2") (pintype "passive"))
      (node (ref "Q41") (pin "2") (pinfunction "S_2") (pintype "passive"))
      (node (ref "Q43") (pin "2") (pinfunction "S_2") (pintype "passive"))
      (node (ref "Q49") (pin "2") (pinfunction "S_2") (pintype "passive"))
      (node (ref "Q51") (pin "2") (pinfunction "S_2") (pintype "passive"))
      (node (ref "Q53") (pin "2") (pinfunction "S_2") (pintype "passive"))
      (node (ref "Q9") (pin "2") (pinfunction "S_2") (pintype "passive"))
      (node (ref "R100") (pin "1") (pinfunction "1_1") (pintype "passive"))
      (node (ref "R101") (pin "2") (pinfunction "2_2") (pintype "passive"))
      (node (ref "R103") (pin "2") (pinfunction "2_2") (pintype "passive"))
      (node (ref "R104") (pin "2") (pinfunction "2_2") (pintype "passive"))
      (node (ref "R107") (pin "1") (pinfunction "1_1") (pintype "passive"))
      (node (ref "R114") (pin "1") (pinfunction "1_1") (pintype "passive"))
      (node (ref "R118") (pin "1") (pinfunction "1_1") (pintype "passive"))
      (node (ref "R123") (pin "1") (pinfunction "1_1") (pintype "passive"))
      (node (ref "R132") (pin "1") (pinfunction "1_1") (pintype "passive"))
      (node (ref "R136") (pin "1") (pinfunction "1_1") (pintype "passive"))
      (node (ref "R137") (pin "1") (pinfunction "1_1") (pintype "passive"))
      (node (ref "R141") (pin "2") (pinfunction "2_2") (pintype "passive"))
      (node (ref "R143") (pin "2") (pinfunction "2_2") (pintype "passive"))
      (node (ref "R153") (pin "1") (pinfunction "1_1") (pintype "passive"))
      (node (ref "R154") (pin "2") (pinfunction "2_2") (pintype "passive"))
      (node (ref "R158") (pin "2") (pinfunction "2_2") (pintype "passive"))
      (node (ref "R159") (pin "2") (pinfunction "2_2") (pintype "passive"))
      (node (ref "R160") (pin "1") (pinfunction "1_1") (pintype "passive"))
      (node (ref "R173") (pin "1") (pinfunction "1_1") (pintype "passive"))
      (node (ref "R179") (pin "1") (pinfunction "1_1") (pintype "passive"))
      (node (ref "R183") (pin "1") (pinfunction "1_1") (pintype "passive"))
      (node (ref "R184") (pin "2") (pinfunction "2_2") (pintype "passive"))
      (node (ref "R185") (pin "2") (pinfunction "2_2") (pintype "passive"))
      (node (ref "R187") (pin "2") (pinfunction "2_2") (pintype "passive"))
      (node (ref "R19") (pin "1") (pinfunction "1_1") (pintype "passive"))
      (node (ref "R196") (pin "2") (pinfunction "2_2") (pintype "passive"))
      (node (ref "R199") (pin "1") (pinfunction "1_1") (pintype "passive"))
      (node (ref "R200") (pin "1") (pinfunction "1_1") (pintype "passive"))
      (node (ref "R208") (pin "1") (pinfunction "1_1") (pintype "passive"))
      (node (ref "R209") (pin "2") (pinfunction "2_2") (pintype "passive"))
      (node (ref "R213") (pin "2") (pinfunction "2_2") (pintype "passive"))
      (node (ref "R214") (pin "2") (pinfunction "2_2") (pintype "passive"))
      (node (ref "R215") (pin "1") (pinfunction "1_1") (pintype "passive"))
      (node (ref "R228") (pin "1") (pinfunction "1_1") (pintype "passive"))
      (node (ref "R234") (pin "1") (pinfunction "1_1") (pintype "passive"))
      (node (ref "R238") (pin "1") (pinfunction "1_1") (pintype "passive"))
      (node (ref "R239") (pin "2") (pinfunction "2_2") (pintype "passive"))
      (node (ref "R240") (pin "2") (pinfunction "2_2") (pintype "passive"))
      (node (ref "R242") (pin "2") (pinfunction "2_2") (pintype "passive"))
      (node (ref "R25") (pin "1") (pinfunction "1_1") (pintype "passive"))
      (node (ref "R251") (pin "2") (pinfunction "2_2") (pintype "passive"))
      (node (ref "R254") (pin "1") (pinfunction "1_1") (pintype "passive"))
      (node (ref "R255") (pin "1") (pinfunction "1_1") (pintype "passive"))
      (node (ref "R263") (pin "1") (pinfunction "1_1") (pintype "passive"))
      (node (ref "R264") (pin "2") (pinfunction "2_2") (pintype "passive"))
      (node (ref "R268") (pin "2") (pinfunction "2_2") (pintype "passive"))
      (node (ref "R269") (pin "2") (pinfunction "2_2") (pintype "passive"))
      (node (ref "R270") (pin "1") (pinfunction "1_1") (pintype "passive"))
      (node (ref "R283") (pin "1") (pinfunction "1_1") (pintype "passive"))
      (node (ref "R289") (pin "1") (pinfunction "1_1") (pintype "passive"))
      (node (ref "R29") (pin "1") (pinfunction "1_1") (pintype "passive"))
      (node (ref "R293") (pin "1") (pinfunction "1_1") (pintype "passive"))
      (node (ref "R294") (pin "2") (pinfunction "2_2") (pintype "passive"))
      (node (ref "R295") (pin "2") (pinfunction "2_2") (pintype "passive"))
      (node (ref "R297") (pin "2") (pinfunction "2_2") (pintype "passive"))
      (node (ref "R30") (pin "2") (pinfunction "2_2") (pintype "passive"))
      (node (ref "R306") (pin "2") (pinfunction "2_2") (pintype "passive"))
      (node (ref "R309") (pin "1") (pinfunction "1_1") (pintype "passive"))
      (node (ref "R31") (pin "2") (pinfunction "2_2") (pintype "passive"))
      (node (ref "R310") (pin "1") (pinfunction "1_1") (pintype "passive"))
      (node (ref "R318") (pin "1") (pinfunction "1_1") (pintype "passive"))
      (node (ref "R319") (pin "2") (pinfunction "2_2") (pintype "passive"))
      (node (ref "R323") (pin "2") (pinfunction "2_2") (pintype "passive"))
      (node (ref "R324") (pin "2") (pinfunction "2_2") (pintype "passive"))
      (node (ref "R325") (pin "1") (pinfunction "1_1") (pintype "passive"))
      (node (ref "R33") (pin "2") (pinfunction "2_2") (pintype "passive"))
      (node (ref "R4") (pin "1") (pinfunction "1_1") (pintype "passive"))
      (node (ref "R42") (pin "2") (pinfunction "2_2") (pintype "passive"))
      (node (ref "R45") (pin "1") (pinfunction "1_1") (pintype "passive"))
      (node (ref "R46") (pin "1") (pinfunction "1_1") (pintype "passive"))
      (node (ref "R5") (pin "2") (pinfunction "2_2") (pintype "passive"))
      (node (ref "R54") (pin "1") (pinfunction "1_1") (pintype "passive"))
      (node (ref "R55") (pin "2") (pinfunction "2_2") (pintype "passive"))
      (node (ref "R59") (pin "2") (pinfunction "2_2") (pintype "passive"))
      (node (ref "R6") (pin "2") (pinfunction "2_2") (pintype "passive"))
      (node (ref "R60") (pin "2") (pinfunction "2_2") (pintype "passive"))
      (node (ref "R61") (pin "1") (pinfunction "1_1") (pintype "passive"))
      (node (ref "R74") (pin "1") (pinfunction "1_1") (pintype "passive"))
      (node (ref "R80") (pin "1") (pinfunction "1_1") (pintype "passive"))
      (node (ref "R84") (pin "1") (pinfunction "1_1") (pintype "passive"))
      (node (ref "R85") (pin "2") (pinfunction "2_2") (pintype "passive"))
      (node (ref "R86") (pin "2") (pinfunction "2_2") (pintype "passive"))
      (node (ref "R88") (pin "2") (pinfunction "2_2") (pintype "passive"))
      (node (ref "R97") (pin "2") (pinfunction "2_2") (pintype "passive"))
      (node (ref "X1") (pin "13") (pinfunction "13_13") (pintype "passive"))
      (node (ref "X1") (pin "18") (pinfunction "18_18") (pintype "passive"))
      (node (ref "X1") (pin "23") (pinfunction "23_23") (pintype "passive"))
      (node (ref "X10") (pin "13") (pinfunction "13_13") (pintype "passive"))
      (node (ref "X10") (pin "18") (pinfunction "18_18") (pintype "passive"))
      (node (ref "X10") (pin "23") (pinfunction "23_23") (pintype "passive"))
      (node (ref "X101") (pin "13") (pinfunction "13_13") (pintype "passive"))
      (node (ref "X101") (pin "18") (pinfunction "18_18") (pintype "passive"))
      (node (ref "X101") (pin "23") (pinfunction "23_23") (pintype "passive"))
      (node (ref "X102") (pin "1") (pinfunction "S_1") (pintype "passive"))
      (node (ref "X103") (pin "5") (pinfunction "S_5") (pintype "passive"))
      (node (ref "X11") (pin "5") (pinfunction "S_5") (pintype "passive"))
      (node (ref "X12") (pin "1") (pinfunction "S_1") (pintype "passive"))
      (node (ref "X13") (pin "13") (pinfunction "13_13") (pintype "passive"))
      (node (ref "X13") (pin "18") (pinfunction "18_18") (pintype "passive"))
      (node (ref "X13") (pin "23") (pinfunction "23_23") (pintype "passive"))
      (node (ref "X14") (pin "5") (pinfunction "S_5") (pintype "passive"))
      (node (ref "X15") (pin "1") (pinfunction "S_1") (pintype "passive"))
      (node (ref "X2") (pin "5") (pinfunction "S_5") (pintype "passive"))
      (node (ref "X3") (pin "1") (pinfunction "S_1") (pintype "passive"))
      (node (ref "X4") (pin "13") (pinfunction "13_13") (pintype "passive"))
      (node (ref "X4") (pin "18") (pinfunction "18_18") (pintype "passive"))
      (node (ref "X4") (pin "23") (pinfunction "23_23") (pintype "passive"))
      (node (ref "X5") (pin "5") (pinfunction "S_5") (pintype "passive"))
      (node (ref "X6") (pin "1") (pinfunction "S_1") (pintype "passive"))
      (node (ref "X7") (pin "13") (pinfunction "13_13") (pintype "passive"))
      (node (ref "X7") (pin "18") (pinfunction "18_18") (pintype "passive"))
      (node (ref "X7") (pin "23") (pinfunction "23_23") (pintype "passive"))
      (node (ref "X8") (pin "5") (pinfunction "S_5") (pintype "passive"))
      (node (ref "X9") (pin "1") (pinfunction "S_1") (pintype "passive"))
    )
    (net (code "4") (name "Net-(1A-KL)") (class "Default")
      (node (ref "1") (pin "1") (pinfunction "KL_1") (pintype "passive"))
      (node (ref "D2") (pin "2") (pinfunction "-_2") (pintype "passive"))
      (node (ref "TP1") (pin "TP") (pinfunction "PP_TP") (pintype "input"))
    )
    (net (code "5") (name "Net-(1B-KL)") (class "Default")
      (node (ref "1") (pin "10") (pinfunction "KL_10") (pintype "passive"))
      (node (ref "D102") (pin "2") (pinfunction "-_2") (pintype "passive"))
      (node (ref "D103") (pin "2") (pinfunction "-_2") (pintype "passive"))
      (node (ref "JP104") (pin "1") (pinfunction "1_1") (pintype "passive"))
      (node (ref "SJ101") (pin "1") (pinfunction "1_1") (pintype "passive"))
      (node (ref "TP10") (pin "TP") (pinfunction "PP_TP") (pintype "input"))
    )
    (net (code "6") (name "Net-(1C-KL)") (class "Default")
      (node (ref "1") (pin "11") (pinfunction "KL_11") (pintype "passive"))
      (node (ref "D103") (pin "1") (pinfunction "+_1") (pintype "passive"))
      (node (ref "TP11") (pin "TP") (pinfunction "PP_TP") (pintype "input"))
      (node (ref "X101") (pin "19") (pinfunction "19_19") (pintype "passive"))
    )
    (net (code "7") (name "Net-(1E-KL)") (class "Default")
      (node (ref "1") (pin "2") (pinfunction "KL_2") (pintype "passive"))
      (node (ref "Q101") (pin "2") (pinfunction "C_2") (pintype "passive"))
      (node (ref "TP2") (pin "TP") (pinfunction "PP_TP") (pintype "input"))
    )
    (net (code "8") (name "Net-(1F-KL)") (class "Default")
      (node (ref "1") (pin "3") (pinfunction "KL_3") (pintype "passive"))
      (node (ref "IC107") (pin "11") (pinfunction "O6_11") (pintype "open_collector"))
      (node (ref "TP3") (pin "TP") (pinfunction "PP_TP") (pintype "input"))
    )
    (net (code "9") (name "Net-(1G-KL)") (class "Default")
      (node (ref "1") (pin "4") (pinfunction "KL_4") (pintype "passive"))
      (node (ref "IC107") (pin "10") (pinfunction "O7_10") (pintype "open_collector"))
      (node (ref "TP4") (pin "TP") (pinfunction "PP_TP") (pintype "input"))
    )
    (net (code "10") (name "Net-(1H-KL)") (class "Default")
      (node (ref "1") (pin "5") (pinfunction "KL_5") (pintype "passive"))
      (node (ref "IC107") (pin "12") (pinfunction "O5_12") (pintype "open_collector"))
      (node (ref "TP5") (pin "TP") (pinfunction "PP_TP") (pintype "input"))
    )
    (net (code "11") (name "Net-(1I-KL)") (class "Default")
      (node (ref "1") (pin "6") (pinfunction "KL_6") (pintype "passive"))
      (node (ref "IC107") (pin "13") (pinfunction "O4_13") (pintype "open_collector"))
      (node (ref "TP6") (pin "TP") (pinfunction "PP_TP") (pintype "input"))
    )
    (net (code "12") (name "Net-(1J-KL)") (class "Default")
      (node (ref "1") (pin "7") (pinfunction "KL_7") (pintype "passive"))
      (node (ref "IC107") (pin "14") (pinfunction "O3_14") (pintype "open_collector"))
      (node (ref "TP7") (pin "TP") (pinfunction "PP_TP") (pintype "input"))
    )
    (net (code "13") (name "Net-(1K-KL)") (class "Default")
      (node (ref "1") (pin "8") (pinfunction "KL_8") (pintype "passive"))
      (node (ref "R9") (pin "2") (pinfunction "2_2") (pintype "passive"))
      (node (ref "TP8") (pin "TP") (pinfunction "PP_TP") (pintype "input"))
    )
    (net (code "14") (name "Net-(1L-KL)") (class "Default")
      (node (ref "1") (pin "9") (pinfunction "KL_9") (pintype "passive"))
      (node (ref "D102") (pin "1") (pinfunction "+_1") (pintype "passive"))
      (node (ref "TP9") (pin "TP") (pinfunction "PP_TP") (pintype "input"))
      (node (ref "X101") (pin "17") (pinfunction "17_17") (pintype "passive"))
    )
    (net (code "15") (name "Net-(2B-KL)") (class "Default")
      (node (ref "2") (pin "10") (pinfunction "KL_10") (pintype "passive"))
      (node (ref "TP25") (pin "TP") (pinfunction "PP_TP") (pintype "input"))
      (node (ref "X101") (pin "15") (pinfunction "15_15") (pintype "passive"))
    )
    (net (code "16") (name "Net-(2C-KL)") (class "Default")
      (node (ref "2") (pin "11") (pinfunction "KL_11") (pintype "passive"))
      (node (ref "Q103") (pin "2") (pinfunction "C_2") (pintype "passive"))
      (node (ref "R119") (pin "1") (pinfunction "1_1") (pintype "passive"))
      (node (ref "TP26") (pin "TP") (pinfunction "PP_TP") (pintype "input"))
    )
    (net (code "17") (name "Net-(2D-KL)") (class "Default")
      (node (ref "2") (pin "12") (pinfunction "KL_12") (pintype "passive"))
      (node (ref "R146") (pin "1") (pinfunction "1_1") (pintype "passive"))
      (node (ref "TP13") (pin "TP") (pinfunction "PP_TP") (pintype "input"))
    )
    (net (code "18") (name "Net-(2E-KL)") (class "Default")
      (node (ref "2") (pin "2") (pinfunction "KL_2") (pintype "passive"))
      (node (ref "D109") (pin "2") (pinfunction "-_2") (pintype "passive"))
      (node (ref "LED102") (pin "K") (pinfunction "C_K") (pintype "passive"))
      (node (ref "TP16") (pin "TP") (pinfunction "PP_TP") (pintype "input"))
      (node (ref "X101") (pin "12") (pinfunction "12_12") (pintype "passive"))
    )
    (net (code "19") (name "Net-(2F-KL)") (class "Default")
      (node (ref "2") (pin "3") (pinfunction "KL_3") (pintype "passive"))
      (node (ref "D108") (pin "2") (pinfunction "-_2") (pintype "passive"))
      (node (ref "LED103") (pin "K") (pinfunction "C_K") (pintype "passive"))
      (node (ref "TP17") (pin "TP") (pinfunction "PP_TP") (pintype "input"))
      (node (ref "X101") (pin "11") (pinfunction "11_11") (pintype "passive"))
    )
    (net (code "20") (name "Net-(2G-KL)") (class "Default")
      (node (ref "2") (pin "4") (pinfunction "KL_4") (pintype "passive"))
      (node (ref "D107") (pin "2") (pinfunction "-_2") (pintype "passive"))
      (node (ref "LED104") (pin "K") (pinfunction "C_K") (pintype "passive"))
      (node (ref "TP18") (pin "TP") (pinfunction "PP_TP") (pintype "input"))
      (node (ref "X101") (pin "10") (pinfunction "10_10") (pintype "passive"))
    )
    (net (code "21") (name "Net-(2H-KL)") (class "Default")
      (node (ref "2") (pin "5") (pinfunction "KL_5") (pintype "passive"))
      (node (ref "D106") (pin "2") (pinfunction "-_2") (pintype "passive"))
      (node (ref "LED105") (pin "K") (pinfunction "C_K") (pintype "passive"))
      (node (ref "TP19") (pin "TP") (pinfunction "PP_TP") (pintype "input"))
      (node (ref "X101") (pin "9") (pinfunction "9_9") (pintype "passive"))
    )
    (net (code "22") (name "Net-(2I-KL)") (class "Default")
      (node (ref "2") (pin "6") (pinfunction "KL_6") (pintype "passive"))
      (node (ref "JP105") (pin "2") (pinfunction "2_2") (pintype "passive"))
      (node (ref "TP21") (pin "TP") (pinfunction "PP_TP") (pintype "input"))
    )
    (net (code "23") (name "Net-(2J-KL)") (class "Default")
      (node (ref "2") (pin "7") (pinfunction "KL_7") (pintype "passive"))
      (node (ref "LED101") (pin "A") (pinfunction "A_A") (pintype "passive"))
      (node (ref "TP22") (pin "TP") (pinfunction "PP_TP") (pintype "input"))
      (node (ref "X101") (pin "8") (pinfunction "8_8") (pintype "passive"))
    )
    (net (code "24") (name "Net-(2K-KL)") (class "Default")
      (node (ref "2") (pin "8") (pinfunction "KL_8") (pintype "passive"))
      (node (ref "D110") (pin "2") (pinfunction "-_2") (pintype "passive"))
      (node (ref "LED106") (pin "K") (pinfunction "C_K") (pintype "passive"))
      (node (ref "TP23") (pin "TP") (pinfunction "PP_TP") (pintype "input"))
      (node (ref "X101") (pin "14") (pinfunction "14_14") (pintype "passive"))
    )
    (net (code "25") (name "Net-(2L-KL)") (class "Default")
      (node (ref "2") (pin "9") (pinfunction "KL_9") (pintype "passive"))
      (node (ref "D107") (pin "1") (pinfunction "+_1") (pintype "passive"))
      (node (ref "D108") (pin "1") (pinfunction "+_1") (pintype "passive"))
      (node (ref "JP102") (pin "1") (pinfunction "1_1") (pintype "passive"))
      (node (ref "JP103") (pin "2") (pinfunction "2_2") (pintype "passive"))
      (node (ref "TP24") (pin "TP") (pinfunction "PP_TP") (pintype "input"))
    )
    (net (code "26") (name "Net-(3A-KL)") (class "Default")
      (node (ref "3") (pin "1") (pinfunction "KL_1") (pintype "passive"))
      (node (ref "D16") (pin "2") (pinfunction "-_2") (pintype "passive"))
      (node (ref "TP14") (pin "TP") (pinfunction "PP_TP") (pintype "input"))
    )
    (net (code "27") (name "Net-(3B-KL)") (class "Default")
      (node (ref "3") (pin "10") (pinfunction "KL_10") (pintype "passive"))
      (node (ref "D3") (pin "2") (pinfunction "-_2") (pintype "passive"))
      (node (ref "D5") (pin "2") (pinfunction "-_2") (pintype "passive"))
      (node (ref "JP5") (pin "1") (pinfunction "1_1") (pintype "passive"))
      (node (ref "SJ1") (pin "1") (pinfunction "1_1") (pintype "passive"))
      (node (ref "TP33") (pin "TP") (pinfunction "PP_TP") (pintype "input"))
    )
    (net (code "28") (name "Net-(3C-KL)") (class "Default")
      (node (ref "3") (pin "11") (pinfunction "KL_11") (pintype "passive"))
      (node (ref "D5") (pin "1") (pinfunction "+_1") (pintype "passive"))
      (node (ref "TP34") (pin "TP") (pinfunction "PP_TP") (pintype "input"))
      (node (ref "X1") (pin "19") (pinfunction "19_19") (pintype "passive"))
    )
    (net (code "29") (name "Net-(3E-KL)") (class "Default")
      (node (ref "3") (pin "2") (pinfunction "KL_2") (pintype "passive"))
      (node (ref "Q6") (pin "2") (pinfunction "C_2") (pintype "passive"))
      (node (ref "TP15") (pin "TP") (pinfunction "PP_TP") (pintype "input"))
    )
    (net (code "30") (name "Net-(3F-KL)") (class "Default")
      (node (ref "3") (pin "3") (pinfunction "KL_3") (pintype "passive"))
      (node (ref "IC3") (pin "11") (pinfunction "O6_11") (pintype "open_collector"))
      (node (ref "TP20") (pin "TP") (pinfunction "PP_TP") (pintype "input"))
    )
    (net (code "31") (name "Net-(3G-KL)") (class "Default")
      (node (ref "3") (pin "4") (pinfunction "KL_4") (pintype "passive"))
      (node (ref "IC3") (pin "10") (pinfunction "O7_10") (pintype "open_collector"))
      (node (ref "TP27") (pin "TP") (pinfunction "PP_TP") (pintype "input"))
    )
    (net (code "32") (name "Net-(3H-KL)") (class "Default")
      (node (ref "3") (pin "5") (pinfunction "KL_5") (pintype "passive"))
      (node (ref "IC3") (pin "12") (pinfunction "O5_12") (pintype "open_collector"))
      (node (ref "TP28") (pin "TP") (pinfunction "PP_TP") (pintype "input"))
    )
    (net (code "33") (name "Net-(3I-KL)") (class "Default")
      (node (ref "3") (pin "6") (pinfunction "KL_6") (pintype "passive"))
      (node (ref "IC3") (pin "13") (pinfunction "O4_13") (pintype "open_collector"))
      (node (ref "TP29") (pin "TP") (pinfunction "PP_TP") (pintype "input"))
    )
    (net (code "34") (name "Net-(3J-KL)") (class "Default")
      (node (ref "3") (pin "7") (pinfunction "KL_7") (pintype "passive"))
      (node (ref "IC3") (pin "14") (pinfunction "O3_14") (pintype "open_collector"))
      (node (ref "TP30") (pin "TP") (pinfunction "PP_TP") (pintype "input"))
    )
    (net (code "35") (name "Net-(3K-KL)") (class "Default")
      (node (ref "3") (pin "8") (pinfunction "KL_8") (pintype "passive"))
      (node (ref "R62") (pin "2") (pinfunction "2_2") (pintype "passive"))
      (node (ref "TP31") (pin "TP") (pinfunction "PP_TP") (pintype "input"))
    )
    (net (code "36") (name "Net-(3L-KL)") (class "Default")
      (node (ref "3") (pin "9") (pinfunction "KL_9") (pintype "passive"))
      (node (ref "D3") (pin "1") (pinfunction "+_1") (pintype "passive"))
      (node (ref "TP32") (pin "TP") (pinfunction "PP_TP") (pintype "input"))
      (node (ref "X1") (pin "17") (pinfunction "17_17") (pintype "passive"))
    )
    (net (code "37") (name "Net-(4B-KL)") (class "Default")
      (node (ref "4") (pin "10") (pinfunction "KL_10") (pintype "passive"))
      (node (ref "TP43") (pin "TP") (pinfunction "PP_TP") (pintype "input"))
      (node (ref "X1") (pin "15") (pinfunction "15_15") (pintype "passive"))
    )
    (net (code "38") (name "Net-(4C-KL)") (class "Default")
      (node (ref "4") (pin "11") (pinfunction "KL_11") (pintype "passive"))
      (node (ref "Q8") (pin "2") (pinfunction "C_2") (pintype "passive"))
      (node (ref "R48") (pin "1") (pinfunction "1_1") (pintype "passive"))
      (node (ref "TP44") (pin "TP") (pinfunction "PP_TP") (pintype "input"))
    )
    (net (code "39") (name "Net-(4D-KL)") (class "Default")
      (node (ref "4") (pin "12") (pinfunction "KL_12") (pintype "passive"))
      (node (ref "R49") (pin "1") (pinfunction "1_1") (pintype "passive"))
      (node (ref "TP46") (pin "TP") (pinfunction "PP_TP") (pintype "input"))
    )
    (net (code "40") (name "Net-(4E-KL)") (class "Default")
      (node (ref "4") (pin "2") (pinfunction "KL_2") (pintype "passive"))
      (node (ref "D9") (pin "2") (pinfunction "-_2") (pintype "passive"))
      (node (ref "LED1") (pin "K") (pinfunction "C_K") (pintype "passive"))
      (node (ref "TP35") (pin "TP") (pinfunction "PP_TP") (pintype "input"))
      (node (ref "X1") (pin "12") (pinfunction "12_12") (pintype "passive"))
    )
    (net (code "41") (name "Net-(4F-KL)") (class "Default")
      (node (ref "4") (pin "3") (pinfunction "KL_3") (pintype "passive"))
      (node (ref "D8") (pin "2") (pinfunction "-_2") (pintype "passive"))
      (node (ref "LED2") (pin "K") (pinfunction "C_K") (pintype "passive"))
      (node (ref "TP36") (pin "TP") (pinfunction "PP_TP") (pintype "input"))
      (node (ref "X1") (pin "11") (pinfunction "11_11") (pintype "passive"))
    )
    (net (code "42") (name "Net-(4G-KL)") (class "Default")
      (node (ref "4") (pin "4") (pinfunction "KL_4") (pintype "passive"))
      (node (ref "D7") (pin "2") (pinfunction "-_2") (pintype "passive"))
      (node (ref "LED3") (pin "K") (pinfunction "C_K") (pintype "passive"))
      (node (ref "TP37") (pin "TP") (pinfunction "PP_TP") (pintype "input"))
      (node (ref "X1") (pin "10") (pinfunction "10_10") (pintype "passive"))
    )
    (net (code "43") (name "Net-(4H-KL)") (class "Default")
      (node (ref "4") (pin "5") (pinfunction "KL_5") (pintype "passive"))
      (node (ref "D6") (pin "2") (pinfunction "-_2") (pintype "passive"))
      (node (ref "LED4") (pin "K") (pinfunction "C_K") (pintype "passive"))
      (node (ref "TP38") (pin "TP") (pinfunction "PP_TP") (pintype "input"))
      (node (ref "X1") (pin "9") (pinfunction "9_9") (pintype "passive"))
    )
    (net (code "44") (name "Net-(4I-KL)") (class "Default")
      (node (ref "4") (pin "6") (pinfunction "KL_6") (pintype "passive"))
      (node (ref "JP2") (pin "2") (pinfunction "2_2") (pintype "passive"))
      (node (ref "TP39") (pin "TP") (pinfunction "PP_TP") (pintype "input"))
    )
    (net (code "45") (name "Net-(4J-KL)") (class "Default")
      (node (ref "4") (pin "7") (pinfunction "KL_7") (pintype "passive"))
      (node (ref "LED5") (pin "A") (pinfunction "A_A") (pintype "passive"))
      (node (ref "TP40") (pin "TP") (pinfunction "PP_TP") (pintype "input"))
      (node (ref "X1") (pin "8") (pinfunction "8_8") (pintype "passive"))
    )
    (net (code "46") (name "Net-(4K-KL)") (class "Default")
      (node (ref "4") (pin "8") (pinfunction "KL_8") (pintype "passive"))
      (node (ref "D10") (pin "2") (pinfunction "-_2") (pintype "passive"))
      (node (ref "LED6") (pin "K") (pinfunction "C_K") (pintype "passive"))
      (node (ref "TP41") (pin "TP") (pinfunction "PP_TP") (pintype "input"))
      (node (ref "X1") (pin "14") (pinfunction "14_14") (pintype "passive"))
    )
    (net (code "47") (name "Net-(4L-KL)") (class "Default")
      (node (ref "4") (pin "9") (pinfunction "KL_9") (pintype "passive"))
      (node (ref "D7") (pin "1") (pinfunction "+_1") (pintype "passive"))
      (node (ref "D8") (pin "1") (pinfunction "+_1") (pintype "passive"))
      (node (ref "JP3") (pin "1") (pinfunction "1_1") (pintype "passive"))
      (node (ref "JP4") (pin "2") (pinfunction "2_2") (pintype "passive"))
      (node (ref "TP42") (pin "TP") (pinfunction "PP_TP") (pintype "input"))
    )
    (net (code "48") (name "Net-(5A-KL)") (class "Default")
      (node (ref "5") (pin "1") (pinfunction "KL_1") (pintype "passive"))
      (node (ref "D30") (pin "2") (pinfunction "-_2") (pintype "passive"))
      (node (ref "TP47") (pin "TP") (pinfunction "PP_TP") (pintype "input"))
    )
    (net (code "49") (name "Net-(5B-KL)") (class "Default")
      (node (ref "5") (pin "10") (pinfunction "KL_10") (pintype "passive"))
      (node (ref "D18") (pin "2") (pinfunction "-_2") (pintype "passive"))
      (node (ref "D19") (pin "2") (pinfunction "-_2") (pintype "passive"))
      (node (ref "JP10") (pin "1") (pinfunction "1_1") (pintype "passive"))
      (node (ref "SJ2") (pin "1") (pinfunction "1_1") (pintype "passive"))
      (node (ref "TP56") (pin "TP") (pinfunction "PP_TP") (pintype "input"))
    )
    (net (code "50") (name "Net-(5C-KL)") (class "Default")
      (node (ref "5") (pin "11") (pinfunction "KL_11") (pintype "passive"))
      (node (ref "D19") (pin "1") (pinfunction "+_1") (pintype "passive"))
      (node (ref "TP57") (pin "TP") (pinfunction "PP_TP") (pintype "input"))
      (node (ref "X4") (pin "19") (pinfunction "19_19") (pintype "passive"))
    )
    (net (code "51") (name "Net-(5E-KL)") (class "Default")
      (node (ref "5") (pin "2") (pinfunction "KL_2") (pintype "passive"))
      (node (ref "Q16") (pin "2") (pinfunction "C_2") (pintype "passive"))
      (node (ref "TP48") (pin "TP") (pinfunction "PP_TP") (pintype "input"))
    )
    (net (code "52") (name "Net-(5F-KL)") (class "Default")
      (node (ref "5") (pin "3") (pinfunction "KL_3") (pintype "passive"))
      (node (ref "IC12") (pin "11") (pinfunction "O6_11") (pintype "open_collector"))
      (node (ref "TP49") (pin "TP") (pinfunction "PP_TP") (pintype "input"))
    )
    (net (code "53") (name "Net-(5G-KL)") (class "Default")
      (node (ref "5") (pin "4") (pinfunction "KL_4") (pintype "passive"))
      (node (ref "IC12") (pin "10") (pinfunction "O7_10") (pintype "open_collector"))
      (node (ref "TP50") (pin "TP") (pinfunction "PP_TP") (pintype "input"))
    )
    (net (code "54") (name "Net-(5H-KL)") (class "Default")
      (node (ref "5") (pin "5") (pinfunction "KL_5") (pintype "passive"))
      (node (ref "IC12") (pin "12") (pinfunction "O5_12") (pintype "open_collector"))
      (node (ref "TP51") (pin "TP") (pinfunction "PP_TP") (pintype "input"))
    )
    (net (code "55") (name "Net-(5I-KL)") (class "Default")
      (node (ref "5") (pin "6") (pinfunction "KL_6") (pintype "passive"))
      (node (ref "IC12") (pin "13") (pinfunction "O4_13") (pintype "open_collector"))
      (node (ref "TP52") (pin "TP") (pinfunction "PP_TP") (pintype "input"))
    )
    (net (code "56") (name "Net-(5J-KL)") (class "Default")
      (node (ref "5") (pin "7") (pinfunction "KL_7") (pintype "passive"))
      (node (ref "IC12") (pin "14") (pinfunction "O3_14") (pintype "open_collector"))
      (node (ref "TP53") (pin "TP") (pinfunction "PP_TP") (pintype "input"))
    )
    (net (code "57") (name "Net-(5K-KL)") (class "Default")
      (node (ref "5") (pin "8") (pinfunction "KL_8") (pintype "passive"))
      (node (ref "R161") (pin "2") (pinfunction "2_2") (pintype "passive"))
      (node (ref "TP54") (pin "TP") (pinfunction "PP_TP") (pintype "input"))
    )
    (net (code "58") (name "Net-(5L-KL)") (class "Default")
      (node (ref "5") (pin "9") (pinfunction "KL_9") (pintype "passive"))
      (node (ref "D18") (pin "1") (pinfunction "+_1") (pintype "passive"))
      (node (ref "TP55") (pin "TP") (pinfunction "PP_TP") (pintype "input"))
      (node (ref "X4") (pin "17") (pinfunction "17_17") (pintype "passive"))
    )
    (net (code "59") (name "Net-(6B-KL)") (class "Default")
      (node (ref "6") (pin "10") (pinfunction "KL_10") (pintype "passive"))
      (node (ref "TP66") (pin "TP") (pinfunction "PP_TP") (pintype "input"))
      (node (ref "X4") (pin "15") (pinfunction "15_15") (pintype "passive"))
    )
    (net (code "60") (name "Net-(6C-KL)") (class "Default")
      (node (ref "6") (pin "11") (pinfunction "KL_11") (pintype "passive"))
      (node (ref "Q18") (pin "2") (pinfunction "C_2") (pintype "passive"))
      (node (ref "R147") (pin "1") (pinfunction "1_1") (pintype "passive"))
      (node (ref "TP67") (pin "TP") (pinfunction "PP_TP") (pintype "input"))
    )
    (net (code "61") (name "Net-(6D-KL)") (class "Default")
      (node (ref "6") (pin "12") (pinfunction "KL_12") (pintype "passive"))
      (node (ref "R148") (pin "1") (pinfunction "1_1") (pintype "passive"))
      (node (ref "TP69") (pin "TP") (pinfunction "PP_TP") (pintype "input"))
    )
    (net (code "62") (name "Net-(6E-KL)") (class "Default")
      (node (ref "6") (pin "2") (pinfunction "KL_2") (pintype "passive"))
      (node (ref "D23") (pin "2") (pinfunction "-_2") (pintype "passive"))
      (node (ref "LED7") (pin "K") (pinfunction "C_K") (pintype "passive"))
      (node (ref "TP58") (pin "TP") (pinfunction "PP_TP") (pintype "input"))
      (node (ref "X4") (pin "12") (pinfunction "12_12") (pintype "passive"))
    )
    (net (code "63") (name "Net-(6F-KL)") (class "Default")
      (node (ref "6") (pin "3") (pinfunction "KL_3") (pintype "passive"))
      (node (ref "D22") (pin "2") (pinfunction "-_2") (pintype "passive"))
      (node (ref "LED8") (pin "K") (pinfunction "C_K") (pintype "passive"))
      (node (ref "TP59") (pin "TP") (pinfunction "PP_TP") (pintype "input"))
      (node (ref "X4") (pin "11") (pinfunction "11_11") (pintype "passive"))
    )
    (net (code "64") (name "Net-(6G-KL)") (class "Default")
      (node (ref "6") (pin "4") (pinfunction "KL_4") (pintype "passive"))
      (node (ref "D21") (pin "2") (pinfunction "-_2") (pintype "passive"))
      (node (ref "LED9") (pin "K") (pinfunction "C_K") (pintype "passive"))
      (node (ref "TP60") (pin "TP") (pinfunction "PP_TP") (pintype "input"))
      (node (ref "X4") (pin "10") (pinfunction "10_10") (pintype "passive"))
    )
    (net (code "65") (name "Net-(6H-KL)") (class "Default")
      (node (ref "6") (pin "5") (pinfunction "KL_5") (pintype "passive"))
      (node (ref "D20") (pin "2") (pinfunction "-_2") (pintype "passive"))
      (node (ref "LED10") (pin "K") (pinfunction "C_K") (pintype "passive"))
      (node (ref "TP61") (pin "TP") (pinfunction "PP_TP") (pintype "input"))
      (node (ref "X4") (pin "9") (pinfunction "9_9") (pintype "passive"))
    )
    (net (code "66") (name "Net-(6I-KL)") (class "Default")
      (node (ref "6") (pin "6") (pinfunction "KL_6") (pintype "passive"))
      (node (ref "JP7") (pin "2") (pinfunction "2_2") (pintype "passive"))
      (node (ref "TP62") (pin "TP") (pinfunction "PP_TP") (pintype "input"))
    )
    (net (code "67") (name "Net-(6J-KL)") (class "Default")
      (node (ref "6") (pin "7") (pinfunction "KL_7") (pintype "passive"))
      (node (ref "LED11") (pin "A") (pinfunction "A_A") (pintype "passive"))
      (node (ref "TP63") (pin "TP") (pinfunction "PP_TP") (pintype "input"))
      (node (ref "X4") (pin "8") (pinfunction "8_8") (pintype "passive"))
    )
    (net (code "68") (name "Net-(6K-KL)") (class "Default")
      (node (ref "6") (pin "8") (pinfunction "KL_8") (pintype "passive"))
      (node (ref "D24") (pin "2") (pinfunction "-_2") (pintype "passive"))
      (node (ref "LED12") (pin "K") (pinfunction "C_K") (pintype "passive"))
      (node (ref "TP64") (pin "TP") (pinfunction "PP_TP") (pintype "input"))
      (node (ref "X4") (pin "14") (pinfunction "14_14") (pintype "passive"))
    )
    (net (code "69") (name "Net-(6L-KL)") (class "Default")
      (node (ref "6") (pin "9") (pinfunction "KL_9") (pintype "passive"))
      (node (ref "D21") (pin "1") (pinfunction "+_1") (pintype "passive"))
      (node (ref "D22") (pin "1") (pinfunction "+_1") (pintype "passive"))
      (node (ref "JP8") (pin "1") (pinfunction "1_1") (pintype "passive"))
      (node (ref "JP9") (pin "2") (pinfunction "2_2") (pintype "passive"))
      (node (ref "TP65") (pin "TP") (pinfunction "PP_TP") (pintype "input"))
    )
    (net (code "70") (name "Net-(7A-KL)") (class "Default")
      (node (ref "7") (pin "1") (pinfunction "KL_1") (pintype "passive"))
      (node (ref "D44") (pin "2") (pinfunction "-_2") (pintype "passive"))
      (node (ref "TP70") (pin "TP") (pinfunction "PP_TP") (pintype "input"))
    )
    (net (code "71") (name "Net-(7B-KL)") (class "Default")
      (node (ref "7") (pin "10") (pinfunction "KL_10") (pintype "passive"))
      (node (ref "D32") (pin "2") (pinfunction "-_2") (pintype "passive"))
      (node (ref "D33") (pin "2") (pinfunction "-_2") (pintype "passive"))
      (node (ref "JP15") (pin "1") (pinfunction "1_1") (pintype "passive"))
      (node (ref "SJ3") (pin "1") (pinfunction "1_1") (pintype "passive"))
      (node (ref "TP79") (pin "TP") (pinfunction "PP_TP") (pintype "input"))
    )
    (net (code "72") (name "Net-(7C-KL)") (class "Default")
      (node (ref "7") (pin "11") (pinfunction "KL_11") (pintype "passive"))
      (node (ref "D33") (pin "1") (pinfunction "+_1") (pintype "passive"))
      (node (ref "TP80") (pin "TP") (pinfunction "PP_TP") (pintype "input"))
      (node (ref "X7") (pin "19") (pinfunction "19_19") (pintype "passive"))
    )
    (net (code "73") (name "Net-(7E-KL)") (class "Default")
      (node (ref "7") (pin "2") (pinfunction "KL_2") (pintype "passive"))
      (node (ref "Q26") (pin "2") (pinfunction "C_2") (pintype "passive"))
      (node (ref "TP71") (pin "TP") (pinfunction "PP_TP") (pintype "input"))
    )
    (net (code "74") (name "Net-(7F-KL)") (class "Default")
      (node (ref "7") (pin "3") (pinfunction "KL_3") (pintype "passive"))
      (node (ref "IC21") (pin "11") (pinfunction "O6_11") (pintype "open_collector"))
      (node (ref "TP72") (pin "TP") (pinfunction "PP_TP") (pintype "input"))
    )
    (net (code "75") (name "Net-(7G-KL)") (class "Default")
      (node (ref "7") (pin "4") (pinfunction "KL_4") (pintype "passive"))
      (node (ref "IC21") (pin "10") (pinfunction "O7_10") (pintype "open_collector"))
      (node (ref "TP73") (pin "TP") (pinfunction "PP_TP") (pintype "input"))
    )
    (net (code "76") (name "Net-(7H-KL)") (class "Default")
      (node (ref "7") (pin "5") (pinfunction "KL_5") (pintype "passive"))
      (node (ref "IC21") (pin "12") (pinfunction "O5_12") (pintype "open_collector"))
      (node (ref "TP74") (pin "TP") (pinfunction "PP_TP") (pintype "input"))
    )
    (net (code "77") (name "Net-(7I-KL)") (class "Default")
      (node (ref "7") (pin "6") (pinfunction "KL_6") (pintype "passive"))
      (node (ref "IC21") (pin "13") (pinfunction "O4_13") (pintype "open_collector"))
      (node (ref "TP75") (pin "TP") (pinfunction "PP_TP") (pintype "input"))
    )
    (net (code "78") (name "Net-(7J-KL)") (class "Default")
      (node (ref "7") (pin "7") (pinfunction "KL_7") (pintype "passive"))
      (node (ref "IC21") (pin "14") (pinfunction "O3_14") (pintype "open_collector"))
      (node (ref "TP76") (pin "TP") (pinfunction "PP_TP") (pintype "input"))
    )
    (net (code "79") (name "Net-(7K-KL)") (class "Default")
      (node (ref "7") (pin "8") (pinfunction "KL_8") (pintype "passive"))
      (node (ref "R216") (pin "2") (pinfunction "2_2") (pintype "passive"))
      (node (ref "TP77") (pin "TP") (pinfunction "PP_TP") (pintype "input"))
    )
    (net (code "80") (name "Net-(7L-KL)") (class "Default")
      (node (ref "7") (pin "9") (pinfunction "KL_9") (pintype "passive"))
      (node (ref "D32") (pin "1") (pinfunction "+_1") (pintype "passive"))
      (node (ref "TP78") (pin "TP") (pinfunction "PP_TP") (pintype "input"))
      (node (ref "X7") (pin "17") (pinfunction "17_17") (pintype "passive"))
    )
    (net (code "81") (name "Net-(8B-KL)") (class "Default")
      (node (ref "8") (pin "10") (pinfunction "KL_10") (pintype "passive"))
      (node (ref "TP89") (pin "TP") (pinfunction "PP_TP") (pintype "input"))
      (node (ref "X7") (pin "15") (pinfunction "15_15") (pintype "passive"))
    )
    (net (code "82") (name "Net-(8C-KL)") (class "Default")
      (node (ref "8") (pin "11") (pinfunction "KL_11") (pintype "passive"))
      (node (ref "Q28") (pin "2") (pinfunction "C_2") (pintype "passive"))
      (node (ref "R202") (pin "1") (pinfunction "1_1") (pintype "passive"))
      (node (ref "TP90") (pin "TP") (pinfunction "PP_TP") (pintype "input"))
    )
    (net (code "83") (name "Net-(8D-KL)") (class "Default")
      (node (ref "8") (pin "12") (pinfunction "KL_12") (pintype "passive"))
      (node (ref "R203") (pin "1") (pinfunction "1_1") (pintype "passive"))
      (node (ref "TP92") (pin "TP") (pinfunction "PP_TP") (pintype "input"))
    )
    (net (code "84") (name "Net-(8E-KL)") (class "Default")
      (node (ref "8") (pin "2") (pinfunction "KL_2") (pintype "passive"))
      (node (ref "D37") (pin "2") (pinfunction "-_2") (pintype "passive"))
      (node (ref "LED13") (pin "K") (pinfunction "C_K") (pintype "passive"))
      (node (ref "TP81") (pin "TP") (pinfunction "PP_TP") (pintype "input"))
      (node (ref "X7") (pin "12") (pinfunction "12_12") (pintype "passive"))
    )
    (net (code "85") (name "Net-(8F-KL)") (class "Default")
      (node (ref "8") (pin "3") (pinfunction "KL_3") (pintype "passive"))
      (node (ref "D36") (pin "2") (pinfunction "-_2") (pintype "passive"))
      (node (ref "LED14") (pin "K") (pinfunction "C_K") (pintype "passive"))
      (node (ref "TP82") (pin "TP") (pinfunction "PP_TP") (pintype "input"))
      (node (ref "X7") (pin "11") (pinfunction "11_11") (pintype "passive"))
    )
    (net (code "86") (name "Net-(8G-KL)") (class "Default")
      (node (ref "8") (pin "4") (pinfunction "KL_4") (pintype "passive"))
      (node (ref "D35") (pin "2") (pinfunction "-_2") (pintype "passive"))
      (node (ref "LED15") (pin "K") (pinfunction "C_K") (pintype "passive"))
      (node (ref "TP83") (pin "TP") (pinfunction "PP_TP") (pintype "input"))
      (node (ref "X7") (pin "10") (pinfunction "10_10") (pintype "passive"))
    )
    (net (code "87") (name "Net-(8H-KL)") (class "Default")
      (node (ref "8") (pin "5") (pinfunction "KL_5") (pintype "passive"))
      (node (ref "D34") (pin "2") (pinfunction "-_2") (pintype "passive"))
      (node (ref "LED16") (pin "K") (pinfunction "C_K") (pintype "passive"))
      (node (ref "TP84") (pin "TP") (pinfunction "PP_TP") (pintype "input"))
      (node (ref "X7") (pin "9") (pinfunction "9_9") (pintype "passive"))
    )
    (net (code "88") (name "Net-(8I-KL)") (class "Default")
      (node (ref "8") (pin "6") (pinfunction "KL_6") (pintype "passive"))
      (node (ref "JP12") (pin "2") (pinfunction "2_2") (pintype "passive"))
      (node (ref "TP85") (pin "TP") (pinfunction "PP_TP") (pintype "input"))
    )
    (net (code "89") (name "Net-(8J-KL)") (class "Default")
      (node (ref "8") (pin "7") (pinfunction "KL_7") (pintype "passive"))
      (node (ref "LED17") (pin "A") (pinfunction "A_A") (pintype "passive"))
      (node (ref "TP86") (pin "TP") (pinfunction "PP_TP") (pintype "input"))
      (node (ref "X7") (pin "8") (pinfunction "8_8") (pintype "passive"))
    )
    (net (code "90") (name "Net-(8K-KL)") (class "Default")
      (node (ref "8") (pin "8") (pinfunction "KL_8") (pintype "passive"))
      (node (ref "D38") (pin "2") (pinfunction "-_2") (pintype "passive"))
      (node (ref "LED18") (pin "K") (pinfunction "C_K") (pintype "passive"))
      (node (ref "TP87") (pin "TP") (pinfunction "PP_TP") (pintype "input"))
      (node (ref "X7") (pin "14") (pinfunction "14_14") (pintype "passive"))
    )
    (net (code "91") (name "Net-(8L-KL)") (class "Default")
      (node (ref "8") (pin "9") (pinfunction "KL_9") (pintype "passive"))
      (node (ref "D35") (pin "1") (pinfunction "+_1") (pintype "passive"))
      (node (ref "D36") (pin "1") (pinfunction "+_1") (pintype "passive"))
      (node (ref "JP13") (pin "1") (pinfunction "1_1") (pintype "passive"))
      (node (ref "JP14") (pin "2") (pinfunction "2_2") (pintype "passive"))
      (node (ref "TP88") (pin "TP") (pinfunction "PP_TP") (pintype "input"))
    )
    (net (code "92") (name "Net-(9A-KL)") (class "Default")
      (node (ref "9") (pin "1") (pinfunction "KL_1") (pintype "passive"))
      (node (ref "D58") (pin "2") (pinfunction "-_2") (pintype "passive"))
      (node (ref "TP93") (pin "TP") (pinfunction "PP_TP") (pintype "input"))
    )
    (net (code "93") (name "Net-(9B-KL)") (class "Default")
      (node (ref "9") (pin "10") (pinfunction "KL_10") (pintype "passive"))
      (node (ref "D46") (pin "2") (pinfunction "-_2") (pintype "passive"))
      (node (ref "D47") (pin "2") (pinfunction "-_2") (pintype "passive"))
      (node (ref "JP20") (pin "1") (pinfunction "1_1") (pintype "passive"))
      (node (ref "SJ4") (pin "1") (pinfunction "1_1") (pintype "passive"))
      (node (ref "TP102") (pin "TP") (pinfunction "PP_TP") (pintype "input"))
    )
    (net (code "94") (name "Net-(9C-KL)") (class "Default")
      (node (ref "9") (pin "11") (pinfunction "KL_11") (pintype "passive"))
      (node (ref "D47") (pin "1") (pinfunction "+_1") (pintype "passive"))
      (node (ref "TP103") (pin "TP") (pinfunction "PP_TP") (pintype "input"))
      (node (ref "X10") (pin "19") (pinfunction "19_19") (pintype "passive"))
    )
    (net (code "95") (name "Net-(9E-KL)") (class "Default")
      (node (ref "9") (pin "2") (pinfunction "KL_2") (pintype "passive"))
      (node (ref "Q36") (pin "2") (pinfunction "C_2") (pintype "passive"))
      (node (ref "TP94") (pin "TP") (pinfunction "PP_TP") (pintype "input"))
    )
    (net (code "96") (name "Net-(9F-KL)") (class "Default")
      (node (ref "9") (pin "3") (pinfunction "KL_3") (pintype "passive"))
      (node (ref "IC30") (pin "11") (pinfunction "O6_11") (pintype "open_collector"))
      (node (ref "TP95") (pin "TP") (pinfunction "PP_TP") (pintype "input"))
    )
    (net (code "97") (name "Net-(9G-KL)") (class "Default")
      (node (ref "9") (pin "4") (pinfunction "KL_4") (pintype "passive"))
      (node (ref "IC30") (pin "10") (pinfunction "O7_10") (pintype "open_collector"))
      (node (ref "TP96") (pin "TP") (pinfunction "PP_TP") (pintype "input"))
    )
    (net (code "98") (name "Net-(9H-KL)") (class "Default")
      (node (ref "9") (pin "5") (pinfunction "KL_5") (pintype "passive"))
      (node (ref "IC30") (pin "12") (pinfunction "O5_12") (pintype "open_collector"))
      (node (ref "TP97") (pin "TP") (pinfunction "PP_TP") (pintype "input"))
    )
    (net (code "99") (name "Net-(9I-KL)") (class "Default")
      (node (ref "9") (pin "6") (pinfunction "KL_6") (pintype "passive"))
      (node (ref "IC30") (pin "13") (pinfunction "O4_13") (pintype "open_collector"))
      (node (ref "TP98") (pin "TP") (pinfunction "PP_TP") (pintype "input"))
    )
    (net (code "100") (name "Net-(9J-KL)") (class "Default")
      (node (ref "9") (pin "7") (pinfunction "KL_7") (pintype "passive"))
      (node (ref "IC30") (pin "14") (pinfunction "O3_14") (pintype "open_collector"))
      (node (ref "TP99") (pin "TP") (pinfunction "PP_TP") (pintype "input"))
    )
    (net (code "101") (name "Net-(9K-KL)") (class "Default")
      (node (ref "9") (pin "8") (pinfunction "KL_8") (pintype "passive"))
      (node (ref "R271") (pin "2") (pinfunction "2_2") (pintype "passive"))
      (node (ref "TP100") (pin "TP") (pinfunction "PP_TP") (pintype "input"))
    )
    (net (code "102") (name "Net-(9L-KL)") (class "Default")
      (node (ref "9") (pin "9") (pinfunction "KL_9") (pintype "passive"))
      (node (ref "D46") (pin "1") (pinfunction "+_1") (pintype "passive"))
      (node (ref "TP101") (pin "TP") (pinfunction "PP_TP") (pintype "input"))
      (node (ref "X10") (pin "17") (pinfunction "17_17") (pintype "passive"))
    )
    (net (code "103") (name "Net-(10B-KL)") (class "Default")
      (node (ref "10") (pin "10") (pinfunction "KL_10") (pintype "passive"))
      (node (ref "TP112") (pin "TP") (pinfunction "PP_TP") (pintype "input"))
      (node (ref "X10") (pin "15") (pinfunction "15_15") (pintype "passive"))
    )
    (net (code "104") (name "Net-(10C-KL)") (class "Default")
      (node (ref "10") (pin "11") (pinfunction "KL_11") (pintype "passive"))
      (node (ref "Q38") (pin "2") (pinfunction "C_2") (pintype "passive"))
      (node (ref "R257") (pin "1") (pinfunction "1_1") (pintype "passive"))
      (node (ref "TP113") (pin "TP") (pinfunction "PP_TP") (pintype "input"))
    )
    (net (code "105") (name "Net-(10D-KL)") (class "Default")
      (node (ref "10") (pin "12") (pinfunction "KL_12") (pintype "passive"))
      (node (ref "R258") (pin "1") (pinfunction "1_1") (pintype "passive"))
      (node (ref "TP115") (pin "TP") (pinfunction "PP_TP") (pintype "input"))
    )
    (net (code "106") (name "Net-(10E-KL)") (class "Default")
      (node (ref "10") (pin "2") (pinfunction "KL_2") (pintype "passive"))
      (node (ref "D51") (pin "2") (pinfunction "-_2") (pintype "passive"))
      (node (ref "LED19") (pin "K") (pinfunction "C_K") (pintype "passive"))
      (node (ref "TP104") (pin "TP") (pinfunction "PP_TP") (pintype "input"))
      (node (ref "X10") (pin "12") (pinfunction "12_12") (pintype "passive"))
    )
    (net (code "107") (name "Net-(10F-KL)") (class "Default")
      (node (ref "10") (pin "3") (pinfunction "KL_3") (pintype "passive"))
      (node (ref "D50") (pin "2") (pinfunction "-_2") (pintype "passive"))
      (node (ref "LED20") (pin "K") (pinfunction "C_K") (pintype "passive"))
      (node (ref "TP105") (pin "TP") (pinfunction "PP_TP") (pintype "input"))
      (node (ref "X10") (pin "11") (pinfunction "11_11") (pintype "passive"))
    )
    (net (code "108") (name "Net-(10G-KL)") (class "Default")
      (node (ref "10") (pin "4") (pinfunction "KL_4") (pintype "passive"))
      (node (ref "D49") (pin "2") (pinfunction "-_2") (pintype "passive"))
      (node (ref "LED21") (pin "K") (pinfunction "C_K") (pintype "passive"))
      (node (ref "TP106") (pin "TP") (pinfunction "PP_TP") (pintype "input"))
      (node (ref "X10") (pin "10") (pinfunction "10_10") (pintype "passive"))
    )
    (net (code "109") (name "Net-(10H-KL)") (class "Default")
      (node (ref "10") (pin "5") (pinfunction "KL_5") (pintype "passive"))
      (node (ref "D48") (pin "2") (pinfunction "-_2") (pintype "passive"))
      (node (ref "LED22") (pin "K") (pinfunction "C_K") (pintype "passive"))
      (node (ref "TP107") (pin "TP") (pinfunction "PP_TP") (pintype "input"))
      (node (ref "X10") (pin "9") (pinfunction "9_9") (pintype "passive"))
    )
    (net (code "110") (name "Net-(10I-KL)") (class "Default")
      (node (ref "10") (pin "6") (pinfunction "KL_6") (pintype "passive"))
      (node (ref "JP17") (pin "2") (pinfunction "2_2") (pintype "passive"))
      (node (ref "TP108") (pin "TP") (pinfunction "PP_TP") (pintype "input"))
    )
    (net (code "111") (name "Net-(10J-KL)") (class "Default")
      (node (ref "10") (pin "7") (pinfunction "KL_7") (pintype "passive"))
      (node (ref "LED23") (pin "A") (pinfunction "A_A") (pintype "passive"))
      (node (ref "TP109") (pin "TP") (pinfunction "PP_TP") (pintype "input"))
      (node (ref "X10") (pin "8") (pinfunction "8_8") (pintype "passive"))
    )
    (net (code "112") (name "Net-(10K-KL)") (class "Default")
      (node (ref "10") (pin "8") (pinfunction "KL_8") (pintype "passive"))
      (node (ref "D52") (pin "2") (pinfunction "-_2") (pintype "passive"))
      (node (ref "LED24") (pin "K") (pinfunction "C_K") (pintype "passive"))
      (node (ref "TP110") (pin "TP") (pinfunction "PP_TP") (pintype "input"))
      (node (ref "X10") (pin "14") (pinfunction "14_14") (pintype "passive"))
    )
    (net (code "113") (name "Net-(10L-KL)") (class "Default")
      (node (ref "10") (pin "9") (pinfunction "KL_9") (pintype "passive"))
      (node (ref "D49") (pin "1") (pinfunction "+_1") (pintype "passive"))
      (node (ref "D50") (pin "1") (pinfunction "+_1") (pintype "passive"))
      (node (ref "JP18") (pin "1") (pinfunction "1_1") (pintype "passive"))
      (node (ref "JP19") (pin "2") (pinfunction "2_2") (pintype "passive"))
      (node (ref "TP111") (pin "TP") (pinfunction "PP_TP") (pintype "input"))
    )
    (net (code "114") (name "Net-(11A-KL)") (class "Default")
      (node (ref "11") (pin "1") (pinfunction "KL_1") (pintype "passive"))
      (node (ref "D72") (pin "2") (pinfunction "-_2") (pintype "passive"))
      (node (ref "TP116") (pin "TP") (pinfunction "PP_TP") (pintype "input"))
    )
    (net (code "115") (name "Net-(11B-KL)") (class "Default")
      (node (ref "11") (pin "10") (pinfunction "KL_10") (pintype "passive"))
      (node (ref "D60") (pin "2") (pinfunction "-_2") (pintype "passive"))
      (node (ref "D61") (pin "2") (pinfunction "-_2") (pintype "passive"))
      (node (ref "JP25") (pin "1") (pinfunction "1_1") (pintype "passive"))
      (node (ref "SJ5") (pin "1") (pinfunction "1_1") (pintype "passive"))
      (node (ref "TP125") (pin "TP") (pinfunction "PP_TP") (pintype "input"))
    )
    (net (code "116") (name "Net-(11C-KL)") (class "Default")
      (node (ref "11") (pin "11") (pinfunction "KL_11") (pintype "passive"))
      (node (ref "D61") (pin "1") (pinfunction "+_1") (pintype "passive"))
      (node (ref "TP126") (pin "TP") (pinfunction "PP_TP") (pintype "input"))
      (node (ref "X13") (pin "19") (pinfunction "19_19") (pintype "passive"))
    )
    (net (code "117") (name "Net-(11E-KL)") (class "Default")
      (node (ref "11") (pin "2") (pinfunction "KL_2") (pintype "passive"))
      (node (ref "Q46") (pin "2") (pinfunction "C_2") (pintype "passive"))
      (node (ref "TP117") (pin "TP") (pinfunction "PP_TP") (pintype "input"))
    )
    (net (code "118") (name "Net-(11F-KL)") (class "Default")
      (node (ref "11") (pin "3") (pinfunction "KL_3") (pintype "passive"))
      (node (ref "IC39") (pin "11") (pinfunction "O6_11") (pintype "open_collector"))
      (node (ref "TP118") (pin "TP") (pinfunction "PP_TP") (pintype "input"))
    )
    (net (code "119") (name "Net-(11G-KL)") (class "Default")
      (node (ref "11") (pin "4") (pinfunction "KL_4") (pintype "passive"))
      (node (ref "IC39") (pin "10") (pinfunction "O7_10") (pintype "open_collector"))
      (node (ref "TP119") (pin "TP") (pinfunction "PP_TP") (pintype "input"))
    )
    (net (code "120") (name "Net-(11H-KL)") (class "Default")
      (node (ref "11") (pin "5") (pinfunction "KL_5") (pintype "passive"))
      (node (ref "IC39") (pin "12") (pinfunction "O5_12") (pintype "open_collector"))
      (node (ref "TP120") (pin "TP") (pinfunction "PP_TP") (pintype "input"))
    )
    (net (code "121") (name "Net-(11I-KL)") (class "Default")
      (node (ref "11") (pin "6") (pinfunction "KL_6") (pintype "passive"))
      (node (ref "IC39") (pin "13") (pinfunction "O4_13") (pintype "open_collector"))
      (node (ref "TP121") (pin "TP") (pinfunction "PP_TP") (pintype "input"))
    )
    (net (code "122") (name "Net-(11J-KL)") (class "Default")
      (node (ref "11") (pin "7") (pinfunction "KL_7") (pintype "passive"))
      (node (ref "IC39") (pin "14") (pinfunction "O3_14") (pintype "open_collector"))
      (node (ref "TP122") (pin "TP") (pinfunction "PP_TP") (pintype "input"))
    )
    (net (code "123") (name "Net-(11K-KL)") (class "Default")
      (node (ref "11") (pin "8") (pinfunction "KL_8") (pintype "passive"))
      (node (ref "R326") (pin "2") (pinfunction "2_2") (pintype "passive"))
      (node (ref "TP123") (pin "TP") (pinfunction "PP_TP") (pintype "input"))
    )
    (net (code "124") (name "Net-(11L-KL)") (class "Default")
      (node (ref "11") (pin "9") (pinfunction "KL_9") (pintype "passive"))
      (node (ref "D60") (pin "1") (pinfunction "+_1") (pintype "passive"))
      (node (ref "TP124") (pin "TP") (pinfunction "PP_TP") (pintype "input"))
      (node (ref "X13") (pin "17") (pinfunction "17_17") (pintype "passive"))
    )
    (net (code "125") (name "Net-(12B-KL)") (class "Default")
      (node (ref "12") (pin "10") (pinfunction "KL_10") (pintype "passive"))
      (node (ref "TP135") (pin "TP") (pinfunction "PP_TP") (pintype "input"))
      (node (ref "X13") (pin "15") (pinfunction "15_15") (pintype "passive"))
    )
    (net (code "126") (name "Net-(12C-KL)") (class "Default")
      (node (ref "12") (pin "11") (pinfunction "KL_11") (pintype "passive"))
      (node (ref "Q48") (pin "2") (pinfunction "C_2") (pintype "passive"))
      (node (ref "R312") (pin "1") (pinfunction "1_1") (pintype "passive"))
      (node (ref "TP136") (pin "TP") (pinfunction "PP_TP") (pintype "input"))
    )
    (net (code "127") (name "Net-(12D-KL)") (class "Default")
      (node (ref "12") (pin "12") (pinfunction "KL_12") (pintype "passive"))
      (node (ref "R313") (pin "1") (pinfunction "1_1") (pintype "passive"))
      (node (ref "TP138") (pin "TP") (pinfunction "PP_TP") (pintype "input"))
    )
    (net (code "128") (name "Net-(12E-KL)") (class "Default")
      (node (ref "12") (pin "2") (pinfunction "KL_2") (pintype "passive"))
      (node (ref "D65") (pin "2") (pinfunction "-_2") (pintype "passive"))
      (node (ref "LED25") (pin "K") (pinfunction "C_K") (pintype "passive"))
      (node (ref "TP127") (pin "TP") (pinfunction "PP_TP") (pintype "input"))
      (node (ref "X13") (pin "12") (pinfunction "12_12") (pintype "passive"))
    )
    (net (code "129") (name "Net-(12F-KL)") (class "Default")
      (node (ref "12") (pin "3") (pinfunction "KL_3") (pintype "passive"))
      (node (ref "D64") (pin "2") (pinfunction "-_2") (pintype "passive"))
      (node (ref "LED26") (pin "K") (pinfunction "C_K") (pintype "passive"))
      (node (ref "TP128") (pin "TP") (pinfunction "PP_TP") (pintype "input"))
      (node (ref "X13") (pin "11") (pinfunction "11_11") (pintype "passive"))
    )
    (net (code "130") (name "Net-(12G-KL)") (class "Default")
      (node (ref "12") (pin "4") (pinfunction "KL_4") (pintype "passive"))
      (node (ref "D63") (pin "2") (pinfunction "-_2") (pintype "passive"))
      (node (ref "LED27") (pin "K") (pinfunction "C_K") (pintype "passive"))
      (node (ref "TP129") (pin "TP") (pinfunction "PP_TP") (pintype "input"))
      (node (ref "X13") (pin "10") (pinfunction "10_10") (pintype "passive"))
    )
    (net (code "131") (name "Net-(12H-KL)") (class "Default")
      (node (ref "12") (pin "5") (pinfunction "KL_5") (pintype "passive"))
      (node (ref "D62") (pin "2") (pinfunction "-_2") (pintype "passive"))
      (node (ref "LED28") (pin "K") (pinfunction "C_K") (pintype "passive"))
      (node (ref "TP130") (pin "TP") (pinfunction "PP_TP") (pintype "input"))
      (node (ref "X13") (pin "9") (pinfunction "9_9") (pintype "passive"))
    )
    (net (code "132") (name "Net-(12I-KL)") (class "Default")
      (node (ref "12") (pin "6") (pinfunction "KL_6") (pintype "passive"))
      (node (ref "JP22") (pin "2") (pinfunction "2_2") (pintype "passive"))
      (node (ref "TP131") (pin "TP") (pinfunction "PP_TP") (pintype "input"))
    )
    (net (code "133") (name "Net-(12J-KL)") (class "Default")
      (node (ref "12") (pin "7") (pinfunction "KL_7") (pintype "passive"))
      (node (ref "LED29") (pin "A") (pinfunction "A_A") (pintype "passive"))
      (node (ref "TP132") (pin "TP") (pinfunction "PP_TP") (pintype "input"))
      (node (ref "X13") (pin "8") (pinfunction "8_8") (pintype "passive"))
    )
    (net (code "134") (name "Net-(12K-KL)") (class "Default")
      (node (ref "12") (pin "8") (pinfunction "KL_8") (pintype "passive"))
      (node (ref "D66") (pin "2") (pinfunction "-_2") (pintype "passive"))
      (node (ref "LED30") (pin "K") (pinfunction "C_K") (pintype "passive"))
      (node (ref "TP133") (pin "TP") (pinfunction "PP_TP") (pintype "input"))
      (node (ref "X13") (pin "14") (pinfunction "14_14") (pintype "passive"))
    )
    (net (code "135") (name "Net-(12L-KL)") (class "Default")
      (node (ref "12") (pin "9") (pinfunction "KL_9") (pintype "passive"))
      (node (ref "D63") (pin "1") (pinfunction "+_1") (pintype "passive"))
      (node (ref "D64") (pin "1") (pinfunction "+_1") (pintype "passive"))
      (node (ref "JP23") (pin "1") (pinfunction "1_1") (pintype "passive"))
      (node (ref "JP24") (pin "2") (pinfunction "2_2") (pintype "passive"))
      (node (ref "TP134") (pin "TP") (pinfunction "PP_TP") (pintype "input"))
    )
    (net (code "136") (name "Net-(C1-Pad1)") (class "Default")
      (node (ref "C1") (pin "1") (pinfunction "1_1") (pintype "passive"))
      (node (ref "R22") (pin "1") (pinfunction "1_1") (pintype "passive"))
      (node (ref "R23") (pin "2") (pinfunction "2_2") (pintype "passive"))
    )
    (net (code "137") (name "Net-(C11-Pad1)") (class "Default")
      (node (ref "C11") (pin "1") (pinfunction "1_1") (pintype "passive"))
      (node (ref "R50") (pin "1") (pinfunction "1_1") (pintype "passive"))
      (node (ref "R51") (pin "1") (pinfunction "1_1") (pintype "passive"))
    )
    (net (code "138") (name "Net-(C14-Pad1)") (class "Default")
      (node (ref "C14") (pin "1") (pinfunction "1_1") (pintype "passive"))
      (node (ref "R77") (pin "1") (pinfunction "1_1") (pintype "passive"))
      (node (ref "R78") (pin "2") (pinfunction "2_2") (pintype "passive"))
    )
    (net (code "139") (name "Net-(C24-Pad1)") (class "Default")
      (node (ref "C24") (pin "1") (pinfunction "1_1") (pintype "passive"))
      (node (ref "R149") (pin "1") (pinfunction "1_1") (pintype "passive"))
      (node (ref "R150") (pin "1") (pinfunction "1_1") (pintype "passive"))
    )
    (net (code "140") (name "Net-(C27-Pad1)") (class "Default")
      (node (ref "C27") (pin "1") (pinfunction "1_1") (pintype "passive"))
      (node (ref "R176") (pin "1") (pinfunction "1_1") (pintype "passive"))
      (node (ref "R177") (pin "2") (pinfunction "2_2") (pintype "passive"))
    )
    (net (code "141") (name "Net-(C36-Pad1)") (class "Default")
      (node (ref "C36") (pin "1") (pinfunction "1_1") (pintype "passive"))
      (node (ref "R204") (pin "1") (pinfunction "1_1") (pintype "passive"))
      (node (ref "R205") (pin "1") (pinfunction "1_1") (pintype "passive"))
    )
    (net (code "142") (name "Net-(C39-Pad1)") (class "Default")
      (node (ref "C39") (pin "1") (pinfunction "1_1") (pintype "passive"))
      (node (ref "R231") (pin "1") (pinfunction "1_1") (pintype "passive"))
      (node (ref "R232") (pin "2") (pinfunction "2_2") (pintype "passive"))
    )
    (net (code "143") (name "Net-(C48-Pad1)") (class "Default")
      (node (ref "C48") (pin "1") (pinfunction "1_1") (pintype "passive"))
      (node (ref "R259") (pin "1") (pinfunction "1_1") (pintype "passive"))
      (node (ref "R260") (pin "1") (pinfunction "1_1") (pintype "passive"))
    )
    (net (code "144") (name "Net-(C51-Pad1)") (class "Default")
      (node (ref "C51") (pin "1") (pinfunction "1_1") (pintype "passive"))
      (node (ref "R286") (pin "1") (pinfunction "1_1") (pintype "passive"))
      (node (ref "R287") (pin "2") (pinfunction "2_2") (pintype "passive"))
    )
    (net (code "145") (name "Net-(C60-Pad1)") (class "Default")
      (node (ref "C60") (pin "1") (pinfunction "1_1") (pintype "passive"))
      (node (ref "R314") (pin "1") (pinfunction "1_1") (pintype "passive"))
      (node (ref "R315") (pin "1") (pinfunction "1_1") (pintype "passive"))
    )
    (net (code "146") (name "Net-(C103-Pad1)") (class "Default")
      (node (ref "C103") (pin "1") (pinfunction "1_1") (pintype "passive"))
      (node (ref "R108") (pin "1") (pinfunction "1_1") (pintype "passive"))
      (node (ref "R112") (pin "1") (pinfunction "1_1") (pintype "passive"))
    )
    (net (code "147") (name "Net-(C107-Pad1)") (class "Default")
      (node (ref "C107") (pin "1") (pinfunction "1_1") (pintype "passive"))
      (node (ref "R125") (pin "1") (pinfunction "1_1") (pintype "passive"))
      (node (ref "R130") (pin "2") (pinfunction "2_2") (pintype "passive"))
    )
    (net (code "148") (name "Net-(D1--)") (class "Default")
      (node (ref "D1") (pin "2") (pinfunction "-_2") (pintype "passive"))
      (node (ref "R12") (pin "1") (pinfunction "1_1") (pintype "passive"))
      (node (ref "R13") (pin "1") (pinfunction "1_1") (pintype "passive"))
    )
    (net (code "149") (name "Net-(D2-+)") (class "Default")
      (node (ref "D2") (pin "1") (pinfunction "+_1") (pintype "passive"))
      (node (ref "X101") (pin "1") (pinfunction "1_1") (pintype "passive"))
    )
    (net (code "150") (name "Net-(D6-+)") (class "Default")
      (node (ref "D6") (pin "1") (pinfunction "+_1") (pintype "passive"))
      (node (ref "R7") (pin "1") (pinfunction "1_1") (pintype "passive"))
    )
    (net (code "151") (name "Net-(D9-+)") (class "Default")
      (node (ref "D9") (pin "1") (pinfunction "+_1") (pintype "passive"))
      (node (ref "JP3") (pin "2") (pinfunction "2_2") (pintype "passive"))
    )
    (net (code "152") (name "Net-(D10-+)") (class "Default")
      (node (ref "D10") (pin "1") (pinfunction "+_1") (pintype "passive"))
      (node (ref "JP4") (pin "1") (pinfunction "1_1") (pintype "passive"))
    )
    (net (code "153") (name "Net-(D11--)") (class "Default")
      (node (ref "D11") (pin "2") (pinfunction "-_2") (pintype "passive"))
      (node (ref "Q4") (pin "2") (pinfunction "C_2") (pintype "passive"))
      (node (ref "START1") (pin "TP") (pinfunction "PP_TP") (pintype "input"))
      (node (ref "X1") (pin "5") (pinfunction "5_5") (pintype "passive"))
    )
    (net (code "154") (name "Net-(D12-+)") (class "Default")
      (node (ref "D12") (pin "1") (pinfunction "+_1") (pintype "passive"))
      (node (ref "R44") (pin "1") (pinfunction "1_1") (pintype "passive"))
    )
    (net (code "155") (name "Net-(D12--)") (class "Default")
      (node (ref "C8") (pin "2") (pinfunction "2_2") (pintype "passive"))
      (node (ref "D12") (pin "2") (pinfunction "-_2") (pintype "passive"))
      (node (ref "D17") (pin "C") (pinfunction "C_C") (pintype "passive"))
      (node (ref "IC6") (pin "2") (pinfunction "TR_2") (pintype "input"))
      (node (ref "IC6") (pin "6") (pinfunction "THR_6") (pintype "input"))
      (node (ref "R42") (pin "1") (pinfunction "1_1") (pintype "passive"))
    )
    (net (code "156") (name "Net-(D14-PadC)") (class "Default")
      (node (ref "D14") (pin "C") (pinfunction "C_C") (pintype "passive"))
      (node (ref "R18") (pin "2") (pinfunction "2_2") (pintype "passive"))
      (node (ref "X1") (pin "22") (pinfunction "22_22") (pintype "passive"))
    )
    (net (code "157") (name "Net-(D15--)") (class "Default")
      (node (ref "D15") (pin "2") (pinfunction "-_2") (pintype "passive"))
      (node (ref "R65") (pin "1") (pinfunction "1_1") (pintype "passive"))
      (node (ref "R66") (pin "1") (pinfunction "1_1") (pintype "passive"))
    )
    (net (code "158") (name "Net-(D16-+)") (class "Default")
      (node (ref "D16") (pin "1") (pinfunction "+_1") (pintype "passive"))
      (node (ref "X1") (pin "1") (pinfunction "1_1") (pintype "passive"))
    )
    (net (code "159") (name "Net-(D20-+)") (class "Default")
      (node (ref "D20") (pin "1") (pinfunction "+_1") (pintype "passive"))
      (node (ref "R67") (pin "1") (pinfunction "1_1") (pintype "passive"))
    )
    (net (code "160") (name "Net-(D23-+)") (class "Default")
      (node (ref "D23") (pin "1") (pinfunction "+_1") (pintype "passive"))
      (node (ref "JP8") (pin "2") (pinfunction "2_2") (pintype "passive"))
    )
    (net (code "161") (name "Net-(D24-+)") (class "Default")
      (node (ref "D24") (pin "1") (pinfunction "+_1") (pintype "passive"))
      (node (ref "JP9") (pin "1") (pinfunction "1_1") (pintype "passive"))
    )
    (net (code "162") (name "Net-(D25--)") (class "Default")
      (node (ref "D25") (pin "2") (pinfunction "-_2") (pintype "passive"))
      (node (ref "Q14") (pin "2") (pinfunction "C_2") (pintype "passive"))
      (node (ref "START2") (pin "TP") (pinfunction "PP_TP") (pintype "input"))
      (node (ref "X4") (pin "5") (pinfunction "5_5") (pintype "passive"))
    )
    (net (code "163") (name "Net-(D26-+)") (class "Default")
      (node (ref "D26") (pin "1") (pinfunction "+_1") (pintype "passive"))
      (node (ref "R99") (pin "1") (pinfunction "1_1") (pintype "passive"))
    )
    (net (code "164") (name "Net-(D26--)") (class "Default")
      (node (ref "C21") (pin "2") (pinfunction "2_2") (pintype "passive"))
      (node (ref "D26") (pin "2") (pinfunction "-_2") (pintype "passive"))
      (node (ref "D31") (pin "C") (pinfunction "C_C") (pintype "passive"))
      (node (ref "IC15") (pin "2") (pinfunction "TR_2") (pintype "input"))
      (node (ref "IC15") (pin "6") (pinfunction "THR_6") (pintype "input"))
      (node (ref "R97") (pin "1") (pinfunction "1_1") (pintype "passive"))
    )
    (net (code "165") (name "Net-(D28-PadC)") (class "Default")
      (node (ref "D28") (pin "C") (pinfunction "C_C") (pintype "passive"))
      (node (ref "R73") (pin "2") (pinfunction "2_2") (pintype "passive"))
      (node (ref "X4") (pin "22") (pinfunction "22_22") (pintype "passive"))
    )
    (net (code "166") (name "Net-(D29--)") (class "Default")
      (node (ref "D29") (pin "2") (pinfunction "-_2") (pintype "passive"))
      (node (ref "R164") (pin "1") (pinfunction "1_1") (pintype "passive"))
      (node (ref "R165") (pin "1") (pinfunction "1_1") (pintype "passive"))
    )
    (net (code "167") (name "Net-(D30-+)") (class "Default")
      (node (ref "D30") (pin "1") (pinfunction "+_1") (pintype "passive"))
      (node (ref "X4") (pin "1") (pinfunction "1_1") (pintype "passive"))
    )
    (net (code "168") (name "Net-(D34-+)") (class "Default")
      (node (ref "D34") (pin "1") (pinfunction "+_1") (pintype "passive"))
      (node (ref "R166") (pin "1") (pinfunction "1_1") (pintype "passive"))
    )
    (net (code "169") (name "Net-(D37-+)") (class "Default")
      (node (ref "D37") (pin "1") (pinfunction "+_1") (pintype "passive"))
      (node (ref "JP13") (pin "2") (pinfunction "2_2") (pintype "passive"))
    )
    (net (code "170") (name "Net-(D38-+)") (class "Default")
      (node (ref "D38") (pin "1") (pinfunction "+_1") (pintype "passive"))
      (node (ref "JP14") (pin "1") (pinfunction "1_1") (pintype "passive"))
    )
    (net (code "171") (name "Net-(D39--)") (class "Default")
      (node (ref "D39") (pin "2") (pinfunction "-_2") (pintype "passive"))
      (node (ref "Q24") (pin "2") (pinfunction "C_2") (pintype "passive"))
      (node (ref "START3") (pin "TP") (pinfunction "PP_TP") (pintype "input"))
      (node (ref "X7") (pin "5") (pinfunction "5_5") (pintype "passive"))
    )
    (net (code "172") (name "Net-(D40-+)") (class "Default")
      (node (ref "D40") (pin "1") (pinfunction "+_1") (pintype "passive"))
      (node (ref "R198") (pin "1") (pinfunction "1_1") (pintype "passive"))
    )
    (net (code "173") (name "Net-(D40--)") (class "Default")
      (node (ref "C33") (pin "2") (pinfunction "2_2") (pintype "passive"))
      (node (ref "D40") (pin "2") (pinfunction "-_2") (pintype "passive"))
      (node (ref "D45") (pin "C") (pinfunction "C_C") (pintype "passive"))
      (node (ref "IC24") (pin "2") (pinfunction "TR_2") (pintype "input"))
      (node (ref "IC24") (pin "6") (pinfunction "THR_6") (pintype "input"))
      (node (ref "R196") (pin "1") (pinfunction "1_1") (pintype "passive"))
    )
    (net (code "174") (name "Net-(D42-PadC)") (class "Default")
      (node (ref "D42") (pin "C") (pinfunction "C_C") (pintype "passive"))
      (node (ref "R172") (pin "2") (pinfunction "2_2") (pintype "passive"))
      (node (ref "X7") (pin "22") (pinfunction "22_22") (pintype "passive"))
    )
    (net (code "175") (name "Net-(D43--)") (class "Default")
      (node (ref "D43") (pin "2") (pinfunction "-_2") (pintype "passive"))
      (node (ref "R219") (pin "1") (pinfunction "1_1") (pintype "passive"))
      (node (ref "R220") (pin "1") (pinfunction "1_1") (pintype "passive"))
    )
    (net (code "176") (name "Net-(D44-+)") (class "Default")
      (node (ref "D44") (pin "1") (pinfunction "+_1") (pintype "passive"))
      (node (ref "X7") (pin "1") (pinfunction "1_1") (pintype "passive"))
    )
    (net (code "177") (name "Net-(D48-+)") (class "Default")
      (node (ref "D48") (pin "1") (pinfunction "+_1") (pintype "passive"))
      (node (ref "R221") (pin "1") (pinfunction "1_1") (pintype "passive"))
    )
    (net (code "178") (name "Net-(D51-+)") (class "Default")
      (node (ref "D51") (pin "1") (pinfunction "+_1") (pintype "passive"))
      (node (ref "JP18") (pin "2") (pinfunction "2_2") (pintype "passive"))
    )
    (net (code "179") (name "Net-(D52-+)") (class "Default")
      (node (ref "D52") (pin "1") (pinfunction "+_1") (pintype "passive"))
      (node (ref "JP19") (pin "1") (pinfunction "1_1") (pintype "passive"))
    )
    (net (code "180") (name "Net-(D53--)") (class "Default")
      (node (ref "D53") (pin "2") (pinfunction "-_2") (pintype "passive"))
      (node (ref "Q34") (pin "2") (pinfunction "C_2") (pintype "passive"))
      (node (ref "START4") (pin "TP") (pinfunction "PP_TP") (pintype "input"))
      (node (ref "X10") (pin "5") (pinfunction "5_5") (pintype "passive"))
    )
    (net (code "181") (name "Net-(D54-+)") (class "Default")
      (node (ref "D54") (pin "1") (pinfunction "+_1") (pintype "passive"))
      (node (ref "R253") (pin "1") (pinfunction "1_1") (pintype "passive"))
    )
    (net (code "182") (name "Net-(D54--)") (class "Default")
      (node (ref "C45") (pin "2") (pinfunction "2_2") (pintype "passive"))
      (node (ref "D54") (pin "2") (pinfunction "-_2") (pintype "passive"))
      (node (ref "D59") (pin "C") (pinfunction "C_C") (pintype "passive"))
      (node (ref "IC33") (pin "2") (pinfunction "TR_2") (pintype "input"))
      (node (ref "IC33") (pin "6") (pinfunction "THR_6") (pintype "input"))
      (node (ref "R251") (pin "1") (pinfunction "1_1") (pintype "passive"))
    )
    (net (code "183") (name "Net-(D56-PadC)") (class "Default")
      (node (ref "D56") (pin "C") (pinfunction "C_C") (pintype "passive"))
      (node (ref "R227") (pin "2") (pinfunction "2_2") (pintype "passive"))
      (node (ref "X10") (pin "22") (pinfunction "22_22") (pintype "passive"))
    )
    (net (code "184") (name "Net-(D57--)") (class "Default")
      (node (ref "D57") (pin "2") (pinfunction "-_2") (pintype "passive"))
      (node (ref "R274") (pin "1") (pinfunction "1_1") (pintype "passive"))
      (node (ref "R275") (pin "1") (pinfunction "1_1") (pintype "passive"))
    )
    (net (code "185") (name "Net-(D58-+)") (class "Default")
      (node (ref "D58") (pin "1") (pinfunction "+_1") (pintype "passive"))
      (node (ref "X10") (pin "1") (pinfunction "1_1") (pintype "passive"))
    )
    (net (code "186") (name "Net-(D62-+)") (class "Default")
      (node (ref "D62") (pin "1") (pinfunction "+_1") (pintype "passive"))
      (node (ref "R276") (pin "1") (pinfunction "1_1") (pintype "passive"))
    )
    (net (code "187") (name "Net-(D65-+)") (class "Default")
      (node (ref "D65") (pin "1") (pinfunction "+_1") (pintype "passive"))
      (node (ref "JP23") (pin "2") (pinfunction "2_2") (pintype "passive"))
    )
    (net (code "188") (name "Net-(D66-+)") (class "Default")
      (node (ref "D66") (pin "1") (pinfunction "+_1") (pintype "passive"))
      (node (ref "JP24") (pin "1") (pinfunction "1_1") (pintype "passive"))
    )
    (net (code "189") (name "Net-(D67--)") (class "Default")
      (node (ref "D67") (pin "2") (pinfunction "-_2") (pintype "passive"))
      (node (ref "Q44") (pin "2") (pinfunction "C_2") (pintype "passive"))
      (node (ref "START5") (pin "TP") (pinfunction "PP_TP") (pintype "input"))
      (node (ref "X13") (pin "5") (pinfunction "5_5") (pintype "passive"))
    )
    (net (code "190") (name "Net-(D68-+)") (class "Default")
      (node (ref "D68") (pin "1") (pinfunction "+_1") (pintype "passive"))
      (node (ref "R308") (pin "1") (pinfunction "1_1") (pintype "passive"))
    )
    (net (code "191") (name "Net-(D68--)") (class "Default")
      (node (ref "C57") (pin "2") (pinfunction "2_2") (pintype "passive"))
      (node (ref "D68") (pin "2") (pinfunction "-_2") (pintype "passive"))
      (node (ref "D73") (pin "C") (pinfunction "C_C") (pintype "passive"))
      (node (ref "IC42") (pin "2") (pinfunction "TR_2") (pintype "input"))
      (node (ref "IC42") (pin "6") (pinfunction "THR_6") (pintype "input"))
      (node (ref "R306") (pin "1") (pinfunction "1_1") (pintype "passive"))
    )
    (net (code "192") (name "Net-(D70-PadC)") (class "Default")
      (node (ref "D70") (pin "C") (pinfunction "C_C") (pintype "passive"))
      (node (ref "R282") (pin "2") (pinfunction "2_2") (pintype "passive"))
      (node (ref "X13") (pin "22") (pinfunction "22_22") (pintype "passive"))
    )
    (net (code "193") (name "Net-(D71--)") (class "Default")
      (node (ref "D71") (pin "2") (pinfunction "-_2") (pintype "passive"))
      (node (ref "R329") (pin "1") (pinfunction "1_1") (pintype "passive"))
      (node (ref "R330") (pin "1") (pinfunction "1_1") (pintype "passive"))
    )
    (net (code "194") (name "Net-(D72-+)") (class "Default")
      (node (ref "D72") (pin "1") (pinfunction "+_1") (pintype "passive"))
      (node (ref "X13") (pin "1") (pinfunction "1_1") (pintype "passive"))
    )
    (net (code "195") (name "Net-(D104-PadC)") (class "Default")
      (node (ref "D104") (pin "C") (pinfunction "C_C") (pintype "passive"))
      (node (ref "R105") (pin "2") (pinfunction "2_2") (pintype "passive"))
      (node (ref "X101") (pin "22") (pinfunction "22_22") (pintype "passive"))
    )
    (net (code "196") (name "Net-(D105--)") (class "Default")
      (node (ref "D105") (pin "2") (pinfunction "-_2") (pintype "passive"))
      (node (ref "Q104") (pin "2") (pinfunction "C_2") (pintype "passive"))
      (node (ref "START") (pin "TP") (pinfunction "PP_TP") (pintype "input"))
      (node (ref "X101") (pin "5") (pinfunction "5_5") (pintype "passive"))
    )
    (net (code "197") (name "Net-(D106-+)") (class "Default")
      (node (ref "D106") (pin "1") (pinfunction "+_1") (pintype "passive"))
      (node (ref "R127") (pin "1") (pinfunction "1_1") (pintype "passive"))
    )
    (net (code "198") (name "Net-(D109-+)") (class "Default")
      (node (ref "D109") (pin "1") (pinfunction "+_1") (pintype "passive"))
      (node (ref "JP102") (pin "2") (pinfunction "2_2") (pintype "passive"))
    )
    (net (code "199") (name "Net-(D110-+)") (class "Default")
      (node (ref "D110") (pin "1") (pinfunction "+_1") (pintype "passive"))
      (node (ref "JP103") (pin "1") (pinfunction "1_1") (pintype "passive"))
    )
    (net (code "200") (name "Net-(D112-+)") (class "Default")
      (node (ref "D112") (pin "1") (pinfunction "+_1") (pintype "passive"))
      (node (ref "R140") (pin "1") (pinfunction "1_1") (pintype "passive"))
    )
    (net (code "201") (name "Net-(D112--)") (class "Default")
      (node (ref "C109") (pin "2") (pinfunction "2_2") (pintype "passive"))
      (node (ref "D112") (pin "2") (pinfunction "-_2") (pintype "passive"))
      (node (ref "D4") (pin "C") (pinfunction "C_C") (pintype "passive"))
      (node (ref "IC110") (pin "2") (pinfunction "TR_2") (pintype "input"))
      (node (ref "IC110") (pin "6") (pinfunction "THR_6") (pintype "input"))
      (node (ref "R141") (pin "1") (pinfunction "1_1") (pintype "passive"))
    )
    (net (code "202") (name "Net-(IC1A-A)") (class "Default")
      (node (ref "IC1") (pin "10") (pinfunction "A_10") (pintype "input"))
      (node (ref "R17") (pin "1") (pinfunction "1_1") (pintype "passive"))
      (node (ref "R58") (pin "1") (pinfunction "1_1") (pintype "passive"))
      (node (ref "R58") (pin "2") (pinfunction "2_2") (pintype "passive"))
      (node (ref "X1") (pin "4") (pinfunction "4_4") (pintype "passive"))
      (node (ref "X2") (pin "2") (pinfunction "S_2") (pintype "passive"))
    )
    (net (code "203") (name "Net-(IC1A-B)") (class "Default")
      (node (ref "IC1") (pin "13") (pinfunction "B_13") (pintype "input"))
      (node (ref "R16") (pin "1") (pinfunction "1_1") (pintype "passive"))
      (node (ref "R57") (pin "1") (pinfunction "1_1") (pintype "passive"))
      (node (ref "R57") (pin "2") (pinfunction "2_2") (pintype "passive"))
      (node (ref "X1") (pin "3") (pinfunction "3_3") (pintype "passive"))
      (node (ref "X2") (pin "3") (pinfunction "S_3") (pintype "passive"))
    )
    (net (code "204") (name "Net-(IC1A-C)") (class "Default")
      (node (ref "IC1") (pin "12") (pinfunction "C_12") (pintype "input"))
      (node (ref "R15") (pin "1") (pinfunction "1_1") (pintype "passive"))
      (node (ref "R56") (pin "1") (pinfunction "1_1") (pintype "passive"))
      (node (ref "R56") (pin "2") (pinfunction "2_2") (pintype "passive"))
      (node (ref "X1") (pin "2") (pinfunction "2_2") (pintype "passive"))
      (node (ref "X2") (pin "4") (pinfunction "S_4") (pintype "passive"))
    )
    (net (code "205") (name "Net-(IC1A-Q0)") (class "Default")
      (node (ref "IC1") (pin "3") (pinfunction "Q0_3") (pintype "output"))
      (node (ref "IC3") (pin "1") (pinfunction "I1_1") (pintype "input"))
      (node (ref "IC3") (pin "2") (pinfunction "I2_2") (pintype "input"))
      (node (ref "Q10") (pin "1") (pinfunction "G_1") (pintype "passive"))
      (node (ref "Q11") (pin "1") (pinfunction "G_1") (pintype "passive"))
    )
    (net (code "206") (name "Net-(IC1A-Q1)") (class "Default")
      (node (ref "IC1") (pin "14") (pinfunction "Q1_14") (pintype "output"))
      (node (ref "IC3") (pin "6") (pinfunction "I6_6") (pintype "input"))
    )
    (net (code "207") (name "Net-(IC1A-Q2)") (class "Default")
      (node (ref "IC1") (pin "2") (pinfunction "Q2_2") (pintype "output"))
      (node (ref "IC3") (pin "7") (pinfunction "I7_7") (pintype "input"))
    )
    (net (code "208") (name "Net-(IC1A-Q3)") (class "Default")
      (node (ref "IC1") (pin "15") (pinfunction "Q3_15") (pintype "output"))
      (node (ref "IC3") (pin "5") (pinfunction "I5_5") (pintype "input"))
    )
    (net (code "209") (name "Net-(IC1A-Q4)") (class "Default")
      (node (ref "IC1") (pin "1") (pinfunction "Q4_1") (pintype "output"))
      (node (ref "IC3") (pin "4") (pinfunction "I4_4") (pintype "input"))
    )
    (net (code "210") (name "Net-(IC1A-Q5)") (class "Default")
      (node (ref "IC1") (pin "6") (pinfunction "Q5_6") (pintype "output"))
      (node (ref "IC3") (pin "3") (pinfunction "I3_3") (pintype "input"))
    )
    (net (code "211") (name "Net-(IC2-ADJ)") (class "Default")
      (node (ref "IC2") (pin "1") (pinfunction "ADJ_1") (pintype "input"))
      (node (ref "R11") (pin "1") (pinfunction "1_1") (pintype "passive"))
      (node (ref "R20") (pin "2") (pinfunction "2_2") (pintype "passive"))
      (node (ref "X1") (pin "7") (pinfunction "7_7") (pintype "passive"))
    )
    (net (code "212") (name "Net-(IC2-VI)") (class "Default")
      (node (ref "IC2") (pin "3") (pinfunction "VI_3") (pintype "input"))
      (node (ref "Q7") (pin "2") (pinfunction "C_2") (pintype "passive"))
    )
    (net (code "213") (name "Net-(IC2-VO)") (class "Default")
      (node (ref "IC2") (pin "2") (pinfunction "VO_2") (pintype "passive"))
      (node (ref "R11") (pin "2") (pinfunction "2_2") (pintype "passive"))
    )
    (net (code "214") (name "Net-(IC3-O1)") (class "Default")
      (node (ref "IC3") (pin "16") (pinfunction "O1_16") (pintype "open_collector"))
      (node (ref "Q10") (pin "3") (pinfunction "D_3") (pintype "passive"))
      (node (ref "R62") (pin "1") (pinfunction "1_1") (pintype "passive"))
    )
    (net (code "215") (name "Net-(IC3-O2)") (class "Default")
      (node (ref "IC3") (pin "15") (pinfunction "O2_15") (pintype "open_collector"))
      (node (ref "R35") (pin "1") (pinfunction "1_1") (pintype "passive"))
    )
    (net (code "216") (name "Net-(IC4A-+IN)") (class "Default")
      (node (ref "IC4") (pin "11") (pinfunction "+IN_11") (pintype "input"))
      (node (ref "IC4") (pin "5") (pinfunction "+IN_5") (pintype "input"))
      (node (ref "R24") (pin "1") (pinfunction "1_1") (pintype "passive"))
      (node (ref "R25") (pin "2") (pinfunction "2_2") (pintype "passive"))
      (node (ref "R26") (pin "2") (pinfunction "2_2") (pintype "passive"))
    )
    (net (code "217") (name "Net-(IC4A--IN)") (class "Default")
      (node (ref "C3") (pin "1") (pinfunction "1_1") (pintype "passive"))
      (node (ref "IC4") (pin "10") (pinfunction "-IN_10") (pintype "input"))
      (node (ref "IC4") (pin "4") (pinfunction "-IN_4") (pintype "input"))
      (node (ref "R23") (pin "1") (pinfunction "1_1") (pintype "passive"))
    )
    (net (code "218") (name "Net-(IC4A-OUT)") (class "Default")
      (node (ref "IC4") (pin "2") (pinfunction "OUT_2") (pintype "open_collector"))
      (node (ref "R26") (pin "1") (pinfunction "1_1") (pintype "passive"))
    )
    (net (code "219") (name "Net-(IC4B-+IN)") (class "Default")
      (node (ref "IC4") (pin "7") (pinfunction "+IN_7") (pintype "input"))
      (node (ref "R21") (pin "1") (pinfunction "1_1") (pintype "passive"))
      (node (ref "R38") (pin "1") (pinfunction "1_1") (pintype "passive"))
    )
    (net (code "220") (name "Net-(IC4B--IN)") (class "Default")
      (node (ref "IC4") (pin "6") (pinfunction "-IN_6") (pintype "input"))
      (node (ref "IC4") (pin "8") (pinfunction "-IN_8") (pintype "input"))
      (node (ref "R20") (pin "1") (pinfunction "1_1") (pintype "passive"))
    )
    (net (code "221") (name "Net-(IC4B-OUT)") (class "Default")
      (node (ref "IC4") (pin "1") (pinfunction "OUT_1") (pintype "open_collector"))
      (node (ref "R22") (pin "2") (pinfunction "2_2") (pintype "passive"))
      (node (ref "R27") (pin "2") (pinfunction "2_2") (pintype "passive"))
    )
    (net (code "222") (name "Net-(IC4C-+IN)") (class "Default")
      (node (ref "C6") (pin "1") (pinfunction "1_1") (pintype "passive"))
      (node (ref "IC4") (pin "9") (pinfunction "+IN_9") (pintype "input"))
      (node (ref "R29") (pin "2") (pinfunction "2_2") (pintype "passive"))
      (node (ref "R38") (pin "2") (pinfunction "2_2") (pintype "passive"))
    )
    (net (code "223") (name "Net-(IC4C-OUT)") (class "Default")
      (node (ref "C7") (pin "2") (pinfunction "2_2") (pintype "passive"))
      (node (ref "IC4") (pin "14") (pinfunction "OUT_14") (pintype "open_collector"))
      (node (ref "R28") (pin "2") (pinfunction "2_2") (pintype "passive"))
    )
    (net (code "224") (name "Net-(IC4D-OUT)") (class "Default")
      (node (ref "IC4") (pin "13") (pinfunction "OUT_13") (pintype "open_collector"))
      (node (ref "JP2") (pin "1") (pinfunction "1_1") (pintype "passive"))
      (node (ref "Q9") (pin "1") (pinfunction "G_1") (pintype "passive"))
      (node (ref "R41") (pin "2") (pinfunction "2_2") (pintype "passive"))
    )
    (net (code "225") (name "Net-(IC6-CV)") (class "Default")
      (node (ref "IC6") (pin "5") (pinfunction "CV_5") (pintype "input"))
      (node (ref "R43") (pin "2") (pinfunction "2_2") (pintype "passive"))
    )
    (net (code "226") (name "Net-(IC6-Q)") (class "Default")
      (node (ref "IC6") (pin "3") (pinfunction "Q_3") (pintype "output"))
      (node (ref "IC7") (pin "12") (pinfunction "A_12") (pintype "input"))
      (node (ref "IC7") (pin "4") (pinfunction "A_4") (pintype "input"))
      (node (ref "R43") (pin "1") (pinfunction "1_1") (pintype "passive"))
    )
    (net (code "227") (name "Net-(IC7A-T2)") (class "Default")
      (node (ref "C12") (pin "2") (pinfunction "2_2") (pintype "passive"))
      (node (ref "IC7") (pin "2") (pinfunction "T2_2") (pintype "input"))
      (node (ref "R64") (pin "1") (pinfunction "1_1") (pintype "passive"))
    )
    (net (code "228") (name "Net-(IC7A-~{Q})") (class "Default")
      (node (ref "IC7") (pin "7") (pinfunction "~{Q}_7") (pintype "output"))
      (node (ref "Q13") (pin "1") (pinfunction "G_1") (pintype "passive"))
    )
    (net (code "229") (name "Net-(IC7B-B)") (class "Default")
      (node (ref "IC7") (pin "11") (pinfunction "B_11") (pintype "input"))
      (node (ref "IC7") (pin "9") (pinfunction "~{Q}_9") (pintype "output"))
      (node (ref "R49") (pin "2") (pinfunction "2_2") (pintype "passive"))
    )
    (net (code "230") (name "Net-(IC7B-T2)") (class "Default")
      (node (ref "C10") (pin "1") (pinfunction "1_1") (pintype "passive"))
      (node (ref "IC7") (pin "14") (pinfunction "T2_14") (pintype "input"))
      (node (ref "R47") (pin "1") (pinfunction "1_1") (pintype "passive"))
    )
    (net (code "231") (name "Net-(IC9A-+IN)") (class "Default")
      (node (ref "C5") (pin "1") (pinfunction "1_1") (pintype "passive"))
      (node (ref "IC9") (pin "3") (pinfunction "+IN_3") (pintype "input"))
      (node (ref "R18") (pin "1") (pinfunction "1_1") (pintype "passive"))
    )
    (net (code "232") (name "Net-(IC9A--IN)") (class "Default")
      (node (ref "IC9") (pin "2") (pinfunction "-IN_2") (pintype "input"))
      (node (ref "R19") (pin "2") (pinfunction "2_2") (pintype "passive"))
    )
    (net (code "233") (name "Net-(IC9A-OUT)") (class "Default")
      (node (ref "IC9") (pin "1") (pinfunction "OUT_1") (pintype "output"))
      (node (ref "R50") (pin "2") (pinfunction "2_2") (pintype "passive"))
    )
    (net (code "234") (name "Net-(IC9B-+IN)") (class "Default")
      (node (ref "IC9") (pin "5") (pinfunction "+IN_5") (pintype "input"))
      (node (ref "Q11") (pin "3") (pinfunction "D_3") (pintype "passive"))
      (node (ref "R51") (pin "2") (pinfunction "2_2") (pintype "passive"))
      (node (ref "R52") (pin "2") (pinfunction "2_2") (pintype "passive"))
    )
    (net (code "235") (name "Net-(IC9B--IN)") (class "Default")
      (node (ref "IC9") (pin "6") (pinfunction "-IN_6") (pintype "input"))
      (node (ref "R53") (pin "1") (pinfunction "1_1") (pintype "passive"))
      (node (ref "R54") (pin "2") (pinfunction "2_2") (pintype "passive"))
    )
    (net (code "236") (name "Net-(IC9B-OUT)") (class "Default")
      (node (ref "IC9") (pin "7") (pinfunction "OUT_7") (pintype "output"))
      (node (ref "R32") (pin "2") (pinfunction "2_2") (pintype "passive"))
      (node (ref "R39") (pin "1") (pinfunction "1_1") (pintype "passive"))
      (node (ref "R52") (pin "1") (pinfunction "1_1") (pintype "passive"))
    )
    (net (code "237") (name "Net-(IC10A-A)") (class "Default")
      (node (ref "IC10") (pin "10") (pinfunction "A_10") (pintype "input"))
      (node (ref "R157") (pin "1") (pinfunction "1_1") (pintype "passive"))
      (node (ref "R157") (pin "2") (pinfunction "2_2") (pintype "passive"))
      (node (ref "R72") (pin "1") (pinfunction "1_1") (pintype "passive"))
      (node (ref "X4") (pin "4") (pinfunction "4_4") (pintype "passive"))
      (node (ref "X5") (pin "2") (pinfunction "S_2") (pintype "passive"))
    )
    (net (code "238") (name "Net-(IC10A-B)") (class "Default")
      (node (ref "IC10") (pin "13") (pinfunction "B_13") (pintype "input"))
      (node (ref "R156") (pin "1") (pinfunction "1_1") (pintype "passive"))
      (node (ref "R156") (pin "2") (pinfunction "2_2") (pintype "passive"))
      (node (ref "R71") (pin "1") (pinfunction "1_1") (pintype "passive"))
      (node (ref "X4") (pin "3") (pinfunction "3_3") (pintype "passive"))
      (node (ref "X5") (pin "3") (pinfunction "S_3") (pintype "passive"))
    )
    (net (code "239") (name "Net-(IC10A-C)") (class "Default")
      (node (ref "IC10") (pin "12") (pinfunction "C_12") (pintype "input"))
      (node (ref "R155") (pin "1") (pinfunction "1_1") (pintype "passive"))
      (node (ref "R155") (pin "2") (pinfunction "2_2") (pintype "passive"))
      (node (ref "R70") (pin "1") (pinfunction "1_1") (pintype "passive"))
      (node (ref "X4") (pin "2") (pinfunction "2_2") (pintype "passive"))
      (node (ref "X5") (pin "4") (pinfunction "S_4") (pintype "passive"))
    )
    (net (code "240") (name "Net-(IC10A-Q0)") (class "Default")
      (node (ref "IC10") (pin "3") (pinfunction "Q0_3") (pintype "output"))
      (node (ref "IC12") (pin "1") (pinfunction "I1_1") (pintype "input"))
      (node (ref "IC12") (pin "2") (pinfunction "I2_2") (pintype "input"))
      (node (ref "Q20") (pin "1") (pinfunction "G_1") (pintype "passive"))
      (node (ref "Q21") (pin "1") (pinfunction "G_1") (pintype "passive"))
    )
    (net (code "241") (name "Net-(IC10A-Q1)") (class "Default")
      (node (ref "IC10") (pin "14") (pinfunction "Q1_14") (pintype "output"))
      (node (ref "IC12") (pin "6") (pinfunction "I6_6") (pintype "input"))
    )
    (net (code "242") (name "Net-(IC10A-Q2)") (class "Default")
      (node (ref "IC10") (pin "2") (pinfunction "Q2_2") (pintype "output"))
      (node (ref "IC12") (pin "7") (pinfunction "I7_7") (pintype "input"))
    )
    (net (code "243") (name "Net-(IC10A-Q3)") (class "Default")
      (node (ref "IC10") (pin "15") (pinfunction "Q3_15") (pintype "output"))
      (node (ref "IC12") (pin "5") (pinfunction "I5_5") (pintype "input"))
    )
    (net (code "244") (name "Net-(IC10A-Q4)") (class "Default")
      (node (ref "IC10") (pin "1") (pinfunction "Q4_1") (pintype "output"))
      (node (ref "IC12") (pin "4") (pinfunction "I4_4") (pintype "input"))
    )
    (net (code "245") (name "Net-(IC10A-Q5)") (class "Default")
      (node (ref "IC10") (pin "6") (pinfunction "Q5_6") (pintype "output"))
      (node (ref "IC12") (pin "3") (pinfunction "I3_3") (pintype "input"))
    )
    (net (code "246") (name "Net-(IC11-ADJ)") (class "Default")
      (node (ref "IC11") (pin "1") (pinfunction "ADJ_1") (pintype "input"))
      (node (ref "R68") (pin "1") (pinfunction "1_1") (pintype "passive"))
      (node (ref "R75") (pin "2") (pinfunction "2_2") (pintype "passive"))
      (node (ref "X4") (pin "7") (pinfunction "7_7") (pintype "passive"))
    )
    (net (code "247") (name "Net-(IC11-VI)") (class "Default")
      (node (ref "IC11") (pin "3") (pinfunction "VI_3") (pintype "input"))
      (node (ref "Q17") (pin "2") (pinfunction "C_2") (pintype "passive"))
    )
    (net (code "248") (name "Net-(IC11-VO)") (class "Default")
      (node (ref "IC11") (pin "2") (pinfunction "VO_2") (pintype "passive"))
      (node (ref "R68") (pin "2") (pinfunction "2_2") (pintype "passive"))
    )
    (net (code "249") (name "Net-(IC12-O1)") (class "Default")
      (node (ref "IC12") (pin "16") (pinfunction "O1_16") (pintype "open_collector"))
      (node (ref "Q20") (pin "3") (pinfunction "D_3") (pintype "passive"))
      (node (ref "R161") (pin "1") (pinfunction "1_1") (pintype "passive"))
    )
    (net (code "250") (name "Net-(IC12-O2)") (class "Default")
      (node (ref "IC12") (pin "15") (pinfunction "O2_15") (pintype "open_collector"))
      (node (ref "R90") (pin "1") (pinfunction "1_1") (pintype "passive"))
    )
    (net (code "251") (name "Net-(IC13A-+IN)") (class "Default")
      (node (ref "IC13") (pin "11") (pinfunction "+IN_11") (pintype "input"))
      (node (ref "IC13") (pin "5") (pinfunction "+IN_5") (pintype "input"))
      (node (ref "R79") (pin "1") (pinfunction "1_1") (pintype "passive"))
      (node (ref "R80") (pin "2") (pinfunction "2_2") (pintype "passive"))
      (node (ref "R81") (pin "2") (pinfunction "2_2") (pintype "passive"))
    )
    (net (code "252") (name "Net-(IC13A--IN)") (class "Default")
      (node (ref "C16") (pin "1") (pinfunction "1_1") (pintype "passive"))
      (node (ref "IC13") (pin "10") (pinfunction "-IN_10") (pintype "input"))
      (node (ref "IC13") (pin "4") (pinfunction "-IN_4") (pintype "input"))
      (node (ref "R78") (pin "1") (pinfunction "1_1") (pintype "passive"))
    )
    (net (code "253") (name "Net-(IC13A-OUT)") (class "Default")
      (node (ref "IC13") (pin "2") (pinfunction "OUT_2") (pintype "open_collector"))
      (node (ref "R81") (pin "1") (pinfunction "1_1") (pintype "passive"))
    )
    (net (code "254") (name "Net-(IC13B-+IN)") (class "Default")
      (node (ref "IC13") (pin "7") (pinfunction "+IN_7") (pintype "input"))
      (node (ref "R76") (pin "1") (pinfunction "1_1") (pintype "passive"))
      (node (ref "R93") (pin "1") (pinfunction "1_1") (pintype "passive"))
    )
    (net (code "255") (name "Net-(IC13B--IN)") (class "Default")
      (node (ref "IC13") (pin "6") (pinfunction "-IN_6") (pintype "input"))
      (node (ref "IC13") (pin "8") (pinfunction "-IN_8") (pintype "input"))
      (node (ref "R75") (pin "1") (pinfunction "1_1") (pintype "passive"))
    )
    (net (code "256") (name "Net-(IC13B-OUT)") (class "Default")
      (node (ref "IC13") (pin "1") (pinfunction "OUT_1") (pintype "open_collector"))
      (node (ref "R77") (pin "2") (pinfunction "2_2") (pintype "passive"))
      (node (ref "R82") (pin "2") (pinfunction "2_2") (pintype "passive"))
    )
    (net (code "257") (name "Net-(IC13C-+IN)") (class "Default")
      (node (ref "C19") (pin "1") (pinfunction "1_1") (pintype "passive"))
      (node (ref "IC13") (pin "9") (pinfunction "+IN_9") (pintype "input"))
      (node (ref "R84") (pin "2") (pinfunction "2_2") (pintype "passive"))
      (node (ref "R93") (pin "2") (pinfunction "2_2") (pintype "passive"))
    )
    (net (code "258") (name "Net-(IC13C-OUT)") (class "Default")
      (node (ref "C20") (pin "2") (pinfunction "2_2") (pintype "passive"))
      (node (ref "IC13") (pin "14") (pinfunction "OUT_14") (pintype "open_collector"))
      (node (ref "R83") (pin "2") (pinfunction "2_2") (pintype "passive"))
    )
    (net (code "259") (name "Net-(IC13D-OUT)") (class "Default")
      (node (ref "IC13") (pin "13") (pinfunction "OUT_13") (pintype "open_collector"))
      (node (ref "JP7") (pin "1") (pinfunction "1_1") (pintype "passive"))
      (node (ref "Q19") (pin "1") (pinfunction "G_1") (pintype "passive"))
      (node (ref "R96") (pin "2") (pinfunction "2_2") (pintype "passive"))
    )
    (net (code "260") (name "Net-(IC15-CV)") (class "Default")
      (node (ref "IC15") (pin "5") (pinfunction "CV_5") (pintype "input"))
      (node (ref "R98") (pin "2") (pinfunction "2_2") (pintype "passive"))
    )
    (net (code "261") (name "Net-(IC15-Q)") (class "Default")
      (node (ref "IC15") (pin "3") (pinfunction "Q_3") (pintype "output"))
      (node (ref "IC16") (pin "12") (pinfunction "A_12") (pintype "input"))
      (node (ref "IC16") (pin "4") (pinfunction "A_4") (pintype "input"))
      (node (ref "R98") (pin "1") (pinfunction "1_1") (pintype "passive"))
    )
    (net (code "262") (name "Net-(IC16A-T2)") (class "Default")
      (node (ref "C25") (pin "2") (pinfunction "2_2") (pintype "passive"))
      (node (ref "IC16") (pin "2") (pinfunction "T2_2") (pintype "input"))
      (node (ref "R163") (pin "1") (pinfunction "1_1") (pintype "passive"))
    )
    (net (code "263") (name "Net-(IC16A-~{Q})") (class "Default")
      (node (ref "IC16") (pin "7") (pinfunction "~{Q}_7") (pintype "output"))
      (node (ref "Q23") (pin "1") (pinfunction "G_1") (pintype "passive"))
    )
    (net (code "264") (name "Net-(IC16B-B)") (class "Default")
      (node (ref "IC16") (pin "11") (pinfunction "B_11") (pintype "input"))
      (node (ref "IC16") (pin "9") (pinfunction "~{Q}_9") (pintype "output"))
      (node (ref "R148") (pin "2") (pinfunction "2_2") (pintype "passive"))
    )
    (net (code "265") (name "Net-(IC16B-T2)") (class "Default")
      (node (ref "C23") (pin "1") (pinfunction "1_1") (pintype "passive"))
      (node (ref "IC16") (pin "14") (pinfunction "T2_14") (pintype "input"))
      (node (ref "R139") (pin "1") (pinfunction "1_1") (pintype "passive"))
    )
    (net (code "266") (name "Net-(IC18A-+IN)") (class "Default")
      (node (ref "C18") (pin "1") (pinfunction "1_1") (pintype "passive"))
      (node (ref "IC18") (pin "3") (pinfunction "+IN_3") (pintype "input"))
      (node (ref "R73") (pin "1") (pinfunction "1_1") (pintype "passive"))
    )
    (net (code "267") (name "Net-(IC18A--IN)") (class "Default")
      (node (ref "IC18") (pin "2") (pinfunction "-IN_2") (pintype "input"))
      (node (ref "R74") (pin "2") (pinfunction "2_2") (pintype "passive"))
    )
    (net (code "268") (name "Net-(IC18A-OUT)") (class "Default")
      (node (ref "IC18") (pin "1") (pinfunction "OUT_1") (pintype "output"))
      (node (ref "R149") (pin "2") (pinfunction "2_2") (pintype "passive"))
    )
    (net (code "269") (name "Net-(IC18B-+IN)") (class "Default")
      (node (ref "IC18") (pin "5") (pinfunction "+IN_5") (pintype "input"))
      (node (ref "Q21") (pin "3") (pinfunction "D_3") (pintype "passive"))
      (node (ref "R150") (pin "2") (pinfunction "2_2") (pintype "passive"))
      (node (ref "R151") (pin "2") (pinfunction "2_2") (pintype "passive"))
    )
    (net (code "270") (name "Net-(IC18B--IN)") (class "Default")
      (node (ref "IC18") (pin "6") (pinfunction "-IN_6") (pintype "input"))
      (node (ref "R152") (pin "1") (pinfunction "1_1") (pintype "passive"))
      (node (ref "R153") (pin "2") (pinfunction "2_2") (pintype "passive"))
    )
    (net (code "271") (name "Net-(IC18B-OUT)") (class "Default")
      (node (ref "IC18") (pin "7") (pinfunction "OUT_7") (pintype "output"))
      (node (ref "R151") (pin "1") (pinfunction "1_1") (pintype "passive"))
      (node (ref "R87") (pin "2") (pinfunction "2_2") (pintype "passive"))
      (node (ref "R94") (pin "1") (pinfunction "1_1") (pintype "passive"))
    )
    (net (code "272") (name "Net-(IC19A-A)") (class "Default")
      (node (ref "IC19") (pin "10") (pinfunction "A_10") (pintype "input"))
      (node (ref "R171") (pin "1") (pinfunction "1_1") (pintype "passive"))
      (node (ref "R212") (pin "1") (pinfunction "1_1") (pintype "passive"))
      (node (ref "R212") (pin "2") (pinfunction "2_2") (pintype "passive"))
      (node (ref "X7") (pin "4") (pinfunction "4_4") (pintype "passive"))
      (node (ref "X8") (pin "2") (pinfunction "S_2") (pintype "passive"))
    )
    (net (code "273") (name "Net-(IC19A-B)") (class "Default")
      (node (ref "IC19") (pin "13") (pinfunction "B_13") (pintype "input"))
      (node (ref "R170") (pin "1") (pinfunction "1_1") (pintype "passive"))
      (node (ref "R211") (pin "1") (pinfunction "1_1") (pintype "passive"))
      (node (ref "R211") (pin "2") (pinfunction "2_2") (pintype "passive"))
      (node (ref "X7") (pin "3") (pinfunction "3_3") (pintype "passive"))
      (node (ref "X8") (pin "3") (pinfunction "S_3") (pintype "passive"))
    )
    (net (code "274") (name "Net-(IC19A-C)") (class "Default")
      (node (ref "IC19") (pin "12") (pinfunction "C_12") (pintype "input"))
      (node (ref "R169") (pin "1") (pinfunction "1_1") (pintype "passive"))
      (node (ref "R210") (pin "1") (pinfunction "1_1") (pintype "passive"))
      (node (ref "R210") (pin "2") (pinfunction "2_2") (pintype "passive"))
      (node (ref "X7") (pin "2") (pinfunction "2_2") (pintype "passive"))
      (node (ref "X8") (pin "4") (pinfunction "S_4") (pintype "passive"))
    )
    (net (code "275") (name "Net-(IC19A-Q0)") (class "Default")
      (node (ref "IC19") (pin "3") (pinfunction "Q0_3") (pintype "output"))
      (node (ref "IC21") (pin "1") (pinfunction "I1_1") (pintype "input"))
      (node (ref "IC21") (pin "2") (pinfunction "I2_2") (pintype "input"))
      (node (ref "Q30") (pin "1") (pinfunction "G_1") (pintype "passive"))
      (node (ref "Q31") (pin "1") (pinfunction "G_1") (pintype "passive"))
    )
    (net (code "276") (name "Net-(IC19A-Q1)") (class "Default")
      (node (ref "IC19") (pin "14") (pinfunction "Q1_14") (pintype "output"))
      (node (ref "IC21") (pin "6") (pinfunction "I6_6") (pintype "input"))
    )
    (net (code "277") (name "Net-(IC19A-Q2)") (class "Default")
      (node (ref "IC19") (pin "2") (pinfunction "Q2_2") (pintype "output"))
      (node (ref "IC21") (pin "7") (pinfunction "I7_7") (pintype "input"))
    )
    (net (code "278") (name "Net-(IC19A-Q3)") (class "Default")
      (node (ref "IC19") (pin "15") (pinfunction "Q3_15") (pintype "output"))
      (node (ref "IC21") (pin "5") (pinfunction "I5_5") (pintype "input"))
    )
    (net (code "279") (name "Net-(IC19A-Q4)") (class "Default")
      (node (ref "IC19") (pin "1") (pinfunction "Q4_1") (pintype "output"))
      (node (ref "IC21") (pin "4") (pinfunction "I4_4") (pintype "input"))
    )
    (net (code "280") (name "Net-(IC19A-Q5)") (class "Default")
      (node (ref "IC19") (pin "6") (pinfunction "Q5_6") (pintype "output"))
      (node (ref "IC21") (pin "3") (pinfunction "I3_3") (pintype "input"))
    )
    (net (code "281") (name "Net-(IC20-ADJ)") (class "Default")
      (node (ref "IC20") (pin "1") (pinfunction "ADJ_1") (pintype "input"))
      (node (ref "R167") (pin "1") (pinfunction "1_1") (pintype "passive"))
      (node (ref "R174") (pin "2") (pinfunction "2_2") (pintype "passive"))
      (node (ref "X7") (pin "7") (pinfunction "7_7") (pintype "passive"))
    )
    (net (code "282") (name "Net-(IC20-VI)") (class "Default")
      (node (ref "IC20") (pin "3") (pinfunction "VI_3") (pintype "input"))
      (node (ref "Q27") (pin "2") (pinfunction "C_2") (pintype "passive"))
    )
    (net (code "283") (name "Net-(IC20-VO)") (class "Default")
      (node (ref "IC20") (pin "2") (pinfunction "VO_2") (pintype "passive"))
      (node (ref "R167") (pin "2") (pinfunction "2_2") (pintype "passive"))
    )
    (net (code "284") (name "Net-(IC21-O1)") (class "Default")
      (node (ref "IC21") (pin "16") (pinfunction "O1_16") (pintype "open_collector"))
      (node (ref "Q30") (pin "3") (pinfunction "D_3") (pintype "passive"))
      (node (ref "R216") (pin "1") (pinfunction "1_1") (pintype "passive"))
    )
    (net (code "285") (name "Net-(IC21-O2)") (class "Default")
      (node (ref "IC21") (pin "15") (pinfunction "O2_15") (pintype "open_collector"))
      (node (ref "R189") (pin "1") (pinfunction "1_1") (pintype "passive"))
    )
    (net (code "286") (name "Net-(IC22A-+IN)") (class "Default")
      (node (ref "IC22") (pin "11") (pinfunction "+IN_11") (pintype "input"))
      (node (ref "IC22") (pin "5") (pinfunction "+IN_5") (pintype "input"))
      (node (ref "R178") (pin "1") (pinfunction "1_1") (pintype "passive"))
      (node (ref "R179") (pin "2") (pinfunction "2_2") (pintype "passive"))
      (node (ref "R180") (pin "2") (pinfunction "2_2") (pintype "passive"))
    )
    (net (code "287") (name "Net-(IC22A--IN)") (class "Default")
      (node (ref "C28") (pin "1") (pinfunction "1_1") (pintype "passive"))
      (node (ref "IC22") (pin "10") (pinfunction "-IN_10") (pintype "input"))
      (node (ref "IC22") (pin "4") (pinfunction "-IN_4") (pintype "input"))
      (node (ref "R177") (pin "1") (pinfunction "1_1") (pintype "passive"))
    )
    (net (code "288") (name "Net-(IC22A-OUT)") (class "Default")
      (node (ref "IC22") (pin "2") (pinfunction "OUT_2") (pintype "open_collector"))
      (node (ref "R180") (pin "1") (pinfunction "1_1") (pintype "passive"))
    )
    (net (code "289") (name "Net-(IC22B-+IN)") (class "Default")
      (node (ref "IC22") (pin "7") (pinfunction "+IN_7") (pintype "input"))
      (node (ref "R175") (pin "1") (pinfunction "1_1") (pintype "passive"))
      (node (ref "R192") (pin "1") (pinfunction "1_1") (pintype "passive"))
    )
    (net (code "290") (name "Net-(IC22B--IN)") (class "Default")
      (node (ref "IC22") (pin "6") (pinfunction "-IN_6") (pintype "input"))
      (node (ref "IC22") (pin "8") (pinfunction "-IN_8") (pintype "input"))
      (node (ref "R174") (pin "1") (pinfunction "1_1") (pintype "passive"))
    )
    (net (code "291") (name "Net-(IC22B-OUT)") (class "Default")
      (node (ref "IC22") (pin "1") (pinfunction "OUT_1") (pintype "open_collector"))
      (node (ref "R176") (pin "2") (pinfunction "2_2") (pintype "passive"))
      (node (ref "R181") (pin "2") (pinfunction "2_2") (pintype "passive"))
    )
    (net (code "292") (name "Net-(IC22C-+IN)") (class "Default")
      (node (ref "C31") (pin "1") (pinfunction "1_1") (pintype "passive"))
      (node (ref "IC22") (pin "9") (pinfunction "+IN_9") (pintype "input"))
      (node (ref "R183") (pin "2") (pinfunction "2_2") (pintype "passive"))
      (node (ref "R192") (pin "2") (pinfunction "2_2") (pintype "passive"))
    )
    (net (code "293") (name "Net-(IC22C-OUT)") (class "Default")
      (node (ref "C32") (pin "2") (pinfunction "2_2") (pintype "passive"))
      (node (ref "IC22") (pin "14") (pinfunction "OUT_14") (pintype "open_collector"))
      (node (ref "R182") (pin "2") (pinfunction "2_2") (pintype "passive"))
    )
    (net (code "294") (name "Net-(IC22D-OUT)") (class "Default")
      (node (ref "IC22") (pin "13") (pinfunction "OUT_13") (pintype "open_collector"))
      (node (ref "JP12") (pin "1") (pinfunction "1_1") (pintype "passive"))
      (node (ref "Q29") (pin "1") (pinfunction "G_1") (pintype "passive"))
      (node (ref "R195") (pin "2") (pinfunction "2_2") (pintype "passive"))
    )
    (net (code "295") (name "Net-(IC24-CV)") (class "Default")
      (node (ref "IC24") (pin "5") (pinfunction "CV_5") (pintype "input"))
      (node (ref "R197") (pin "2") (pinfunction "2_2") (pintype "passive"))
    )
    (net (code "296") (name "Net-(IC24-Q)") (class "Default")
      (node (ref "IC24") (pin "3") (pinfunction "Q_3") (pintype "output"))
      (node (ref "IC25") (pin "12") (pinfunction "A_12") (pintype "input"))
      (node (ref "IC25") (pin "4") (pinfunction "A_4") (pintype "input"))
      (node (ref "R197") (pin "1") (pinfunction "1_1") (pintype "passive"))
    )
    (net (code "297") (name "Net-(IC25A-T2)") (class "Default")
      (node (ref "C37") (pin "2") (pinfunction "2_2") (pintype "passive"))
      (node (ref "IC25") (pin "2") (pinfunction "T2_2") (pintype "input"))
      (node (ref "R218") (pin "1") (pinfunction "1_1") (pintype "passive"))
    )
    (net (code "298") (name "Net-(IC25A-~{Q})") (class "Default")
      (node (ref "IC25") (pin "7") (pinfunction "~{Q}_7") (pintype "output"))
      (node (ref "Q33") (pin "1") (pinfunction "G_1") (pintype "passive"))
    )
    (net (code "299") (name "Net-(IC25B-B)") (class "Default")
      (node (ref "IC25") (pin "11") (pinfunction "B_11") (pintype "input"))
      (node (ref "IC25") (pin "9") (pinfunction "~{Q}_9") (pintype "output"))
      (node (ref "R203") (pin "2") (pinfunction "2_2") (pintype "passive"))
    )
    (net (code "300") (name "Net-(IC25B-T2)") (class "Default")
      (node (ref "C35") (pin "1") (pinfunction "1_1") (pintype "passive"))
      (node (ref "IC25") (pin "14") (pinfunction "T2_14") (pintype "input"))
      (node (ref "R201") (pin "1") (pinfunction "1_1") (pintype "passive"))
    )
    (net (code "301") (name "Net-(IC27A-+IN)") (class "Default")
      (node (ref "C30") (pin "1") (pinfunction "1_1") (pintype "passive"))
      (node (ref "IC27") (pin "3") (pinfunction "+IN_3") (pintype "input"))
      (node (ref "R172") (pin "1") (pinfunction "1_1") (pintype "passive"))
    )
    (net (code "302") (name "Net-(IC27A--IN)") (class "Default")
      (node (ref "IC27") (pin "2") (pinfunction "-IN_2") (pintype "input"))
      (node (ref "R173") (pin "2") (pinfunction "2_2") (pintype "passive"))
    )
    (net (code "303") (name "Net-(IC27A-OUT)") (class "Default")
      (node (ref "IC27") (pin "1") (pinfunction "OUT_1") (pintype "output"))
      (node (ref "R204") (pin "2") (pinfunction "2_2") (pintype "passive"))
    )
    (net (code "304") (name "Net-(IC27B-+IN)") (class "Default")
      (node (ref "IC27") (pin "5") (pinfunction "+IN_5") (pintype "input"))
      (node (ref "Q31") (pin "3") (pinfunction "D_3") (pintype "passive"))
      (node (ref "R205") (pin "2") (pinfunction "2_2") (pintype "passive"))
      (node (ref "R206") (pin "2") (pinfunction "2_2") (pintype "passive"))
    )
    (net (code "305") (name "Net-(IC27B--IN)") (class "Default")
      (node (ref "IC27") (pin "6") (pinfunction "-IN_6") (pintype "input"))
      (node (ref "R207") (pin "1") (pinfunction "1_1") (pintype "passive"))
      (node (ref "R208") (pin "2") (pinfunction "2_2") (pintype "passive"))
    )
    (net (code "306") (name "Net-(IC27B-OUT)") (class "Default")
      (node (ref "IC27") (pin "7") (pinfunction "OUT_7") (pintype "output"))
      (node (ref "R186") (pin "2") (pinfunction "2_2") (pintype "passive"))
      (node (ref "R193") (pin "1") (pinfunction "1_1") (pintype "passive"))
      (node (ref "R206") (pin "1") (pinfunction "1_1") (pintype "passive"))
    )
    (net (code "307") (name "Net-(IC28A-A)") (class "Default")
      (node (ref "IC28") (pin "10") (pinfunction "A_10") (pintype "input"))
      (node (ref "R226") (pin "1") (pinfunction "1_1") (pintype "passive"))
      (node (ref "R267") (pin "1") (pinfunction "1_1") (pintype "passive"))
      (node (ref "R267") (pin "2") (pinfunction "2_2") (pintype "passive"))
      (node (ref "X10") (pin "4") (pinfunction "4_4") (pintype "passive"))
      (node (ref "X11") (pin "2") (pinfunction "S_2") (pintype "passive"))
    )
    (net (code "308") (name "Net-(IC28A-B)") (class "Default")
      (node (ref "IC28") (pin "13") (pinfunction "B_13") (pintype "input"))
      (node (ref "R225") (pin "1") (pinfunction "1_1") (pintype "passive"))
      (node (ref "R266") (pin "1") (pinfunction "1_1") (pintype "passive"))
      (node (ref "R266") (pin "2") (pinfunction "2_2") (pintype "passive"))
      (node (ref "X10") (pin "3") (pinfunction "3_3") (pintype "passive"))
      (node (ref "X11") (pin "3") (pinfunction "S_3") (pintype "passive"))
    )
    (net (code "309") (name "Net-(IC28A-C)") (class "Default")
      (node (ref "IC28") (pin "12") (pinfunction "C_12") (pintype "input"))
      (node (ref "R224") (pin "1") (pinfunction "1_1") (pintype "passive"))
      (node (ref "R265") (pin "1") (pinfunction "1_1") (pintype "passive"))
      (node (ref "R265") (pin "2") (pinfunction "2_2") (pintype "passive"))
      (node (ref "X10") (pin "2") (pinfunction "2_2") (pintype "passive"))
      (node (ref "X11") (pin "4") (pinfunction "S_4") (pintype "passive"))
    )
    (net (code "310") (name "Net-(IC28A-Q0)") (class "Default")
      (node (ref "IC28") (pin "3") (pinfunction "Q0_3") (pintype "output"))
      (node (ref "IC30") (pin "1") (pinfunction "I1_1") (pintype "input"))
      (node (ref "IC30") (pin "2") (pinfunction "I2_2") (pintype "input"))
      (node (ref "Q40") (pin "1") (pinfunction "G_1") (pintype "passive"))
      (node (ref "Q41") (pin "1") (pinfunction "G_1") (pintype "passive"))
    )
    (net (code "311") (name "Net-(IC28A-Q1)") (class "Default")
      (node (ref "IC28") (pin "14") (pinfunction "Q1_14") (pintype "output"))
      (node (ref "IC30") (pin "6") (pinfunction "I6_6") (pintype "input"))
    )
    (net (code "312") (name "Net-(IC28A-Q2)") (class "Default")
      (node (ref "IC28") (pin "2") (pinfunction "Q2_2") (pintype "output"))
      (node (ref "IC30") (pin "7") (pinfunction "I7_7") (pintype "input"))
    )
    (net (code "313") (name "Net-(IC28A-Q3)") (class "Default")
      (node (ref "IC28") (pin "15") (pinfunction "Q3_15") (pintype "output"))
      (node (ref "IC30") (pin "5") (pinfunction "I5_5") (pintype "input"))
    )
    (net (code "314") (name "Net-(IC28A-Q4)") (class "Default")
      (node (ref "IC28") (pin "1") (pinfunction "Q4_1") (pintype "output"))
      (node (ref "IC30") (pin "4") (pinfunction "I4_4") (pintype "input"))
    )
    (net (code "315") (name "Net-(IC28A-Q5)") (class "Default")
      (node (ref "IC28") (pin "6") (pinfunction "Q5_6") (pintype "output"))
      (node (ref "IC30") (pin "3") (pinfunction "I3_3") (pintype "input"))
    )
    (net (code "316") (name "Net-(IC29-ADJ)") (class "Default")
      (node (ref "IC29") (pin "1") (pinfunction "ADJ_1") (pintype "input"))
      (node (ref "R222") (pin "1") (pinfunction "1_1") (pintype "passive"))
      (node (ref "R229") (pin "2") (pinfunction "2_2") (pintype "passive"))
      (node (ref "X10") (pin "7") (pinfunction "7_7") (pintype "passive"))
    )
    (net (code "317") (name "Net-(IC29-VI)") (class "Default")
      (node (ref "IC29") (pin "3") (pinfunction "VI_3") (pintype "input"))
      (node (ref "Q37") (pin "2") (pinfunction "C_2") (pintype "passive"))
    )
    (net (code "318") (name "Net-(IC29-VO)") (class "Default")
      (node (ref "IC29") (pin "2") (pinfunction "VO_2") (pintype "passive"))
      (node (ref "R222") (pin "2") (pinfunction "2_2") (pintype "passive"))
    )
    (net (code "319") (name "Net-(IC30-O1)") (class "Default")
      (node (ref "IC30") (pin "16") (pinfunction "O1_16") (pintype "open_collector"))
      (node (ref "Q40") (pin "3") (pinfunction "D_3") (pintype "passive"))
      (node (ref "R271") (pin "1") (pinfunction "1_1") (pintype "passive"))
    )
    (net (code "320") (name "Net-(IC30-O2)") (class "Default")
      (node (ref "IC30") (pin "15") (pinfunction "O2_15") (pintype "open_collector"))
      (node (ref "R244") (pin "1") (pinfunction "1_1") (pintype "passive"))
    )
    (net (code "321") (name "Net-(IC31A-+IN)") (class "Default")
      (node (ref "IC31") (pin "11") (pinfunction "+IN_11") (pintype "input"))
      (node (ref "IC31") (pin "5") (pinfunction "+IN_5") (pintype "input"))
      (node (ref "R233") (pin "1") (pinfunction "1_1") (pintype "passive"))
      (node (ref "R234") (pin "2") (pinfunction "2_2") (pintype "passive"))
      (node (ref "R235") (pin "2") (pinfunction "2_2") (pintype "passive"))
    )
    (net (code "322") (name "Net-(IC31A--IN)") (class "Default")
      (node (ref "C40") (pin "1") (pinfunction "1_1") (pintype "passive"))
      (node (ref "IC31") (pin "10") (pinfunction "-IN_10") (pintype "input"))
      (node (ref "IC31") (pin "4") (pinfunction "-IN_4") (pintype "input"))
      (node (ref "R232") (pin "1") (pinfunction "1_1") (pintype "passive"))
    )
    (net (code "323") (name "Net-(IC31A-OUT)") (class "Default")
      (node (ref "IC31") (pin "2") (pinfunction "OUT_2") (pintype "open_collector"))
      (node (ref "R235") (pin "1") (pinfunction "1_1") (pintype "passive"))
    )
    (net (code "324") (name "Net-(IC31B-+IN)") (class "Default")
      (node (ref "IC31") (pin "7") (pinfunction "+IN_7") (pintype "input"))
      (node (ref "R230") (pin "1") (pinfunction "1_1") (pintype "passive"))
      (node (ref "R247") (pin "1") (pinfunction "1_1") (pintype "passive"))
    )
    (net (code "325") (name "Net-(IC31B--IN)") (class "Default")
      (node (ref "IC31") (pin "6") (pinfunction "-IN_6") (pintype "input"))
      (node (ref "IC31") (pin "8") (pinfunction "-IN_8") (pintype "input"))
      (node (ref "R229") (pin "1") (pinfunction "1_1") (pintype "passive"))
    )
    (net (code "326") (name "Net-(IC31B-OUT)") (class "Default")
      (node (ref "IC31") (pin "1") (pinfunction "OUT_1") (pintype "open_collector"))
      (node (ref "R231") (pin "2") (pinfunction "2_2") (pintype "passive"))
      (node (ref "R236") (pin "2") (pinfunction "2_2") (pintype "passive"))
    )
    (net (code "327") (name "Net-(IC31C-+IN)") (class "Default")
      (node (ref "C43") (pin "1") (pinfunction "1_1") (pintype "passive"))
      (node (ref "IC31") (pin "9") (pinfunction "+IN_9") (pintype "input"))
      (node (ref "R238") (pin "2") (pinfunction "2_2") (pintype "passive"))
      (node (ref "R247") (pin "2") (pinfunction "2_2") (pintype "passive"))
    )
    (net (code "328") (name "Net-(IC31C-OUT)") (class "Default")
      (node (ref "C44") (pin "2") (pinfunction "2_2") (pintype "passive"))
      (node (ref "IC31") (pin "14") (pinfunction "OUT_14") (pintype "open_collector"))
      (node (ref "R237") (pin "2") (pinfunction "2_2") (pintype "passive"))
    )
    (net (code "329") (name "Net-(IC31D-OUT)") (class "Default")
      (node (ref "IC31") (pin "13") (pinfunction "OUT_13") (pintype "open_collector"))
      (node (ref "JP17") (pin "1") (pinfunction "1_1") (pintype "passive"))
      (node (ref "Q39") (pin "1") (pinfunction "G_1") (pintype "passive"))
      (node (ref "R250") (pin "2") (pinfunction "2_2") (pintype "passive"))
    )
    (net (code "330") (name "Net-(IC33-CV)") (class "Default")
      (node (ref "IC33") (pin "5") (pinfunction "CV_5") (pintype "input"))
      (node (ref "R252") (pin "2") (pinfunction "2_2") (pintype "passive"))
    )
    (net (code "331") (name "Net-(IC33-Q)") (class "Default")
      (node (ref "IC33") (pin "3") (pinfunction "Q_3") (pintype "output"))
      (node (ref "IC34") (pin "12") (pinfunction "A_12") (pintype "input"))
      (node (ref "IC34") (pin "4") (pinfunction "A_4") (pintype "input"))
      (node (ref "R252") (pin "1") (pinfunction "1_1") (pintype "passive"))
    )
    (net (code "332") (name "Net-(IC34A-T2)") (class "Default")
      (node (ref "C49") (pin "2") (pinfunction "2_2") (pintype "passive"))
      (node (ref "IC34") (pin "2") (pinfunction "T2_2") (pintype "input"))
      (node (ref "R273") (pin "1") (pinfunction "1_1") (pintype "passive"))
    )
    (net (code "333") (name "Net-(IC34A-~{Q})") (class "Default")
      (node (ref "IC34") (pin "7") (pinfunction "~{Q}_7") (pintype "output"))
      (node (ref "Q43") (pin "1") (pinfunction "G_1") (pintype "passive"))
    )
    (net (code "334") (name "Net-(IC34B-B)") (class "Default")
      (node (ref "IC34") (pin "11") (pinfunction "B_11") (pintype "input"))
      (node (ref "IC34") (pin "9") (pinfunction "~{Q}_9") (pintype "output"))
      (node (ref "R258") (pin "2") (pinfunction "2_2") (pintype "passive"))
    )
    (net (code "335") (name "Net-(IC34B-T2)") (class "Default")
      (node (ref "C47") (pin "1") (pinfunction "1_1") (pintype "passive"))
      (node (ref "IC34") (pin "14") (pinfunction "T2_14") (pintype "input"))
      (node (ref "R256") (pin "1") (pinfunction "1_1") (pintype "passive"))
    )
    (net (code "336") (name "Net-(IC36A-+IN)") (class "Default")
      (node (ref "C42") (pin "1") (pinfunction "1_1") (pintype "passive"))
      (node (ref "IC36") (pin "3") (pinfunction "+IN_3") (pintype "input"))
      (node (ref "R227") (pin "1") (pinfunction "1_1") (pintype "passive"))
    )
    (net (code "337") (name "Net-(IC36A--IN)") (class "Default")
      (node (ref "IC36") (pin "2") (pinfunction "-IN_2") (pintype "input"))
      (node (ref "R228") (pin "2") (pinfunction "2_2") (pintype "passive"))
    )
    (net (code "338") (name "Net-(IC36A-OUT)") (class "Default")
      (node (ref "IC36") (pin "1") (pinfunction "OUT_1") (pintype "output"))
      (node (ref "R259") (pin "2") (pinfunction "2_2") (pintype "passive"))
    )
    (net (code "339") (name "Net-(IC36B-+IN)") (class "Default")
      (node (ref "IC36") (pin "5") (pinfunction "+IN_5") (pintype "input"))
      (node (ref "Q41") (pin "3") (pinfunction "D_3") (pintype "passive"))
      (node (ref "R260") (pin "2") (pinfunction "2_2") (pintype "passive"))
      (node (ref "R261") (pin "2") (pinfunction "2_2") (pintype "passive"))
    )
    (net (code "340") (name "Net-(IC36B--IN)") (class "Default")
      (node (ref "IC36") (pin "6") (pinfunction "-IN_6") (pintype "input"))
      (node (ref "R262") (pin "1") (pinfunction "1_1") (pintype "passive"))
      (node (ref "R263") (pin "2") (pinfunction "2_2") (pintype "passive"))
    )
    (net (code "341") (name "Net-(IC36B-OUT)") (class "Default")
      (node (ref "IC36") (pin "7") (pinfunction "OUT_7") (pintype "output"))
      (node (ref "R241") (pin "2") (pinfunction "2_2") (pintype "passive"))
      (node (ref "R248") (pin "1") (pinfunction "1_1") (pintype "passive"))
      (node (ref "R261") (pin "1") (pinfunction "1_1") (pintype "passive"))
    )
    (net (code "342") (name "Net-(IC37A-A)") (class "Default")
      (node (ref "IC37") (pin "10") (pinfunction "A_10") (pintype "input"))
      (node (ref "R281") (pin "1") (pinfunction "1_1") (pintype "passive"))
      (node (ref "R322") (pin "1") (pinfunction "1_1") (pintype "passive"))
      (node (ref "R322") (pin "2") (pinfunction "2_2") (pintype "passive"))
      (node (ref "X13") (pin "4") (pinfunction "4_4") (pintype "passive"))
      (node (ref "X14") (pin "2") (pinfunction "S_2") (pintype "passive"))
    )
    (net (code "343") (name "Net-(IC37A-B)") (class "Default")
      (node (ref "IC37") (pin "13") (pinfunction "B_13") (pintype "input"))
      (node (ref "R280") (pin "1") (pinfunction "1_1") (pintype "passive"))
      (node (ref "R321") (pin "1") (pinfunction "1_1") (pintype "passive"))
      (node (ref "R321") (pin "2") (pinfunction "2_2") (pintype "passive"))
      (node (ref "X13") (pin "3") (pinfunction "3_3") (pintype "passive"))
      (node (ref "X14") (pin "3") (pinfunction "S_3") (pintype "passive"))
    )
    (net (code "344") (name "Net-(IC37A-C)") (class "Default")
      (node (ref "IC37") (pin "12") (pinfunction "C_12") (pintype "input"))
      (node (ref "R279") (pin "1") (pinfunction "1_1") (pintype "passive"))
      (node (ref "R320") (pin "1") (pinfunction "1_1") (pintype "passive"))
      (node (ref "R320") (pin "2") (pinfunction "2_2") (pintype "passive"))
      (node (ref "X13") (pin "2") (pinfunction "2_2") (pintype "passive"))
      (node (ref "X14") (pin "4") (pinfunction "S_4") (pintype "passive"))
    )
    (net (code "345") (name "Net-(IC37A-Q0)") (class "Default")
      (node (ref "IC37") (pin "3") (pinfunction "Q0_3") (pintype "output"))
      (node (ref "IC39") (pin "1") (pinfunction "I1_1") (pintype "input"))
      (node (ref "IC39") (pin "2") (pinfunction "I2_2") (pintype "input"))
      (node (ref "Q50") (pin "1") (pinfunction "G_1") (pintype "passive"))
      (node (ref "Q51") (pin "1") (pinfunction "G_1") (pintype "passive"))
    )
    (net (code "346") (name "Net-(IC37A-Q1)") (class "Default")
      (node (ref "IC37") (pin "14") (pinfunction "Q1_14") (pintype "output"))
      (node (ref "IC39") (pin "6") (pinfunction "I6_6") (pintype "input"))
    )
    (net (code "347") (name "Net-(IC37A-Q2)") (class "Default")
      (node (ref "IC37") (pin "2") (pinfunction "Q2_2") (pintype "output"))
      (node (ref "IC39") (pin "7") (pinfunction "I7_7") (pintype "input"))
    )
    (net (code "348") (name "Net-(IC37A-Q3)") (class "Default")
      (node (ref "IC37") (pin "15") (pinfunction "Q3_15") (pintype "output"))
      (node (ref "IC39") (pin "5") (pinfunction "I5_5") (pintype "input"))
    )
    (net (code "349") (name "Net-(IC37A-Q4)") (class "Default")
      (node (ref "IC37") (pin "1") (pinfunction "Q4_1") (pintype "output"))
      (node (ref "IC39") (pin "4") (pinfunction "I4_4") (pintype "input"))
    )
    (net (code "350") (name "Net-(IC37A-Q5)") (class "Default")
      (node (ref "IC37") (pin "6") (pinfunction "Q5_6") (pintype "output"))
      (node (ref "IC39") (pin "3") (pinfunction "I3_3") (pintype "input"))
    )
    (net (code "351") (name "Net-(IC38-ADJ)") (class "Default")
      (node (ref "IC38") (pin "1") (pinfunction "ADJ_1") (pintype "input"))
      (node (ref "R277") (pin "1") (pinfunction "1_1") (pintype "passive"))
      (node (ref "R284") (pin "2") (pinfunction "2_2") (pintype "passive"))
      (node (ref "X13") (pin "7") (pinfunction "7_7") (pintype "passive"))
    )
    (net (code "352") (name "Net-(IC38-VI)") (class "Default")
      (node (ref "IC38") (pin "3") (pinfunction "VI_3") (pintype "input"))
      (node (ref "Q47") (pin "2") (pinfunction "C_2") (pintype "passive"))
    )
    (net (code "353") (name "Net-(IC38-VO)") (class "Default")
      (node (ref "IC38") (pin "2") (pinfunction "VO_2") (pintype "passive"))
      (node (ref "R277") (pin "2") (pinfunction "2_2") (pintype "passive"))
    )
    (net (code "354") (name "Net-(IC39-O1)") (class "Default")
      (node (ref "IC39") (pin "16") (pinfunction "O1_16") (pintype "open_collector"))
      (node (ref "Q50") (pin "3") (pinfunction "D_3") (pintype "passive"))
      (node (ref "R326") (pin "1") (pinfunction "1_1") (pintype "passive"))
    )
    (net (code "355") (name "Net-(IC39-O2)") (class "Default")
      (node (ref "IC39") (pin "15") (pinfunction "O2_15") (pintype "open_collector"))
      (node (ref "R299") (pin "1") (pinfunction "1_1") (pintype "passive"))
    )
    (net (code "356") (name "Net-(IC40A-+IN)") (class "Default")
      (node (ref "IC40") (pin "11") (pinfunction "+IN_11") (pintype "input"))
      (node (ref "IC40") (pin "5") (pinfunction "+IN_5") (pintype "input"))
      (node (ref "R288") (pin "1") (pinfunction "1_1") (pintype "passive"))
      (node (ref "R289") (pin "2") (pinfunction "2_2") (pintype "passive"))
      (node (ref "R290") (pin "2") (pinfunction "2_2") (pintype "passive"))
    )
    (net (code "357") (name "Net-(IC40A--IN)") (class "Default")
      (node (ref "C52") (pin "1") (pinfunction "1_1") (pintype "passive"))
      (node (ref "IC40") (pin "10") (pinfunction "-IN_10") (pintype "input"))
      (node (ref "IC40") (pin "4") (pinfunction "-IN_4") (pintype "input"))
      (node (ref "R287") (pin "1") (pinfunction "1_1") (pintype "passive"))
    )
    (net (code "358") (name "Net-(IC40A-OUT)") (class "Default")
      (node (ref "IC40") (pin "2") (pinfunction "OUT_2") (pintype "open_collector"))
      (node (ref "R290") (pin "1") (pinfunction "1_1") (pintype "passive"))
    )
    (net (code "359") (name "Net-(IC40B-+IN)") (class "Default")
      (node (ref "IC40") (pin "7") (pinfunction "+IN_7") (pintype "input"))
      (node (ref "R285") (pin "1") (pinfunction "1_1") (pintype "passive"))
      (node (ref "R302") (pin "1") (pinfunction "1_1") (pintype "passive"))
    )
    (net (code "360") (name "Net-(IC40B--IN)") (class "Default")
      (node (ref "IC40") (pin "6") (pinfunction "-IN_6") (pintype "input"))
      (node (ref "IC40") (pin "8") (pinfunction "-IN_8") (pintype "input"))
      (node (ref "R284") (pin "1") (pinfunction "1_1") (pintype "passive"))
    )
    (net (code "361") (name "Net-(IC40B-OUT)") (class "Default")
      (node (ref "IC40") (pin "1") (pinfunction "OUT_1") (pintype "open_collector"))
      (node (ref "R286") (pin "2") (pinfunction "2_2") (pintype "passive"))
      (node (ref "R291") (pin "2") (pinfunction "2_2") (pintype "passive"))
    )
    (net (code "362") (name "Net-(IC40C-+IN)") (class "Default")
      (node (ref "C55") (pin "1") (pinfunction "1_1") (pintype "passive"))
      (node (ref "IC40") (pin "9") (pinfunction "+IN_9") (pintype "input"))
      (node (ref "R293") (pin "2") (pinfunction "2_2") (pintype "passive"))
      (node (ref "R302") (pin "2") (pinfunction "2_2") (pintype "passive"))
    )
    (net (code "363") (name "Net-(IC40C-OUT)") (class "Default")
      (node (ref "C56") (pin "2") (pinfunction "2_2") (pintype "passive"))
      (node (ref "IC40") (pin "14") (pinfunction "OUT_14") (pintype "open_collector"))
      (node (ref "R292") (pin "2") (pinfunction "2_2") (pintype "passive"))
    )
    (net (code "364") (name "Net-(IC40D-OUT)") (class "Default")
      (node (ref "IC40") (pin "13") (pinfunction "OUT_13") (pintype "open_collector"))
      (node (ref "JP22") (pin "1") (pinfunction "1_1") (pintype "passive"))
      (node (ref "Q49") (pin "1") (pinfunction "G_1") (pintype "passive"))
      (node (ref "R305") (pin "2") (pinfunction "2_2") (pintype "passive"))
    )
    (net (code "365") (name "Net-(IC42-CV)") (class "Default")
      (node (ref "IC42") (pin "5") (pinfunction "CV_5") (pintype "input"))
      (node (ref "R307") (pin "2") (pinfunction "2_2") (pintype "passive"))
    )
    (net (code "366") (name "Net-(IC42-Q)") (class "Default")
      (node (ref "IC42") (pin "3") (pinfunction "Q_3") (pintype "output"))
      (node (ref "IC43") (pin "12") (pinfunction "A_12") (pintype "input"))
      (node (ref "IC43") (pin "4") (pinfunction "A_4") (pintype "input"))
      (node (ref "R307") (pin "1") (pinfunction "1_1") (pintype "passive"))
    )
    (net (code "367") (name "Net-(IC43A-T2)") (class "Default")
      (node (ref "C61") (pin "2") (pinfunction "2_2") (pintype "passive"))
      (node (ref "IC43") (pin "2") (pinfunction "T2_2") (pintype "input"))
      (node (ref "R328") (pin "1") (pinfunction "1_1") (pintype "passive"))
    )
    (net (code "368") (name "Net-(IC43A-~{Q})") (class "Default")
      (node (ref "IC43") (pin "7") (pinfunction "~{Q}_7") (pintype "output"))
      (node (ref "Q53") (pin "1") (pinfunction "G_1") (pintype "passive"))
    )
    (net (code "369") (name "Net-(IC43B-B)") (class "Default")
      (node (ref "IC43") (pin "11") (pinfunction "B_11") (pintype "input"))
      (node (ref "IC43") (pin "9") (pinfunction "~{Q}_9") (pintype "output"))
      (node (ref "R313") (pin "2") (pinfunction "2_2") (pintype "passive"))
    )
    (net (code "370") (name "Net-(IC43B-T2)") (class "Default")
      (node (ref "C59") (pin "1") (pinfunction "1_1") (pintype "passive"))
      (node (ref "IC43") (pin "14") (pinfunction "T2_14") (pintype "input"))
      (node (ref "R311") (pin "1") (pinfunction "1_1") (pintype "passive"))
    )
    (net (code "371") (name "Net-(IC45A-+IN)") (class "Default")
      (node (ref "C54") (pin "1") (pinfunction "1_1") (pintype "passive"))
      (node (ref "IC45") (pin "3") (pinfunction "+IN_3") (pintype "input"))
      (node (ref "R282") (pin "1") (pinfunction "1_1") (pintype "passive"))
    )
    (net (code "372") (name "Net-(IC45A--IN)") (class "Default")
      (node (ref "IC45") (pin "2") (pinfunction "-IN_2") (pintype "input"))
      (node (ref "R283") (pin "2") (pinfunction "2_2") (pintype "passive"))
    )
    (net (code "373") (name "Net-(IC45A-OUT)") (class "Default")
      (node (ref "IC45") (pin "1") (pinfunction "OUT_1") (pintype "output"))
      (node (ref "R314") (pin "2") (pinfunction "2_2") (pintype "passive"))
    )
    (net (code "374") (name "Net-(IC45B-+IN)") (class "Default")
      (node (ref "IC45") (pin "5") (pinfunction "+IN_5") (pintype "input"))
      (node (ref "Q51") (pin "3") (pinfunction "D_3") (pintype "passive"))
      (node (ref "R315") (pin "2") (pinfunction "2_2") (pintype "passive"))
      (node (ref "R316") (pin "2") (pinfunction "2_2") (pintype "passive"))
    )
    (net (code "375") (name "Net-(IC45B--IN)") (class "Default")
      (node (ref "IC45") (pin "6") (pinfunction "-IN_6") (pintype "input"))
      (node (ref "R317") (pin "1") (pinfunction "1_1") (pintype "passive"))
      (node (ref "R318") (pin "2") (pinfunction "2_2") (pintype "passive"))
    )
    (net (code "376") (name "Net-(IC45B-OUT)") (class "Default")
      (node (ref "IC45") (pin "7") (pinfunction "OUT_7") (pintype "output"))
      (node (ref "R296") (pin "2") (pinfunction "2_2") (pintype "passive"))
      (node (ref "R303") (pin "1") (pinfunction "1_1") (pintype "passive"))
      (node (ref "R316") (pin "1") (pinfunction "1_1") (pintype "passive"))
    )
    (net (code "377") (name "Net-(IC101A-+IN)") (class "Default")
      (node (ref "C101") (pin "1") (pinfunction "1_1") (pintype "passive"))
      (node (ref "IC101") (pin "3") (pinfunction "+IN_3") (pintype "input"))
      (node (ref "R105") (pin "1") (pinfunction "1_1") (pintype "passive"))
    )
    (net (code "378") (name "Net-(IC101A--IN)") (class "Default")
      (node (ref "IC101") (pin "2") (pinfunction "-IN_2") (pintype "input"))
      (node (ref "R107") (pin "2") (pinfunction "2_2") (pintype "passive"))
    )
    (net (code "379") (name "Net-(IC101A-OUT)") (class "Default")
      (node (ref "IC101") (pin "1") (pinfunction "OUT_1") (pintype "output"))
      (node (ref "R108") (pin "2") (pinfunction "2_2") (pintype "passive"))
    )
    (net (code "380") (name "Net-(IC101B-+IN)") (class "Default")
      (node (ref "IC101") (pin "5") (pinfunction "+IN_5") (pintype "input"))
      (node (ref "Q1") (pin "3") (pinfunction "D_3") (pintype "passive"))
      (node (ref "R112") (pin "2") (pinfunction "2_2") (pintype "passive"))
      (node (ref "R117") (pin "2") (pinfunction "2_2") (pintype "passive"))
    )
    (net (code "381") (name "Net-(IC101B--IN)") (class "Default")
      (node (ref "IC101") (pin "6") (pinfunction "-IN_6") (pintype "input"))
      (node (ref "R113") (pin "1") (pinfunction "1_1") (pintype "passive"))
      (node (ref "R114") (pin "2") (pinfunction "2_2") (pintype "passive"))
    )
    (net (code "382") (name "Net-(IC101B-OUT)") (class "Default")
      (node (ref "IC101") (pin "7") (pinfunction "OUT_7") (pintype "output"))
      (node (ref "R115") (pin "2") (pinfunction "2_2") (pintype "passive"))
      (node (ref "R116") (pin "1") (pinfunction "1_1") (pintype "passive"))
      (node (ref "R117") (pin "1") (pinfunction "1_1") (pintype "passive"))
    )
    (net (code "383") (name "Net-(IC105A-A)") (class "Default")
      (node (ref "IC105") (pin "10") (pinfunction "A_10") (pintype "input"))
      (node (ref "R111") (pin "1") (pinfunction "1_1") (pintype "passive"))
      (node (ref "R3") (pin "1") (pinfunction "1_1") (pintype "passive"))
      (node (ref "R3") (pin "2") (pinfunction "2_2") (pintype "passive"))
      (node (ref "X101") (pin "4") (pinfunction "4_4") (pintype "passive"))
      (node (ref "X103") (pin "2") (pinfunction "S_2") (pintype "passive"))
    )
    (net (code "384") (name "Net-(IC105A-B)") (class "Default")
      (node (ref "IC105") (pin "13") (pinfunction "B_13") (pintype "input"))
      (node (ref "R110") (pin "1") (pinfunction "1_1") (pintype "passive"))
      (node (ref "R2") (pin "1") (pinfunction "1_1") (pintype "passive"))
      (node (ref "R2") (pin "2") (pinfunction "2_2") (pintype "passive"))
      (node (ref "X101") (pin "3") (pinfunction "3_3") (pintype "passive"))
      (node (ref "X103") (pin "3") (pinfunction "S_3") (pintype "passive"))
    )
    (net (code "385") (name "Net-(IC105A-C)") (class "Default")
      (node (ref "IC105") (pin "12") (pinfunction "C_12") (pintype "input"))
      (node (ref "R1") (pin "1") (pinfunction "1_1") (pintype "passive"))
      (node (ref "R1") (pin "2") (pinfunction "2_2") (pintype "passive"))
      (node (ref "R109") (pin "1") (pinfunction "1_1") (pintype "passive"))
      (node (ref "X101") (pin "2") (pinfunction "2_2") (pintype "passive"))
      (node (ref "X103") (pin "4") (pinfunction "S_4") (pintype "passive"))
    )
    (net (code "386") (name "Net-(IC105A-Q0)") (class "Default")
      (node (ref "IC105") (pin "3") (pinfunction "Q0_3") (pintype "output"))
      (node (ref "IC107") (pin "1") (pinfunction "I1_1") (pintype "input"))
      (node (ref "IC107") (pin "2") (pinfunction "I2_2") (pintype "input"))
      (node (ref "Q1") (pin "1") (pinfunction "G_1") (pintype "passive"))
      (node (ref "Q106") (pin "1") (pinfunction "G_1") (pintype "passive"))
    )
    (net (code "387") (name "Net-(IC105A-Q1)") (class "Default")
      (node (ref "IC105") (pin "14") (pinfunction "Q1_14") (pintype "output"))
      (node (ref "IC107") (pin "6") (pinfunction "I6_6") (pintype "input"))
    )
    (net (code "388") (name "Net-(IC105A-Q2)") (class "Default")
      (node (ref "IC105") (pin "2") (pinfunction "Q2_2") (pintype "output"))
      (node (ref "IC107") (pin "7") (pinfunction "I7_7") (pintype "input"))
    )
    (net (code "389") (name "Net-(IC105A-Q3)") (class "Default")
      (node (ref "IC105") (pin "15") (pinfunction "Q3_15") (pintype "output"))
      (node (ref "IC107") (pin "5") (pinfunction "I5_5") (pintype "input"))
    )
    (net (code "390") (name "Net-(IC105A-Q4)") (class "Default")
      (node (ref "IC105") (pin "1") (pinfunction "Q4_1") (pintype "output"))
      (node (ref "IC107") (pin "4") (pinfunction "I4_4") (pintype "input"))
    )
    (net (code "391") (name "Net-(IC105A-Q5)") (class "Default")
      (node (ref "IC105") (pin "6") (pinfunction "Q5_6") (pintype "output"))
      (node (ref "IC107") (pin "3") (pinfunction "I3_3") (pintype "input"))
    )
    (net (code "392") (name "Net-(IC107-O1)") (class "Default")
      (node (ref "IC107") (pin "16") (pinfunction "O1_16") (pintype "open_collector"))
      (node (ref "Q106") (pin "3") (pinfunction "D_3") (pintype "passive"))
      (node (ref "R9") (pin "1") (pinfunction "1_1") (pintype "passive"))
    )
    (net (code "393") (name "Net-(IC107-O2)") (class "Default")
      (node (ref "IC107") (pin "15") (pinfunction "O2_15") (pintype "open_collector"))
      (node (ref "R128") (pin "1") (pinfunction "1_1") (pintype "passive"))
    )
    (net (code "394") (name "Net-(IC108A-+IN)") (class "Default")
      (node (ref "IC108") (pin "11") (pinfunction "+IN_11") (pintype "input"))
      (node (ref "IC108") (pin "5") (pinfunction "+IN_5") (pintype "input"))
      (node (ref "R131") (pin "1") (pinfunction "1_1") (pintype "passive"))
      (node (ref "R132") (pin "2") (pinfunction "2_2") (pintype "passive"))
      (node (ref "R133") (pin "2") (pinfunction "2_2") (pintype "passive"))
    )
    (net (code "395") (name "Net-(IC108A--IN)") (class "Default")
      (node (ref "C108") (pin "1") (pinfunction "1_1") (pintype "passive"))
      (node (ref "IC108") (pin "10") (pinfunction "-IN_10") (pintype "input"))
      (node (ref "IC108") (pin "4") (pinfunction "-IN_4") (pintype "input"))
      (node (ref "R130") (pin "1") (pinfunction "1_1") (pintype "passive"))
    )
    (net (code "396") (name "Net-(IC108A-OUT)") (class "Default")
      (node (ref "IC108") (pin "2") (pinfunction "OUT_2") (pintype "open_collector"))
      (node (ref "R133") (pin "1") (pinfunction "1_1") (pintype "passive"))
    )
    (net (code "397") (name "Net-(IC108B-+IN)") (class "Default")
      (node (ref "IC108") (pin "7") (pinfunction "+IN_7") (pintype "input"))
      (node (ref "R121") (pin "1") (pinfunction "1_1") (pintype "passive"))
      (node (ref "R122") (pin "1") (pinfunction "1_1") (pintype "passive"))
    )
    (net (code "398") (name "Net-(IC108B--IN)") (class "Default")
      (node (ref "IC108") (pin "6") (pinfunction "-IN_6") (pintype "input"))
      (node (ref "IC108") (pin "8") (pinfunction "-IN_8") (pintype "input"))
      (node (ref "R120") (pin "1") (pinfunction "1_1") (pintype "passive"))
    )
    (net (code "399") (name "Net-(IC108B-OUT)") (class "Default")
      (node (ref "IC108") (pin "1") (pinfunction "OUT_1") (pintype "open_collector"))
      (node (ref "R124") (pin "2") (pinfunction "2_2") (pintype "passive"))
      (node (ref "R125") (pin "2") (pinfunction "2_2") (pintype "passive"))
    )
    (net (code "400") (name "Net-(IC108C-+IN)") (class "Default")
      (node (ref "C105") (pin "1") (pinfunction "1_1") (pintype "passive"))
      (node (ref "IC108") (pin "9") (pinfunction "+IN_9") (pintype "input"))
      (node (ref "R122") (pin "2") (pinfunction "2_2") (pintype "passive"))
      (node (ref "R123") (pin "2") (pinfunction "2_2") (pintype "passive"))
    )
    (net (code "401") (name "Net-(IC108C-OUT)") (class "Default")
      (node (ref "C106") (pin "2") (pinfunction "2_2") (pintype "passive"))
      (node (ref "IC108") (pin "14") (pinfunction "OUT_14") (pintype "open_collector"))
      (node (ref "R126") (pin "2") (pinfunction "2_2") (pintype "passive"))
    )
    (net (code "402") (name "Net-(IC108D-OUT)") (class "Default")
      (node (ref "IC108") (pin "13") (pinfunction "OUT_13") (pintype "open_collector"))
      (node (ref "JP105") (pin "1") (pinfunction "1_1") (pintype "passive"))
      (node (ref "Q107") (pin "1") (pinfunction "G_1") (pintype "passive"))
      (node (ref "R135") (pin "2") (pinfunction "2_2") (pintype "passive"))
    )
    (net (code "403") (name "Net-(IC109-ADJ)") (class "Default")
      (node (ref "IC109") (pin "1") (pinfunction "ADJ_1") (pintype "input"))
      (node (ref "R120") (pin "2") (pinfunction "2_2") (pintype "passive"))
      (node (ref "R134") (pin "1") (pinfunction "1_1") (pintype "passive"))
      (node (ref "X101") (pin "7") (pinfunction "7_7") (pintype "passive"))
    )
    (net (code "404") (name "Net-(IC109-VI)") (class "Default")
      (node (ref "IC109") (pin "3") (pinfunction "VI_3") (pintype "input"))
      (node (ref "Q105") (pin "2") (pinfunction "C_2") (pintype "passive"))
    )
    (net (code "405") (name "Net-(IC109-VO)") (class "Default")
      (node (ref "IC109") (pin "2") (pinfunction "VO_2") (pintype "passive"))
      (node (ref "R134") (pin "2") (pinfunction "2_2") (pintype "passive"))
    )
    (net (code "406") (name "Net-(IC110-CV)") (class "Default")
      (node (ref "IC110") (pin "5") (pinfunction "CV_5") (pintype "input"))
      (node (ref "R144") (pin "2") (pinfunction "2_2") (pintype "passive"))
    )
    (net (code "407") (name "Net-(IC110-Q)") (class "Default")
      (node (ref "IC110") (pin "3") (pinfunction "Q_3") (pintype "output"))
      (node (ref "IC111") (pin "12") (pinfunction "A_12") (pintype "input"))
      (node (ref "IC111") (pin "4") (pinfunction "A_4") (pintype "input"))
      (node (ref "R144") (pin "1") (pinfunction "1_1") (pintype "passive"))
    )
    (net (code "408") (name "Net-(IC111A-T2)") (class "Default")
      (node (ref "C15") (pin "2") (pinfunction "2_2") (pintype "passive"))
      (node (ref "IC111") (pin "2") (pinfunction "T2_2") (pintype "input"))
      (node (ref "R10") (pin "1") (pinfunction "1_1") (pintype "passive"))
    )
    (net (code "409") (name "Net-(IC111A-~{Q})") (class "Default")
      (node (ref "IC111") (pin "7") (pinfunction "~{Q}_7") (pintype "output"))
      (node (ref "Q3") (pin "1") (pinfunction "G_1") (pintype "passive"))
    )
    (net (code "410") (name "Net-(IC111B-B)") (class "Default")
      (node (ref "IC111") (pin "11") (pinfunction "B_11") (pintype "input"))
      (node (ref "IC111") (pin "9") (pinfunction "~{Q}_9") (pintype "output"))
      (node (ref "R146") (pin "2") (pinfunction "2_2") (pintype "passive"))
    )
    (net (code "411") (name "Net-(IC111B-T2)") (class "Default")
      (node (ref "C110") (pin "1") (pinfunction "1_1") (pintype "passive"))
      (node (ref "IC111") (pin "14") (pinfunction "T2_14") (pintype "input"))
      (node (ref "R145") (pin "1") (pinfunction "1_1") (pintype "passive"))
    )
    (net (code "412") (name "Net-(JP1-Pad1)") (class "Default")
      (node (ref "JP1") (pin "1") (pinfunction "1_1") (pintype "passive"))
      (node (ref "R48") (pin "2") (pinfunction "2_2") (pintype "passive"))
    )
    (net (code "413") (name "Net-(JP2-Pad3)") (class "Default")
      (node (ref "JP2") (pin "3") (pinfunction "3_3") (pintype "passive"))
      (node (ref "R40") (pin "1") (pinfunction "1_1") (pintype "passive"))
    )
    (net (code "414") (name "Net-(JP5-Pad2)") (class "Default")
      (node (ref "JP5") (pin "2") (pinfunction "2_2") (pintype "passive"))
      (node (ref "R45") (pin "2") (pinfunction "2_2") (pintype "passive"))
      (node (ref "R46") (pin "2") (pinfunction "2_2") (pintype "passive"))
      (node (ref "SJ1") (pin "2") (pinfunction "2_2") (pintype "passive"))
    )
    (net (code "415") (name "Net-(JP6-Pad1)") (class "Default")
      (node (ref "JP6") (pin "1") (pinfunction "1_1") (pintype "passive"))
      (node (ref "R147") (pin "2") (pinfunction "2_2") (pintype "passive"))
    )
    (net (code "416") (name "Net-(JP7-Pad3)") (class "Default")
      (node (ref "JP7") (pin "3") (pinfunction "3_3") (pintype "passive"))
      (node (ref "R95") (pin "1") (pinfunction "1_1") (pintype "passive"))
    )
    (net (code "417") (name "Net-(JP10-Pad2)") (class "Default")
      (node (ref "JP10") (pin "2") (pinfunction "2_2") (pintype "passive"))
      (node (ref "R100") (pin "2") (pinfunction "2_2") (pintype "passive"))
      (node (ref "R118") (pin "2") (pinfunction "2_2") (pintype "passive"))
      (node (ref "SJ2") (pin "2") (pinfunction "2_2") (pintype "passive"))
    )
    (net (code "418") (name "Net-(JP11-Pad1)") (class "Default")
      (node (ref "JP11") (pin "1") (pinfunction "1_1") (pintype "passive"))
      (node (ref "R202") (pin "2") (pinfunction "2_2") (pintype "passive"))
    )
    (net (code "419") (name "Net-(JP12-Pad3)") (class "Default")
      (node (ref "JP12") (pin "3") (pinfunction "3_3") (pintype "passive"))
      (node (ref "R194") (pin "1") (pinfunction "1_1") (pintype "passive"))
    )
    (net (code "420") (name "Net-(JP15-Pad2)") (class "Default")
      (node (ref "JP15") (pin "2") (pinfunction "2_2") (pintype "passive"))
      (node (ref "R199") (pin "2") (pinfunction "2_2") (pintype "passive"))
      (node (ref "R200") (pin "2") (pinfunction "2_2") (pintype "passive"))
      (node (ref "SJ3") (pin "2") (pinfunction "2_2") (pintype "passive"))
    )
    (net (code "421") (name "Net-(JP16-Pad1)") (class "Default")
      (node (ref "JP16") (pin "1") (pinfunction "1_1") (pintype "passive"))
      (node (ref "R257") (pin "2") (pinfunction "2_2") (pintype "passive"))
    )
    (net (code "422") (name "Net-(JP17-Pad3)") (class "Default")
      (node (ref "JP17") (pin "3") (pinfunction "3_3") (pintype "passive"))
      (node (ref "R249") (pin "1") (pinfunction "1_1") (pintype "passive"))
    )
    (net (code "423") (name "Net-(JP20-Pad2)") (class "Default")
      (node (ref "JP20") (pin "2") (pinfunction "2_2") (pintype "passive"))
      (node (ref "R254") (pin "2") (pinfunction "2_2") (pintype "passive"))
      (node (ref "R255") (pin "2") (pinfunction "2_2") (pintype "passive"))
      (node (ref "SJ4") (pin "2") (pinfunction "2_2") (pintype "passive"))
    )
    (net (code "424") (name "Net-(JP21-Pad1)") (class "Default")
      (node (ref "JP21") (pin "1") (pinfunction "1_1") (pintype "passive"))
      (node (ref "R312") (pin "2") (pinfunction "2_2") (pintype "passive"))
    )
    (net (code "425") (name "Net-(JP22-Pad3)") (class "Default")
      (node (ref "JP22") (pin "3") (pinfunction "3_3") (pintype "passive"))
      (node (ref "R304") (pin "1") (pinfunction "1_1") (pintype "passive"))
    )
    (net (code "426") (name "Net-(JP25-Pad2)") (class "Default")
      (node (ref "JP25") (pin "2") (pinfunction "2_2") (pintype "passive"))
      (node (ref "R309") (pin "2") (pinfunction "2_2") (pintype "passive"))
      (node (ref "R310") (pin "2") (pinfunction "2_2") (pintype "passive"))
      (node (ref "SJ5") (pin "2") (pinfunction "2_2") (pintype "passive"))
    )
    (net (code "427") (name "Net-(JP101-Pad1)") (class "Default")
      (node (ref "JP101") (pin "1") (pinfunction "1_1") (pintype "passive"))
      (node (ref "R119") (pin "2") (pinfunction "2_2") (pintype "passive"))
    )
    (net (code "428") (name "Net-(JP104-Pad2)") (class "Default")
      (node (ref "JP104") (pin "2") (pinfunction "2_2") (pintype "passive"))
      (node (ref "R136") (pin "2") (pinfunction "2_2") (pintype "passive"))
      (node (ref "R137") (pin "2") (pinfunction "2_2") (pintype "passive"))
      (node (ref "SJ101") (pin "2") (pinfunction "2_2") (pintype "passive"))
    )
    (net (code "429") (name "Net-(JP105-Pad3)") (class "Default")
      (node (ref "JP105") (pin "3") (pinfunction "3_3") (pintype "passive"))
      (node (ref "R138") (pin "1") (pinfunction "1_1") (pintype "passive"))
    )
    (net (code "430") (name "Net-(LED1-PadA)") (class "Default")
      (node (ref "LED1") (pin "A") (pinfunction "A_A") (pintype "passive"))
      (node (ref "LED2") (pin "A") (pinfunction "A_A") (pintype "passive"))
      (node (ref "LED3") (pin "A") (pinfunction "A_A") (pintype "passive"))
      (node (ref "LED4") (pin "A") (pinfunction "A_A") (pintype "passive"))
      (node (ref "LED6") (pin "A") (pinfunction "A_A") (pintype "passive"))
      (node (ref "R34") (pin "1") (pinfunction "1_1") (pintype "passive"))
    )
    (net (code "431") (name "Net-(LED5-C)") (class "Default")
      (node (ref "LED5") (pin "K") (pinfunction "C_K") (pintype "passive"))
      (node (ref "R33") (pin "1") (pinfunction "1_1") (pintype "passive"))
    )
    (net (code "432") (name "Net-(LED10-PadA)") (class "Default")
      (node (ref "LED10") (pin "A") (pinfunction "A_A") (pintype "passive"))
      (node (ref "LED12") (pin "A") (pinfunction "A_A") (pintype "passive"))
      (node (ref "LED7") (pin "A") (pinfunction "A_A") (pintype "passive"))
      (node (ref "LED8") (pin "A") (pinfunction "A_A") (pintype "passive"))
      (node (ref "LED9") (pin "A") (pinfunction "A_A") (pintype "passive"))
      (node (ref "R89") (pin "1") (pinfunction "1_1") (pintype "passive"))
    )
    (net (code "433") (name "Net-(LED11-C)") (class "Default")
      (node (ref "LED11") (pin "K") (pinfunction "C_K") (pintype "passive"))
      (node (ref "R88") (pin "1") (pinfunction "1_1") (pintype "passive"))
    )
    (net (code "434") (name "Net-(LED13-PadA)") (class "Default")
      (node (ref "LED13") (pin "A") (pinfunction "A_A") (pintype "passive"))
      (node (ref "LED14") (pin "A") (pinfunction "A_A") (pintype "passive"))
      (node (ref "LED15") (pin "A") (pinfunction "A_A") (pintype "passive"))
      (node (ref "LED16") (pin "A") (pinfunction "A_A") (pintype "passive"))
      (node (ref "LED18") (pin "A") (pinfunction "A_A") (pintype "passive"))
      (node (ref "R188") (pin "1") (pinfunction "1_1") (pintype "passive"))
    )
    (net (code "435") (name "Net-(LED17-C)") (class "Default")
      (node (ref "LED17") (pin "K") (pinfunction "C_K") (pintype "passive"))
      (node (ref "R187") (pin "1") (pinfunction "1_1") (pintype "passive"))
    )
    (net (code "436") (name "Net-(LED19-PadA)") (class "Default")
      (node (ref "LED19") (pin "A") (pinfunction "A_A") (pintype "passive"))
      (node (ref "LED20") (pin "A") (pinfunction "A_A") (pintype "passive"))
      (node (ref "LED21") (pin "A") (pinfunction "A_A") (pintype "passive"))
      (node (ref "LED22") (pin "A") (pinfunction "A_A") (pintype "passive"))
      (node (ref "LED24") (pin "A") (pinfunction "A_A") (pintype "passive"))
      (node (ref "R243") (pin "1") (pinfunction "1_1") (pintype "passive"))
    )
    (net (code "437") (name "Net-(LED23-C)") (class "Default")
      (node (ref "LED23") (pin "K") (pinfunction "C_K") (pintype "passive"))
      (node (ref "R242") (pin "1") (pinfunction "1_1") (pintype "passive"))
    )
    (net (code "438") (name "Net-(LED25-PadA)") (class "Default")
      (node (ref "LED25") (pin "A") (pinfunction "A_A") (pintype "passive"))
      (node (ref "LED26") (pin "A") (pinfunction "A_A") (pintype "passive"))
      (node (ref "LED27") (pin "A") (pinfunction "A_A") (pintype "passive"))
      (node (ref "LED28") (pin "A") (pinfunction "A_A") (pintype "passive"))
      (node (ref "LED30") (pin "A") (pinfunction "A_A") (pintype "passive"))
      (node (ref "R298") (pin "1") (pinfunction "1_1") (pintype "passive"))
    )
    (net (code "439") (name "Net-(LED29-C)") (class "Default")
      (node (ref "LED29") (pin "K") (pinfunction "C_K") (pintype "passive"))
      (node (ref "R297") (pin "1") (pinfunction "1_1") (pintype "passive"))
    )
    (net (code "440") (name "Net-(LED101-C)") (class "Default")
      (node (ref "LED101") (pin "K") (pinfunction "C_K") (pintype "passive"))
      (node (ref "R143") (pin "1") (pinfunction "1_1") (pintype "passive"))
    )
    (net (code "441") (name "Net-(LED102-PadA)") (class "Default")
      (node (ref "LED102") (pin "A") (pinfunction "A_A") (pintype "passive"))
      (node (ref "LED103") (pin "A") (pinfunction "A_A") (pintype "passive"))
      (node (ref "LED104") (pin "A") (pinfunction "A_A") (pintype "passive"))
      (node (ref "LED105") (pin "A") (pinfunction "A_A") (pintype "passive"))
      (node (ref "LED106") (pin "A") (pinfunction "A_A") (pintype "passive"))
      (node (ref "R142") (pin "1") (pinfunction "1_1") (pintype "passive"))
    )
    (net (code "442") (name "Net-(Q2-B)") (class "Default")
      (node (ref "Q2") (pin "1") (pinfunction "B_1") (pintype "passive"))
      (node (ref "R8") (pin "1") (pinfunction "1_1") (pintype "passive"))
    )
    (net (code "443") (name "Net-(Q2-C)") (class "Default")
      (node (ref "Q2") (pin "2") (pinfunction "C_2") (pintype "passive"))
      (node (ref "R129") (pin "2") (pinfunction "2_2") (pintype "passive"))
      (node (ref "SJMP") (pin "2") (pinfunction "2_2") (pintype "passive"))
    )
    (net (code "444") (name "Net-(Q3-D)") (class "Default")
      (node (ref "Q3") (pin "3") (pinfunction "D_3") (pintype "passive"))
      (node (ref "R8") (pin "2") (pinfunction "2_2") (pintype "passive"))
    )
    (net (code "445") (name "Net-(Q4-B)") (class "Default")
      (node (ref "Q4") (pin "1") (pinfunction "B_1") (pintype "passive"))
      (node (ref "R35") (pin "2") (pinfunction "2_2") (pintype "passive"))
    )
    (net (code "446") (name "Net-(Q5-B)") (class "Default")
      (node (ref "Q5") (pin "1") (pinfunction "B_1") (pintype "passive"))
      (node (ref "Q5") (pin "2") (pinfunction "C_2") (pintype "passive"))
      (node (ref "Q6") (pin "1") (pinfunction "B_1") (pintype "passive"))
      (node (ref "R30") (pin "1") (pinfunction "1_1") (pintype "passive"))
      (node (ref "R31") (pin "1") (pinfunction "1_1") (pintype "passive"))
      (node (ref "R55") (pin "1") (pinfunction "1_1") (pintype "passive"))
      (node (ref "X3") (pin "2") (pinfunction "S_2") (pintype "passive"))
    )
    (net (code "447") (name "Net-(Q5-E)") (class "Default")
      (node (ref "Q5") (pin "3") (pinfunction "E_3") (pintype "passive"))
      (node (ref "R36") (pin "2") (pinfunction "2_2") (pintype "passive"))
    )
    (net (code "448") (name "Net-(Q6-E)") (class "Default")
      (node (ref "Q6") (pin "3") (pinfunction "E_3") (pintype "passive"))
      (node (ref "R37") (pin "2") (pinfunction "2_2") (pintype "passive"))
    )
    (net (code "449") (name "Net-(Q7-B)") (class "Default")
      (node (ref "Q7") (pin "1") (pinfunction "B_1") (pintype "passive"))
      (node (ref "R28") (pin "1") (pinfunction "1_1") (pintype "passive"))
    )
    (net (code "450") (name "Net-(Q8-B)") (class "Default")
      (node (ref "Q8") (pin "1") (pinfunction "B_1") (pintype "passive"))
      (node (ref "R39") (pin "2") (pinfunction "2_2") (pintype "passive"))
      (node (ref "R60") (pin "1") (pinfunction "1_1") (pintype "passive"))
    )
    (net (code "451") (name "Net-(Q8-E)") (class "Default")
      (node (ref "Q8") (pin "3") (pinfunction "E_3") (pintype "passive"))
      (node (ref "R59") (pin "1") (pinfunction "1_1") (pintype "passive"))
    )
    (net (code "452") (name "Net-(Q9-D)") (class "Default")
      (node (ref "Q9") (pin "3") (pinfunction "D_3") (pintype "passive"))
      (node (ref "R40") (pin "2") (pinfunction "2_2") (pintype "passive"))
    )
    (net (code "453") (name "Net-(Q10-S)") (class "Default")
      (node (ref "Q10") (pin "2") (pinfunction "S_2") (pintype "passive"))
      (node (ref "R61") (pin "2") (pinfunction "2_2") (pintype "passive"))
    )
    (net (code "454") (name "Net-(Q12-B)") (class "Default")
      (node (ref "Q12") (pin "1") (pinfunction "B_1") (pintype "passive"))
      (node (ref "R63") (pin "1") (pinfunction "1_1") (pintype "passive"))
    )
    (net (code "455") (name "Net-(Q12-C)") (class "Default")
      (node (ref "Q12") (pin "2") (pinfunction "C_2") (pintype "passive"))
      (node (ref "R14") (pin "2") (pinfunction "2_2") (pintype "passive"))
      (node (ref "SJMP1") (pin "2") (pinfunction "2_2") (pintype "passive"))
    )
    (net (code "456") (name "Net-(Q13-D)") (class "Default")
      (node (ref "Q13") (pin "3") (pinfunction "D_3") (pintype "passive"))
      (node (ref "R63") (pin "2") (pinfunction "2_2") (pintype "passive"))
    )
    (net (code "457") (name "Net-(Q14-B)") (class "Default")
      (node (ref "Q14") (pin "1") (pinfunction "B_1") (pintype "passive"))
      (node (ref "R90") (pin "2") (pinfunction "2_2") (pintype "passive"))
    )
    (net (code "458") (name "Net-(Q15-B)") (class "Default")
      (node (ref "Q15") (pin "1") (pinfunction "B_1") (pintype "passive"))
      (node (ref "Q15") (pin "2") (pinfunction "C_2") (pintype "passive"))
      (node (ref "Q16") (pin "1") (pinfunction "B_1") (pintype "passive"))
      (node (ref "R154") (pin "1") (pinfunction "1_1") (pintype "passive"))
      (node (ref "R85") (pin "1") (pinfunction "1_1") (pintype "passive"))
      (node (ref "R86") (pin "1") (pinfunction "1_1") (pintype "passive"))
      (node (ref "X6") (pin "2") (pinfunction "S_2") (pintype "passive"))
    )
    (net (code "459") (name "Net-(Q15-E)") (class "Default")
      (node (ref "Q15") (pin "3") (pinfunction "E_3") (pintype "passive"))
      (node (ref "R91") (pin "2") (pinfunction "2_2") (pintype "passive"))
    )
    (net (code "460") (name "Net-(Q16-E)") (class "Default")
      (node (ref "Q16") (pin "3") (pinfunction "E_3") (pintype "passive"))
      (node (ref "R92") (pin "2") (pinfunction "2_2") (pintype "passive"))
    )
    (net (code "461") (name "Net-(Q17-B)") (class "Default")
      (node (ref "Q17") (pin "1") (pinfunction "B_1") (pintype "passive"))
      (node (ref "R83") (pin "1") (pinfunction "1_1") (pintype "passive"))
    )
    (net (code "462") (name "Net-(Q18-B)") (class "Default")
      (node (ref "Q18") (pin "1") (pinfunction "B_1") (pintype "passive"))
      (node (ref "R159") (pin "1") (pinfunction "1_1") (pintype "passive"))
      (node (ref "R94") (pin "2") (pinfunction "2_2") (pintype "passive"))
    )
    (net (code "463") (name "Net-(Q18-E)") (class "Default")
      (node (ref "Q18") (pin "3") (pinfunction "E_3") (pintype "passive"))
      (node (ref "R158") (pin "1") (pinfunction "1_1") (pintype "passive"))
    )
    (net (code "464") (name "Net-(Q19-D)") (class "Default")
      (node (ref "Q19") (pin "3") (pinfunction "D_3") (pintype "passive"))
      (node (ref "R95") (pin "2") (pinfunction "2_2") (pintype "passive"))
    )
    (net (code "465") (name "Net-(Q20-S)") (class "Default")
      (node (ref "Q20") (pin "2") (pinfunction "S_2") (pintype "passive"))
      (node (ref "R160") (pin "2") (pinfunction "2_2") (pintype "passive"))
    )
    (net (code "466") (name "Net-(Q22-B)") (class "Default")
      (node (ref "Q22") (pin "1") (pinfunction "B_1") (pintype "passive"))
      (node (ref "R162") (pin "1") (pinfunction "1_1") (pintype "passive"))
    )
    (net (code "467") (name "Net-(Q22-C)") (class "Default")
      (node (ref "Q22") (pin "2") (pinfunction "C_2") (pintype "passive"))
      (node (ref "R69") (pin "2") (pinfunction "2_2") (pintype "passive"))
      (node (ref "SJMP2") (pin "2") (pinfunction "2_2") (pintype "passive"))
    )
    (net (code "468") (name "Net-(Q23-D)") (class "Default")
      (node (ref "Q23") (pin "3") (pinfunction "D_3") (pintype "passive"))
      (node (ref "R162") (pin "2") (pinfunction "2_2") (pintype "passive"))
    )
    (net (code "469") (name "Net-(Q24-B)") (class "Default")
      (node (ref "Q24") (pin "1") (pinfunction "B_1") (pintype "passive"))
      (node (ref "R189") (pin "2") (pinfunction "2_2") (pintype "passive"))
    )
    (net (code "470") (name "Net-(Q25-B)") (class "Default")
      (node (ref "Q25") (pin "1") (pinfunction "B_1") (pintype "passive"))
      (node (ref "Q25") (pin "2") (pinfunction "C_2") (pintype "passive"))
      (node (ref "Q26") (pin "1") (pinfunction "B_1") (pintype "passive"))
      (node (ref "R184") (pin "1") (pinfunction "1_1") (pintype "passive"))
      (node (ref "R185") (pin "1") (pinfunction "1_1") (pintype "passive"))
      (node (ref "R209") (pin "1") (pinfunction "1_1") (pintype "passive"))
      (node (ref "X9") (pin "2") (pinfunction "S_2") (pintype "passive"))
    )
    (net (code "471") (name "Net-(Q25-E)") (class "Default")
      (node (ref "Q25") (pin "3") (pinfunction "E_3") (pintype "passive"))
      (node (ref "R190") (pin "2") (pinfunction "2_2") (pintype "passive"))
    )
    (net (code "472") (name "Net-(Q26-E)") (class "Default")
      (node (ref "Q26") (pin "3") (pinfunction "E_3") (pintype "passive"))
      (node (ref "R191") (pin "2") (pinfunction "2_2") (pintype "passive"))
    )
    (net (code "473") (name "Net-(Q27-B)") (class "Default")
      (node (ref "Q27") (pin "1") (pinfunction "B_1") (pintype "passive"))
      (node (ref "R182") (pin "1") (pinfunction "1_1") (pintype "passive"))
    )
    (net (code "474") (name "Net-(Q28-B)") (class "Default")
      (node (ref "Q28") (pin "1") (pinfunction "B_1") (pintype "passive"))
      (node (ref "R193") (pin "2") (pinfunction "2_2") (pintype "passive"))
      (node (ref "R214") (pin "1") (pinfunction "1_1") (pintype "passive"))
    )
    (net (code "475") (name "Net-(Q28-E)") (class "Default")
      (node (ref "Q28") (pin "3") (pinfunction "E_3") (pintype "passive"))
      (node (ref "R213") (pin "1") (pinfunction "1_1") (pintype "passive"))
    )
    (net (code "476") (name "Net-(Q29-D)") (class "Default")
      (node (ref "Q29") (pin "3") (pinfunction "D_3") (pintype "passive"))
      (node (ref "R194") (pin "2") (pinfunction "2_2") (pintype "passive"))
    )
    (net (code "477") (name "Net-(Q30-S)") (class "Default")
      (node (ref "Q30") (pin "2") (pinfunction "S_2") (pintype "passive"))
      (node (ref "R215") (pin "2") (pinfunction "2_2") (pintype "passive"))
    )
    (net (code "478") (name "Net-(Q32-B)") (class "Default")
      (node (ref "Q32") (pin "1") (pinfunction "B_1") (pintype "passive"))
      (node (ref "R217") (pin "1") (pinfunction "1_1") (pintype "passive"))
    )
    (net (code "479") (name "Net-(Q32-C)") (class "Default")
      (node (ref "Q32") (pin "2") (pinfunction "C_2") (pintype "passive"))
      (node (ref "R168") (pin "2") (pinfunction "2_2") (pintype "passive"))
      (node (ref "SJMP3") (pin "2") (pinfunction "2_2") (pintype "passive"))
    )
    (net (code "480") (name "Net-(Q33-D)") (class "Default")
      (node (ref "Q33") (pin "3") (pinfunction "D_3") (pintype "passive"))
      (node (ref "R217") (pin "2") (pinfunction "2_2") (pintype "passive"))
    )
    (net (code "481") (name "Net-(Q34-B)") (class "Default")
      (node (ref "Q34") (pin "1") (pinfunction "B_1") (pintype "passive"))
      (node (ref "R244") (pin "2") (pinfunction "2_2") (pintype "passive"))
    )
    (net (code "482") (name "Net-(Q35-B)") (class "Default")
      (node (ref "Q35") (pin "1") (pinfunction "B_1") (pintype "passive"))
      (node (ref "Q35") (pin "2") (pinfunction "C_2") (pintype "passive"))
      (node (ref "Q36") (pin "1") (pinfunction "B_1") (pintype "passive"))
      (node (ref "R239") (pin "1") (pinfunction "1_1") (pintype "passive"))
      (node (ref "R240") (pin "1") (pinfunction "1_1") (pintype "passive"))
      (node (ref "R264") (pin "1") (pinfunction "1_1") (pintype "passive"))
      (node (ref "X12") (pin "2") (pinfunction "S_2") (pintype "passive"))
    )
    (net (code "483") (name "Net-(Q35-E)") (class "Default")
      (node (ref "Q35") (pin "3") (pinfunction "E_3") (pintype "passive"))
      (node (ref "R245") (pin "2") (pinfunction "2_2") (pintype "passive"))
    )
    (net (code "484") (name "Net-(Q36-E)") (class "Default")
      (node (ref "Q36") (pin "3") (pinfunction "E_3") (pintype "passive"))
      (node (ref "R246") (pin "2") (pinfunction "2_2") (pintype "passive"))
    )
    (net (code "485") (name "Net-(Q37-B)") (class "Default")
      (node (ref "Q37") (pin "1") (pinfunction "B_1") (pintype "passive"))
      (node (ref "R237") (pin "1") (pinfunction "1_1") (pintype "passive"))
    )
    (net (code "486") (name "Net-(Q38-B)") (class "Default")
      (node (ref "Q38") (pin "1") (pinfunction "B_1") (pintype "passive"))
      (node (ref "R248") (pin "2") (pinfunction "2_2") (pintype "passive"))
      (node (ref "R269") (pin "1") (pinfunction "1_1") (pintype "passive"))
    )
    (net (code "487") (name "Net-(Q38-E)") (class "Default")
      (node (ref "Q38") (pin "3") (pinfunction "E_3") (pintype "passive"))
      (node (ref "R268") (pin "1") (pinfunction "1_1") (pintype "passive"))
    )
    (net (code "488") (name "Net-(Q39-D)") (class "Default")
      (node (ref "Q39") (pin "3") (pinfunction "D_3") (pintype "passive"))
      (node (ref "R249") (pin "2") (pinfunction "2_2") (pintype "passive"))
    )
    (net (code "489") (name "Net-(Q40-S)") (class "Default")
      (node (ref "Q40") (pin "2") (pinfunction "S_2") (pintype "passive"))
      (node (ref "R270") (pin "2") (pinfunction "2_2") (pintype "passive"))
    )
    (net (code "490") (name "Net-(Q42-B)") (class "Default")
      (node (ref "Q42") (pin "1") (pinfunction "B_1") (pintype "passive"))
      (node (ref "R272") (pin "1") (pinfunction "1_1") (pintype "passive"))
    )
    (net (code "491") (name "Net-(Q42-C)") (class "Default")
      (node (ref "Q42") (pin "2") (pinfunction "C_2") (pintype "passive"))
      (node (ref "R223") (pin "2") (pinfunction "2_2") (pintype "passive"))
      (node (ref "SJMP4") (pin "2") (pinfunction "2_2") (pintype "passive"))
    )
    (net (code "492") (name "Net-(Q43-D)") (class "Default")
      (node (ref "Q43") (pin "3") (pinfunction "D_3") (pintype "passive"))
      (node (ref "R272") (pin "2") (pinfunction "2_2") (pintype "passive"))
    )
    (net (code "493") (name "Net-(Q44-B)") (class "Default")
      (node (ref "Q44") (pin "1") (pinfunction "B_1") (pintype "passive"))
      (node (ref "R299") (pin "2") (pinfunction "2_2") (pintype "passive"))
    )
    (net (code "494") (name "Net-(Q45-B)") (class "Default")
      (node (ref "Q45") (pin "1") (pinfunction "B_1") (pintype "passive"))
      (node (ref "Q45") (pin "2") (pinfunction "C_2") (pintype "passive"))
      (node (ref "Q46") (pin "1") (pinfunction "B_1") (pintype "passive"))
      (node (ref "R294") (pin "1") (pinfunction "1_1") (pintype "passive"))
      (node (ref "R295") (pin "1") (pinfunction "1_1") (pintype "passive"))
      (node (ref "R319") (pin "1") (pinfunction "1_1") (pintype "passive"))
      (node (ref "X15") (pin "2") (pinfunction "S_2") (pintype "passive"))
    )
    (net (code "495") (name "Net-(Q45-E)") (class "Default")
      (node (ref "Q45") (pin "3") (pinfunction "E_3") (pintype "passive"))
      (node (ref "R300") (pin "2") (pinfunction "2_2") (pintype "passive"))
    )
    (net (code "496") (name "Net-(Q46-E)") (class "Default")
      (node (ref "Q46") (pin "3") (pinfunction "E_3") (pintype "passive"))
      (node (ref "R301") (pin "2") (pinfunction "2_2") (pintype "passive"))
    )
    (net (code "497") (name "Net-(Q47-B)") (class "Default")
      (node (ref "Q47") (pin "1") (pinfunction "B_1") (pintype "passive"))
      (node (ref "R292") (pin "1") (pinfunction "1_1") (pintype "passive"))
    )
    (net (code "498") (name "Net-(Q48-B)") (class "Default")
      (node (ref "Q48") (pin "1") (pinfunction "B_1") (pintype "passive"))
      (node (ref "R303") (pin "2") (pinfunction "2_2") (pintype "passive"))
      (node (ref "R324") (pin "1") (pinfunction "1_1") (pintype "passive"))
    )
    (net (code "499") (name "Net-(Q48-E)") (class "Default")
      (node (ref "Q48") (pin "3") (pinfunction "E_3") (pintype "passive"))
      (node (ref "R323") (pin "1") (pinfunction "1_1") (pintype "passive"))
    )
    (net (code "500") (name "Net-(Q49-D)") (class "Default")
      (node (ref "Q49") (pin "3") (pinfunction "D_3") (pintype "passive"))
      (node (ref "R304") (pin "2") (pinfunction "2_2") (pintype "passive"))
    )
    (net (code "501") (name "Net-(Q50-S)") (class "Default")
      (node (ref "Q50") (pin "2") (pinfunction "S_2") (pintype "passive"))
      (node (ref "R325") (pin "2") (pinfunction "2_2") (pintype "passive"))
    )
    (net (code "502") (name "Net-(Q52-B)") (class "Default")
      (node (ref "Q52") (pin "1") (pinfunction "B_1") (pintype "passive"))
      (node (ref "R327") (pin "1") (pinfunction "1_1") (pintype "passive"))
    )
    (net (code "503") (name "Net-(Q52-C)") (class "Default")
      (node (ref "Q52") (pin "2") (pinfunction "C_2") (pintype "passive"))
      (node (ref "R278") (pin "2") (pinfunction "2_2") (pintype "passive"))
      (node (ref "SJMP5") (pin "2") (pinfunction "2_2") (pintype "passive"))
    )
    (net (code "504") (name "Net-(Q53-D)") (class "Default")
      (node (ref "Q53") (pin "3") (pinfunction "D_3") (pintype "passive"))
      (node (ref "R327") (pin "2") (pinfunction "2_2") (pintype "passive"))
    )
    (net (code "505") (name "Net-(Q101-B)") (class "Default")
      (node (ref "Q101") (pin "1") (pinfunction "B_1") (pintype "passive"))
      (node (ref "Q102") (pin "1") (pinfunction "B_1") (pintype "passive"))
      (node (ref "Q102") (pin "2") (pinfunction "C_2") (pintype "passive"))
      (node (ref "R101") (pin "1") (pinfunction "1_1") (pintype "passive"))
      (node (ref "R103") (pin "1") (pinfunction "1_1") (pintype "passive"))
      (node (ref "R104") (pin "1") (pinfunction "1_1") (pintype "passive"))
      (node (ref "X102") (pin "2") (pinfunction "S_2") (pintype "passive"))
    )
    (net (code "506") (name "Net-(Q101-E)") (class "Default")
      (node (ref "Q101") (pin "3") (pinfunction "E_3") (pintype "passive"))
      (node (ref "R102") (pin "2") (pinfunction "2_2") (pintype "passive"))
    )
    (net (code "507") (name "Net-(Q102-E)") (class "Default")
      (node (ref "Q102") (pin "3") (pinfunction "E_3") (pintype "passive"))
      (node (ref "R106") (pin "2") (pinfunction "2_2") (pintype "passive"))
    )
    (net (code "508") (name "Net-(Q103-B)") (class "Default")
      (node (ref "Q103") (pin "1") (pinfunction "B_1") (pintype "passive"))
      (node (ref "R116") (pin "2") (pinfunction "2_2") (pintype "passive"))
      (node (ref "R6") (pin "1") (pinfunction "1_1") (pintype "passive"))
    )
    (net (code "509") (name "Net-(Q103-E)") (class "Default")
      (node (ref "Q103") (pin "3") (pinfunction "E_3") (pintype "passive"))
      (node (ref "R5") (pin "1") (pinfunction "1_1") (pintype "passive"))
    )
    (net (code "510") (name "Net-(Q104-B)") (class "Default")
      (node (ref "Q104") (pin "1") (pinfunction "B_1") (pintype "passive"))
      (node (ref "R128") (pin "2") (pinfunction "2_2") (pintype "passive"))
    )
    (net (code "511") (name "Net-(Q105-B)") (class "Default")
      (node (ref "Q105") (pin "1") (pinfunction "B_1") (pintype "passive"))
      (node (ref "R126") (pin "1") (pinfunction "1_1") (pintype "passive"))
    )
    (net (code "512") (name "Net-(Q106-S)") (class "Default")
      (node (ref "Q106") (pin "2") (pinfunction "S_2") (pintype "passive"))
      (node (ref "R4") (pin "2") (pinfunction "2_2") (pintype "passive"))
    )
    (net (code "513") (name "Net-(Q107-D)") (class "Default")
      (node (ref "Q107") (pin "3") (pinfunction "D_3") (pintype "passive"))
      (node (ref "R138") (pin "2") (pinfunction "2_2") (pintype "passive"))
    )
    (net (code "514") (name "Net-(R14-Pad1)") (class "Default")
      (node (ref "R14") (pin "1") (pinfunction "1_1") (pintype "passive"))
      (node (ref "R7") (pin "2") (pinfunction "2_2") (pintype "passive"))
    )
    (net (code "515") (name "Net-(R32-Pad1)") (class "Default")
      (node (ref "R32") (pin "1") (pinfunction "1_1") (pintype "passive"))
      (node (ref "X1") (pin "21") (pinfunction "21_21") (pintype "passive"))
    )
    (net (code "516") (name "Net-(R44-Pad2)") (class "Default")
      (node (ref "R44") (pin "2") (pinfunction "2_2") (pintype "passive"))
      (node (ref "X1") (pin "16") (pinfunction "16_16") (pintype "passive"))
    )
    (net (code "517") (name "Net-(R67-Pad2)") (class "Default")
      (node (ref "R67") (pin "2") (pinfunction "2_2") (pintype "passive"))
      (node (ref "R69") (pin "1") (pinfunction "1_1") (pintype "passive"))
    )
    (net (code "518") (name "Net-(R87-Pad1)") (class "Default")
      (node (ref "R87") (pin "1") (pinfunction "1_1") (pintype "passive"))
      (node (ref "X4") (pin "21") (pinfunction "21_21") (pintype "passive"))
    )
    (net (code "519") (name "Net-(R99-Pad2)") (class "Default")
      (node (ref "R99") (pin "2") (pinfunction "2_2") (pintype "passive"))
      (node (ref "X4") (pin "16") (pinfunction "16_16") (pintype "passive"))
    )
    (net (code "520") (name "Net-(R115-Pad1)") (class "Default")
      (node (ref "R115") (pin "1") (pinfunction "1_1") (pintype "passive"))
      (node (ref "X101") (pin "21") (pinfunction "21_21") (pintype "passive"))
    )
    (net (code "521") (name "Net-(R127-Pad2)") (class "Default")
      (node (ref "R127") (pin "2") (pinfunction "2_2") (pintype "passive"))
      (node (ref "R129") (pin "1") (pinfunction "1_1") (pintype "passive"))
    )
    (net (code "522") (name "Net-(R140-Pad2)") (class "Default")
      (node (ref "R140") (pin "2") (pinfunction "2_2") (pintype "passive"))
      (node (ref "X101") (pin "16") (pinfunction "16_16") (pintype "passive"))
    )
    (net (code "523") (name "Net-(R166-Pad2)") (class "Default")
      (node (ref "R166") (pin "2") (pinfunction "2_2") (pintype "passive"))
      (node (ref "R168") (pin "1") (pinfunction "1_1") (pintype "passive"))
    )
    (net (code "524") (name "Net-(R186-Pad1)") (class "Default")
      (node (ref "R186") (pin "1") (pinfunction "1_1") (pintype "passive"))
      (node (ref "X7") (pin "21") (pinfunction "21_21") (pintype "passive"))
    )
    (net (code "525") (name "Net-(R198-Pad2)") (class "Default")
      (node (ref "R198") (pin "2") (pinfunction "2_2") (pintype "passive"))
      (node (ref "X7") (pin "16") (pinfunction "16_16") (pintype "passive"))
    )
    (net (code "526") (name "Net-(R221-Pad2)") (class "Default")
      (node (ref "R221") (pin "2") (pinfunction "2_2") (pintype "passive"))
      (node (ref "R223") (pin "1") (pinfunction "1_1") (pintype "passive"))
    )
    (net (code "527") (name "Net-(R241-Pad1)") (class "Default")
      (node (ref "R241") (pin "1") (pinfunction "1_1") (pintype "passive"))
      (node (ref "X10") (pin "21") (pinfunction "21_21") (pintype "passive"))
    )
    (net (code "528") (name "Net-(R253-Pad2)") (class "Default")
      (node (ref "R253") (pin "2") (pinfunction "2_2") (pintype "passive"))
      (node (ref "X10") (pin "16") (pinfunction "16_16") (pintype "passive"))
    )
    (net (code "529") (name "Net-(R276-Pad2)") (class "Default")
      (node (ref "R276") (pin "2") (pinfunction "2_2") (pintype "passive"))
      (node (ref "R278") (pin "1") (pinfunction "1_1") (pintype "passive"))
    )
    (net (code "530") (name "Net-(R296-Pad1)") (class "Default")
      (node (ref "R296") (pin "1") (pinfunction "1_1") (pintype "passive"))
      (node (ref "X13") (pin "21") (pinfunction "21_21") (pintype "passive"))
    )
    (net (code "531") (name "Net-(R308-Pad2)") (class "Default")
      (node (ref "R308") (pin "2") (pinfunction "2_2") (pintype "passive"))
      (node (ref "X13") (pin "16") (pinfunction "16_16") (pintype "passive"))
    )
    (net (code "532") (name "V+") (class "Default")
      (node (ref "D1") (pin "1") (pinfunction "+_1") (pintype "passive"))
      (node (ref "D15") (pin "1") (pinfunction "+_1") (pintype "passive"))
      (node (ref "D29") (pin "1") (pinfunction "+_1") (pintype "passive"))
      (node (ref "D43") (pin "1") (pinfunction "+_1") (pintype "passive"))
      (node (ref "D57") (pin "1") (pinfunction "+_1") (pintype "passive"))
      (node (ref "D71") (pin "1") (pinfunction "+_1") (pintype "passive"))
      (node (ref "Q104") (pin "3") (pinfunction "E_3") (pintype "passive"))
      (node (ref "Q105") (pin "3") (pinfunction "E_3") (pintype "passive"))
      (node (ref "Q12") (pin "3") (pinfunction "E_3") (pintype "passive"))
      (node (ref "Q14") (pin "3") (pinfunction "E_3") (pintype "passive"))
      (node (ref "Q17") (pin "3") (pinfunction "E_3") (pintype "passive"))
      (node (ref "Q2") (pin "3") (pinfunction "E_3") (pintype "passive"))
      (node (ref "Q22") (pin "3") (pinfunction "E_3") (pintype "passive"))
      (node (ref "Q24") (pin "3") (pinfunction "E_3") (pintype "passive"))
      (node (ref "Q27") (pin "3") (pinfunction "E_3") (pintype "passive"))
      (node (ref "Q32") (pin "3") (pinfunction "E_3") (pintype "passive"))
      (node (ref "Q34") (pin "3") (pinfunction "E_3") (pintype "passive"))
      (node (ref "Q37") (pin "3") (pinfunction "E_3") (pintype "passive"))
      (node (ref "Q4") (pin "3") (pinfunction "E_3") (pintype "passive"))
      (node (ref "Q42") (pin "3") (pinfunction "E_3") (pintype "passive"))
      (node (ref "Q44") (pin "3") (pinfunction "E_3") (pintype "passive"))
      (node (ref "Q47") (pin "3") (pinfunction "E_3") (pintype "passive"))
      (node (ref "Q52") (pin "3") (pinfunction "E_3") (pintype "passive"))
      (node (ref "Q7") (pin "3") (pinfunction "E_3") (pintype "passive"))
      (node (ref "SJMP") (pin "1") (pinfunction "1_1") (pintype "passive"))
      (node (ref "SJMP1") (pin "1") (pinfunction "1_1") (pintype "passive"))
      (node (ref "SJMP2") (pin "1") (pinfunction "1_1") (pintype "passive"))
      (node (ref "SJMP3") (pin "1") (pinfunction "1_1") (pintype "passive"))
      (node (ref "SJMP4") (pin "1") (pinfunction "1_1") (pintype "passive"))
      (node (ref "SJMP5") (pin "1") (pinfunction "1_1") (pintype "passive"))
      (node (ref "X1") (pin "6") (pinfunction "6_6") (pintype "passive"))
      (node (ref "X10") (pin "6") (pinfunction "6_6") (pintype "passive"))
      (node (ref "X101") (pin "6") (pinfunction "6_6") (pintype "passive"))
      (node (ref "X13") (pin "6") (pinfunction "6_6") (pintype "passive"))
      (node (ref "X4") (pin "6") (pinfunction "6_6") (pintype "passive"))
      (node (ref "X7") (pin "6") (pinfunction "6_6") (pintype "passive"))
    )
    (net (code "533") (name "VCC") (class "Default")
      (node (ref "6V") (pin "TP") (pinfunction "PP_TP") (pintype "input"))
      (node (ref "6V1") (pin "TP") (pinfunction "PP_TP") (pintype "input"))
      (node (ref "6V2") (pin "TP") (pinfunction "PP_TP") (pintype "input"))
      (node (ref "6V3") (pin "TP") (pinfunction "PP_TP") (pintype "input"))
      (node (ref "6V4") (pin "TP") (pinfunction "PP_TP") (pintype "input"))
      (node (ref "6V5") (pin "TP") (pinfunction "PP_TP") (pintype "input"))
      (node (ref "C104") (pin "1") (pinfunction "1_1") (pintype "passive"))
      (node (ref "C17") (pin "1") (pinfunction "1_1") (pintype "passive"))
      (node (ref "C29") (pin "1") (pinfunction "1_1") (pintype "passive"))
      (node (ref "C4") (pin "1") (pinfunction "1_1") (pintype "passive"))
      (node (ref "C41") (pin "1") (pinfunction "1_1") (pintype "passive"))
      (node (ref "C53") (pin "1") (pinfunction "1_1") (pintype "passive"))
      (node (ref "IC101") (pin "8") (pinfunction "V+_8") (pintype "power_in"))
      (node (ref "IC102") (pin "1") (pinfunction "OUT_1") (pintype "passive"))
      (node (ref "IC108") (pin "3") (pinfunction "V+_3") (pintype "power_in"))
      (node (ref "IC13") (pin "3") (pinfunction "V+_3") (pintype "power_in"))
      (node (ref "IC14") (pin "1") (pinfunction "OUT_1") (pintype "passive"))
      (node (ref "IC18") (pin "8") (pinfunction "V+_8") (pintype "power_in"))
      (node (ref "IC22") (pin "3") (pinfunction "V+_3") (pintype "power_in"))
      (node (ref "IC23") (pin "1") (pinfunction "OUT_1") (pintype "passive"))
      (node (ref "IC27") (pin "8") (pinfunction "V+_8") (pintype "power_in"))
      (node (ref "IC31") (pin "3") (pinfunction "V+_3") (pintype "power_in"))
      (node (ref "IC32") (pin "1") (pinfunction "OUT_1") (pintype "passive"))
      (node (ref "IC36") (pin "8") (pinfunction "V+_8") (pintype "power_in"))
      (node (ref "IC4") (pin "3") (pinfunction "V+_3") (pintype "power_in"))
      (node (ref "IC40") (pin "3") (pinfunction "V+_3") (pintype "power_in"))
      (node (ref "IC41") (pin "1") (pinfunction "OUT_1") (pintype "passive"))
      (node (ref "IC45") (pin "8") (pinfunction "V+_8") (pintype "power_in"))
      (node (ref "IC5") (pin "1") (pinfunction "OUT_1") (pintype "passive"))
      (node (ref "IC9") (pin "8") (pinfunction "V+_8") (pintype "power_in"))
      (node (ref "R113") (pin "2") (pinfunction "2_2") (pintype "passive"))
      (node (ref "R121") (pin "2") (pinfunction "2_2") (pintype "passive"))
      (node (ref "R124") (pin "1") (pinfunction "1_1") (pintype "passive"))
      (node (ref "R131") (pin "2") (pinfunction "2_2") (pintype "passive"))
      (node (ref "R142") (pin "2") (pinfunction "2_2") (pintype "passive"))
      (node (ref "R152") (pin "2") (pinfunction "2_2") (pintype "passive"))
      (node (ref "R175") (pin "2") (pinfunction "2_2") (pintype "passive"))
      (node (ref "R178") (pin "2") (pinfunction "2_2") (pintype "passive"))
      (node (ref "R181") (pin "1") (pinfunction "1_1") (pintype "passive"))
      (node (ref "R188") (pin "2") (pinfunction "2_2") (pintype "passive"))
      (node (ref "R207") (pin "2") (pinfunction "2_2") (pintype "passive"))
      (node (ref "R21") (pin "2") (pinfunction "2_2") (pintype "passive"))
      (node (ref "R230") (pin "2") (pinfunction "2_2") (pintype "passive"))
      (node (ref "R233") (pin "2") (pinfunction "2_2") (pintype "passive"))
      (node (ref "R236") (pin "1") (pinfunction "1_1") (pintype "passive"))
      (node (ref "R24") (pin "2") (pinfunction "2_2") (pintype "passive"))
      (node (ref "R243") (pin "2") (pinfunction "2_2") (pintype "passive"))
      (node (ref "R262") (pin "2") (pinfunction "2_2") (pintype "passive"))
      (node (ref "R27") (pin "1") (pinfunction "1_1") (pintype "passive"))
      (node (ref "R285") (pin "2") (pinfunction "2_2") (pintype "passive"))
      (node (ref "R288") (pin "2") (pinfunction "2_2") (pintype "passive"))
      (node (ref "R291") (pin "1") (pinfunction "1_1") (pintype "passive"))
      (node (ref "R298") (pin "2") (pinfunction "2_2") (pintype "passive"))
      (node (ref "R317") (pin "2") (pinfunction "2_2") (pintype "passive"))
      (node (ref "R34") (pin "2") (pinfunction "2_2") (pintype "passive"))
      (node (ref "R53") (pin "2") (pinfunction "2_2") (pintype "passive"))
      (node (ref "R76") (pin "2") (pinfunction "2_2") (pintype "passive"))
      (node (ref "R79") (pin "2") (pinfunction "2_2") (pintype "passive"))
      (node (ref "R82") (pin "1") (pinfunction "1_1") (pintype "passive"))
      (node (ref "R89") (pin "2") (pinfunction "2_2") (pintype "passive"))
    )
    (net (code "534") (name "unconnected-(IC1A-Q6-Pad7)") (class "Default")
      (node (ref "IC1") (pin "7") (pinfunction "Q6_7") (pintype "output"))
    )
    (net (code "535") (name "unconnected-(IC1A-Q7-Pad4)") (class "Default")
      (node (ref "IC1") (pin "4") (pinfunction "Q7_4") (pintype "output"))
    )
    (net (code "536") (name "unconnected-(IC1A-Q8-Pad9)") (class "Default")
      (node (ref "IC1") (pin "9") (pinfunction "Q8_9") (pintype "output"))
    )
    (net (code "537") (name "unconnected-(IC1A-Q9-Pad5)") (class "Default")
      (node (ref "IC1") (pin "5") (pinfunction "Q9_5") (pintype "output"))
    )
    (net (code "538") (name "unconnected-(IC6-DIS-Pad7)") (class "Default")
      (node (ref "IC6") (pin "7") (pinfunction "DIS_7") (pintype "input"))
    )
    (net (code "539") (name "unconnected-(IC7A-Q-Pad6)") (class "Default")
      (node (ref "IC7") (pin "6") (pinfunction "Q_6") (pintype "output"))
    )
    (net (code "540") (name "unconnected-(IC7B-Q-Pad10)") (class "Default")
      (node (ref "IC7") (pin "10") (pinfunction "Q_10") (pintype "output"))
    )
    (net (code "541") (name "unconnected-(IC10A-Q6-Pad7)") (class "Default")
      (node (ref "IC10") (pin "7") (pinfunction "Q6_7") (pintype "output"))
    )
    (net (code "542") (name "unconnected-(IC10A-Q7-Pad4)") (class "Default")
      (node (ref "IC10") (pin "4") (pinfunction "Q7_4") (pintype "output"))
    )
    (net (code "543") (name "unconnected-(IC10A-Q8-Pad9)") (class "Default")
      (node (ref "IC10") (pin "9") (pinfunction "Q8_9") (pintype "output"))
    )
    (net (code "544") (name "unconnected-(IC10A-Q9-Pad5)") (class "Default")
      (node (ref "IC10") (pin "5") (pinfunction "Q9_5") (pintype "output"))
    )
    (net (code "545") (name "unconnected-(IC15-DIS-Pad7)") (class "Default")
      (node (ref "IC15") (pin "7") (pinfunction "DIS_7") (pintype "input"))
    )
    (net (code "546") (name "unconnected-(IC16A-Q-Pad6)") (class "Default")
      (node (ref "IC16") (pin "6") (pinfunction "Q_6") (pintype "output"))
    )
    (net (code "547") (name "unconnected-(IC16B-Q-Pad10)") (class "Default")
      (node (ref "IC16") (pin "10") (pinfunction "Q_10") (pintype "output"))
    )
    (net (code "548") (name "unconnected-(IC19A-Q6-Pad7)") (class "Default")
      (node (ref "IC19") (pin "7") (pinfunction "Q6_7") (pintype "output"))
    )
    (net (code "549") (name "unconnected-(IC19A-Q7-Pad4)") (class "Default")
      (node (ref "IC19") (pin "4") (pinfunction "Q7_4") (pintype "output"))
    )
    (net (code "550") (name "unconnected-(IC19A-Q8-Pad9)") (class "Default")
      (node (ref "IC19") (pin "9") (pinfunction "Q8_9") (pintype "output"))
    )
    (net (code "551") (name "unconnected-(IC19A-Q9-Pad5)") (class "Default")
      (node (ref "IC19") (pin "5") (pinfunction "Q9_5") (pintype "output"))
    )
    (net (code "552") (name "unconnected-(IC24-DIS-Pad7)") (class "Default")
      (node (ref "IC24") (pin "7") (pinfunction "DIS_7") (pintype "input"))
    )
    (net (code "553") (name "unconnected-(IC25A-Q-Pad6)") (class "Default")
      (node (ref "IC25") (pin "6") (pinfunction "Q_6") (pintype "output"))
    )
    (net (code "554") (name "unconnected-(IC25B-Q-Pad10)") (class "Default")
      (node (ref "IC25") (pin "10") (pinfunction "Q_10") (pintype "output"))
    )
    (net (code "555") (name "unconnected-(IC28A-Q6-Pad7)") (class "Default")
      (node (ref "IC28") (pin "7") (pinfunction "Q6_7") (pintype "output"))
    )
    (net (code "556") (name "unconnected-(IC28A-Q7-Pad4)") (class "Default")
      (node (ref "IC28") (pin "4") (pinfunction "Q7_4") (pintype "output"))
    )
    (net (code "557") (name "unconnected-(IC28A-Q8-Pad9)") (class "Default")
      (node (ref "IC28") (pin "9") (pinfunction "Q8_9") (pintype "output"))
    )
    (net (code "558") (name "unconnected-(IC28A-Q9-Pad5)") (class "Default")
      (node (ref "IC28") (pin "5") (pinfunction "Q9_5") (pintype "output"))
    )
    (net (code "559") (name "unconnected-(IC33-DIS-Pad7)") (class "Default")
      (node (ref "IC33") (pin "7") (pinfunction "DIS_7") (pintype "input"))
    )
    (net (code "560") (name "unconnected-(IC34A-Q-Pad6)") (class "Default")
      (node (ref "IC34") (pin "6") (pinfunction "Q_6") (pintype "output"))
    )
    (net (code "561") (name "unconnected-(IC34B-Q-Pad10)") (class "Default")
      (node (ref "IC34") (pin "10") (pinfunction "Q_10") (pintype "output"))
    )
    (net (code "562") (name "unconnected-(IC37A-Q6-Pad7)") (class "Default")
      (node (ref "IC37") (pin "7") (pinfunction "Q6_7") (pintype "output"))
    )
    (net (code "563") (name "unconnected-(IC37A-Q7-Pad4)") (class "Default")
      (node (ref "IC37") (pin "4") (pinfunction "Q7_4") (pintype "output"))
    )
    (net (code "564") (name "unconnected-(IC37A-Q8-Pad9)") (class "Default")
      (node (ref "IC37") (pin "9") (pinfunction "Q8_9") (pintype "output"))
    )
    (net (code "565") (name "unconnected-(IC37A-Q9-Pad5)") (class "Default")
      (node (ref "IC37") (pin "5") (pinfunction "Q9_5") (pintype "output"))
    )
    (net (code "566") (name "unconnected-(IC42-DIS-Pad7)") (class "Default")
      (node (ref "IC42") (pin "7") (pinfunction "DIS_7") (pintype "input"))
    )
    (net (code "567") (name "unconnected-(IC43A-Q-Pad6)") (class "Default")
      (node (ref "IC43") (pin "6") (pinfunction "Q_6") (pintype "output"))
    )
    (net (code "568") (name "unconnected-(IC43B-Q-Pad10)") (class "Default")
      (node (ref "IC43") (pin "10") (pinfunction "Q_10") (pintype "output"))
    )
    (net (code "569") (name "unconnected-(IC105A-Q6-Pad7)") (class "Default")
      (node (ref "IC105") (pin "7") (pinfunction "Q6_7") (pintype "output"))
    )
    (net (code "570") (name "unconnected-(IC105A-Q7-Pad4)") (class "Default")
      (node (ref "IC105") (pin "4") (pinfunction "Q7_4") (pintype "output"))
    )
    (net (code "571") (name "unconnected-(IC105A-Q8-Pad9)") (class "Default")
      (node (ref "IC105") (pin "9") (pinfunction "Q8_9") (pintype "output"))
    )
    (net (code "572") (name "unconnected-(IC105A-Q9-Pad5)") (class "Default")
      (node (ref "IC105") (pin "5") (pinfunction "Q9_5") (pintype "output"))
    )
    (net (code "573") (name "unconnected-(IC110-DIS-Pad7)") (class "Default")
      (node (ref "IC110") (pin "7") (pinfunction "DIS_7") (pintype "input"))
    )
    (net (code "574") (name "unconnected-(IC111A-Q-Pad6)") (class "Default")
      (node (ref "IC111") (pin "6") (pinfunction "Q_6") (pintype "output"))
    )
    (net (code "575") (name "unconnected-(IC111B-Q-Pad10)") (class "Default")
      (node (ref "IC111") (pin "10") (pinfunction "Q_10") (pintype "output"))
    )
    (net (code "576") (name "unconnected-(X1-Pad20)") (class "Default")
      (node (ref "X1") (pin "20") (pinfunction "20_20") (pintype "passive"))
    )
    (net (code "577") (name "unconnected-(X1-Pad24)") (class "Default")
      (node (ref "X1") (pin "24") (pinfunction "24_24") (pintype "passive"))
    )
    (net (code "578") (name "unconnected-(X4-Pad20)") (class "Default")
      (node (ref "X4") (pin "20") (pinfunction "20_20") (pintype "passive"))
    )
    (net (code "579") (name "unconnected-(X4-Pad24)") (class "Default")
      (node (ref "X4") (pin "24") (pinfunction "24_24") (pintype "passive"))
    )
    (net (code "580") (name "unconnected-(X7-Pad20)") (class "Default")
      (node (ref "X7") (pin "20") (pinfunction "20_20") (pintype "passive"))
    )
    (net (code "581") (name "unconnected-(X7-Pad24)") (class "Default")
      (node (ref "X7") (pin "24") (pinfunction "24_24") (pintype "passive"))
    )
    (net (code "582") (name "unconnected-(X10-Pad20)") (class "Default")
      (node (ref "X10") (pin "20") (pinfunction "20_20") (pintype "passive"))
    )
    (net (code "583") (name "unconnected-(X10-Pad24)") (class "Default")
      (node (ref "X10") (pin "24") (pinfunction "24_24") (pintype "passive"))
    )
    (net (code "584") (name "unconnected-(X13-Pad20)") (class "Default")
      (node (ref "X13") (pin "20") (pinfunction "20_20") (pintype "passive"))
    )
    (net (code "585") (name "unconnected-(X13-Pad24)") (class "Default")
      (node (ref "X13") (pin "24") (pinfunction "24_24") (pintype "passive"))
    )
    (net (code "586") (name "unconnected-(X101-Pad20)") (class "Default")
      (node (ref "X101") (pin "20") (pinfunction "20_20") (pintype "passive"))
    )
    (net (code "587") (name "unconnected-(X101-Pad24)") (class "Default")
      (node (ref "X101") (pin "24") (pinfunction "24_24") (pintype "passive"))
    )
  )
)
